# PDNode-600_Pro1.net
KiCad netlist of a schematic drawn in EAGLE
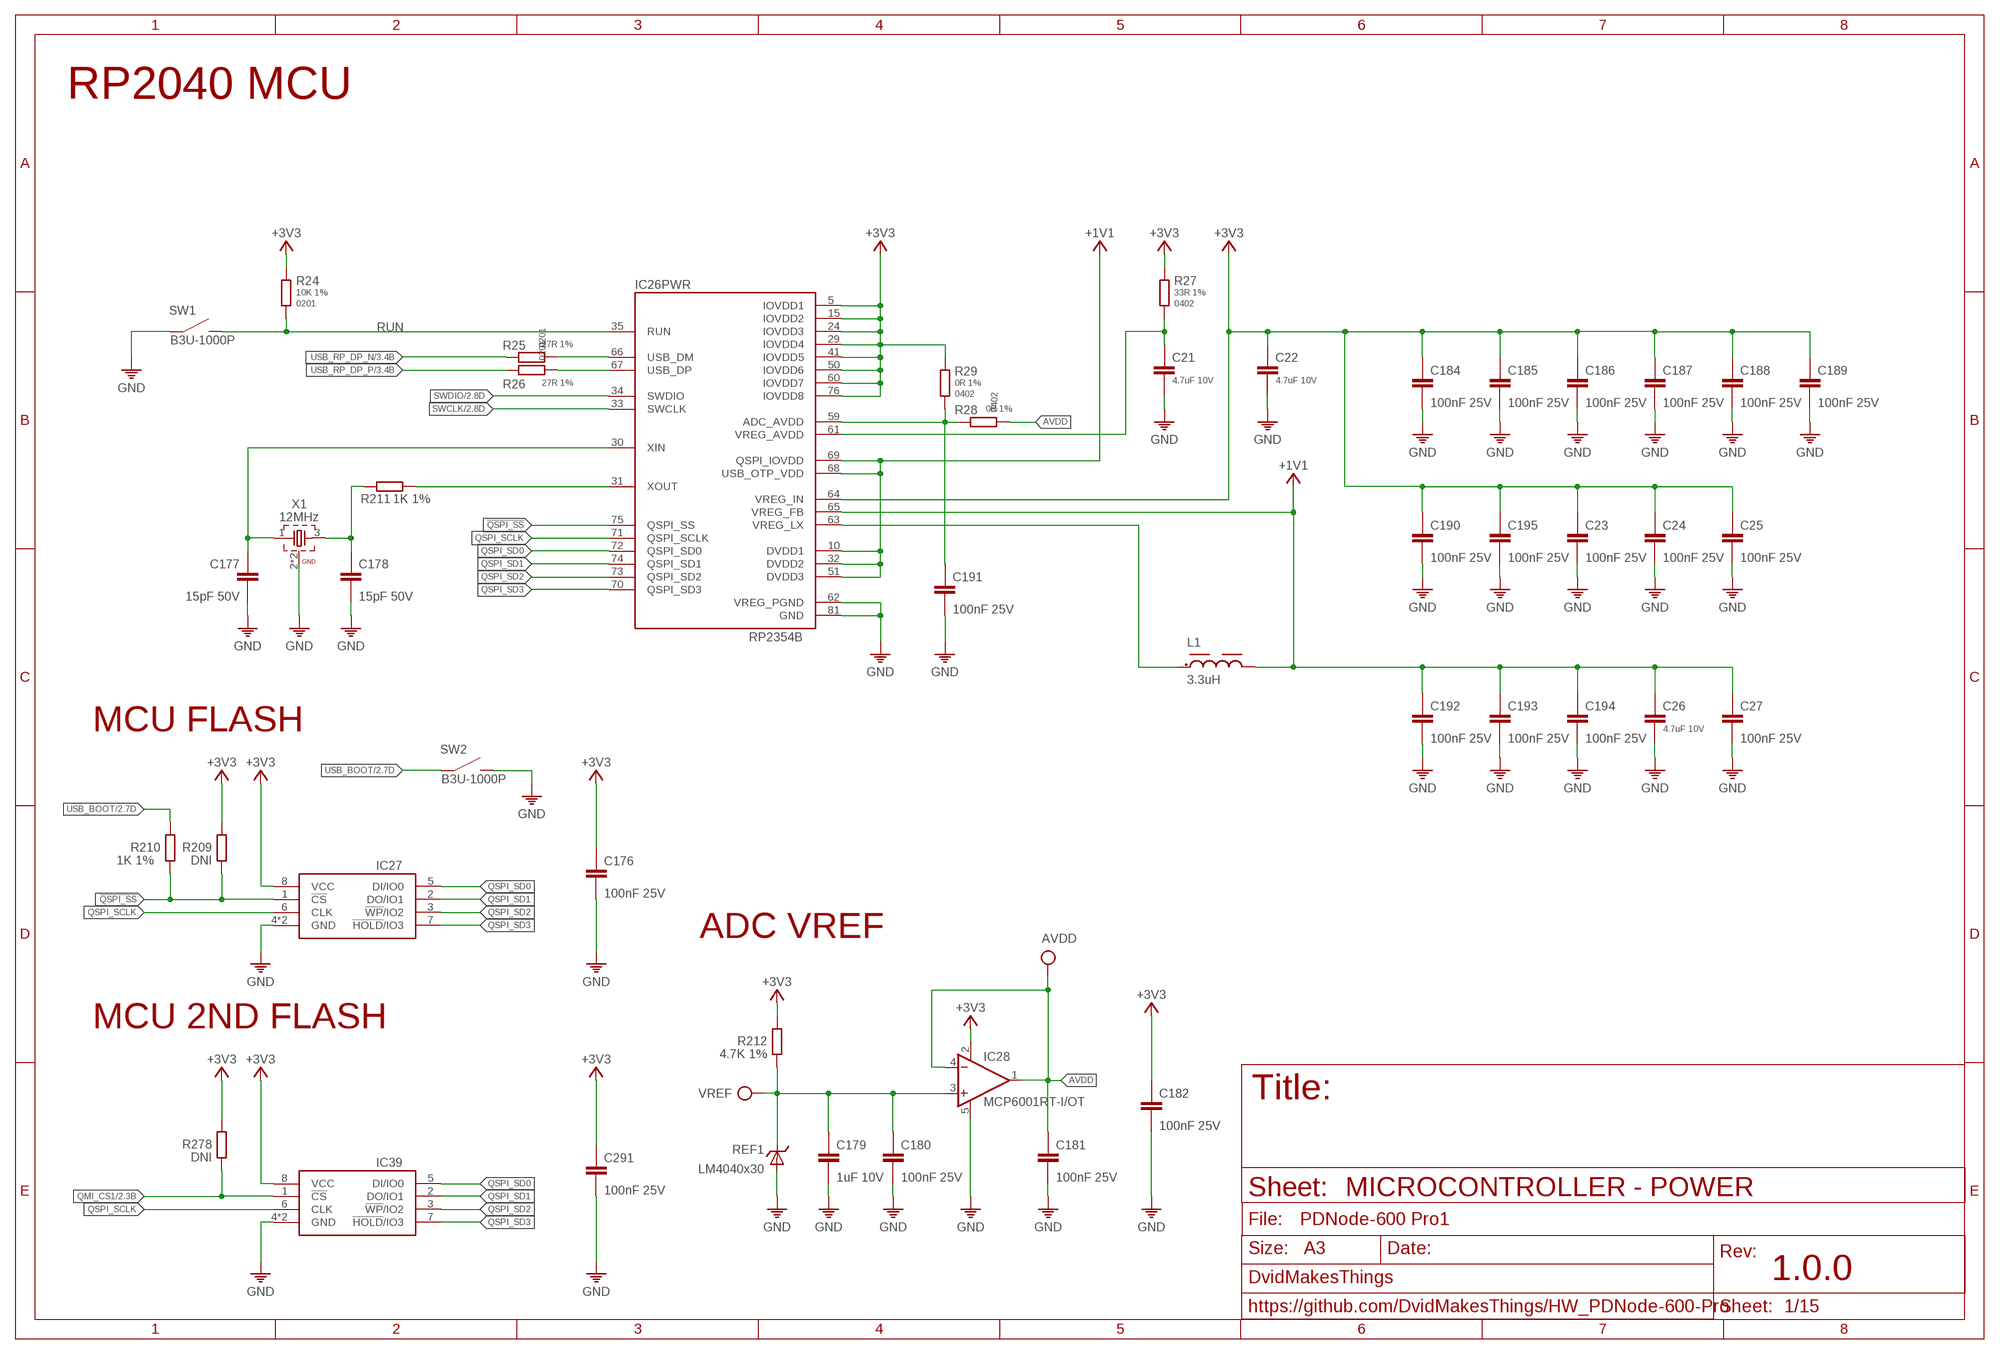
[diagram p0: schematic, sheet 1]
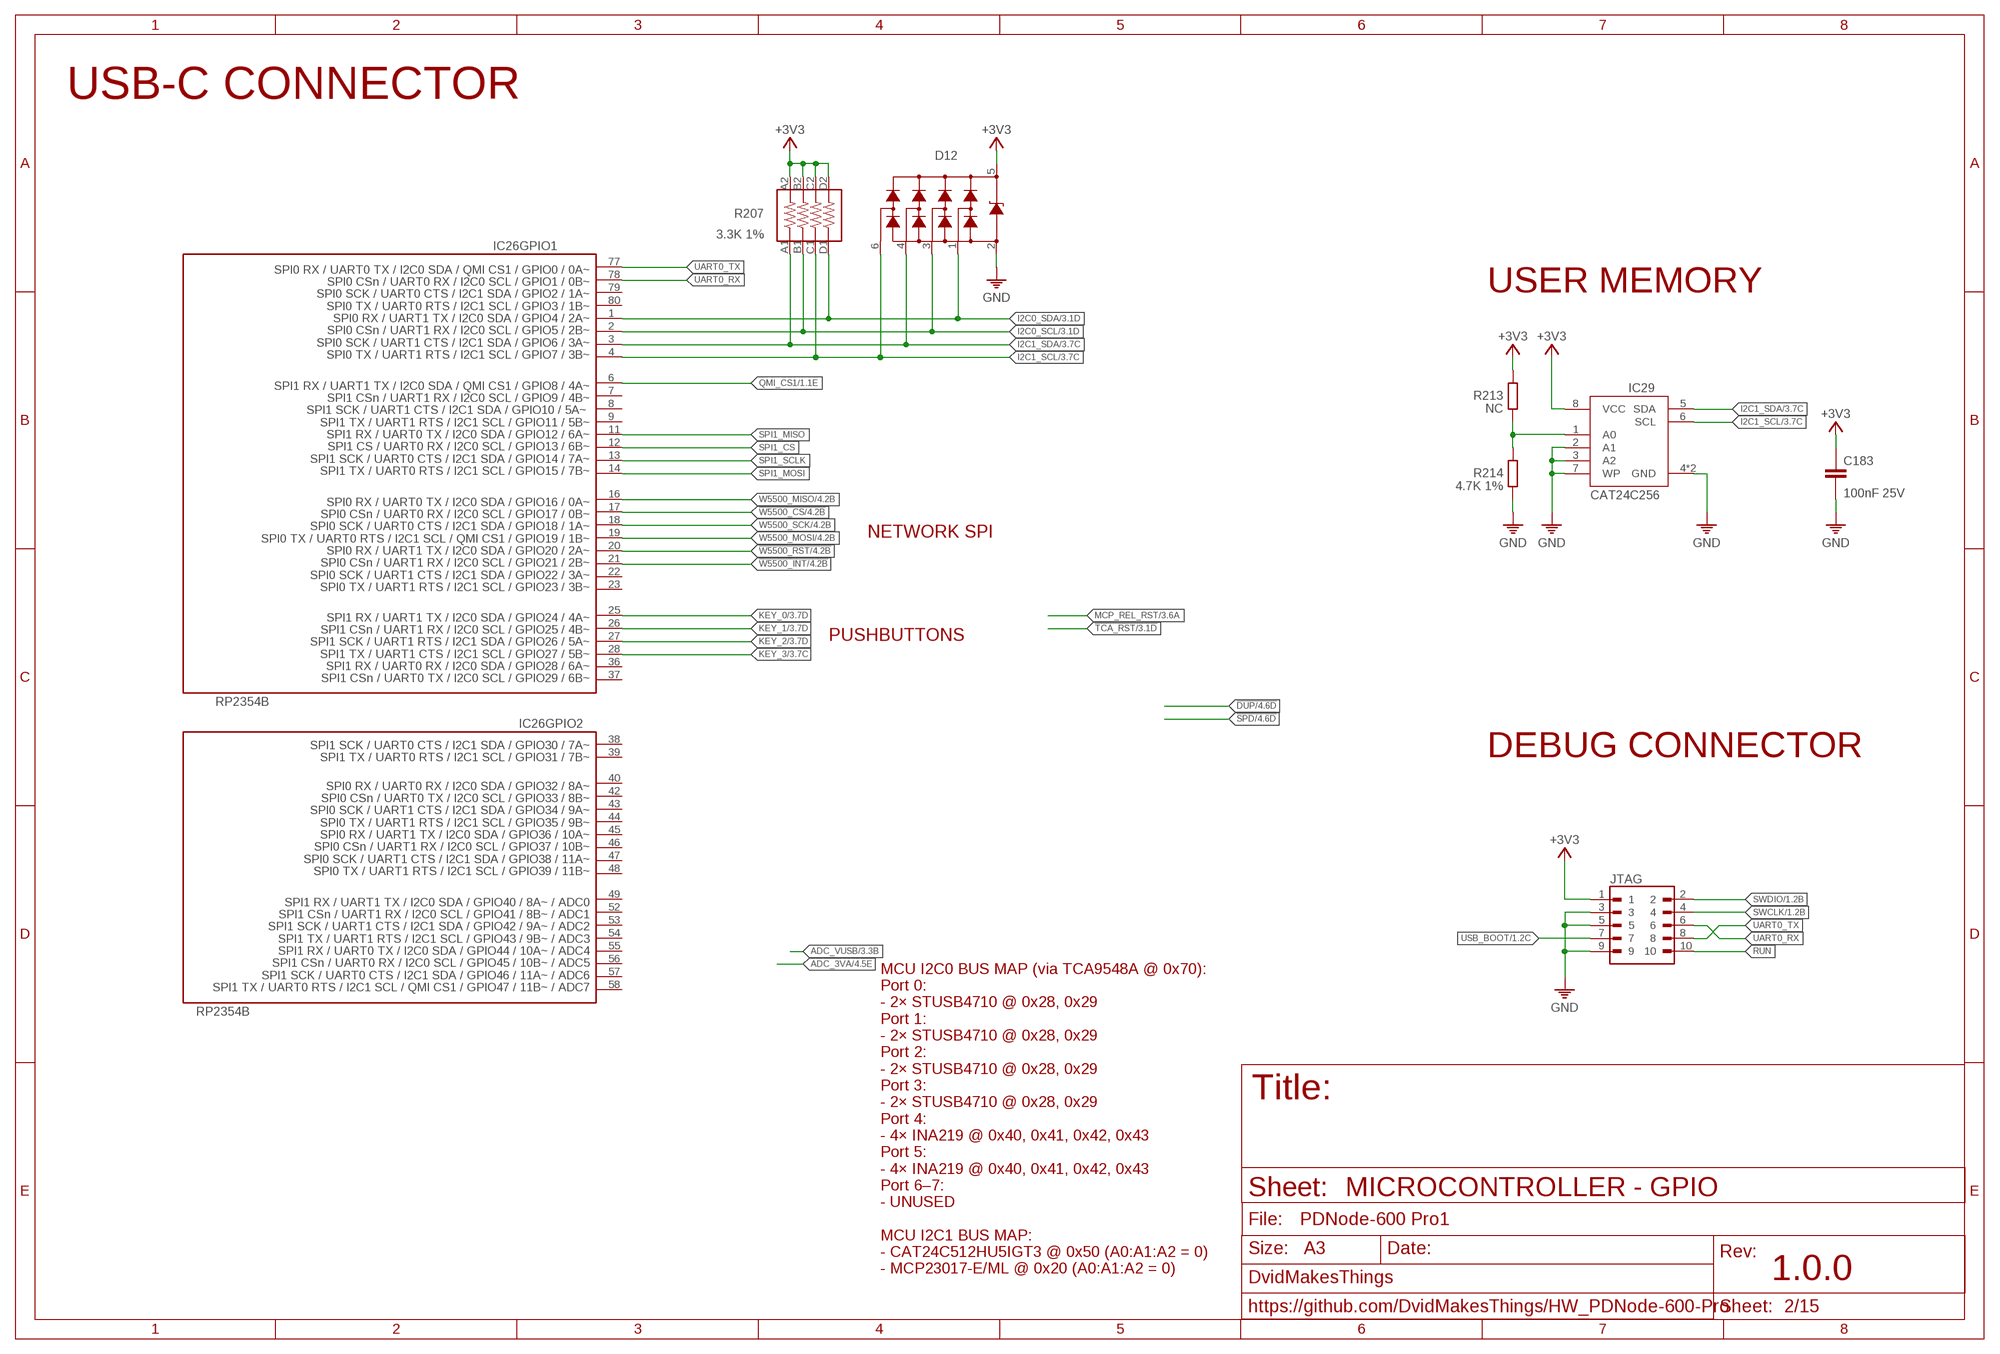
[diagram p1: schematic, sheet 2]
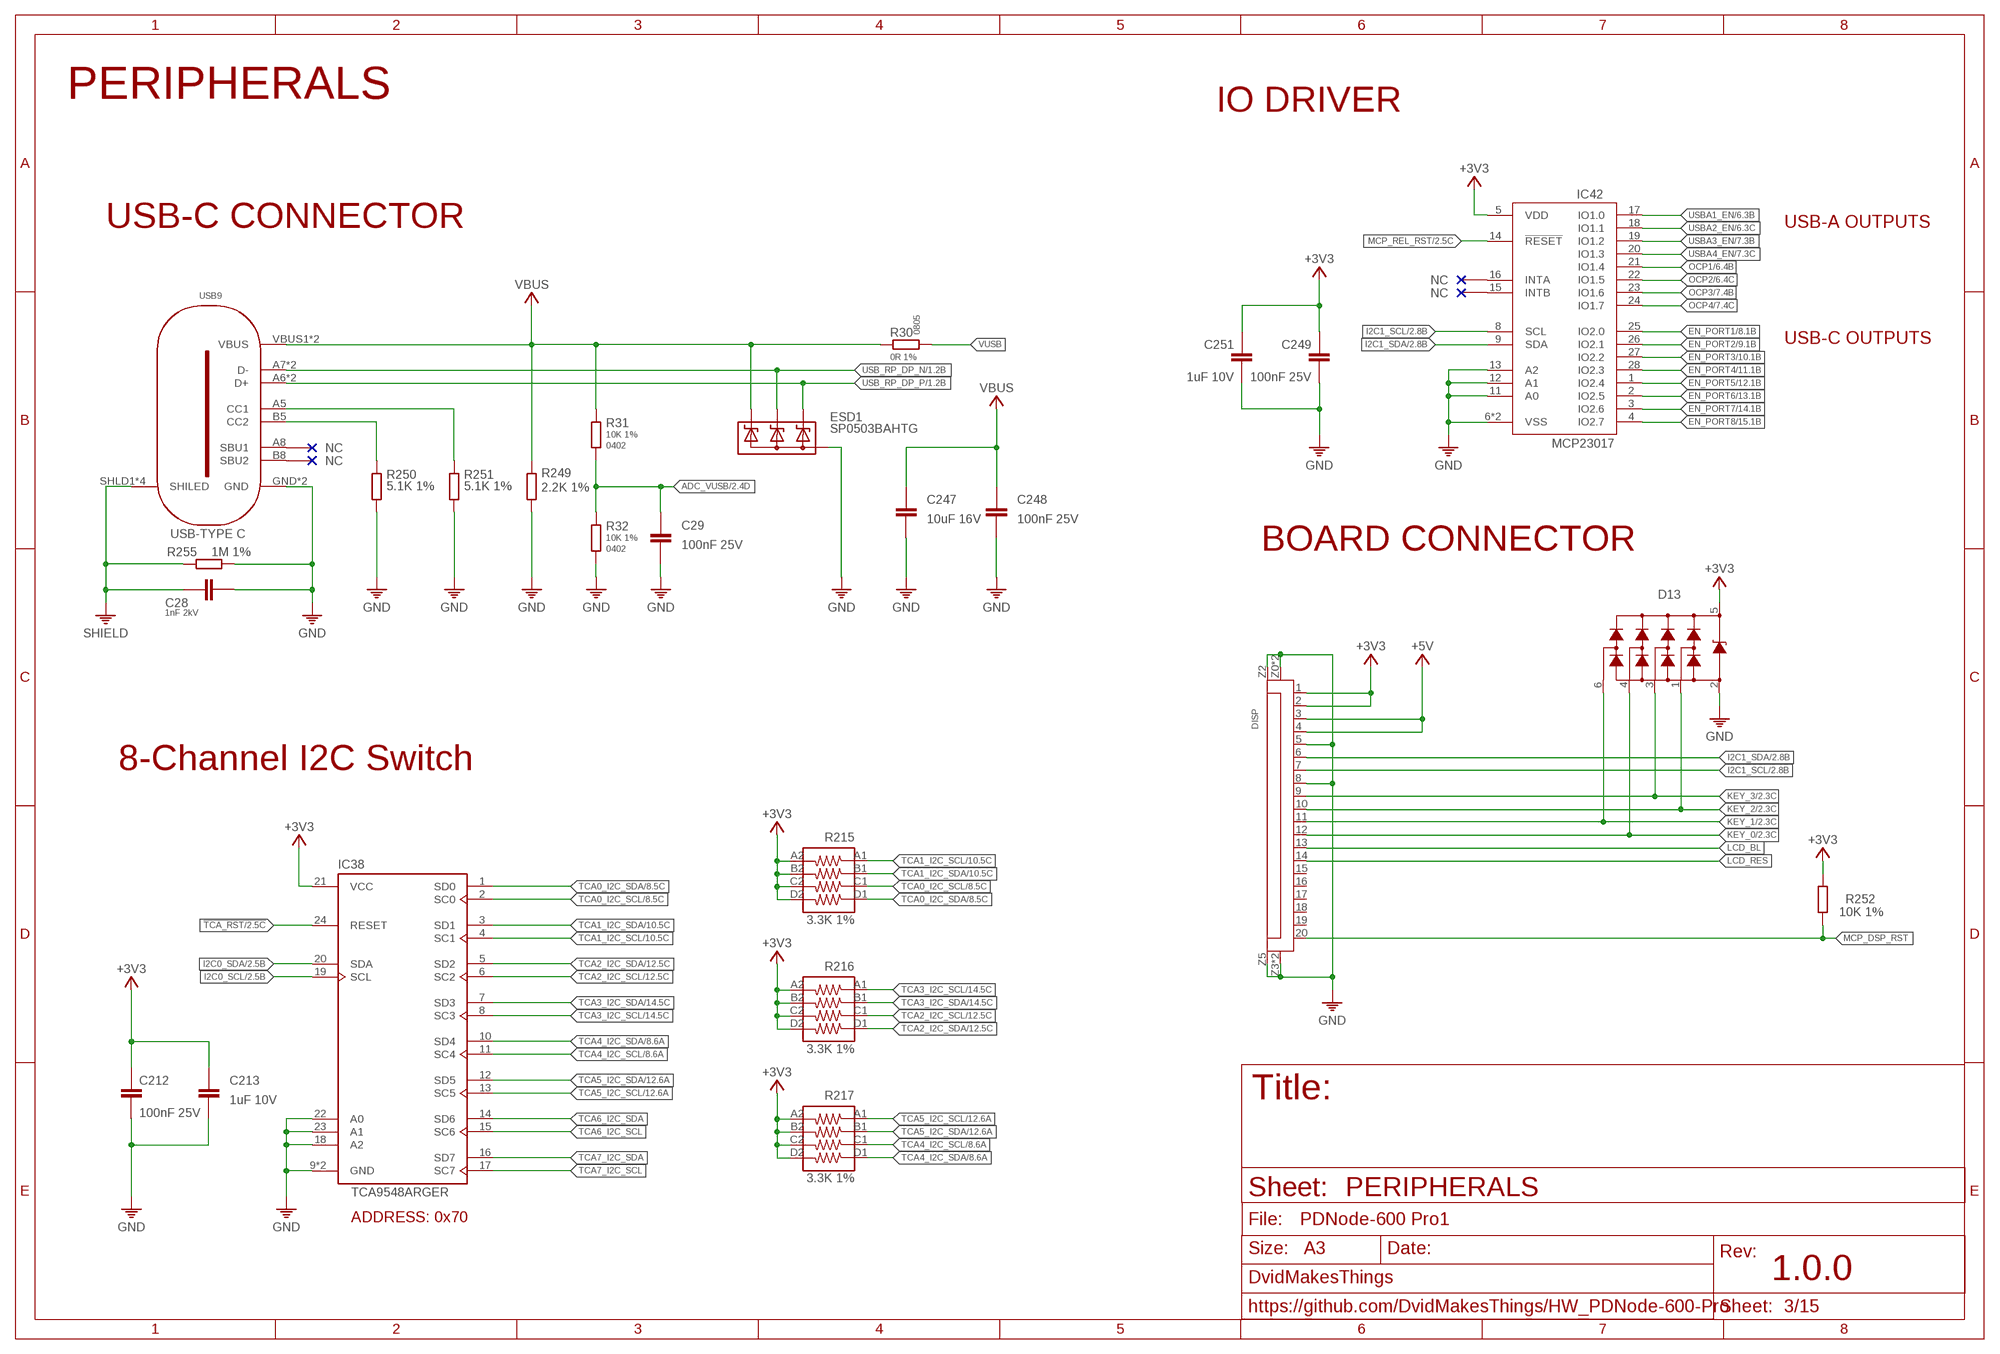
[diagram p2: schematic, sheet 3]
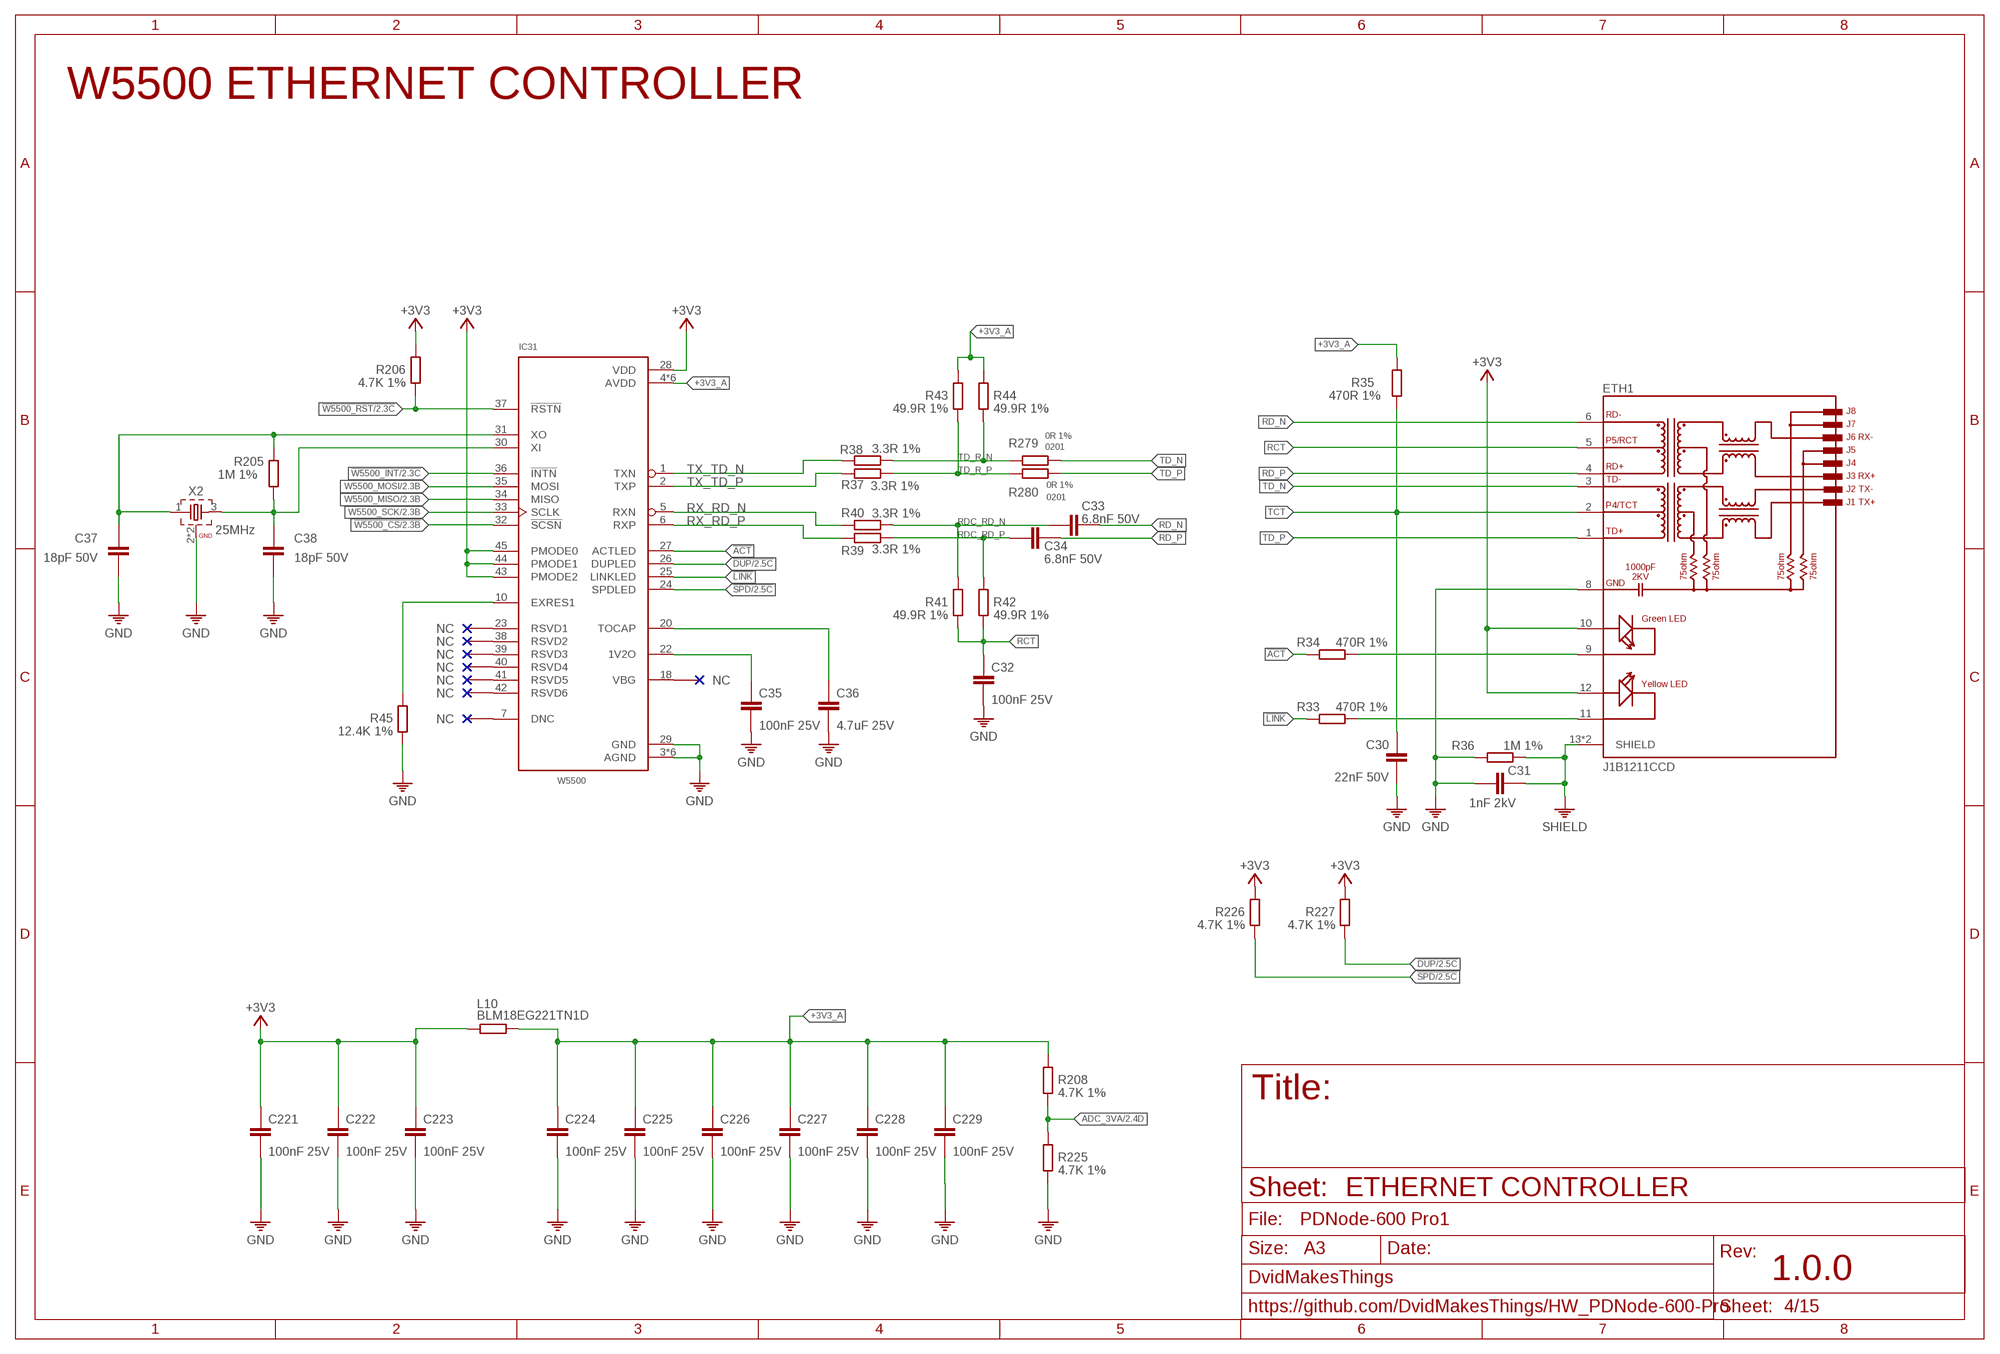
[diagram p3: schematic, sheet 4]
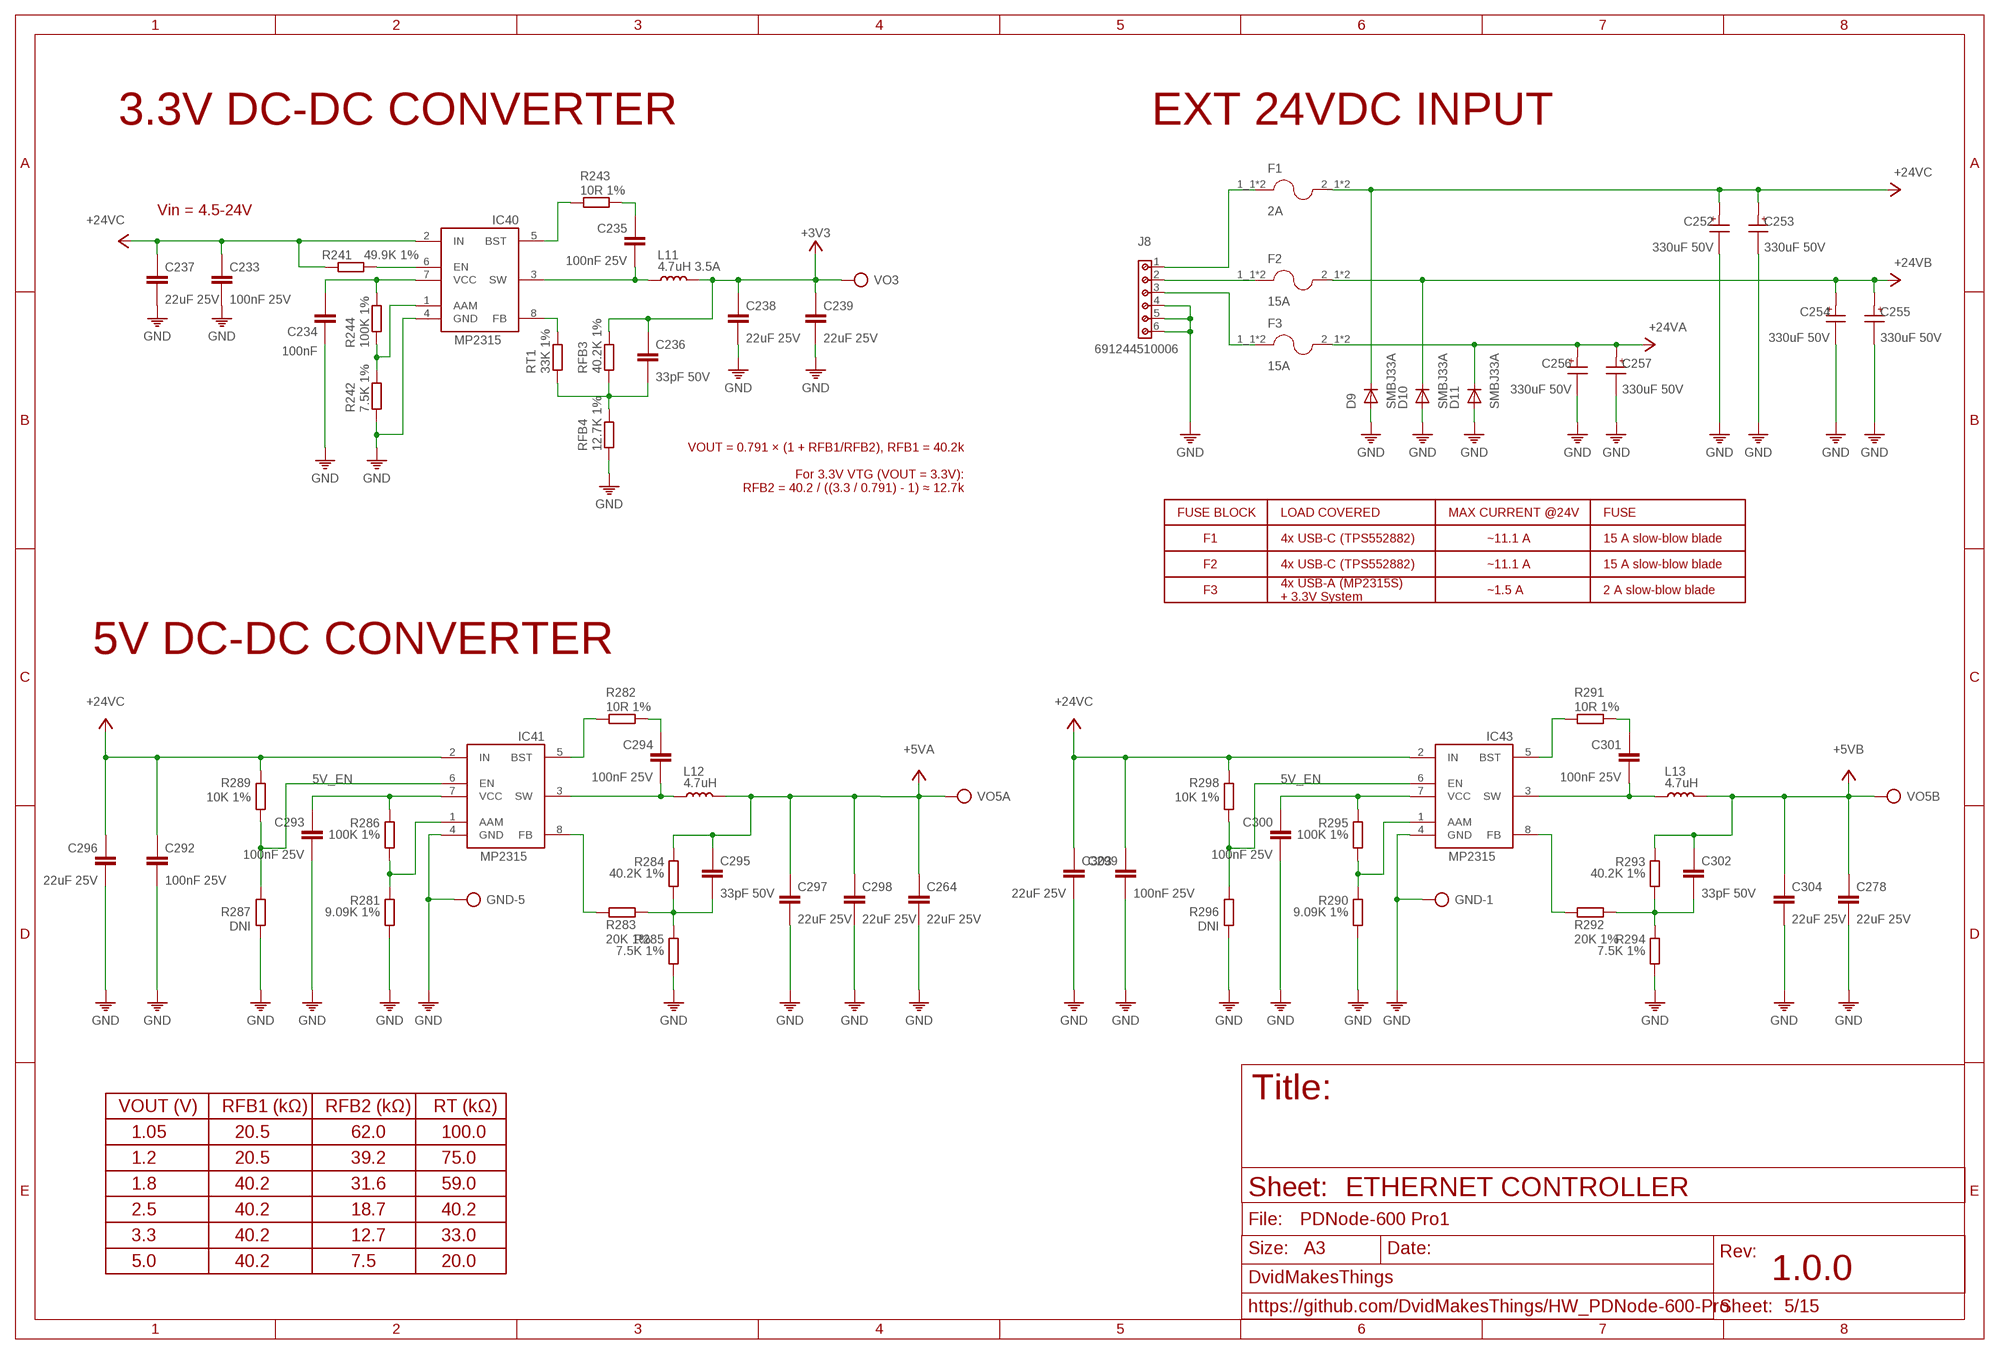
[diagram p4: schematic, sheet 5]
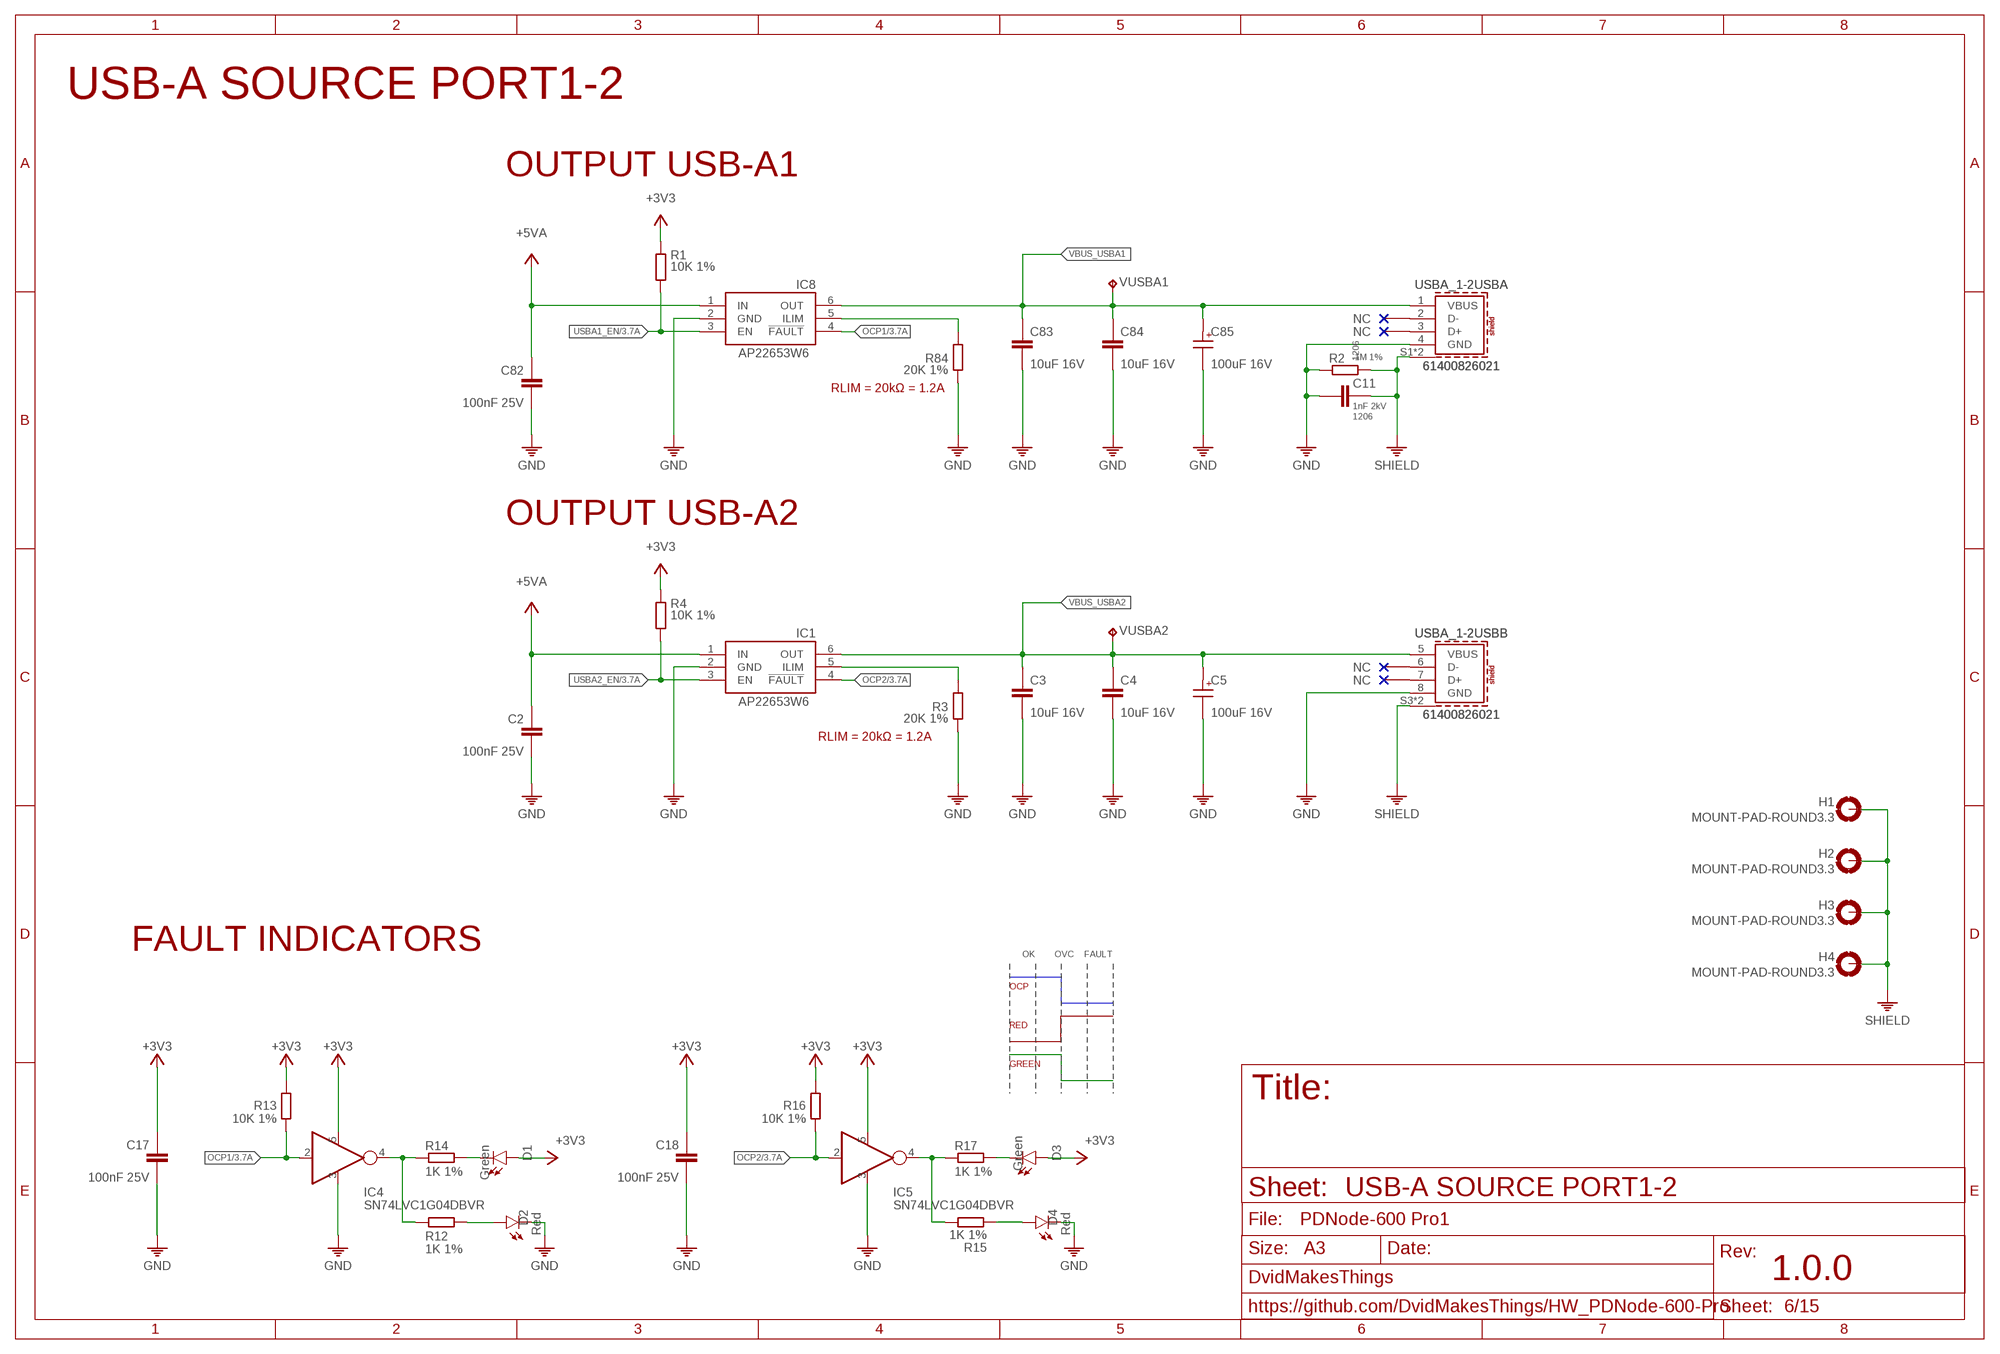
[diagram p5: schematic, sheet 6]
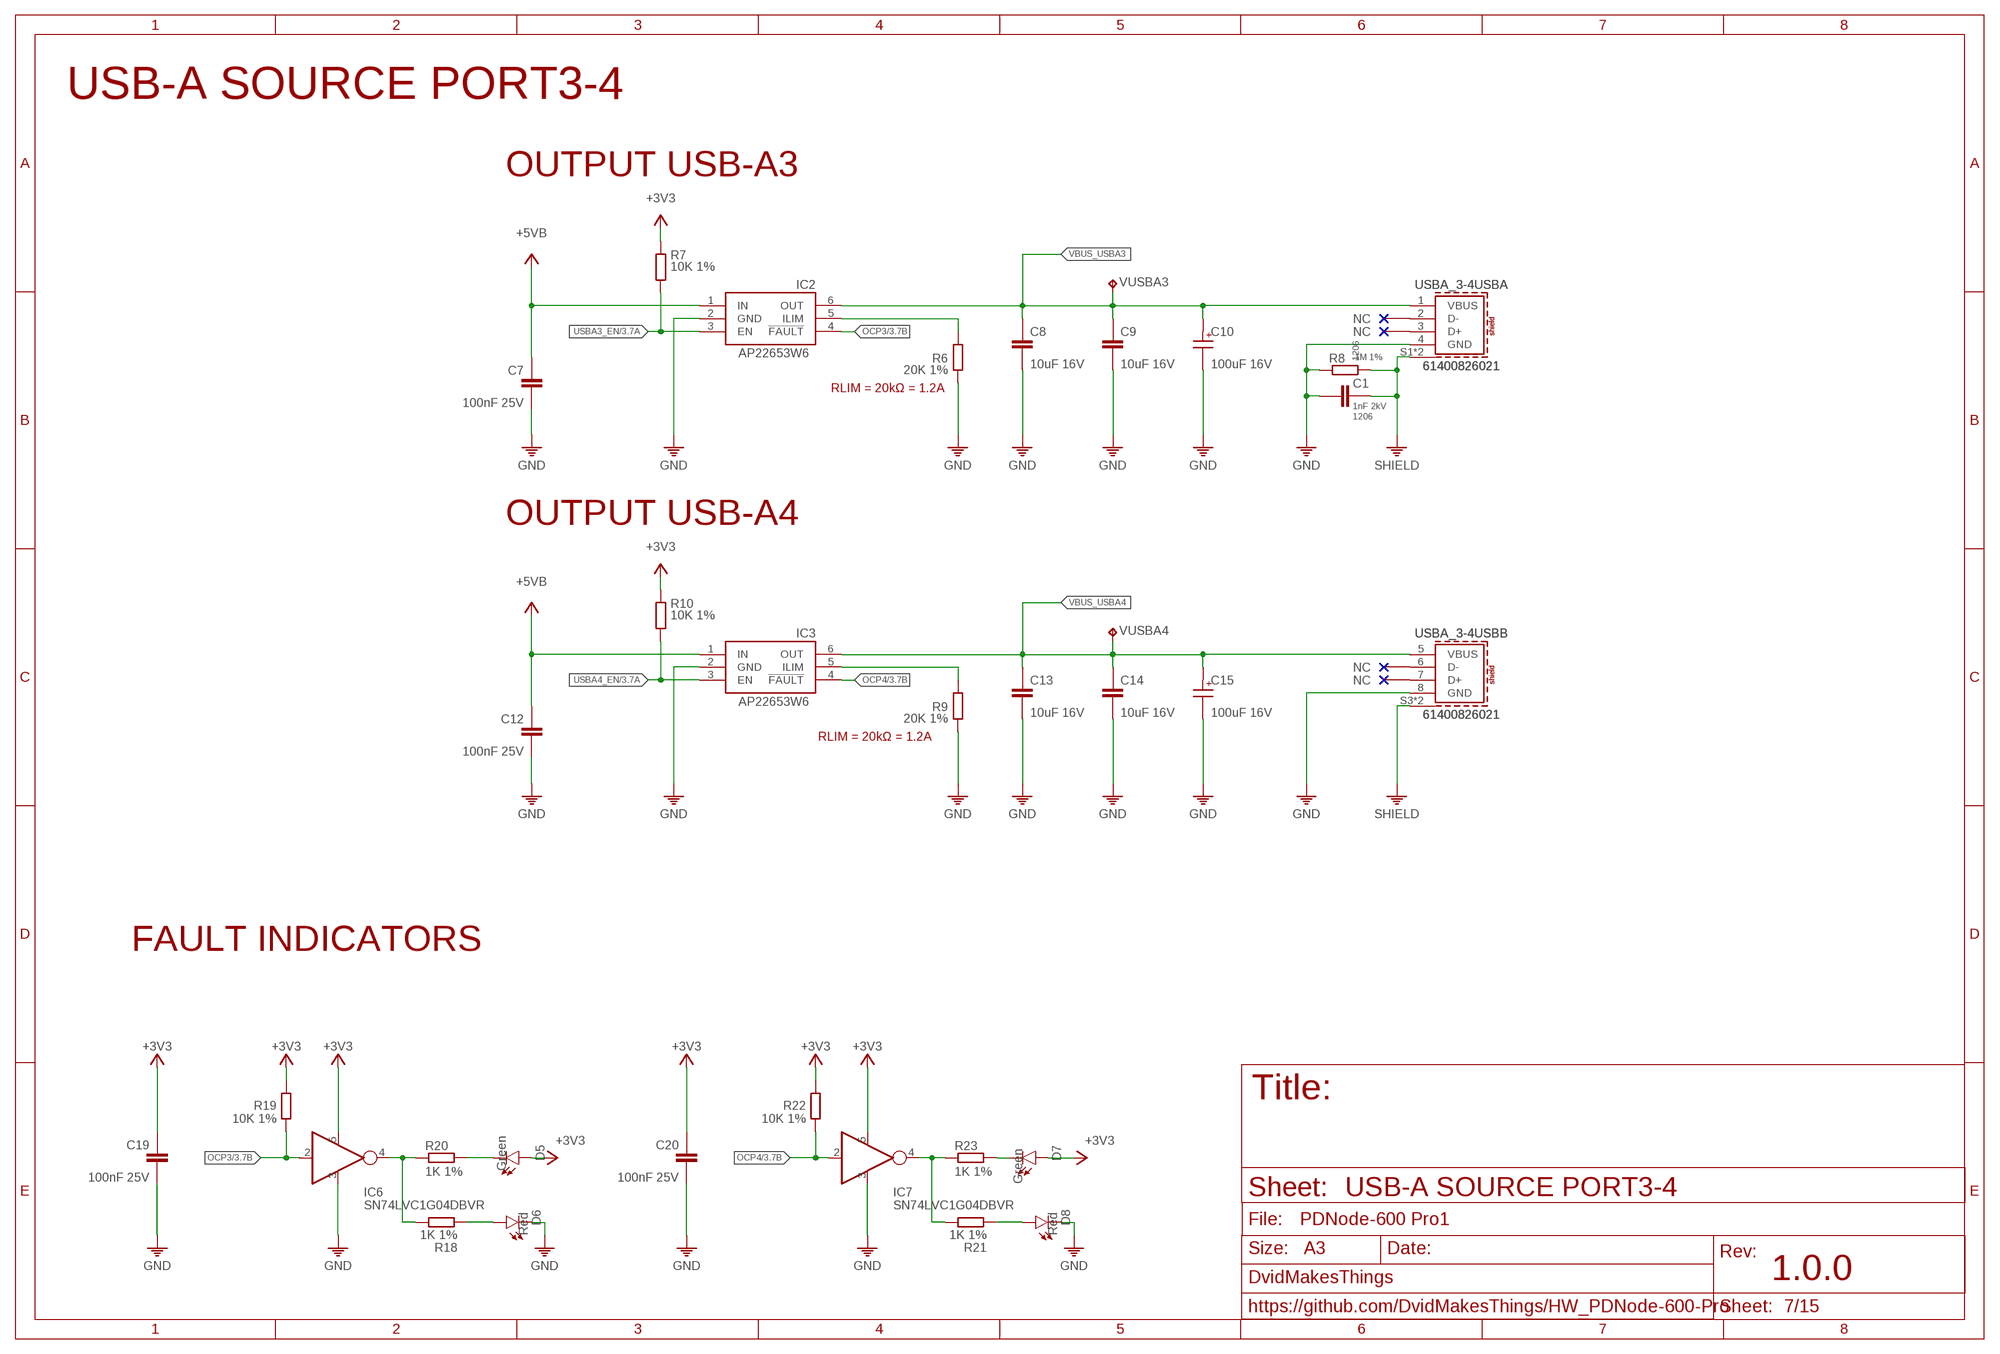
[diagram p6: schematic, sheet 7]
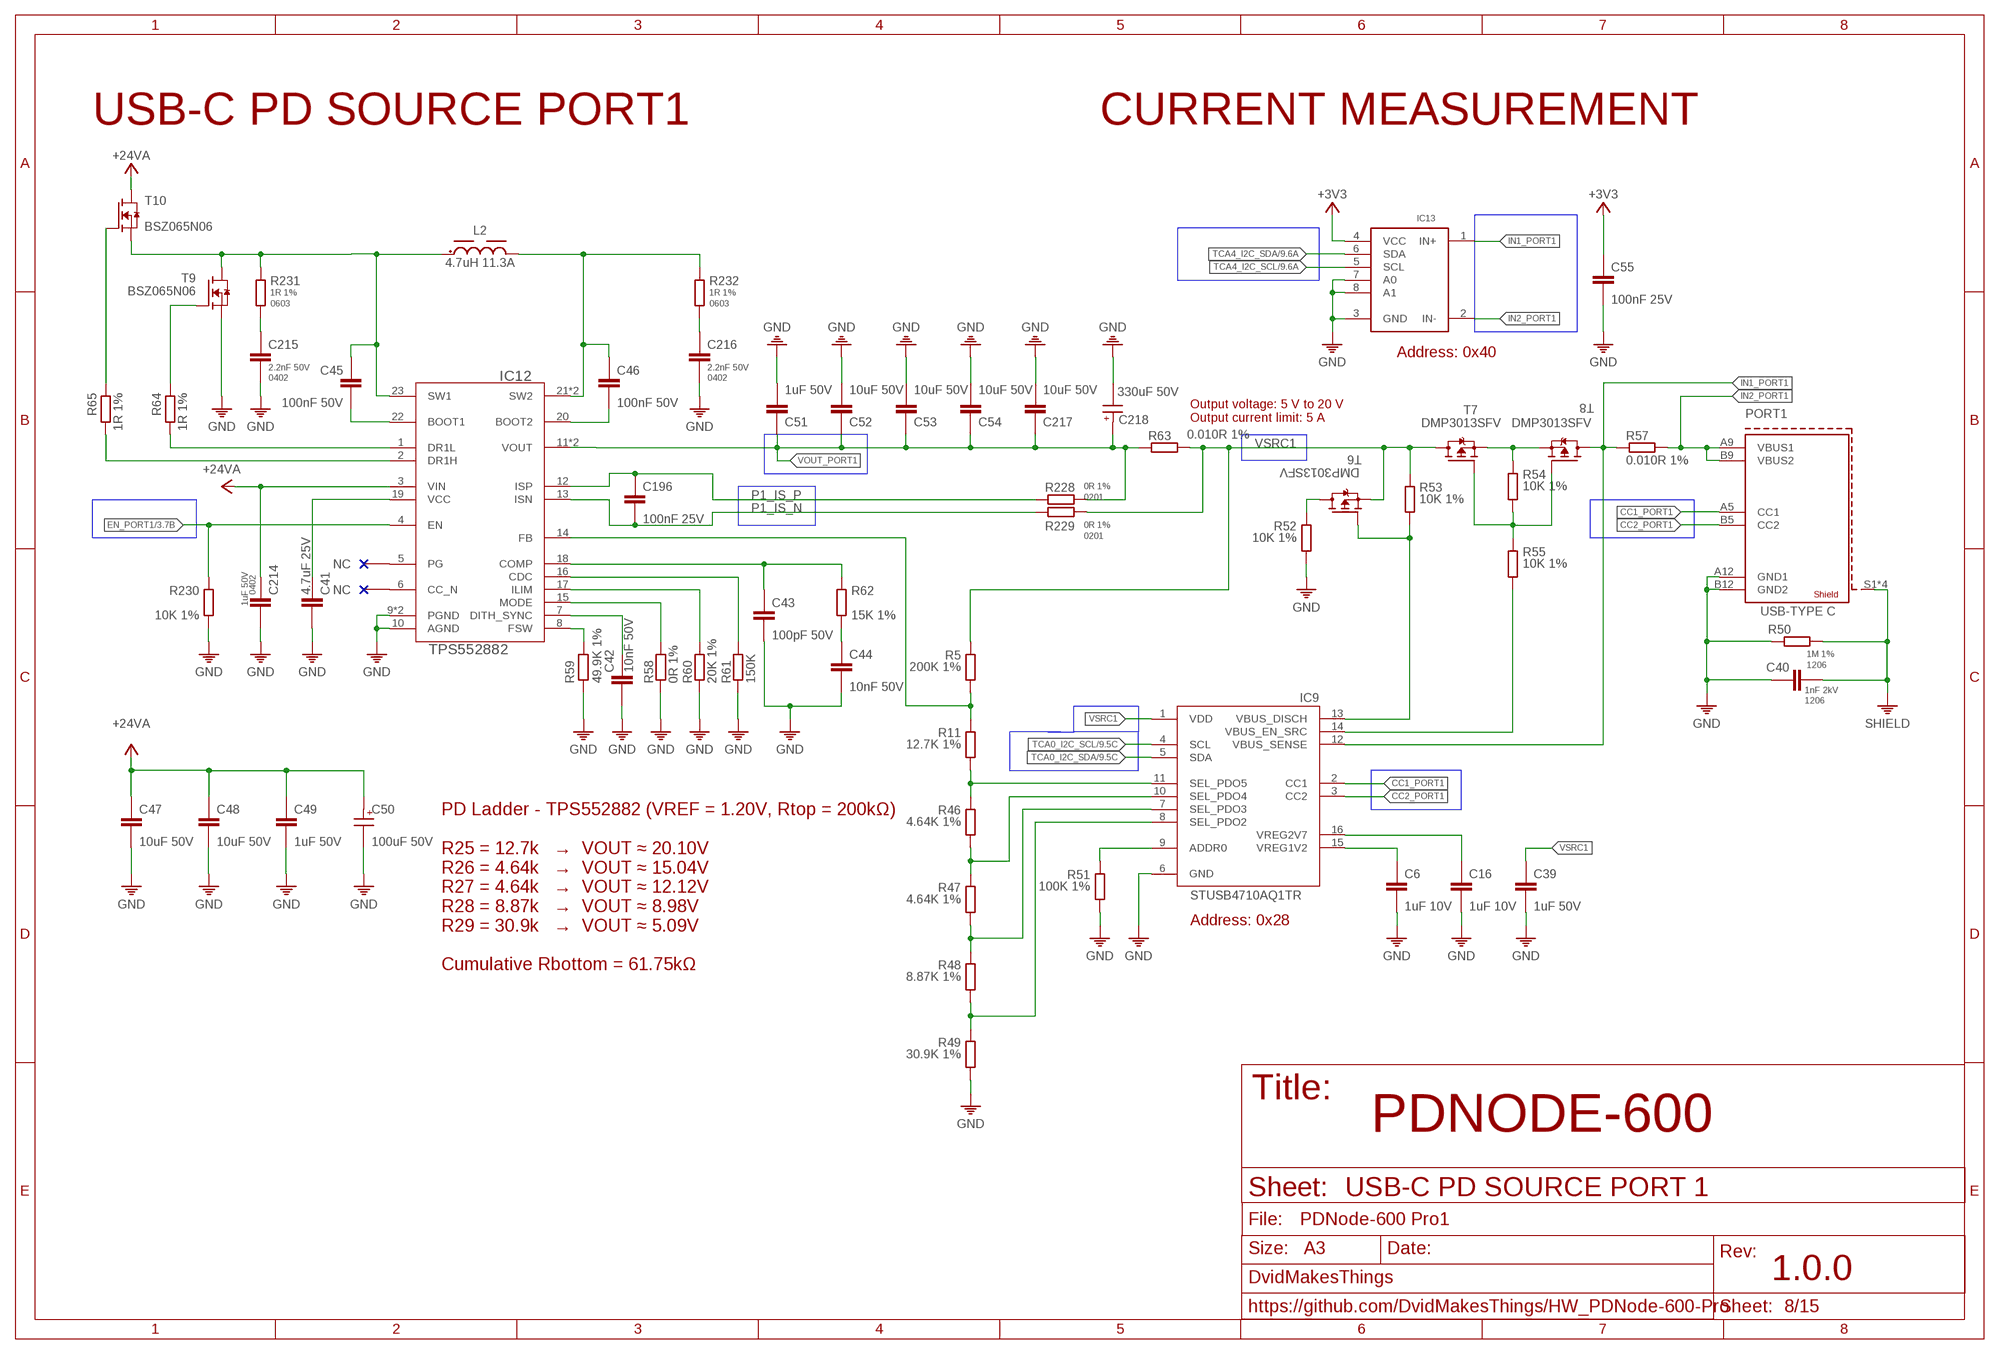
[diagram p7: schematic, sheet 8]
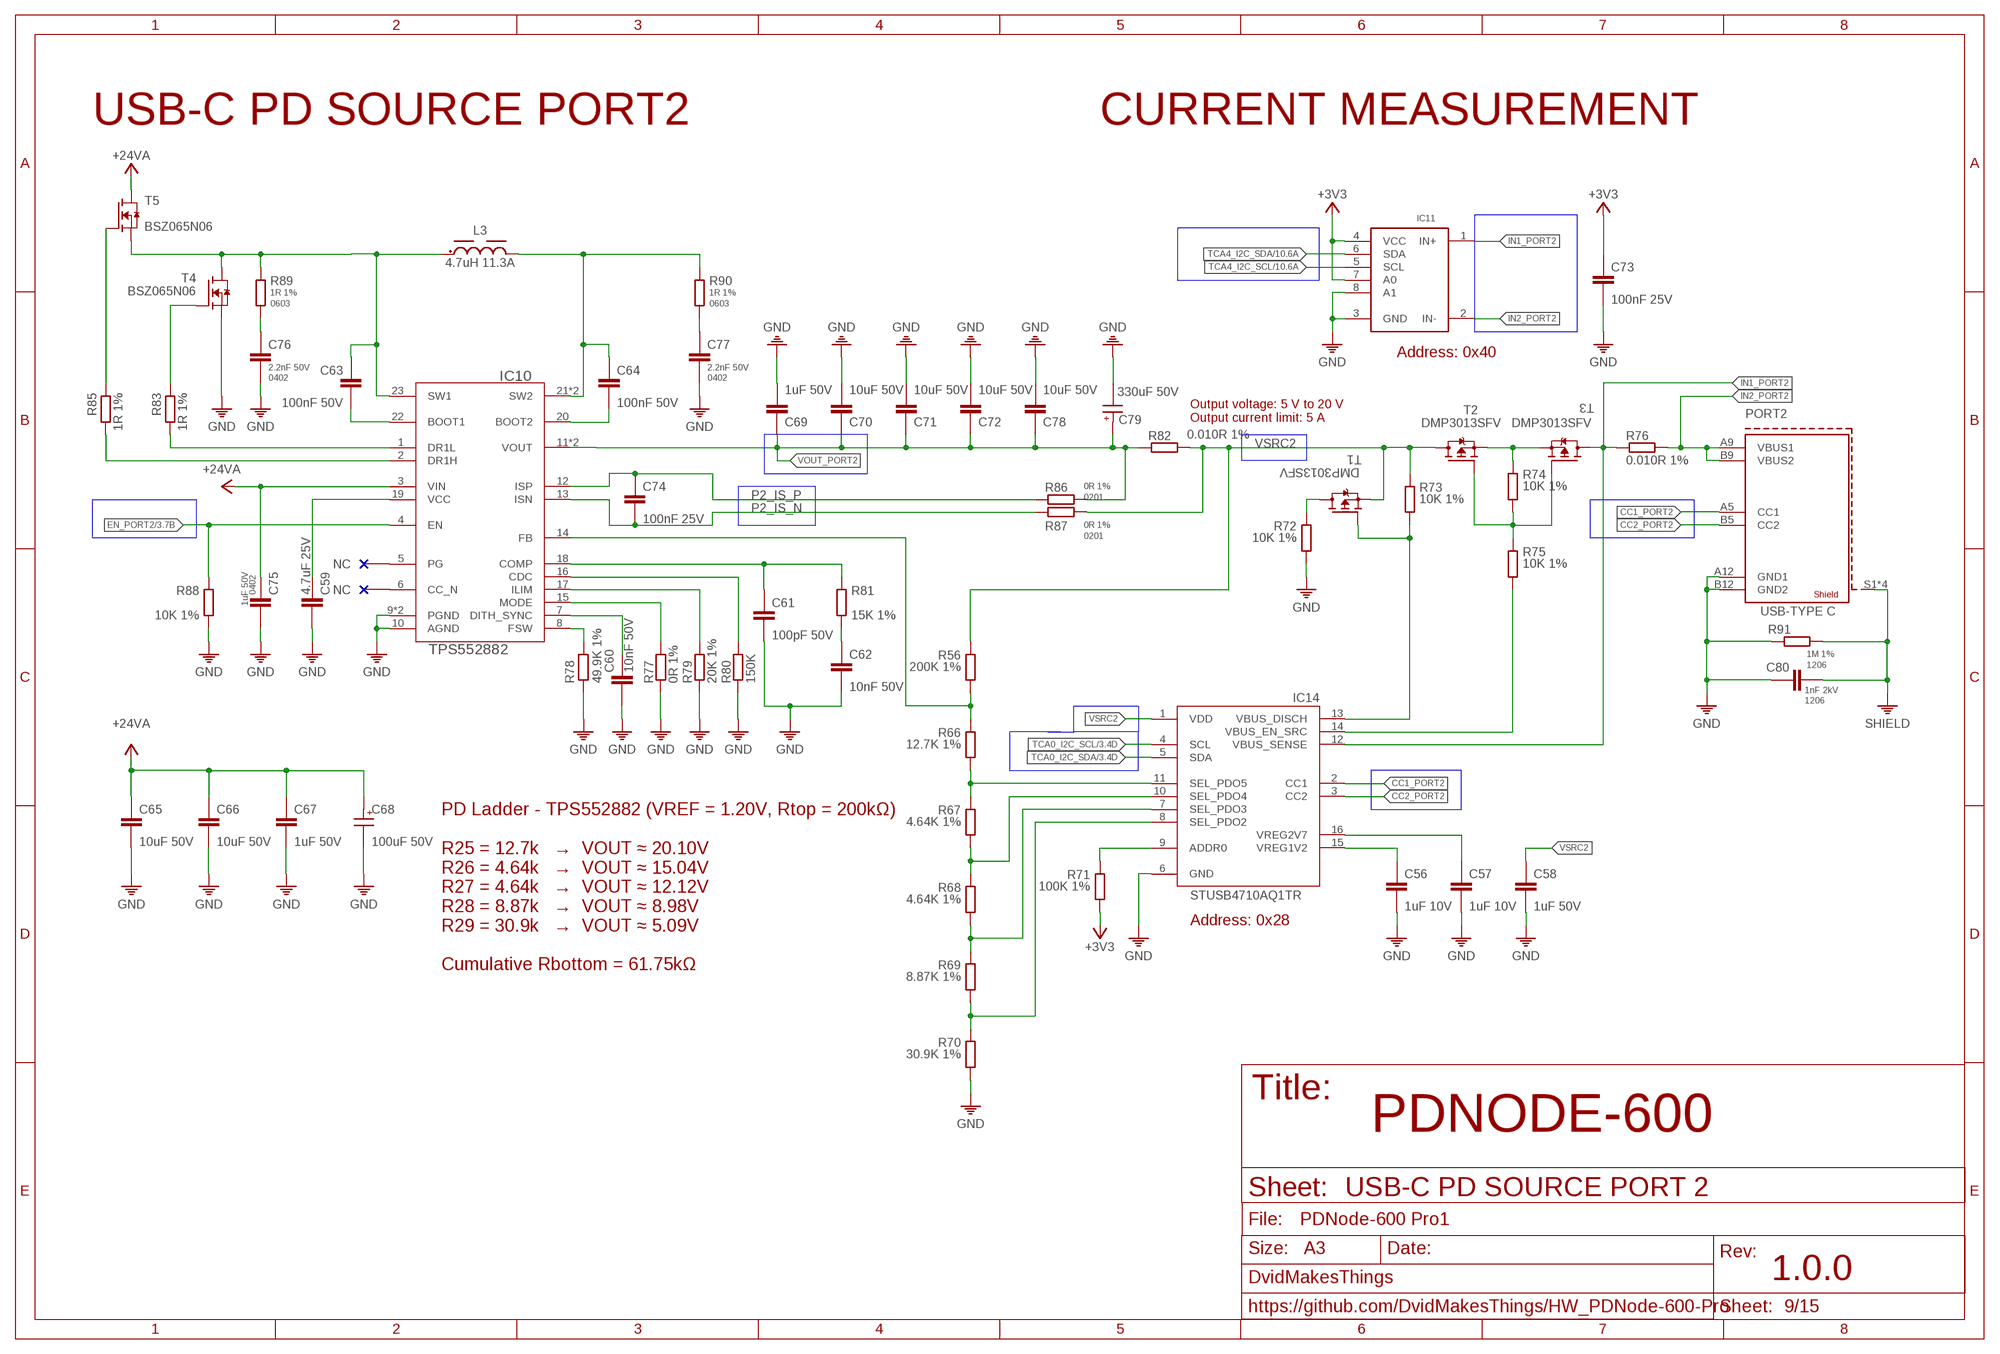
[diagram p8: schematic, sheet 9]
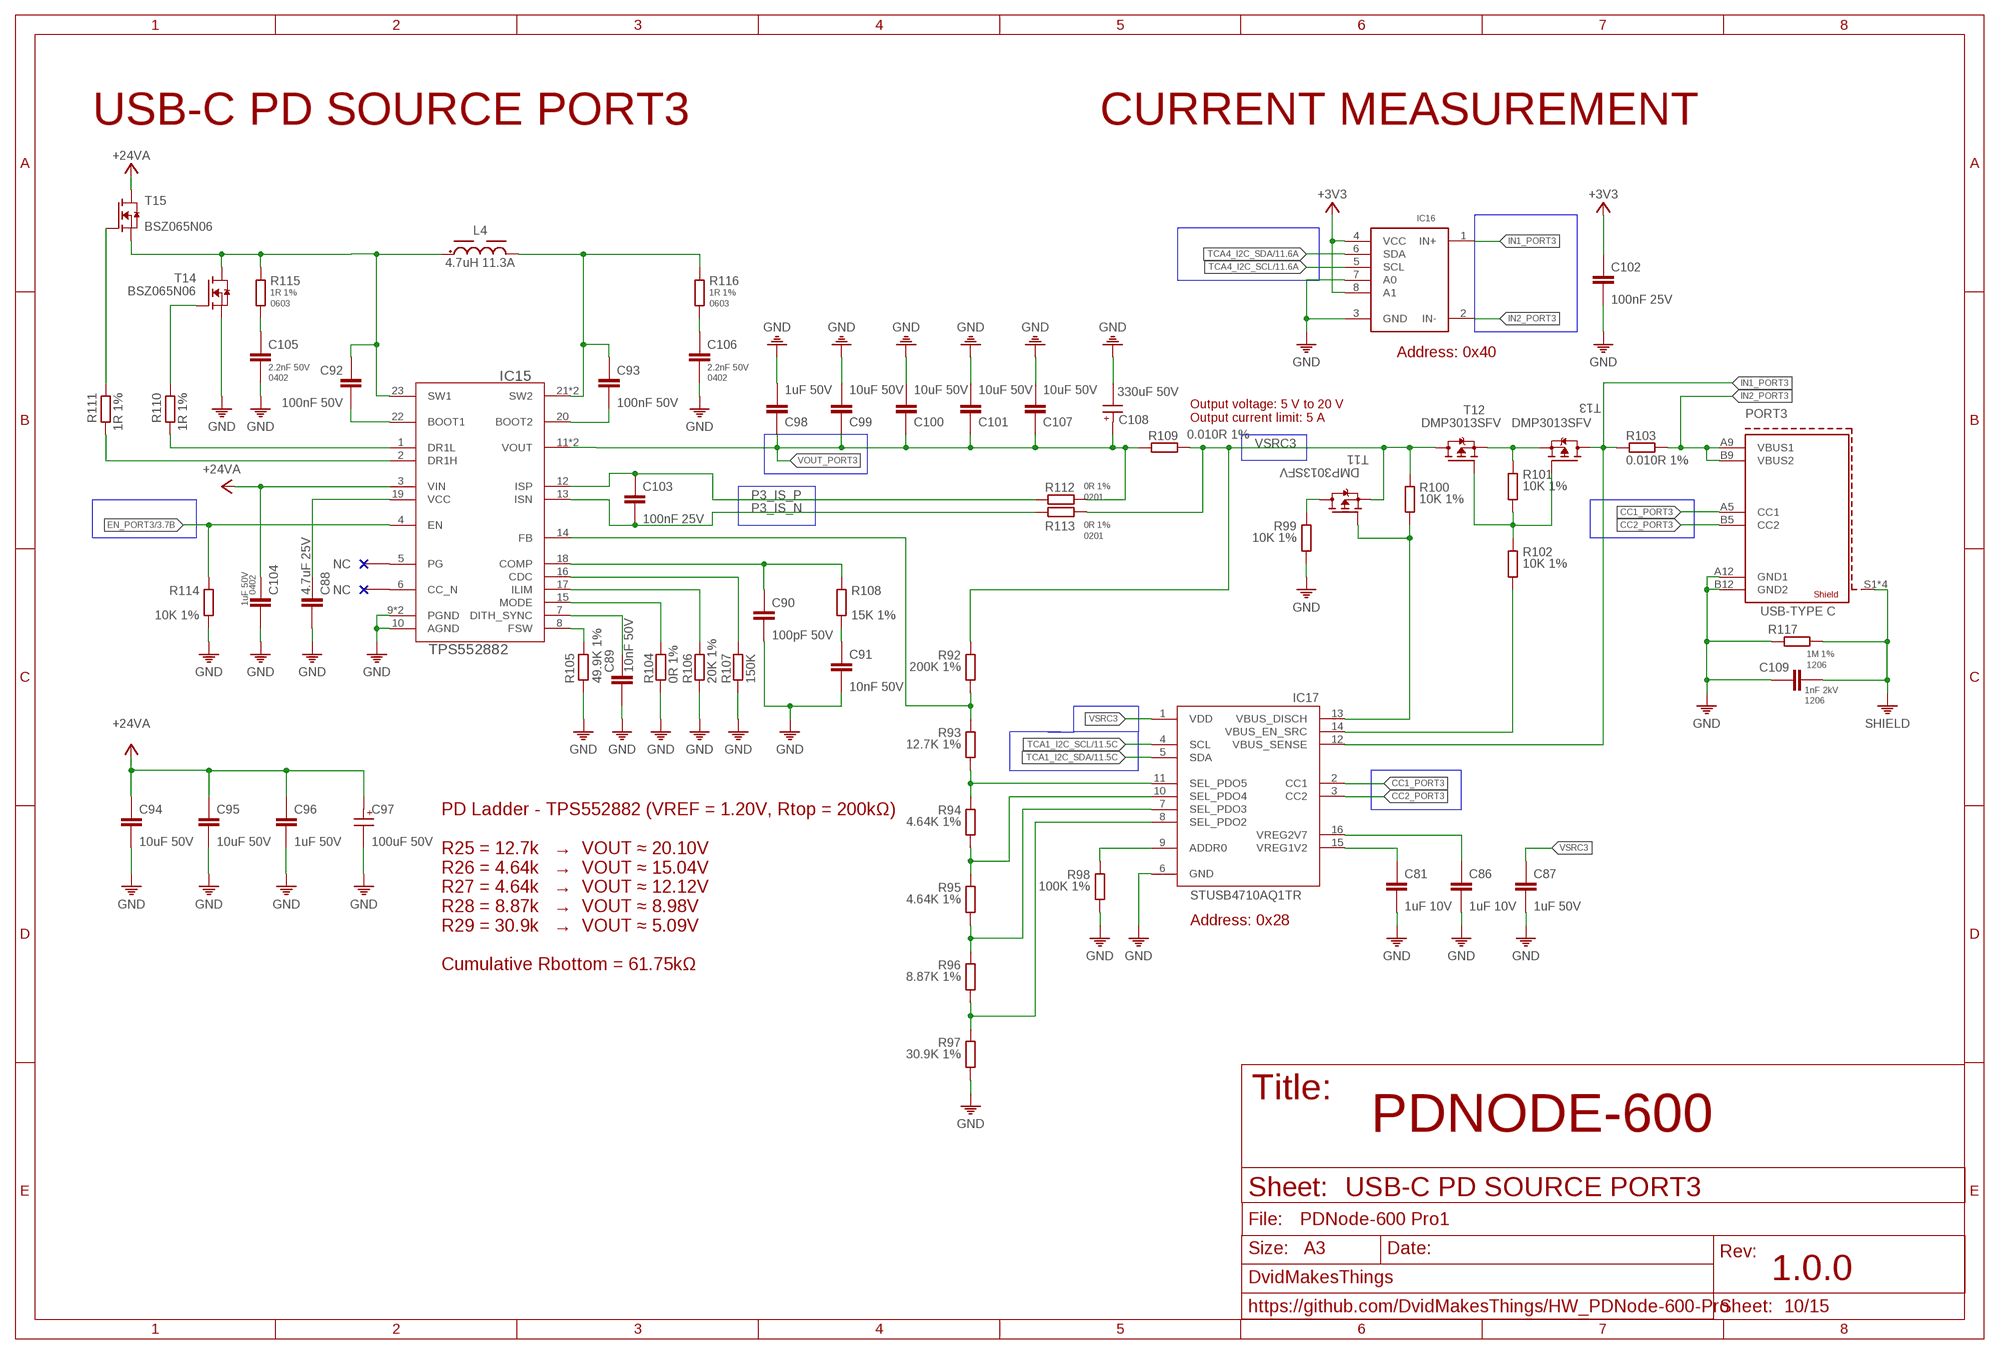
[diagram p9: schematic, sheet 10]
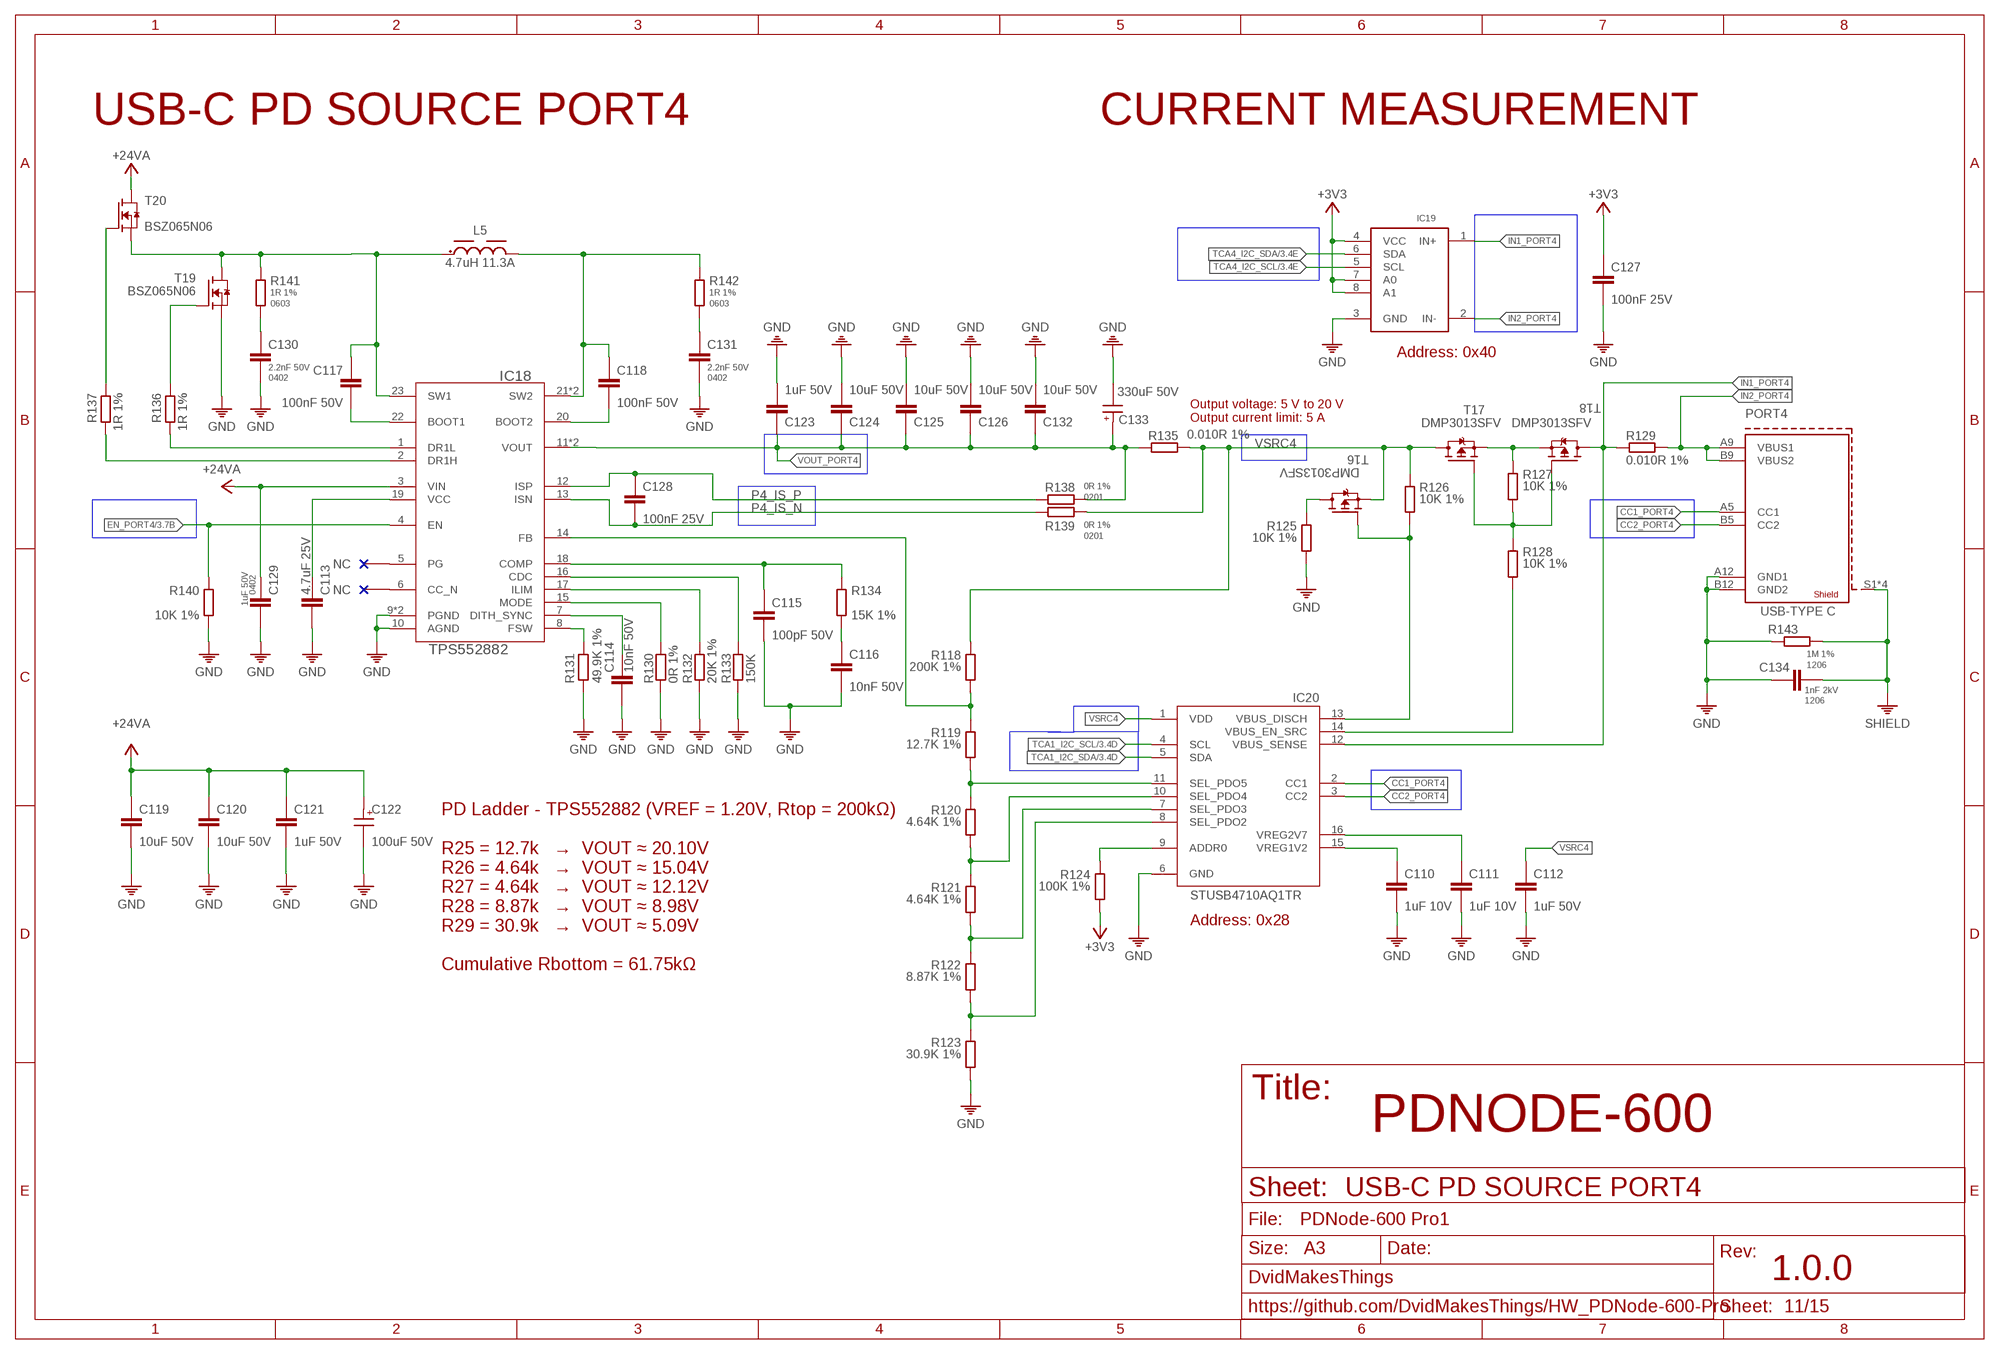
[diagram p10: schematic, sheet 11]
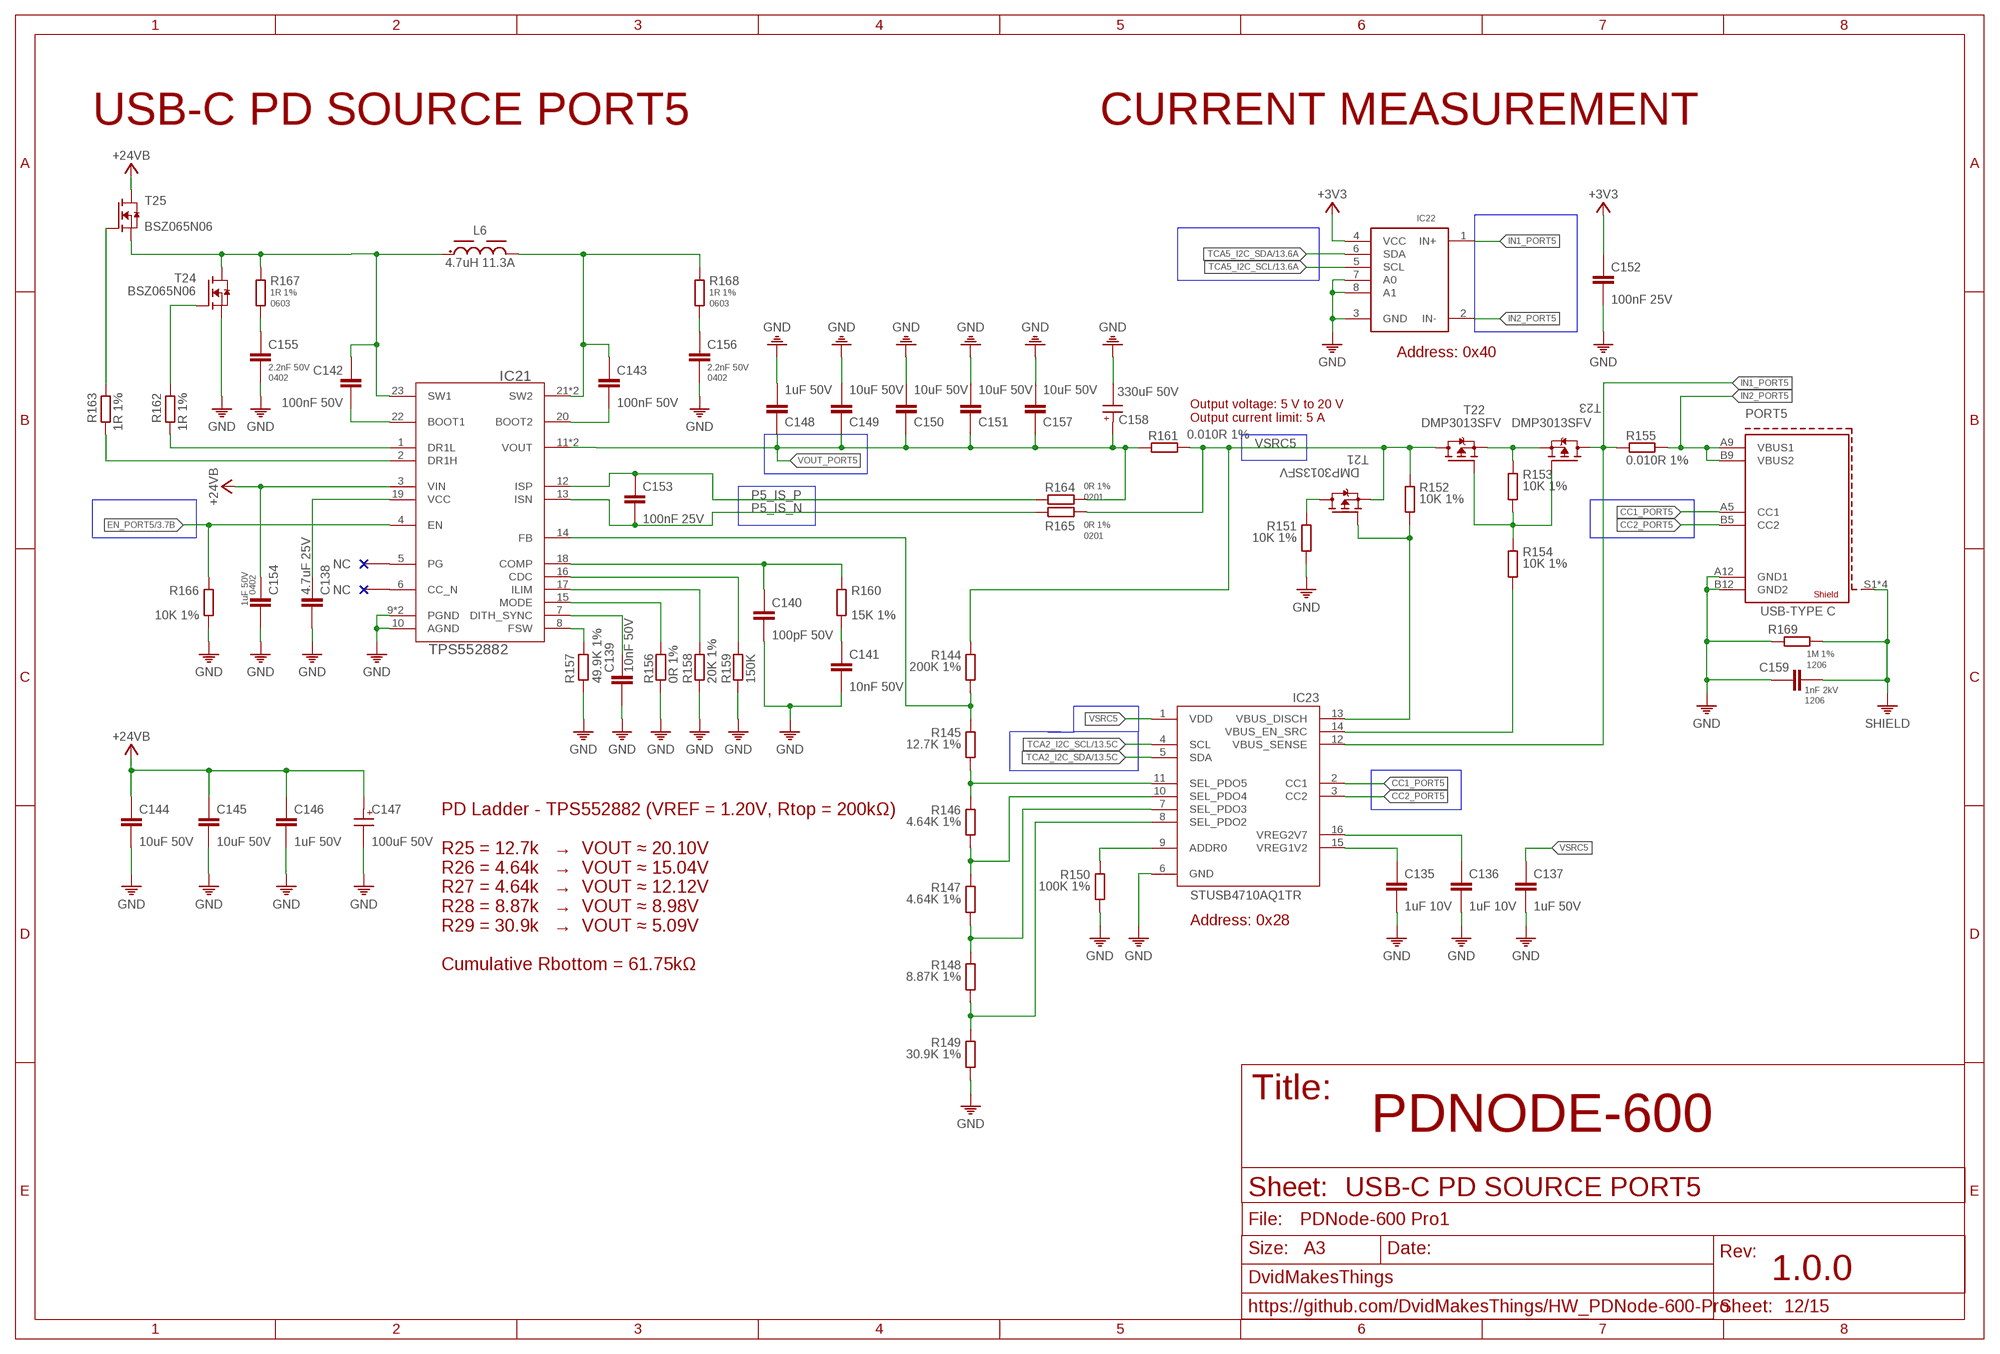
[diagram p11: schematic, sheet 12]
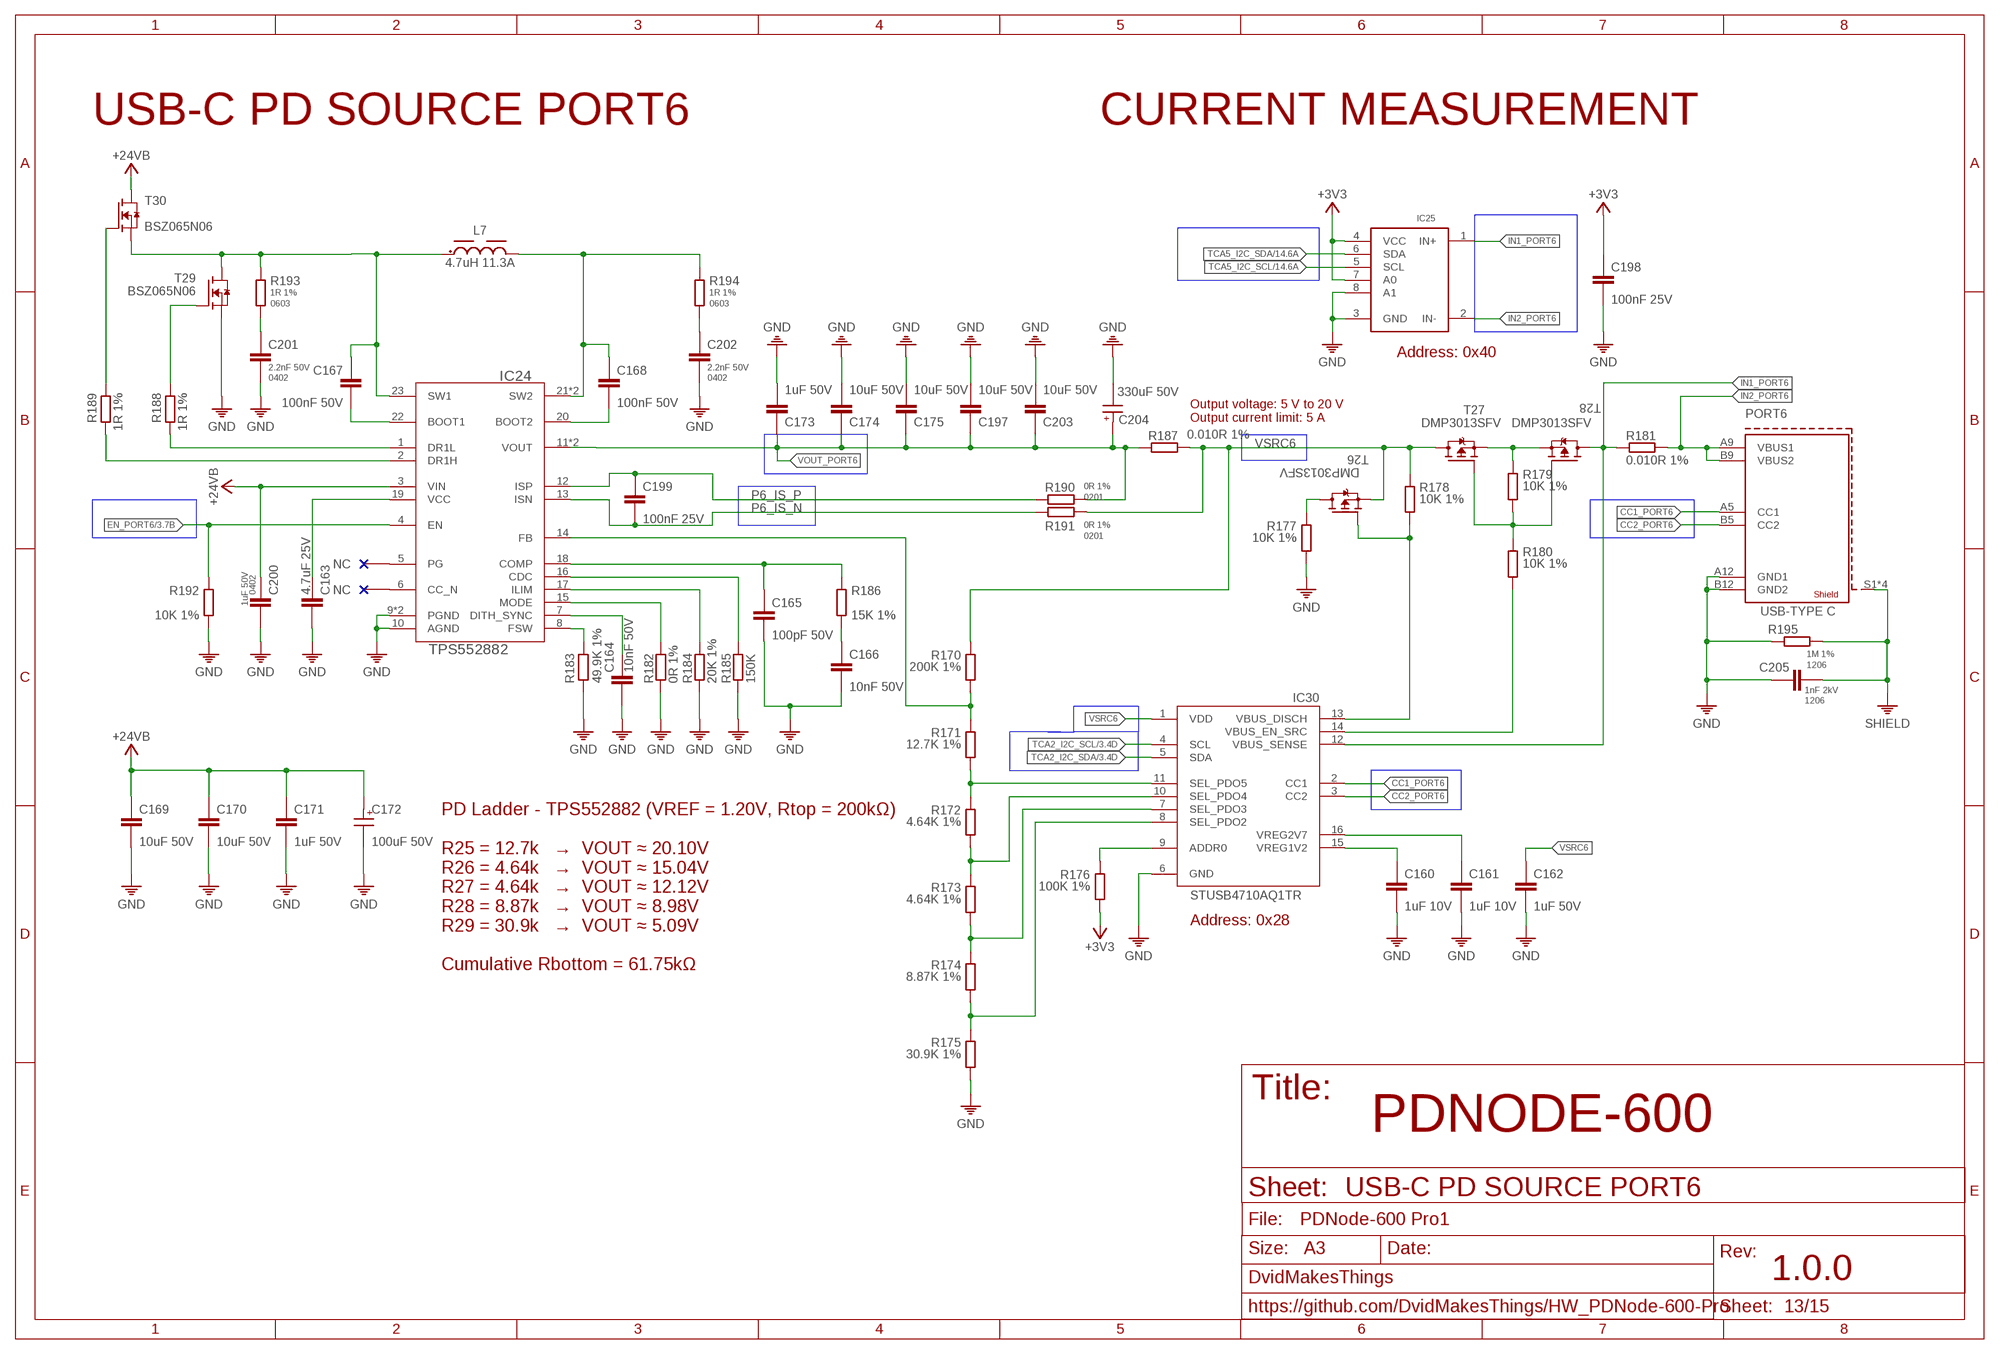
[diagram p12: schematic, sheet 13]
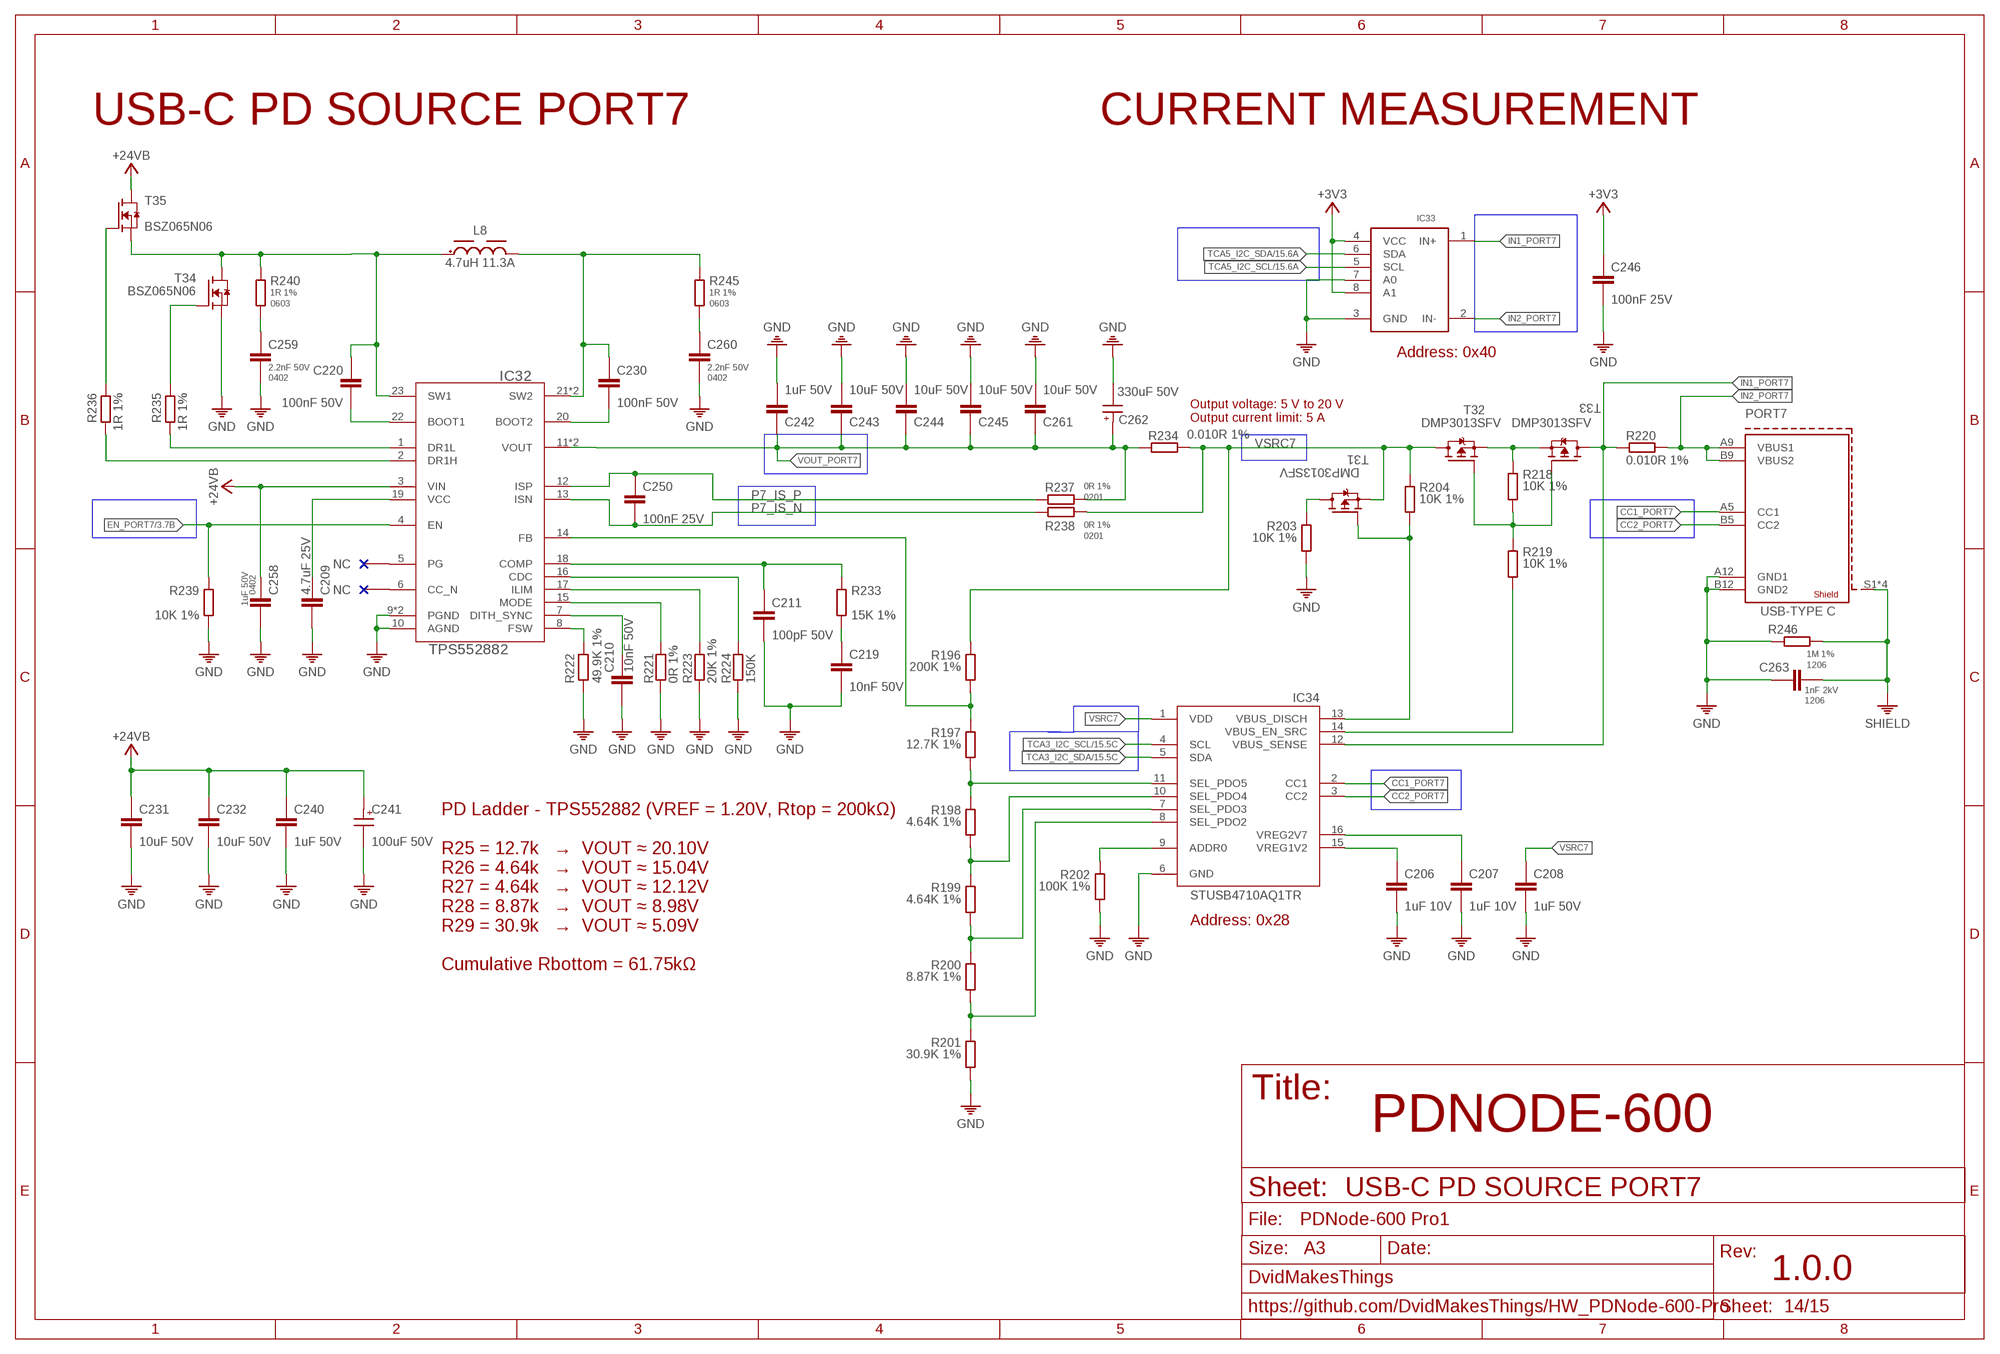
[diagram p13: schematic, sheet 14]
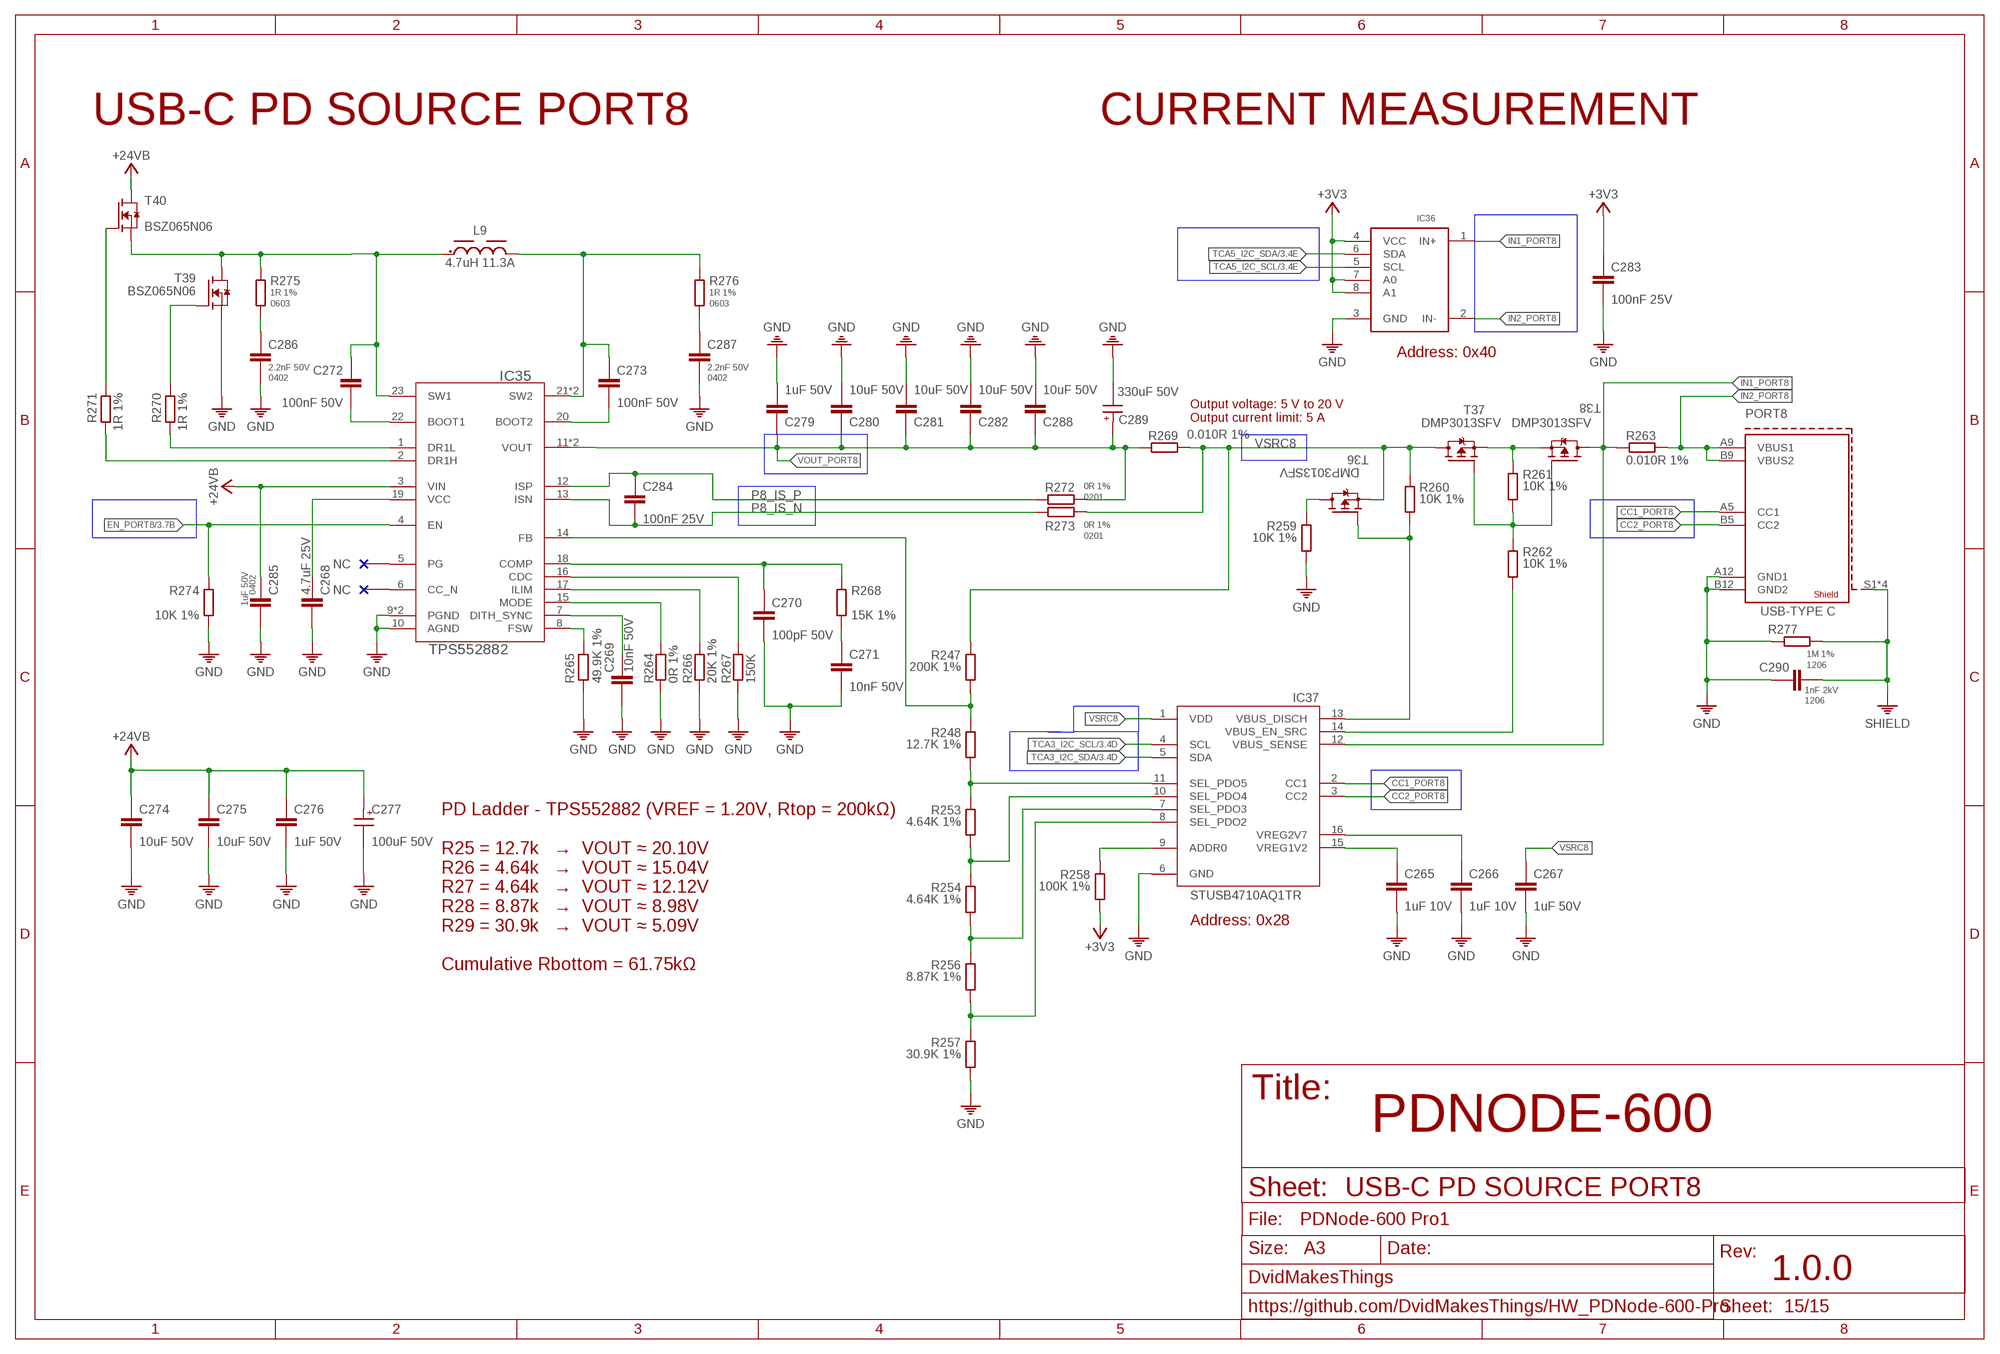
[diagram p14: schematic, sheet 15]

(export (version "E")
  (design (tool "Eeschema 10.0.6"))
  (components
    (comp (ref "C265")
      (value "1uF 10V")
      (footprint "eagle-import:0201")
      (fields (field (name "LCSC_PART") "C76935"))
      (libsource (lib "eagle-import") (part "1UF-10V0201"))
    )
    (comp (ref "C266")
      (value "1uF 10V")
      (footprint "eagle-import:0201")
      (fields (field (name "LCSC_PART") "C76935"))
      (libsource (lib "eagle-import") (part "1UF-10V0201"))
    )
    (comp (ref "C267")
      (value "1uF 50V")
      (footprint "eagle-import:0603")
      (fields (field (name "LCSC_PART") "C15849"))
      (libsource (lib "eagle-import") (part "1UF-50V0603"))
    )
    (comp (ref "C268")
      (value "4.7uF 25V")
      (footprint "eagle-import:0402")
      (fields
        (field (name "HQ_PART") "ZHLM0023346")
        (field (name "LCSC_PART") "C22367824")
        (field (name "MANUFACTURER") "Murata")
      )
      (libsource (lib "eagle-import") (part "4.7UF-25V0402"))
    )
    (comp (ref "C269")
      (value "10nF 50V")
      (footprint "eagle-import:0201")
      (fields (field (name "LCSC_PART") "C5142551"))
      (libsource (lib "eagle-import") (part "10NF-50V-0201"))
    )
    (comp (ref "C270")
      (value "100pF 50V")
      (footprint "eagle-import:0201")
      (fields
        (field (name "HQ_PART") "CA0177921")
        (field (name "MANUFACTURER") "DARFON")
        (field (name "MPN") "C0603NP0101JGT")
      )
      (libsource (lib "eagle-import") (part "100PF-50V0201"))
    )
    (comp (ref "C271")
      (value "10nF 50V")
      (footprint "eagle-import:0201")
      (fields (field (name "LCSC_PART") "C5142551"))
      (libsource (lib "eagle-import") (part "10NF-50V-0201"))
    )
    (comp (ref "C272")
      (value "100nF 50V")
      (footprint "eagle-import:0402")
      (fields (field (name "LCSC_PART") "C307331"))
      (libsource (lib "eagle-import") (part "100NF-50V-0402"))
    )
    (comp (ref "C273")
      (value "100nF 50V")
      (footprint "eagle-import:0402")
      (fields (field (name "LCSC_PART") "C307331"))
      (libsource (lib "eagle-import") (part "100NF-50V-0402"))
    )
    (comp (ref "C274")
      (value "10uF 50V")
      (footprint "eagle-import:0805")
      (fields (field (name "LCSC_PART") "C440198"))
      (libsource (lib "eagle-import") (part "10UF-50V-0805"))
    )
    (comp (ref "C275")
      (value "10uF 50V")
      (footprint "eagle-import:0805")
      (fields (field (name "LCSC_PART") "C440198"))
      (libsource (lib "eagle-import") (part "10UF-50V-0805"))
    )
    (comp (ref "C276")
      (value "1uF 50V")
      (footprint "eagle-import:0805")
      (fields
        (field (name "HQ_PART") "CA0182352")
        (field (name "LCSC_PART") "C28323")
        (field (name "MANUFACTURER") "TDK")
      )
      (libsource (lib "eagle-import") (part "1UF-50V0805"))
    )
    (comp (ref "C277")
      (value "100uF 50V")
      (footprint "eagle-import:6.3X7.7(DXL)")
      (fields
        (field (name "HQ_PART") "ZHLM0353527")
        (field (name "LCSC_PART") "C3151829")
        (field (name "MANUFACTURER") "ROQANG")
      )
      (libsource (lib "eagle-import") (part "100UF-50V6.3X7.7(DXL)"))
    )
    (comp (ref "C279")
      (value "1uF 50V")
      (footprint "eagle-import:0402")
      (fields (field (name "LCSC_PART") "C1518208"))
      (libsource (lib "eagle-import") (part "1UF-50V0402"))
    )
    (comp (ref "C280")
      (value "10uF 50V")
      (footprint "eagle-import:0805")
      (fields (field (name "LCSC_PART") "C440198"))
      (libsource (lib "eagle-import") (part "10UF-50V-0805"))
    )
    (comp (ref "C281")
      (value "10uF 50V")
      (footprint "eagle-import:0805")
      (fields (field (name "LCSC_PART") "C440198"))
      (libsource (lib "eagle-import") (part "10UF-50V-0805"))
    )
    (comp (ref "C282")
      (value "10uF 50V")
      (footprint "eagle-import:0805")
      (fields (field (name "LCSC_PART") "C440198"))
      (libsource (lib "eagle-import") (part "10UF-50V-0805"))
    )
    (comp (ref "C283")
      (value "100nF 25V")
      (footprint "eagle-import:0201")
      (fields
        (field (name "HQ_PART") "CA0183221")
        (field (name "LCSC_PART") "C76939")
        (field (name "MANUFACTURER") "Samsung")
      )
      (libsource (lib "eagle-import") (part "100NF-25V-0201"))
    )
    (comp (ref "C284")
      (value "100nF 25V")
      (footprint "eagle-import:0201")
      (fields
        (field (name "HQ_PART") "CA0183221")
        (field (name "LCSC_PART") "C76939")
        (field (name "MANUFACTURER") "Samsung")
      )
      (libsource (lib "eagle-import") (part "100NF-25V-0201"))
    )
    (comp (ref "C285")
      (value "1uF 50V")
      (footprint "eagle-import:0402")
      (fields (field (name "PACKAGE") "0402") (field (name "LCSC_PART") "C1518208"))
      (libsource (lib "eagle-import") (part "1UF-50V0402"))
    )
    (comp (ref "C286")
      (value "2.2nF 50V")
      (footprint "eagle-import:0402")
      (fields
        (field (name "PACKAGE") "0402")
        (field (name "HQ_PART") "CA0176616")
        (field (name "MANUFACTURER") "WALSIN")
        (field (name "MPN") "0402B222K500CT")
      )
      (libsource (lib "eagle-import") (part "2.2NF-50V-0402"))
    )
    (comp (ref "C287")
      (value "2.2nF 50V")
      (footprint "eagle-import:0402")
      (fields
        (field (name "PACKAGE") "0402")
        (field (name "HQ_PART") "CA0176616")
        (field (name "MANUFACTURER") "WALSIN")
        (field (name "MPN") "0402B222K500CT")
      )
      (libsource (lib "eagle-import") (part "2.2NF-50V-0402"))
    )
    (comp (ref "C288")
      (value "10uF 50V")
      (footprint "eagle-import:0805")
      (fields (field (name "LCSC_PART") "C440198"))
      (libsource (lib "eagle-import") (part "10UF-50V-0805"))
    )
    (comp (ref "C289")
      (value "330uF 50V")
      (footprint "eagle-import:10X10.5(DXL)")
      (fields (field (name "LCSC_PART") "C2895745") (field (name "MPN") "EEE-FT1H331AP"))
      (libsource (lib "eagle-import") (part "330UF-50V10X10.5(DXL)"))
    )
    (comp (ref "C290")
      (value "1nF 2kV")
      (footprint "eagle-import:1206")
      (fields
        (field (name "PACKAGE") "1206")
        (field (name "HQ_PART") "CA0134884")
        (field (name "LCSC_PART") "C173242")
        (field (name "MANUFACTURER") "Johanson Dielectrics ")
      )
      (libsource (lib "eagle-import") (part "1NF-2KV"))
    )
    (comp (ref "IC35")
      (value "TPS552882")
      (footprint "eagle-import:RPM0026A-MFG")
      (fields
        (field (name "MANUFACTURER_PART_NUMBER") "TPS552882QRPMRQ1")
        (field (name "COPYRIGHT") "Copyright (C) 2025 Ultra Librarian. All rights reserved.")
      )
      (libsource (lib "eagle-import") (part "TPS552882"))
    )
    (comp (ref "IC36")
      (value "INA219BIDCNT")
      (footprint "eagle-import:SOT23-8")
      (fields
        (field (name "HQ_PART") "IC0063216")
        (field (name "LCSC_PART") "C2653868")
        (field (name "MANUFACTURER") "Texas Instruments")
      )
      (libsource (lib "eagle-import") (part "INA219BIDCNT"))
    )
    (comp (ref "IC37")
      (value "STUSB4710AQ1TR")
      (footprint "eagle-import:QFN50P300X300X55-16N")
      (libsource (lib "eagle-import") (part "STUSB4710AQ1TR"))
    )
    (comp (ref "L9")
      (value "4.7uH 11.3A")
      (footprint "eagle-import:WE-PDHV_1280")
      (fields
        (field (name "LCSC_PART") "C2998768")
        (field (name "MANUFACTURER") "Sumida")
        (field (name "MPN") "CDRH127NP-4R7NC")
      )
      (libsource (lib "eagle-import") (part "4.7UH-PWR"))
    )
    (comp (ref "PORT8")
      (value "632722100213")
      (footprint "eagle-import:632722100213")
      (fields
        (field (name "LCSC_PART") "C2927029")
        (field (name "MANUFACTURER") "DEALON")
        (field (name "MPN") "USB-TYPE-C-009 ")
      )
      (libsource (lib "eagle-import") (part "USB-C-POWERONLY"))
    )
    (comp (ref "R247")
      (value "200K 1%")
      (footprint "eagle-import:0201")
      (fields (field (name "LCSC_PART") "C270357"))
      (libsource (lib "eagle-import") (part "200K-1%0201"))
    )
    (comp (ref "R248")
      (value "12.7K 1%")
      (footprint "eagle-import:0201")
      (fields
        (field (name "LCSC_PART") "C423755")
        (field (name "MANUFACTURER") "UNI-ROYAL")
        (field (name "MPN") "0201WMF1272TEE")
      )
      (libsource (lib "eagle-import") (part "12.7K-1%0201"))
    )
    (comp (ref "R253")
      (value "4.64K 1%")
      (footprint "eagle-import:0201")
      (fields
        (field (name "LCSC_PART") "C166186")
        (field (name "MANUFACTURER") " RALEC")
        (field (name "MPN") "RTT014641FTH")
      )
      (libsource (lib "eagle-import") (part "4.64K-1%-0201"))
    )
    (comp (ref "R254")
      (value "4.64K 1%")
      (footprint "eagle-import:0201")
      (fields
        (field (name "LCSC_PART") "C166186")
        (field (name "MANUFACTURER") " RALEC")
        (field (name "MPN") "RTT014641FTH")
      )
      (libsource (lib "eagle-import") (part "4.64K-1%-0201"))
    )
    (comp (ref "R256")
      (value "8.87K 1%")
      (footprint "eagle-import:0201")
      (fields
        (field (name "LCSC_PART") "C423413")
        (field (name "MANUFACTURER") " UNI-ROYAL")
        (field (name "MPN") "0201WMF8871TEE")
      )
      (libsource (lib "eagle-import") (part "8.87K-1%-0201"))
    )
    (comp (ref "R257")
      (value "30.9K 1%")
      (footprint "eagle-import:0201")
      (fields (field (name "LCSC_PART") "C364366"))
      (libsource (lib "eagle-import") (part "30.9K-1%0201"))
    )
    (comp (ref "R258")
      (value "100K 1%")
      (footprint "eagle-import:0201")
      (fields (field (name "LCSC_PART") "C270364"))
      (libsource (lib "eagle-import") (part "100K-1%0201"))
    )
    (comp (ref "R259")
      (value "10K 1%")
      (footprint "eagle-import:0402")
      (fields
        (field (name "HQ_PART") "RE0207399")
        (field (name "LCSC_PART") "C25744")
        (field (name "MANUFACTURER") "ROHM")
      )
      (libsource (lib "eagle-import") (part "10K-1%0402"))
    )
    (comp (ref "R260")
      (value "10K 1%")
      (footprint "eagle-import:0402")
      (fields
        (field (name "HQ_PART") "RE0207399")
        (field (name "LCSC_PART") "C25744")
        (field (name "MANUFACTURER") "ROHM")
      )
      (libsource (lib "eagle-import") (part "10K-1%0402"))
    )
    (comp (ref "R261")
      (value "10K 1%")
      (footprint "eagle-import:0201")
      (fields
        (field (name "HQ_PART") "RE0208620")
        (field (name "LCSC_PART") "C473048")
        (field (name "MANUFACTURER") "FH")
      )
      (libsource (lib "eagle-import") (part "10K-1%0201"))
    )
    (comp (ref "R262")
      (value "10K 1%")
      (footprint "eagle-import:0402")
      (fields
        (field (name "HQ_PART") "RE0207399")
        (field (name "LCSC_PART") "C25744")
        (field (name "MANUFACTURER") "ROHM")
      )
      (libsource (lib "eagle-import") (part "10K-1%0402"))
    )
    (comp (ref "R263")
      (value "0.010R 1%")
      (footprint "eagle-import:2512")
      (fields
        (field (name "LCSC_PART") "C127692")
        (field (name "MANUFACTURER") " UNI-ROYAL")
        (field (name "MPN") "25121WF100MT4E")
      )
      (libsource (lib "eagle-import") (part "0.010R-1%-2512"))
    )
    (comp (ref "R264")
      (value "0R 1%")
      (footprint "eagle-import:0201")
      (fields
        (field (name "HA_PART") "RE0015349")
        (field (name "LCSC_PART") "C106227")
        (field (name "MANUFACTURER") "Yageo")
      )
      (libsource (lib "eagle-import") (part "0R0201"))
    )
    (comp (ref "R265")
      (value "49.9K 1%")
      (footprint "eagle-import:0201")
      (fields
        (field (name "HQ_PART") "RE0461584")
        (field (name "LCSC_PART") "C138136")
        (field (name "MANUFACTURER") "Yageo")
      )
      (libsource (lib "eagle-import") (part "49.9K-1%0201"))
    )
    (comp (ref "R266")
      (value "20K 1%")
      (footprint "eagle-import:0201")
      (fields (field (name "LCSC_PART") "C473466"))
      (libsource (lib "eagle-import") (part "20K-1%0201"))
    )
    (comp (ref "R267")
      (value "150K")
      (footprint "eagle-import:R0201")
      (libsource (lib "eagle-import") (part "R0201"))
    )
    (comp (ref "R268")
      (value "15K 1%")
      (footprint "eagle-import:0201")
      (fields (field (name "LCSC_PART") "C295774"))
      (libsource (lib "eagle-import") (part "15K-1%0201"))
    )
    (comp (ref "R269")
      (value "0.010R 1%")
      (footprint "eagle-import:2512")
      (fields
        (field (name "LCSC_PART") "C127692")
        (field (name "MANUFACTURER") " UNI-ROYAL")
        (field (name "MPN") "25121WF100MT4E")
      )
      (libsource (lib "eagle-import") (part "0.010R-1%-2512"))
    )
    (comp (ref "R270")
      (value "1R 1%")
      (footprint "eagle-import:0402")
      (fields
        (field (name "HQ_PART") "RE0322446")
        (field (name "MANUFACTURER") "RALEC")
        (field (name "MPN") "RTT021R00FTH")
      )
      (libsource (lib "eagle-import") (part "1R-1%0402"))
    )
    (comp (ref "R271")
      (value "1R 1%")
      (footprint "eagle-import:0402")
      (fields
        (field (name "HQ_PART") "RE0322446")
        (field (name "MANUFACTURER") "RALEC")
        (field (name "MPN") "RTT021R00FTH")
      )
      (libsource (lib "eagle-import") (part "1R-1%0402"))
    )
    (comp (ref "R272")
      (value "0R 1%")
      (footprint "eagle-import:0201")
      (fields
        (field (name "PACKAGE") "0201")
        (field (name "HA_PART") "RE0015349")
        (field (name "LCSC_PART") "C106227")
        (field (name "MANUFACTURER") "Yageo")
      )
      (libsource (lib "eagle-import") (part "0R0201"))
    )
    (comp (ref "R273")
      (value "0R 1%")
      (footprint "eagle-import:0201")
      (fields
        (field (name "PACKAGE") "0201")
        (field (name "HA_PART") "RE0015349")
        (field (name "LCSC_PART") "C106227")
        (field (name "MANUFACTURER") "Yageo")
      )
      (libsource (lib "eagle-import") (part "0R0201"))
    )
    (comp (ref "R274")
      (value "10K 1%")
      (footprint "eagle-import:0201")
      (fields
        (field (name "HQ_PART") "RE0208620")
        (field (name "LCSC_PART") "C473048")
        (field (name "MANUFACTURER") "FH")
      )
      (libsource (lib "eagle-import") (part "10K-1%0201"))
    )
    (comp (ref "R275")
      (value "1R 1%")
      (footprint "eagle-import:0603")
      (fields
        (field (name "PACKAGE") "0603")
        (field (name "HQ_PART") "RE0421839")
        (field (name "MANUFACTURER") "RALEC")
        (field (name "MPN") "RTT031R00FTP")
      )
      (libsource (lib "eagle-import") (part "1R-1%0603"))
    )
    (comp (ref "R276")
      (value "1R 1%")
      (footprint "eagle-import:0603")
      (fields
        (field (name "PACKAGE") "0603")
        (field (name "HQ_PART") "RE0421839")
        (field (name "MANUFACTURER") "RALEC")
        (field (name "MPN") "RTT031R00FTP")
      )
      (libsource (lib "eagle-import") (part "1R-1%0603"))
    )
    (comp (ref "R277")
      (value "1M 1%")
      (footprint "eagle-import:1206")
      (fields
        (field (name "PACKAGE") "1206")
        (field (name "HQ_PART") "RE0188103")
        (field (name "LCSC_PART") "C17927")
        (field (name "MANUFACTURER") "Uniohm")
      )
      (libsource (lib "eagle-import") (part "1M-1%1206"))
    )
    (comp (ref "T36")
      (value "DMP3013SFV")
      (footprint "eagle-import:POWERDI3333-8_UX_DIO-L")
      (fields (field (name "MANUFACTURER_PART_NUMBER") "DMP3013SFV-7"))
      (libsource (lib "eagle-import") (part "DMP3013SFV-7UX"))
    )
    (comp (ref "T37")
      (value "DMP3013SFV")
      (footprint "eagle-import:POWERDI3333-8_UX_DIO-L")
      (fields (field (name "MANUFACTURER_PART_NUMBER") "DMP3013SFV-7"))
      (libsource (lib "eagle-import") (part "DMP3013SFV-7UX"))
    )
    (comp (ref "T38")
      (value "DMP3013SFV")
      (footprint "eagle-import:POWERDI3333-8_UX_DIO-L")
      (fields (field (name "MANUFACTURER_PART_NUMBER") "DMP3013SFV-7"))
      (libsource (lib "eagle-import") (part "DMP3013SFV-7UX"))
    )
    (comp (ref "T39")
      (value "BSZ065N06")
      (footprint "eagle-import:POWERDI3333-8_UX_DIO-L")
      (fields
        (field (name "MANUFACTURER_PART_NUMBER") "IPZ40N04S5L7R4ATMA1")
        (field (name "COPYRIGHT") "Copyright (C) 2025 Ultra Librarian. All rights reserved.")
      )
      (libsource (lib "eagle-import") (part "IPZ40N04S5L7R4ATMA1"))
    )
    (comp (ref "T40")
      (value "BSZ065N06")
      (footprint "eagle-import:POWERDI3333-8_UX_DIO-L")
      (fields
        (field (name "MANUFACTURER_PART_NUMBER") "IPZ40N04S5L7R4ATMA1")
        (field (name "COPYRIGHT") "Copyright (C) 2025 Ultra Librarian. All rights reserved.")
      )
      (libsource (lib "eagle-import") (part "IPZ40N04S5L7R4ATMA1"))
    )
    (comp (ref "C6")
      (value "1uF 10V")
      (footprint "eagle-import:0201")
      (fields (field (name "LCSC_PART") "C76935"))
      (libsource (lib "eagle-import") (part "1UF-10V0201"))
    )
    (comp (ref "C16")
      (value "1uF 10V")
      (footprint "eagle-import:0201")
      (fields (field (name "LCSC_PART") "C76935"))
      (libsource (lib "eagle-import") (part "1UF-10V0201"))
    )
    (comp (ref "C39")
      (value "1uF 50V")
      (footprint "eagle-import:0603")
      (fields (field (name "LCSC_PART") "C15849"))
      (libsource (lib "eagle-import") (part "1UF-50V0603"))
    )
    (comp (ref "C40")
      (value "1nF 2kV")
      (footprint "eagle-import:1206")
      (fields
        (field (name "PACKAGE") "1206")
        (field (name "HQ_PART") "CA0134884")
        (field (name "LCSC_PART") "C173242")
        (field (name "MANUFACTURER") "Johanson Dielectrics ")
      )
      (libsource (lib "eagle-import") (part "1NF-2KV"))
    )
    (comp (ref "C41")
      (value "4.7uF 25V")
      (footprint "eagle-import:0402")
      (fields
        (field (name "HQ_PART") "ZHLM0023346")
        (field (name "LCSC_PART") "C22367824")
        (field (name "MANUFACTURER") "Murata")
      )
      (libsource (lib "eagle-import") (part "4.7UF-25V0402"))
    )
    (comp (ref "C42")
      (value "10nF 50V")
      (footprint "eagle-import:0201")
      (fields (field (name "LCSC_PART") "C5142551"))
      (libsource (lib "eagle-import") (part "10NF-50V-0201"))
    )
    (comp (ref "C43")
      (value "100pF 50V")
      (footprint "eagle-import:0201")
      (fields
        (field (name "HQ_PART") "CA0177921")
        (field (name "MANUFACTURER") "DARFON")
        (field (name "MPN") "C0603NP0101JGT")
      )
      (libsource (lib "eagle-import") (part "100PF-50V0201"))
    )
    (comp (ref "C44")
      (value "10nF 50V")
      (footprint "eagle-import:0201")
      (fields (field (name "LCSC_PART") "C5142551"))
      (libsource (lib "eagle-import") (part "10NF-50V-0201"))
    )
    (comp (ref "C45")
      (value "100nF 50V")
      (footprint "eagle-import:0402")
      (fields (field (name "LCSC_PART") "C307331"))
      (libsource (lib "eagle-import") (part "100NF-50V-0402"))
    )
    (comp (ref "C46")
      (value "100nF 50V")
      (footprint "eagle-import:0402")
      (fields (field (name "LCSC_PART") "C307331"))
      (libsource (lib "eagle-import") (part "100NF-50V-0402"))
    )
    (comp (ref "C47")
      (value "10uF 50V")
      (footprint "eagle-import:0805")
      (fields (field (name "LCSC_PART") "C440198"))
      (libsource (lib "eagle-import") (part "10UF-50V-0805"))
    )
    (comp (ref "C48")
      (value "10uF 50V")
      (footprint "eagle-import:0805")
      (fields (field (name "LCSC_PART") "C440198"))
      (libsource (lib "eagle-import") (part "10UF-50V-0805"))
    )
    (comp (ref "C49")
      (value "1uF 50V")
      (footprint "eagle-import:0805")
      (fields
        (field (name "HQ_PART") "CA0182352")
        (field (name "LCSC_PART") "C28323")
        (field (name "MANUFACTURER") "TDK")
      )
      (libsource (lib "eagle-import") (part "1UF-50V0805"))
    )
    (comp (ref "C50")
      (value "100uF 50V")
      (footprint "eagle-import:6.3X7.7(DXL)")
      (fields
        (field (name "HQ_PART") "ZHLM0353527")
        (field (name "LCSC_PART") "C3151829")
        (field (name "MANUFACTURER") "ROQANG")
      )
      (libsource (lib "eagle-import") (part "100UF-50V6.3X7.7(DXL)"))
    )
    (comp (ref "C51")
      (value "1uF 50V")
      (footprint "eagle-import:0402")
      (fields (field (name "LCSC_PART") "C1518208"))
      (libsource (lib "eagle-import") (part "1UF-50V0402"))
    )
    (comp (ref "C52")
      (value "10uF 50V")
      (footprint "eagle-import:0805")
      (fields (field (name "LCSC_PART") "C440198"))
      (libsource (lib "eagle-import") (part "10UF-50V-0805"))
    )
    (comp (ref "C53")
      (value "10uF 50V")
      (footprint "eagle-import:0805")
      (fields (field (name "LCSC_PART") "C440198"))
      (libsource (lib "eagle-import") (part "10UF-50V-0805"))
    )
    (comp (ref "C54")
      (value "10uF 50V")
      (footprint "eagle-import:0805")
      (fields (field (name "LCSC_PART") "C440198"))
      (libsource (lib "eagle-import") (part "10UF-50V-0805"))
    )
    (comp (ref "C55")
      (value "100nF 25V")
      (footprint "eagle-import:0201")
      (fields
        (field (name "HQ_PART") "CA0183221")
        (field (name "LCSC_PART") "C76939")
        (field (name "MANUFACTURER") "Samsung")
      )
      (libsource (lib "eagle-import") (part "100NF-25V-0201"))
    )
    (comp (ref "C196")
      (value "100nF 25V")
      (footprint "eagle-import:0201")
      (fields
        (field (name "HQ_PART") "CA0183221")
        (field (name "LCSC_PART") "C76939")
        (field (name "MANUFACTURER") "Samsung")
      )
      (libsource (lib "eagle-import") (part "100NF-25V-0201"))
    )
    (comp (ref "C214")
      (value "1uF 50V")
      (footprint "eagle-import:0402")
      (fields (field (name "PACKAGE") "0402") (field (name "LCSC_PART") "C1518208"))
      (libsource (lib "eagle-import") (part "1UF-50V0402"))
    )
    (comp (ref "C215")
      (value "2.2nF 50V")
      (footprint "eagle-import:0402")
      (fields
        (field (name "PACKAGE") "0402")
        (field (name "HQ_PART") "CA0176616")
        (field (name "MANUFACTURER") "WALSIN")
        (field (name "MPN") "0402B222K500CT")
      )
      (libsource (lib "eagle-import") (part "2.2NF-50V-0402"))
    )
    (comp (ref "C216")
      (value "2.2nF 50V")
      (footprint "eagle-import:0402")
      (fields
        (field (name "PACKAGE") "0402")
        (field (name "HQ_PART") "CA0176616")
        (field (name "MANUFACTURER") "WALSIN")
        (field (name "MPN") "0402B222K500CT")
      )
      (libsource (lib "eagle-import") (part "2.2NF-50V-0402"))
    )
    (comp (ref "C217")
      (value "10uF 50V")
      (footprint "eagle-import:0805")
      (fields (field (name "LCSC_PART") "C440198"))
      (libsource (lib "eagle-import") (part "10UF-50V-0805"))
    )
    (comp (ref "C218")
      (value "330uF 50V")
      (footprint "eagle-import:10X10.5(DXL)")
      (fields (field (name "LCSC_PART") "C2895745") (field (name "MPN") "EEE-FT1H331AP"))
      (libsource (lib "eagle-import") (part "330UF-50V10X10.5(DXL)"))
    )
    (comp (ref "IC9")
      (value "STUSB4710AQ1TR")
      (footprint "eagle-import:QFN50P300X300X55-16N")
      (libsource (lib "eagle-import") (part "STUSB4710AQ1TR"))
    )
    (comp (ref "IC12")
      (value "TPS552882")
      (footprint "eagle-import:RPM0026A-MFG")
      (fields
        (field (name "MANUFACTURER_PART_NUMBER") "TPS552882QRPMRQ1")
        (field (name "COPYRIGHT") "Copyright (C) 2025 Ultra Librarian. All rights reserved.")
      )
      (libsource (lib "eagle-import") (part "TPS552882"))
    )
    (comp (ref "IC13")
      (value "INA219BIDCNT")
      (footprint "eagle-import:SOT23-8")
      (fields
        (field (name "HQ_PART") "IC0063216")
        (field (name "LCSC_PART") "C2653868")
        (field (name "MANUFACTURER") "Texas Instruments")
      )
      (libsource (lib "eagle-import") (part "INA219BIDCNT"))
    )
    (comp (ref "L2")
      (value "4.7uH 11.3A")
      (footprint "eagle-import:WE-PDHV_1280")
      (fields
        (field (name "LCSC_PART") "C2998768")
        (field (name "MANUFACTURER") "Sumida")
        (field (name "MPN") "CDRH127NP-4R7NC")
      )
      (libsource (lib "eagle-import") (part "4.7UH-PWR"))
    )
    (comp (ref "PORT1")
      (value "632722100213")
      (footprint "eagle-import:632722100213")
      (fields
        (field (name "LCSC_PART") "C2927029")
        (field (name "MANUFACTURER") "DEALON")
        (field (name "MPN") "USB-TYPE-C-009 ")
      )
      (libsource (lib "eagle-import") (part "USB-C-POWERONLY"))
    )
    (comp (ref "R5")
      (value "200K 1%")
      (footprint "eagle-import:0201")
      (fields (field (name "LCSC_PART") "C270357"))
      (libsource (lib "eagle-import") (part "200K-1%0201"))
    )
    (comp (ref "R11")
      (value "12.7K 1%")
      (footprint "eagle-import:0201")
      (fields
        (field (name "LCSC_PART") "C423755")
        (field (name "MANUFACTURER") "UNI-ROYAL")
        (field (name "MPN") "0201WMF1272TEE")
      )
      (libsource (lib "eagle-import") (part "12.7K-1%0201"))
    )
    (comp (ref "R46")
      (value "4.64K 1%")
      (footprint "eagle-import:0201")
      (fields
        (field (name "LCSC_PART") "C166186")
        (field (name "MANUFACTURER") " RALEC")
        (field (name "MPN") "RTT014641FTH")
      )
      (libsource (lib "eagle-import") (part "4.64K-1%-0201"))
    )
    (comp (ref "R47")
      (value "4.64K 1%")
      (footprint "eagle-import:0201")
      (fields
        (field (name "LCSC_PART") "C166186")
        (field (name "MANUFACTURER") " RALEC")
        (field (name "MPN") "RTT014641FTH")
      )
      (libsource (lib "eagle-import") (part "4.64K-1%-0201"))
    )
    (comp (ref "R48")
      (value "8.87K 1%")
      (footprint "eagle-import:0201")
      (fields
        (field (name "LCSC_PART") "C423413")
        (field (name "MANUFACTURER") " UNI-ROYAL")
        (field (name "MPN") "0201WMF8871TEE")
      )
      (libsource (lib "eagle-import") (part "8.87K-1%-0201"))
    )
    (comp (ref "R49")
      (value "30.9K 1%")
      (footprint "eagle-import:0201")
      (fields (field (name "LCSC_PART") "C364366"))
      (libsource (lib "eagle-import") (part "30.9K-1%0201"))
    )
    (comp (ref "R50")
      (value "1M 1%")
      (footprint "eagle-import:1206")
      (fields
        (field (name "PACKAGE") "1206")
        (field (name "HQ_PART") "RE0188103")
        (field (name "LCSC_PART") "C17927")
        (field (name "MANUFACTURER") "Uniohm")
      )
      (libsource (lib "eagle-import") (part "1M-1%1206"))
    )
    (comp (ref "R51")
      (value "100K 1%")
      (footprint "eagle-import:0201")
      (fields (field (name "LCSC_PART") "C270364"))
      (libsource (lib "eagle-import") (part "100K-1%0201"))
    )
    (comp (ref "R52")
      (value "10K 1%")
      (footprint "eagle-import:0402")
      (fields
        (field (name "HQ_PART") "RE0207399")
        (field (name "LCSC_PART") "C25744")
        (field (name "MANUFACTURER") "ROHM")
      )
      (libsource (lib "eagle-import") (part "10K-1%0402"))
    )
    (comp (ref "R53")
      (value "10K 1%")
      (footprint "eagle-import:0402")
      (fields
        (field (name "HQ_PART") "RE0207399")
        (field (name "LCSC_PART") "C25744")
        (field (name "MANUFACTURER") "ROHM")
      )
      (libsource (lib "eagle-import") (part "10K-1%0402"))
    )
    (comp (ref "R54")
      (value "10K 1%")
      (footprint "eagle-import:0201")
      (fields
        (field (name "HQ_PART") "RE0208620")
        (field (name "LCSC_PART") "C473048")
        (field (name "MANUFACTURER") "FH")
      )
      (libsource (lib "eagle-import") (part "10K-1%0201"))
    )
    (comp (ref "R55")
      (value "10K 1%")
      (footprint "eagle-import:0402")
      (fields
        (field (name "HQ_PART") "RE0207399")
        (field (name "LCSC_PART") "C25744")
        (field (name "MANUFACTURER") "ROHM")
      )
      (libsource (lib "eagle-import") (part "10K-1%0402"))
    )
    (comp (ref "R57")
      (value "0.010R 1%")
      (footprint "eagle-import:2512")
      (fields
        (field (name "LCSC_PART") "C127692")
        (field (name "MANUFACTURER") " UNI-ROYAL")
        (field (name "MPN") "25121WF100MT4E")
      )
      (libsource (lib "eagle-import") (part "0.010R-1%-2512"))
    )
    (comp (ref "R58")
      (value "0R 1%")
      (footprint "eagle-import:0201")
      (fields
        (field (name "HA_PART") "RE0015349")
        (field (name "LCSC_PART") "C106227")
        (field (name "MANUFACTURER") "Yageo")
      )
      (libsource (lib "eagle-import") (part "0R0201"))
    )
    (comp (ref "R59")
      (value "49.9K 1%")
      (footprint "eagle-import:0201")
      (fields
        (field (name "HQ_PART") "RE0461584")
        (field (name "LCSC_PART") "C138136")
        (field (name "MANUFACTURER") "Yageo")
      )
      (libsource (lib "eagle-import") (part "49.9K-1%0201"))
    )
    (comp (ref "R60")
      (value "20K 1%")
      (footprint "eagle-import:0201")
      (fields (field (name "LCSC_PART") "C473466"))
      (libsource (lib "eagle-import") (part "20K-1%0201"))
    )
    (comp (ref "R61")
      (value "150K")
      (footprint "eagle-import:R0201")
      (libsource (lib "eagle-import") (part "R0201"))
    )
    (comp (ref "R62")
      (value "15K 1%")
      (footprint "eagle-import:0201")
      (fields (field (name "LCSC_PART") "C295774"))
      (libsource (lib "eagle-import") (part "15K-1%0201"))
    )
    (comp (ref "R63")
      (value "0.010R 1%")
      (footprint "eagle-import:2512")
      (fields
        (field (name "LCSC_PART") "C127692")
        (field (name "MANUFACTURER") " UNI-ROYAL")
        (field (name "MPN") "25121WF100MT4E")
      )
      (libsource (lib "eagle-import") (part "0.010R-1%-2512"))
    )
    (comp (ref "R64")
      (value "1R 1%")
      (footprint "eagle-import:0402")
      (fields
        (field (name "HQ_PART") "RE0322446")
        (field (name "MANUFACTURER") "RALEC")
        (field (name "MPN") "RTT021R00FTH")
      )
      (libsource (lib "eagle-import") (part "1R-1%0402"))
    )
    (comp (ref "R65")
      (value "1R 1%")
      (footprint "eagle-import:0402")
      (fields
        (field (name "HQ_PART") "RE0322446")
        (field (name "MANUFACTURER") "RALEC")
        (field (name "MPN") "RTT021R00FTH")
      )
      (libsource (lib "eagle-import") (part "1R-1%0402"))
    )
    (comp (ref "R228")
      (value "0R 1%")
      (footprint "eagle-import:0201")
      (fields
        (field (name "PACKAGE") "0201")
        (field (name "HA_PART") "RE0015349")
        (field (name "LCSC_PART") "C106227")
        (field (name "MANUFACTURER") "Yageo")
      )
      (libsource (lib "eagle-import") (part "0R0201"))
    )
    (comp (ref "R229")
      (value "0R 1%")
      (footprint "eagle-import:0201")
      (fields
        (field (name "PACKAGE") "0201")
        (field (name "HA_PART") "RE0015349")
        (field (name "LCSC_PART") "C106227")
        (field (name "MANUFACTURER") "Yageo")
      )
      (libsource (lib "eagle-import") (part "0R0201"))
    )
    (comp (ref "R230")
      (value "10K 1%")
      (footprint "eagle-import:0201")
      (fields
        (field (name "HQ_PART") "RE0208620")
        (field (name "LCSC_PART") "C473048")
        (field (name "MANUFACTURER") "FH")
      )
      (libsource (lib "eagle-import") (part "10K-1%0201"))
    )
    (comp (ref "R231")
      (value "1R 1%")
      (footprint "eagle-import:0603")
      (fields
        (field (name "PACKAGE") "0603")
        (field (name "HQ_PART") "RE0421839")
        (field (name "MANUFACTURER") "RALEC")
        (field (name "MPN") "RTT031R00FTP")
      )
      (libsource (lib "eagle-import") (part "1R-1%0603"))
    )
    (comp (ref "R232")
      (value "1R 1%")
      (footprint "eagle-import:0603")
      (fields
        (field (name "PACKAGE") "0603")
        (field (name "HQ_PART") "RE0421839")
        (field (name "MANUFACTURER") "RALEC")
        (field (name "MPN") "RTT031R00FTP")
      )
      (libsource (lib "eagle-import") (part "1R-1%0603"))
    )
    (comp (ref "T6")
      (value "DMP3013SFV")
      (footprint "eagle-import:POWERDI3333-8_UX_DIO-L")
      (fields (field (name "MANUFACTURER_PART_NUMBER") "DMP3013SFV-7"))
      (libsource (lib "eagle-import") (part "DMP3013SFV-7UX"))
    )
    (comp (ref "T7")
      (value "DMP3013SFV")
      (footprint "eagle-import:POWERDI3333-8_UX_DIO-L")
      (fields (field (name "MANUFACTURER_PART_NUMBER") "DMP3013SFV-7"))
      (libsource (lib "eagle-import") (part "DMP3013SFV-7UX"))
    )
    (comp (ref "T8")
      (value "DMP3013SFV")
      (footprint "eagle-import:POWERDI3333-8_UX_DIO-L")
      (fields (field (name "MANUFACTURER_PART_NUMBER") "DMP3013SFV-7"))
      (libsource (lib "eagle-import") (part "DMP3013SFV-7UX"))
    )
    (comp (ref "T9")
      (value "BSZ065N06")
      (footprint "eagle-import:POWERDI3333-8_UX_DIO-L")
      (fields
        (field (name "MANUFACTURER_PART_NUMBER") "IPZ40N04S5L7R4ATMA1")
        (field (name "COPYRIGHT") "Copyright (C) 2025 Ultra Librarian. All rights reserved.")
      )
      (libsource (lib "eagle-import") (part "IPZ40N04S5L7R4ATMA1"))
    )
    (comp (ref "T10")
      (value "BSZ065N06")
      (footprint "eagle-import:POWERDI3333-8_UX_DIO-L")
      (fields
        (field (name "MANUFACTURER_PART_NUMBER") "IPZ40N04S5L7R4ATMA1")
        (field (name "COPYRIGHT") "Copyright (C) 2025 Ultra Librarian. All rights reserved.")
      )
      (libsource (lib "eagle-import") (part "IPZ40N04S5L7R4ATMA1"))
    )
    (comp (ref "C81")
      (value "1uF 10V")
      (footprint "eagle-import:0201")
      (fields (field (name "LCSC_PART") "C76935"))
      (libsource (lib "eagle-import") (part "1UF-10V0201"))
    )
    (comp (ref "C86")
      (value "1uF 10V")
      (footprint "eagle-import:0201")
      (fields (field (name "LCSC_PART") "C76935"))
      (libsource (lib "eagle-import") (part "1UF-10V0201"))
    )
    (comp (ref "C87")
      (value "1uF 50V")
      (footprint "eagle-import:0603")
      (fields (field (name "LCSC_PART") "C15849"))
      (libsource (lib "eagle-import") (part "1UF-50V0603"))
    )
    (comp (ref "C88")
      (value "4.7uF 25V")
      (footprint "eagle-import:0402")
      (fields
        (field (name "HQ_PART") "ZHLM0023346")
        (field (name "LCSC_PART") "C22367824")
        (field (name "MANUFACTURER") "Murata")
      )
      (libsource (lib "eagle-import") (part "4.7UF-25V0402"))
    )
    (comp (ref "C89")
      (value "10nF 50V")
      (footprint "eagle-import:0201")
      (fields (field (name "LCSC_PART") "C5142551"))
      (libsource (lib "eagle-import") (part "10NF-50V-0201"))
    )
    (comp (ref "C90")
      (value "100pF 50V")
      (footprint "eagle-import:0201")
      (fields
        (field (name "HQ_PART") "CA0177921")
        (field (name "MANUFACTURER") "DARFON")
        (field (name "MPN") "C0603NP0101JGT")
      )
      (libsource (lib "eagle-import") (part "100PF-50V0201"))
    )
    (comp (ref "C91")
      (value "10nF 50V")
      (footprint "eagle-import:0201")
      (fields (field (name "LCSC_PART") "C5142551"))
      (libsource (lib "eagle-import") (part "10NF-50V-0201"))
    )
    (comp (ref "C92")
      (value "100nF 50V")
      (footprint "eagle-import:0402")
      (fields (field (name "LCSC_PART") "C307331"))
      (libsource (lib "eagle-import") (part "100NF-50V-0402"))
    )
    (comp (ref "C93")
      (value "100nF 50V")
      (footprint "eagle-import:0402")
      (fields (field (name "LCSC_PART") "C307331"))
      (libsource (lib "eagle-import") (part "100NF-50V-0402"))
    )
    (comp (ref "C94")
      (value "10uF 50V")
      (footprint "eagle-import:0805")
      (fields (field (name "LCSC_PART") "C440198"))
      (libsource (lib "eagle-import") (part "10UF-50V-0805"))
    )
    (comp (ref "C95")
      (value "10uF 50V")
      (footprint "eagle-import:0805")
      (fields (field (name "LCSC_PART") "C440198"))
      (libsource (lib "eagle-import") (part "10UF-50V-0805"))
    )
    (comp (ref "C96")
      (value "1uF 50V")
      (footprint "eagle-import:0805")
      (fields
        (field (name "HQ_PART") "CA0182352")
        (field (name "LCSC_PART") "C28323")
        (field (name "MANUFACTURER") "TDK")
      )
      (libsource (lib "eagle-import") (part "1UF-50V0805"))
    )
    (comp (ref "C97")
      (value "100uF 50V")
      (footprint "eagle-import:6.3X7.7(DXL)")
      (fields
        (field (name "HQ_PART") "ZHLM0353527")
        (field (name "LCSC_PART") "C3151829")
        (field (name "MANUFACTURER") "ROQANG")
      )
      (libsource (lib "eagle-import") (part "100UF-50V6.3X7.7(DXL)"))
    )
    (comp (ref "C98")
      (value "1uF 50V")
      (footprint "eagle-import:0402")
      (fields (field (name "LCSC_PART") "C1518208"))
      (libsource (lib "eagle-import") (part "1UF-50V0402"))
    )
    (comp (ref "C99")
      (value "10uF 50V")
      (footprint "eagle-import:0805")
      (fields (field (name "LCSC_PART") "C440198"))
      (libsource (lib "eagle-import") (part "10UF-50V-0805"))
    )
    (comp (ref "C100")
      (value "10uF 50V")
      (footprint "eagle-import:0805")
      (fields (field (name "LCSC_PART") "C440198"))
      (libsource (lib "eagle-import") (part "10UF-50V-0805"))
    )
    (comp (ref "C101")
      (value "10uF 50V")
      (footprint "eagle-import:0805")
      (fields (field (name "LCSC_PART") "C440198"))
      (libsource (lib "eagle-import") (part "10UF-50V-0805"))
    )
    (comp (ref "C102")
      (value "100nF 25V")
      (footprint "eagle-import:0201")
      (fields
        (field (name "HQ_PART") "CA0183221")
        (field (name "LCSC_PART") "C76939")
        (field (name "MANUFACTURER") "Samsung")
      )
      (libsource (lib "eagle-import") (part "100NF-25V-0201"))
    )
    (comp (ref "C103")
      (value "100nF 25V")
      (footprint "eagle-import:0201")
      (fields
        (field (name "HQ_PART") "CA0183221")
        (field (name "LCSC_PART") "C76939")
        (field (name "MANUFACTURER") "Samsung")
      )
      (libsource (lib "eagle-import") (part "100NF-25V-0201"))
    )
    (comp (ref "C104")
      (value "1uF 50V")
      (footprint "eagle-import:0402")
      (fields (field (name "PACKAGE") "0402") (field (name "LCSC_PART") "C1518208"))
      (libsource (lib "eagle-import") (part "1UF-50V0402"))
    )
    (comp (ref "C105")
      (value "2.2nF 50V")
      (footprint "eagle-import:0402")
      (fields
        (field (name "PACKAGE") "0402")
        (field (name "HQ_PART") "CA0176616")
        (field (name "MANUFACTURER") "WALSIN")
        (field (name "MPN") "0402B222K500CT")
      )
      (libsource (lib "eagle-import") (part "2.2NF-50V-0402"))
    )
    (comp (ref "C106")
      (value "2.2nF 50V")
      (footprint "eagle-import:0402")
      (fields
        (field (name "PACKAGE") "0402")
        (field (name "HQ_PART") "CA0176616")
        (field (name "MANUFACTURER") "WALSIN")
        (field (name "MPN") "0402B222K500CT")
      )
      (libsource (lib "eagle-import") (part "2.2NF-50V-0402"))
    )
    (comp (ref "C107")
      (value "10uF 50V")
      (footprint "eagle-import:0805")
      (fields (field (name "LCSC_PART") "C440198"))
      (libsource (lib "eagle-import") (part "10UF-50V-0805"))
    )
    (comp (ref "C108")
      (value "330uF 50V")
      (footprint "eagle-import:10X10.5(DXL)")
      (fields (field (name "LCSC_PART") "C2895745") (field (name "MPN") "EEE-FT1H331AP"))
      (libsource (lib "eagle-import") (part "330UF-50V10X10.5(DXL)"))
    )
    (comp (ref "C109")
      (value "1nF 2kV")
      (footprint "eagle-import:1206")
      (fields
        (field (name "PACKAGE") "1206")
        (field (name "HQ_PART") "CA0134884")
        (field (name "LCSC_PART") "C173242")
        (field (name "MANUFACTURER") "Johanson Dielectrics ")
      )
      (libsource (lib "eagle-import") (part "1NF-2KV"))
    )
    (comp (ref "IC15")
      (value "TPS552882")
      (footprint "eagle-import:RPM0026A-MFG")
      (fields
        (field (name "MANUFACTURER_PART_NUMBER") "TPS552882QRPMRQ1")
        (field (name "COPYRIGHT") "Copyright (C) 2025 Ultra Librarian. All rights reserved.")
      )
      (libsource (lib "eagle-import") (part "TPS552882"))
    )
    (comp (ref "IC16")
      (value "INA219BIDCNT")
      (footprint "eagle-import:SOT23-8")
      (fields
        (field (name "HQ_PART") "IC0063216")
        (field (name "LCSC_PART") "C2653868")
        (field (name "MANUFACTURER") "Texas Instruments")
      )
      (libsource (lib "eagle-import") (part "INA219BIDCNT"))
    )
    (comp (ref "IC17")
      (value "STUSB4710AQ1TR")
      (footprint "eagle-import:QFN50P300X300X55-16N")
      (libsource (lib "eagle-import") (part "STUSB4710AQ1TR"))
    )
    (comp (ref "L4")
      (value "4.7uH 11.3A")
      (footprint "eagle-import:WE-PDHV_1280")
      (fields
        (field (name "LCSC_PART") "C2998768")
        (field (name "MANUFACTURER") "Sumida")
        (field (name "MPN") "CDRH127NP-4R7NC")
      )
      (libsource (lib "eagle-import") (part "4.7UH-PWR"))
    )
    (comp (ref "PORT3")
      (value "632722100213")
      (footprint "eagle-import:632722100213")
      (fields
        (field (name "LCSC_PART") "C2927029")
        (field (name "MANUFACTURER") "DEALON")
        (field (name "MPN") "USB-TYPE-C-009 ")
      )
      (libsource (lib "eagle-import") (part "USB-C-POWERONLY"))
    )
    (comp (ref "R92")
      (value "200K 1%")
      (footprint "eagle-import:0201")
      (fields (field (name "LCSC_PART") "C270357"))
      (libsource (lib "eagle-import") (part "200K-1%0201"))
    )
    (comp (ref "R93")
      (value "12.7K 1%")
      (footprint "eagle-import:0201")
      (fields
        (field (name "LCSC_PART") "C423755")
        (field (name "MANUFACTURER") "UNI-ROYAL")
        (field (name "MPN") "0201WMF1272TEE")
      )
      (libsource (lib "eagle-import") (part "12.7K-1%0201"))
    )
    (comp (ref "R94")
      (value "4.64K 1%")
      (footprint "eagle-import:0201")
      (fields
        (field (name "LCSC_PART") "C166186")
        (field (name "MANUFACTURER") " RALEC")
        (field (name "MPN") "RTT014641FTH")
      )
      (libsource (lib "eagle-import") (part "4.64K-1%-0201"))
    )
    (comp (ref "R95")
      (value "4.64K 1%")
      (footprint "eagle-import:0201")
      (fields
        (field (name "LCSC_PART") "C166186")
        (field (name "MANUFACTURER") " RALEC")
        (field (name "MPN") "RTT014641FTH")
      )
      (libsource (lib "eagle-import") (part "4.64K-1%-0201"))
    )
    (comp (ref "R96")
      (value "8.87K 1%")
      (footprint "eagle-import:0201")
      (fields
        (field (name "LCSC_PART") "C423413")
        (field (name "MANUFACTURER") " UNI-ROYAL")
        (field (name "MPN") "0201WMF8871TEE")
      )
      (libsource (lib "eagle-import") (part "8.87K-1%-0201"))
    )
    (comp (ref "R97")
      (value "30.9K 1%")
      (footprint "eagle-import:0201")
      (fields (field (name "LCSC_PART") "C364366"))
      (libsource (lib "eagle-import") (part "30.9K-1%0201"))
    )
    (comp (ref "R98")
      (value "100K 1%")
      (footprint "eagle-import:0201")
      (fields (field (name "LCSC_PART") "C270364"))
      (libsource (lib "eagle-import") (part "100K-1%0201"))
    )
    (comp (ref "R99")
      (value "10K 1%")
      (footprint "eagle-import:0402")
      (fields
        (field (name "HQ_PART") "RE0207399")
        (field (name "LCSC_PART") "C25744")
        (field (name "MANUFACTURER") "ROHM")
      )
      (libsource (lib "eagle-import") (part "10K-1%0402"))
    )
    (comp (ref "R100")
      (value "10K 1%")
      (footprint "eagle-import:0402")
      (fields
        (field (name "HQ_PART") "RE0207399")
        (field (name "LCSC_PART") "C25744")
        (field (name "MANUFACTURER") "ROHM")
      )
      (libsource (lib "eagle-import") (part "10K-1%0402"))
    )
    (comp (ref "R101")
      (value "10K 1%")
      (footprint "eagle-import:0201")
      (fields
        (field (name "HQ_PART") "RE0208620")
        (field (name "LCSC_PART") "C473048")
        (field (name "MANUFACTURER") "FH")
      )
      (libsource (lib "eagle-import") (part "10K-1%0201"))
    )
    (comp (ref "R102")
      (value "10K 1%")
      (footprint "eagle-import:0402")
      (fields
        (field (name "HQ_PART") "RE0207399")
        (field (name "LCSC_PART") "C25744")
        (field (name "MANUFACTURER") "ROHM")
      )
      (libsource (lib "eagle-import") (part "10K-1%0402"))
    )
    (comp (ref "R103")
      (value "0.010R 1%")
      (footprint "eagle-import:2512")
      (fields
        (field (name "LCSC_PART") "C127692")
        (field (name "MANUFACTURER") " UNI-ROYAL")
        (field (name "MPN") "25121WF100MT4E")
      )
      (libsource (lib "eagle-import") (part "0.010R-1%-2512"))
    )
    (comp (ref "R104")
      (value "0R 1%")
      (footprint "eagle-import:0201")
      (fields
        (field (name "HA_PART") "RE0015349")
        (field (name "LCSC_PART") "C106227")
        (field (name "MANUFACTURER") "Yageo")
      )
      (libsource (lib "eagle-import") (part "0R0201"))
    )
    (comp (ref "R105")
      (value "49.9K 1%")
      (footprint "eagle-import:0201")
      (fields
        (field (name "HQ_PART") "RE0461584")
        (field (name "LCSC_PART") "C138136")
        (field (name "MANUFACTURER") "Yageo")
      )
      (libsource (lib "eagle-import") (part "49.9K-1%0201"))
    )
    (comp (ref "R106")
      (value "20K 1%")
      (footprint "eagle-import:0201")
      (fields (field (name "LCSC_PART") "C473466"))
      (libsource (lib "eagle-import") (part "20K-1%0201"))
    )
    (comp (ref "R107")
      (value "150K")
      (footprint "eagle-import:R0201")
      (libsource (lib "eagle-import") (part "R0201"))
    )
    (comp (ref "R108")
      (value "15K 1%")
      (footprint "eagle-import:0201")
      (fields (field (name "LCSC_PART") "C295774"))
      (libsource (lib "eagle-import") (part "15K-1%0201"))
    )
    (comp (ref "R109")
      (value "0.010R 1%")
      (footprint "eagle-import:2512")
      (fields
        (field (name "LCSC_PART") "C127692")
        (field (name "MANUFACTURER") " UNI-ROYAL")
        (field (name "MPN") "25121WF100MT4E")
      )
      (libsource (lib "eagle-import") (part "0.010R-1%-2512"))
    )
    (comp (ref "R110")
      (value "1R 1%")
      (footprint "eagle-import:0402")
      (fields
        (field (name "HQ_PART") "RE0322446")
        (field (name "MANUFACTURER") "RALEC")
        (field (name "MPN") "RTT021R00FTH")
      )
      (libsource (lib "eagle-import") (part "1R-1%0402"))
    )
    (comp (ref "R111")
      (value "1R 1%")
      (footprint "eagle-import:0402")
      (fields
        (field (name "HQ_PART") "RE0322446")
        (field (name "MANUFACTURER") "RALEC")
        (field (name "MPN") "RTT021R00FTH")
      )
      (libsource (lib "eagle-import") (part "1R-1%0402"))
    )
    (comp (ref "R112")
      (value "0R 1%")
      (footprint "eagle-import:0201")
      (fields
        (field (name "PACKAGE") "0201")
        (field (name "HA_PART") "RE0015349")
        (field (name "LCSC_PART") "C106227")
        (field (name "MANUFACTURER") "Yageo")
      )
      (libsource (lib "eagle-import") (part "0R0201"))
    )
    (comp (ref "R113")
      (value "0R 1%")
      (footprint "eagle-import:0201")
      (fields
        (field (name "PACKAGE") "0201")
        (field (name "HA_PART") "RE0015349")
        (field (name "LCSC_PART") "C106227")
        (field (name "MANUFACTURER") "Yageo")
      )
      (libsource (lib "eagle-import") (part "0R0201"))
    )
    (comp (ref "R114")
      (value "10K 1%")
      (footprint "eagle-import:0201")
      (fields
        (field (name "HQ_PART") "RE0208620")
        (field (name "LCSC_PART") "C473048")
        (field (name "MANUFACTURER") "FH")
      )
      (libsource (lib "eagle-import") (part "10K-1%0201"))
    )
    (comp (ref "R115")
      (value "1R 1%")
      (footprint "eagle-import:0603")
      (fields
        (field (name "PACKAGE") "0603")
        (field (name "HQ_PART") "RE0421839")
        (field (name "MANUFACTURER") "RALEC")
        (field (name "MPN") "RTT031R00FTP")
      )
      (libsource (lib "eagle-import") (part "1R-1%0603"))
    )
    (comp (ref "R116")
      (value "1R 1%")
      (footprint "eagle-import:0603")
      (fields
        (field (name "PACKAGE") "0603")
        (field (name "HQ_PART") "RE0421839")
        (field (name "MANUFACTURER") "RALEC")
        (field (name "MPN") "RTT031R00FTP")
      )
      (libsource (lib "eagle-import") (part "1R-1%0603"))
    )
    (comp (ref "R117")
      (value "1M 1%")
      (footprint "eagle-import:1206")
      (fields
        (field (name "PACKAGE") "1206")
        (field (name "HQ_PART") "RE0188103")
        (field (name "LCSC_PART") "C17927")
        (field (name "MANUFACTURER") "Uniohm")
      )
      (libsource (lib "eagle-import") (part "1M-1%1206"))
    )
    (comp (ref "T11")
      (value "DMP3013SFV")
      (footprint "eagle-import:POWERDI3333-8_UX_DIO-L")
      (fields (field (name "MANUFACTURER_PART_NUMBER") "DMP3013SFV-7"))
      (libsource (lib "eagle-import") (part "DMP3013SFV-7UX"))
    )
    (comp (ref "T12")
      (value "DMP3013SFV")
      (footprint "eagle-import:POWERDI3333-8_UX_DIO-L")
      (fields (field (name "MANUFACTURER_PART_NUMBER") "DMP3013SFV-7"))
      (libsource (lib "eagle-import") (part "DMP3013SFV-7UX"))
    )
    (comp (ref "T13")
      (value "DMP3013SFV")
      (footprint "eagle-import:POWERDI3333-8_UX_DIO-L")
      (fields (field (name "MANUFACTURER_PART_NUMBER") "DMP3013SFV-7"))
      (libsource (lib "eagle-import") (part "DMP3013SFV-7UX"))
    )
    (comp (ref "T14")
      (value "BSZ065N06")
      (footprint "eagle-import:POWERDI3333-8_UX_DIO-L")
      (fields
        (field (name "MANUFACTURER_PART_NUMBER") "IPZ40N04S5L7R4ATMA1")
        (field (name "COPYRIGHT") "Copyright (C) 2025 Ultra Librarian. All rights reserved.")
      )
      (libsource (lib "eagle-import") (part "IPZ40N04S5L7R4ATMA1"))
    )
    (comp (ref "T15")
      (value "BSZ065N06")
      (footprint "eagle-import:POWERDI3333-8_UX_DIO-L")
      (fields
        (field (name "MANUFACTURER_PART_NUMBER") "IPZ40N04S5L7R4ATMA1")
        (field (name "COPYRIGHT") "Copyright (C) 2025 Ultra Librarian. All rights reserved.")
      )
      (libsource (lib "eagle-import") (part "IPZ40N04S5L7R4ATMA1"))
    )
    (comp (ref "AVDD")
      (value "DNI")
      (footprint "eagle-import:TP-ROUND")
      (libsource (lib "eagle-import") (part "TP-ROUND"))
    )
    (comp (ref "C21")
      (value "4.7uF 10V")
      (footprint "eagle-import:0402")
      (fields (field (name "LCSC_PART") "C368809"))
      (libsource (lib "eagle-import") (part "4.7UF-10V0402"))
    )
    (comp (ref "C22")
      (value "4.7uF 10V")
      (footprint "eagle-import:0402")
      (fields (field (name "LCSC_PART") "C368809"))
      (libsource (lib "eagle-import") (part "4.7UF-10V0402"))
    )
    (comp (ref "C23")
      (value "100nF 25V")
      (footprint "eagle-import:0201")
      (fields
        (field (name "HQ_PART") "CA0183221")
        (field (name "LCSC_PART") "C76939")
        (field (name "MANUFACTURER") "Samsung")
      )
      (libsource (lib "eagle-import") (part "100NF-25V-0201"))
    )
    (comp (ref "C24")
      (value "100nF 25V")
      (footprint "eagle-import:0201")
      (fields
        (field (name "HQ_PART") "CA0183221")
        (field (name "LCSC_PART") "C76939")
        (field (name "MANUFACTURER") "Samsung")
      )
      (libsource (lib "eagle-import") (part "100NF-25V-0201"))
    )
    (comp (ref "C25")
      (value "100nF 25V")
      (footprint "eagle-import:0201")
      (fields
        (field (name "HQ_PART") "CA0183221")
        (field (name "LCSC_PART") "C76939")
        (field (name "MANUFACTURER") "Samsung")
      )
      (libsource (lib "eagle-import") (part "100NF-25V-0201"))
    )
    (comp (ref "C26")
      (value "4.7uF 10V")
      (footprint "eagle-import:0402")
      (fields (field (name "LCSC_PART") "C368809"))
      (libsource (lib "eagle-import") (part "4.7UF-10V0402"))
    )
    (comp (ref "C27")
      (value "100nF 25V")
      (footprint "eagle-import:0201")
      (fields
        (field (name "HQ_PART") "CA0183221")
        (field (name "LCSC_PART") "C76939")
        (field (name "MANUFACTURER") "Samsung")
      )
      (libsource (lib "eagle-import") (part "100NF-25V-0201"))
    )
    (comp (ref "C176")
      (value "100nF 25V")
      (footprint "eagle-import:0201")
      (fields
        (field (name "HQ_PART") "CA0183221")
        (field (name "LCSC_PART") "C76939")
        (field (name "MANUFACTURER") "Samsung")
      )
      (libsource (lib "eagle-import") (part "100NF-25V-0201"))
    )
    (comp (ref "C177")
      (value "15pF 50V")
      (footprint "eagle-import:0201")
      (fields
        (field (name "HQ_PART") "CA0136888")
        (field (name "LCSC_PART") "C22374851")
        (field (name "MANUFACTURER") "Yageo")
      )
      (libsource (lib "eagle-import") (part "15PF-50V0201"))
    )
    (comp (ref "C178")
      (value "15pF 50V")
      (footprint "eagle-import:0201")
      (fields
        (field (name "HQ_PART") "CA0136888")
        (field (name "LCSC_PART") "C22374851")
        (field (name "MANUFACTURER") "Yageo")
      )
      (libsource (lib "eagle-import") (part "15PF-50V0201"))
    )
    (comp (ref "C179")
      (value "1uF 10V")
      (footprint "eagle-import:0201")
      (fields (field (name "LCSC_PART") "C76935"))
      (libsource (lib "eagle-import") (part "1UF-10V0201"))
    )
    (comp (ref "C180")
      (value "100nF 25V")
      (footprint "eagle-import:0201")
      (fields
        (field (name "HQ_PART") "CA0183221")
        (field (name "LCSC_PART") "C76939")
        (field (name "MANUFACTURER") "Samsung")
      )
      (libsource (lib "eagle-import") (part "100NF-25V-0201"))
    )
    (comp (ref "C181")
      (value "100nF 25V")
      (footprint "eagle-import:0402")
      (fields
        (field (name "HQ_PART") "CA0176807")
        (field (name "LCSC_PART") "C56392")
        (field (name "MANUFACTURER") "Walsin")
      )
      (libsource (lib "eagle-import") (part "100NF-25V-0402"))
    )
    (comp (ref "C182")
      (value "100nF 25V")
      (footprint "eagle-import:0201")
      (fields
        (field (name "HQ_PART") "CA0183221")
        (field (name "LCSC_PART") "C76939")
        (field (name "MANUFACTURER") "Samsung")
      )
      (libsource (lib "eagle-import") (part "100NF-25V-0201"))
    )
    (comp (ref "C184")
      (value "100nF 25V")
      (footprint "eagle-import:0201")
      (fields
        (field (name "HQ_PART") "CA0183221")
        (field (name "LCSC_PART") "C76939")
        (field (name "MANUFACTURER") "Samsung")
      )
      (libsource (lib "eagle-import") (part "100NF-25V-0201"))
    )
    (comp (ref "C185")
      (value "100nF 25V")
      (footprint "eagle-import:0201")
      (fields
        (field (name "HQ_PART") "CA0183221")
        (field (name "LCSC_PART") "C76939")
        (field (name "MANUFACTURER") "Samsung")
      )
      (libsource (lib "eagle-import") (part "100NF-25V-0201"))
    )
    (comp (ref "C186")
      (value "100nF 25V")
      (footprint "eagle-import:0201")
      (fields
        (field (name "HQ_PART") "CA0183221")
        (field (name "LCSC_PART") "C76939")
        (field (name "MANUFACTURER") "Samsung")
      )
      (libsource (lib "eagle-import") (part "100NF-25V-0201"))
    )
    (comp (ref "C187")
      (value "100nF 25V")
      (footprint "eagle-import:0201")
      (fields
        (field (name "HQ_PART") "CA0183221")
        (field (name "LCSC_PART") "C76939")
        (field (name "MANUFACTURER") "Samsung")
      )
      (libsource (lib "eagle-import") (part "100NF-25V-0201"))
    )
    (comp (ref "C188")
      (value "100nF 25V")
      (footprint "eagle-import:0201")
      (fields
        (field (name "HQ_PART") "CA0183221")
        (field (name "LCSC_PART") "C76939")
        (field (name "MANUFACTURER") "Samsung")
      )
      (libsource (lib "eagle-import") (part "100NF-25V-0201"))
    )
    (comp (ref "C189")
      (value "100nF 25V")
      (footprint "eagle-import:0201")
      (fields
        (field (name "HQ_PART") "CA0183221")
        (field (name "LCSC_PART") "C76939")
        (field (name "MANUFACTURER") "Samsung")
      )
      (libsource (lib "eagle-import") (part "100NF-25V-0201"))
    )
    (comp (ref "C190")
      (value "100nF 25V")
      (footprint "eagle-import:0201")
      (fields
        (field (name "HQ_PART") "CA0183221")
        (field (name "LCSC_PART") "C76939")
        (field (name "MANUFACTURER") "Samsung")
      )
      (libsource (lib "eagle-import") (part "100NF-25V-0201"))
    )
    (comp (ref "C191")
      (value "100nF 25V")
      (footprint "eagle-import:0201")
      (fields
        (field (name "HQ_PART") "CA0183221")
        (field (name "LCSC_PART") "C76939")
        (field (name "MANUFACTURER") "Samsung")
      )
      (libsource (lib "eagle-import") (part "100NF-25V-0201"))
    )
    (comp (ref "C192")
      (value "100nF 25V")
      (footprint "eagle-import:0201")
      (fields
        (field (name "HQ_PART") "CA0183221")
        (field (name "LCSC_PART") "C76939")
        (field (name "MANUFACTURER") "Samsung")
      )
      (libsource (lib "eagle-import") (part "100NF-25V-0201"))
    )
    (comp (ref "C193")
      (value "100nF 25V")
      (footprint "eagle-import:0201")
      (fields
        (field (name "HQ_PART") "CA0183221")
        (field (name "LCSC_PART") "C76939")
        (field (name "MANUFACTURER") "Samsung")
      )
      (libsource (lib "eagle-import") (part "100NF-25V-0201"))
    )
    (comp (ref "C194")
      (value "100nF 25V")
      (footprint "eagle-import:0201")
      (fields
        (field (name "HQ_PART") "CA0183221")
        (field (name "LCSC_PART") "C76939")
        (field (name "MANUFACTURER") "Samsung")
      )
      (libsource (lib "eagle-import") (part "100NF-25V-0201"))
    )
    (comp (ref "C195")
      (value "100nF 25V")
      (footprint "eagle-import:0201")
      (fields
        (field (name "HQ_PART") "CA0183221")
        (field (name "LCSC_PART") "C76939")
        (field (name "MANUFACTURER") "Samsung")
      )
      (libsource (lib "eagle-import") (part "100NF-25V-0201"))
    )
    (comp (ref "C291")
      (value "100nF 25V")
      (footprint "eagle-import:0201")
      (fields
        (field (name "HQ_PART") "CA0183221")
        (field (name "LCSC_PART") "C76939")
        (field (name "MANUFACTURER") "Samsung")
      )
      (libsource (lib "eagle-import") (part "100NF-25V-0201"))
    )
    (comp (ref "IC26")
      (value "RP2354B")
      (footprint "eagle-import:QFN80-10X10")
      (fields (field (name "LCSC_PART") "C39843328") (field (name "MANUFACTURER") "Raspberry Pi "))
      (libsource (lib "eagle-import") (part "RP235XB"))
    )
    (comp (ref "IC27")
      (value "W25Q128JVPIQ")
      (footprint "eagle-import:SON127P600X500X75-8N")
      (fields
        (field (name "HQ_PART") "IC0150933")
        (field (name "LCSC_PART") "C190862")
        (field (name "MANUFACTURER") "Winbond")
      )
      (libsource (lib "eagle-import") (part "W25Q128JVP"))
    )
    (comp (ref "IC28")
      (value "MCP6001RT-I/OT")
      (footprint "eagle-import:SOT23-5")
      (fields
        (field (name "HQ_PART") "IC0119727")
        (field (name "LCSC_PART") "C154973")
        (field (name "MANUFACTURER") "MICROCHIP")
      )
      (libsource (lib "eagle-import") (part "MCP6001RT"))
    )
    (comp (ref "IC39")
      (value "W25Q128JVPIQ")
      (footprint "eagle-import:SON127P600X500X75-8N")
      (fields
        (field (name "HQ_PART") "IC0150933")
        (field (name "LCSC_PART") "C190862")
        (field (name "MANUFACTURER") "Winbond")
      )
      (libsource (lib "eagle-import") (part "W25Q128JVP"))
    )
    (comp (ref "L1")
      (value "3.3uH")
      (footprint "eagle-import:0805")
      (fields
        (field (name "HQ_PART") "IN47489734")
        (field (name "LCSC_PART") "C42411119")
        (field (name "MANUFACTURER") "Abracon LLC")
      )
      (libsource (lib "eagle-import") (part "3.3UH0805"))
    )
    (comp (ref "R24")
      (value "10K 1%")
      (footprint "eagle-import:0201")
      (fields
        (field (name "PACKAGE") "0201")
        (field (name "HQ_PART") "RE0208620")
        (field (name "LCSC_PART") "C473048")
        (field (name "MANUFACTURER") "FH")
      )
      (libsource (lib "eagle-import") (part "10K-1%0201"))
    )
    (comp (ref "R25")
      (value "27R 1%")
      (footprint "eagle-import:0201")
      (fields
        (field (name "PACKAGE") "0201")
        (field (name "HQ_PART") "RE0209327 ")
        (field (name "LCSC_PART") "C473051")
        (field (name "MANUFACTURER") "FH")
      )
      (libsource (lib "eagle-import") (part "27R-1%0201"))
    )
    (comp (ref "R26")
      (value "27R 1%")
      (footprint "eagle-import:0201")
      (fields
        (field (name "PACKAGE") "0201")
        (field (name "HQ_PART") "RE0209327 ")
        (field (name "LCSC_PART") "C473051")
        (field (name "MANUFACTURER") "FH")
      )
      (libsource (lib "eagle-import") (part "27R-1%0201"))
    )
    (comp (ref "R27")
      (value "33R 1%")
      (footprint "eagle-import:0402")
      (fields
        (field (name "PACKAGE") "0402")
        (field (name "HQ_PART") "RE0368295")
        (field (name "LCSC_PART") "C25105")
        (field (name "MANUFACTURER") "ROHM")
      )
      (libsource (lib "eagle-import") (part "33R-1%0402"))
    )
    (comp (ref "R28")
      (value "0R 1%")
      (footprint "eagle-import:0402")
      (fields
        (field (name "PACKAGE") "0402")
        (field (name "HQ_PART") "RE0250181")
        (field (name "LCSC_PART") "C17168")
        (field (name "MANUFACTURER") "YAGEO")
      )
      (libsource (lib "eagle-import") (part "0R0402"))
    )
    (comp (ref "R29")
      (value "0R 1%")
      (footprint "eagle-import:0402")
      (fields
        (field (name "PACKAGE") "0402")
        (field (name "HQ_PART") "RE0250181")
        (field (name "LCSC_PART") "C17168")
        (field (name "MANUFACTURER") "YAGEO")
      )
      (libsource (lib "eagle-import") (part "0R0402"))
    )
    (comp (ref "R209")
      (value "DNI")
      (footprint "eagle-import:R0201")
      (libsource (lib "eagle-import") (part "R0201"))
    )
    (comp (ref "R210")
      (value "1K 1%")
      (footprint "eagle-import:0201")
      (fields
        (field (name "HQ_PART") "RE0015967")
        (field (name "LCSC_PART") "C270365")
        (field (name "MANUFACTURER") "Yageo")
      )
      (libsource (lib "eagle-import") (part "1K-1%0201"))
    )
    (comp (ref "R211")
      (value "1K 1%")
      (footprint "eagle-import:0201")
      (fields
        (field (name "HQ_PART") "RE0015967")
        (field (name "LCSC_PART") "C270365")
        (field (name "MANUFACTURER") "Yageo")
      )
      (libsource (lib "eagle-import") (part "1K-1%0201"))
    )
    (comp (ref "R212")
      (value "4.7K 1%")
      (footprint "eagle-import:0201")
      (fields
        (field (name "HQ_PART") "RE0208670")
        (field (name "LCSC_PART") "C270346")
        (field (name "MANUFACTURER") "RALEC")
      )
      (libsource (lib "eagle-import") (part "4.7K-1%0201"))
    )
    (comp (ref "R278")
      (value "DNI")
      (footprint "eagle-import:R0201")
      (libsource (lib "eagle-import") (part "R0201"))
    )
    (comp (ref "REF1")
      (value "LM4040x30")
      (footprint "eagle-import:SOT23")
      (fields
        (field (name "HQ_PART") "IC0022950")
        (field (name "LCSC_PART") "C460604")
        (field (name "MANUFACTURER") "DIODES")
      )
      (libsource (lib "eagle-import") (part "LM4040BXX"))
    )
    (comp (ref "SW1")
      (value "B3U-1000P")
      (footprint "eagle-import:B3U-1000P")
      (fields
        (field (name "HQ_PART") "SW0036094 ")
        (field (name "LCSC_PART") "C231329")
        (field (name "MANUFACTURER") "Omron")
      )
      (libsource (lib "eagle-import") (part "B3U-1000P"))
    )
    (comp (ref "SW2")
      (value "B3U-1000P")
      (footprint "eagle-import:B3U-1000P")
      (fields
        (field (name "HQ_PART") "SW0036094 ")
        (field (name "LCSC_PART") "C231329")
        (field (name "MANUFACTURER") "Omron")
      )
      (libsource (lib "eagle-import") (part "B3U-1000P"))
    )
    (comp (ref "VREF")
      (value "DNI")
      (footprint "eagle-import:TP-ROUND")
      (libsource (lib "eagle-import") (part "TP-ROUND"))
    )
    (comp (ref "X1")
      (value "12MHz")
      (footprint "eagle-import:WE-XTAL_CFPX-180")
      (fields
        (field (name "HQ_PART") "CR0250194")
        (field (name "LCSC_PART") "C20625731")
        (field (name "MANUFACTURER") "TKD")
      )
      (libsource (lib "eagle-import") (part "CRYSTAL-3225X322512MSB4SI"))
    )
    (comp (ref "C233")
      (value "100nF 25V")
      (footprint "eagle-import:0201")
      (fields
        (field (name "HQ_PART") "CA0183221")
        (field (name "LCSC_PART") "C76939")
        (field (name "MANUFACTURER") "Samsung")
      )
      (libsource (lib "eagle-import") (part "100NF-25V-0201"))
    )
    (comp (ref "C234")
      (value "100nF")
      (footprint "eagle-import:0201")
      (libsource (lib "eagle-import") (part "C-0201"))
    )
    (comp (ref "C235")
      (value "100nF 25V")
      (footprint "eagle-import:0201")
      (fields
        (field (name "HQ_PART") "CA0183221")
        (field (name "LCSC_PART") "C76939")
        (field (name "MANUFACTURER") "Samsung")
      )
      (libsource (lib "eagle-import") (part "100NF-25V-0201"))
    )
    (comp (ref "C236")
      (value "33pF 50V")
      (footprint "eagle-import:0201")
      (fields (field (name "LCSC_PART") "C56903"))
      (libsource (lib "eagle-import") (part "33PF-50V0201"))
    )
    (comp (ref "C237")
      (value "22uF 25V")
      (footprint "eagle-import:1206")
      (fields
        (field (name "HQ_PART") "CA0182777")
        (field (name "LCSC_PART") "C12891")
        (field (name "MANUFACTURER") "FH")
      )
      (libsource (lib "eagle-import") (part "22UF-25V-1206"))
    )
    (comp (ref "C238")
      (value "22uF 25V")
      (footprint "eagle-import:1206")
      (fields
        (field (name "HQ_PART") "CA0182777")
        (field (name "LCSC_PART") "C12891")
        (field (name "MANUFACTURER") "FH")
      )
      (libsource (lib "eagle-import") (part "22UF-25V-1206"))
    )
    (comp (ref "C239")
      (value "22uF 25V")
      (footprint "eagle-import:1206")
      (fields
        (field (name "HQ_PART") "CA0182777")
        (field (name "LCSC_PART") "C12891")
        (field (name "MANUFACTURER") "FH")
      )
      (libsource (lib "eagle-import") (part "22UF-25V-1206"))
    )
    (comp (ref "C252")
      (value "330uF 50V")
      (footprint "eagle-import:10X10.5(DXL)")
      (fields (field (name "LCSC_PART") "C2895745") (field (name "MPN") "EEE-FT1H331AP"))
      (libsource (lib "eagle-import") (part "330UF-50V10X10.5(DXL)"))
    )
    (comp (ref "C253")
      (value "330uF 50V")
      (footprint "eagle-import:10X10.5(DXL)")
      (fields (field (name "LCSC_PART") "C2895745") (field (name "MPN") "EEE-FT1H331AP"))
      (libsource (lib "eagle-import") (part "330UF-50V10X10.5(DXL)"))
    )
    (comp (ref "C254")
      (value "330uF 50V")
      (footprint "eagle-import:10X10.5(DXL)")
      (fields (field (name "LCSC_PART") "C2895745") (field (name "MPN") "EEE-FT1H331AP"))
      (libsource (lib "eagle-import") (part "330UF-50V10X10.5(DXL)"))
    )
    (comp (ref "C255")
      (value "330uF 50V")
      (footprint "eagle-import:10X10.5(DXL)")
      (fields (field (name "LCSC_PART") "C2895745") (field (name "MPN") "EEE-FT1H331AP"))
      (libsource (lib "eagle-import") (part "330UF-50V10X10.5(DXL)"))
    )
    (comp (ref "C256")
      (value "330uF 50V")
      (footprint "eagle-import:10X10.5(DXL)")
      (fields (field (name "LCSC_PART") "C2895745") (field (name "MPN") "EEE-FT1H331AP"))
      (libsource (lib "eagle-import") (part "330UF-50V10X10.5(DXL)"))
    )
    (comp (ref "C257")
      (value "330uF 50V")
      (footprint "eagle-import:10X10.5(DXL)")
      (fields (field (name "LCSC_PART") "C2895745") (field (name "MPN") "EEE-FT1H331AP"))
      (libsource (lib "eagle-import") (part "330UF-50V10X10.5(DXL)"))
    )
    (comp (ref "C264")
      (value "22uF 25V")
      (footprint "eagle-import:1206")
      (fields
        (field (name "HQ_PART") "CA0182777")
        (field (name "LCSC_PART") "C12891")
        (field (name "MANUFACTURER") "FH")
      )
      (libsource (lib "eagle-import") (part "22UF-25V-1206"))
    )
    (comp (ref "C278")
      (value "22uF 25V")
      (footprint "eagle-import:1206")
      (fields
        (field (name "HQ_PART") "CA0182777")
        (field (name "LCSC_PART") "C12891")
        (field (name "MANUFACTURER") "FH")
      )
      (libsource (lib "eagle-import") (part "22UF-25V-1206"))
    )
    (comp (ref "C292")
      (value "100nF 25V")
      (footprint "eagle-import:0402")
      (fields
        (field (name "HQ_PART") "CA0176807")
        (field (name "LCSC_PART") "C56392")
        (field (name "MANUFACTURER") "Walsin")
      )
      (libsource (lib "eagle-import") (part "100NF-25V-0402"))
    )
    (comp (ref "C293")
      (value "100nF 25V")
      (footprint "eagle-import:0402")
      (fields
        (field (name "HQ_PART") "CA0176807")
        (field (name "LCSC_PART") "C56392")
        (field (name "MANUFACTURER") "Walsin")
      )
      (libsource (lib "eagle-import") (part "100NF-25V-0402"))
    )
    (comp (ref "C294")
      (value "100nF 25V")
      (footprint "eagle-import:0402")
      (fields
        (field (name "HQ_PART") "CA0176807")
        (field (name "LCSC_PART") "C56392")
        (field (name "MANUFACTURER") "Walsin")
      )
      (libsource (lib "eagle-import") (part "100NF-25V-0402"))
    )
    (comp (ref "C295")
      (value "33pF 50V")
      (footprint "eagle-import:0402")
      (fields
        (field (name "HQ_PART") "CA0484207")
        (field (name "LCSC_PART") "C107005")
        (field (name "MANUFACTURER") "PSA")
      )
      (libsource (lib "eagle-import") (part "33PF-50V0402"))
    )
    (comp (ref "C296")
      (value "22uF 25V")
      (footprint "eagle-import:1206")
      (fields
        (field (name "HQ_PART") "CA0182777")
        (field (name "LCSC_PART") "C12891")
        (field (name "MANUFACTURER") "FH")
      )
      (libsource (lib "eagle-import") (part "22UF-25V-1206"))
    )
    (comp (ref "C297")
      (value "22uF 25V")
      (footprint "eagle-import:1206")
      (fields
        (field (name "HQ_PART") "CA0182777")
        (field (name "LCSC_PART") "C12891")
        (field (name "MANUFACTURER") "FH")
      )
      (libsource (lib "eagle-import") (part "22UF-25V-1206"))
    )
    (comp (ref "C298")
      (value "22uF 25V")
      (footprint "eagle-import:1206")
      (fields
        (field (name "HQ_PART") "CA0182777")
        (field (name "LCSC_PART") "C12891")
        (field (name "MANUFACTURER") "FH")
      )
      (libsource (lib "eagle-import") (part "22UF-25V-1206"))
    )
    (comp (ref "C299")
      (value "100nF 25V")
      (footprint "eagle-import:0402")
      (fields
        (field (name "HQ_PART") "CA0176807")
        (field (name "LCSC_PART") "C56392")
        (field (name "MANUFACTURER") "Walsin")
      )
      (libsource (lib "eagle-import") (part "100NF-25V-0402"))
    )
    (comp (ref "C300")
      (value "100nF 25V")
      (footprint "eagle-import:0402")
      (fields
        (field (name "HQ_PART") "CA0176807")
        (field (name "LCSC_PART") "C56392")
        (field (name "MANUFACTURER") "Walsin")
      )
      (libsource (lib "eagle-import") (part "100NF-25V-0402"))
    )
    (comp (ref "C301")
      (value "100nF 25V")
      (footprint "eagle-import:0402")
      (fields
        (field (name "HQ_PART") "CA0176807")
        (field (name "LCSC_PART") "C56392")
        (field (name "MANUFACTURER") "Walsin")
      )
      (libsource (lib "eagle-import") (part "100NF-25V-0402"))
    )
    (comp (ref "C302")
      (value "33pF 50V")
      (footprint "eagle-import:0402")
      (fields
        (field (name "HQ_PART") "CA0484207")
        (field (name "LCSC_PART") "C107005")
        (field (name "MANUFACTURER") "PSA")
      )
      (libsource (lib "eagle-import") (part "33PF-50V0402"))
    )
    (comp (ref "C303")
      (value "22uF 25V")
      (footprint "eagle-import:1206")
      (fields
        (field (name "HQ_PART") "CA0182777")
        (field (name "LCSC_PART") "C12891")
        (field (name "MANUFACTURER") "FH")
      )
      (libsource (lib "eagle-import") (part "22UF-25V-1206"))
    )
    (comp (ref "C304")
      (value "22uF 25V")
      (footprint "eagle-import:1206")
      (fields
        (field (name "HQ_PART") "CA0182777")
        (field (name "LCSC_PART") "C12891")
        (field (name "MANUFACTURER") "FH")
      )
      (libsource (lib "eagle-import") (part "22UF-25V-1206"))
    )
    (comp (ref "D9")
      (value "SMBJ33A")
      (footprint "eagle-import:SMB")
      (libsource (lib "eagle-import") (part "DIODE-SMB"))
    )
    (comp (ref "D10")
      (value "SMBJ33A")
      (footprint "eagle-import:SMB")
      (libsource (lib "eagle-import") (part "DIODE-SMB"))
    )
    (comp (ref "D11")
      (value "SMBJ33A")
      (footprint "eagle-import:SMB")
      (libsource (lib "eagle-import") (part "DIODE-SMB"))
    )
    (comp (ref "F1")
      (value "2A")
      (footprint "eagle-import:FUSE_3544-2")
      (fields (field (name "MANUFACTURER") "Keystone") (field (name "MPN") "3544-2"))
      (libsource (lib "eagle-import") (part "BLADE-FUSE"))
    )
    (comp (ref "F2")
      (value "15A")
      (footprint "eagle-import:FUSE_3544-2")
      (fields (field (name "MANUFACTURER") "Keystone") (field (name "MPN") "3544-2"))
      (libsource (lib "eagle-import") (part "BLADE-FUSE"))
    )
    (comp (ref "F3")
      (value "15A")
      (footprint "eagle-import:FUSE_3544-2")
      (fields (field (name "MANUFACTURER") "Keystone") (field (name "MPN") "3544-2"))
      (libsource (lib "eagle-import") (part "BLADE-FUSE"))
    )
    (comp (ref "GND-1")
      (value "DNI")
      (footprint "eagle-import:TP-ROUND")
      (libsource (lib "eagle-import") (part "TP-ROUND"))
    )
    (comp (ref "GND-5")
      (value "DNI")
      (footprint "eagle-import:TP-ROUND")
      (libsource (lib "eagle-import") (part "TP-ROUND"))
    )
    (comp (ref "IC40")
      (value "MP2315GJ-Z")
      (footprint "eagle-import:SOT65P280X110-8N")
      (fields
        (field (name "HQ_PART") "IC0339027")
        (field (name "LCSC_PART") "C45889")
        (field (name "MANUFACTURER") "MPS")
      )
      (libsource (lib "eagle-import") (part "MP2315TSOT23-8"))
    )
    (comp (ref "IC41")
      (value "MP2315GJ-Z")
      (footprint "eagle-import:SOT65P280X110-8N")
      (fields
        (field (name "HQ_PART") "IC0339027")
        (field (name "LCSC_PART") "C45889")
        (field (name "MANUFACTURER") "MPS")
      )
      (libsource (lib "eagle-import") (part "MP2315TSOT23-8"))
    )
    (comp (ref "IC43")
      (value "MP2315GJ-Z")
      (footprint "eagle-import:SOT65P280X110-8N")
      (fields
        (field (name "HQ_PART") "IC0339027")
        (field (name "LCSC_PART") "C45889")
        (field (name "MANUFACTURER") "MPS")
      )
      (libsource (lib "eagle-import") (part "MP2315TSOT23-8"))
    )
    (comp (ref "J8")
      (value "691244510006")
      (footprint "eagle-import:691244510006")
      (libsource (lib "eagle-import") (part "691244510006"))
    )
    (comp (ref "L11")
      (value "4.7uH 3.5A")
      (footprint "eagle-import:SRR5228A")
      (fields
        (field (name "LCSC_PART") "C14258")
        (field (name "MANUFACTURER") "SXN")
        (field (name "MPN") "YP0503-4R7M")
      )
      (libsource (lib "eagle-import") (part "4.2UH"))
    )
    (comp (ref "L12")
      (value "4.7uH")
      (footprint "eagle-import:SRR5228A")
      (fields
        (field (name "HQ_PART") "IN0027228")
        (field (name "LCSC_PART") "C325964")
        (field (name "MANUFACTURER") "YJYCOIN")
      )
      (libsource (lib "eagle-import") (part "4.7UH"))
    )
    (comp (ref "L13")
      (value "4.7uH")
      (footprint "eagle-import:SRR5228A")
      (fields
        (field (name "HQ_PART") "IN0027228")
        (field (name "LCSC_PART") "C325964")
        (field (name "MANUFACTURER") "YJYCOIN")
      )
      (libsource (lib "eagle-import") (part "4.7UH"))
    )
    (comp (ref "R241")
      (value "49.9K 1%")
      (footprint "eagle-import:0201")
      (fields
        (field (name "HQ_PART") "RE0461584")
        (field (name "LCSC_PART") "C138136")
        (field (name "MANUFACTURER") "Yageo")
      )
      (libsource (lib "eagle-import") (part "49.9K-1%0201"))
    )
    (comp (ref "R242")
      (value "7.5K 1%")
      (footprint "eagle-import:0201")
      (fields (field (name "LCSC_PART") "C473504"))
      (libsource (lib "eagle-import") (part "7.5K-1%0201"))
    )
    (comp (ref "R243")
      (value "10R 1%")
      (footprint "eagle-import:0201")
      (fields
        (field (name "HQ_PART") "RE0210247")
        (field (name "LCSC_PART") "C270817")
        (field (name "MANUFACTURER") "Yageo")
      )
      (libsource (lib "eagle-import") (part "10R-1%0201"))
    )
    (comp (ref "R244")
      (value "100K 1%")
      (footprint "eagle-import:0201")
      (fields (field (name "LCSC_PART") "C270364"))
      (libsource (lib "eagle-import") (part "100K-1%0201"))
    )
    (comp (ref "R281")
      (value "9.09K 1%")
      (footprint "eagle-import:0402")
      (fields
        (field (name "HQ_PART") "RE0203888")
        (field (name "LCSC_PART") "C11549")
        (field (name "MANUFACTURER") "Yageo")
      )
      (libsource (lib "eagle-import") (part "9.09K-1%0402"))
    )
    (comp (ref "R282")
      (value "10R 1%")
      (footprint "eagle-import:0402")
      (fields
        (field (name "HQ_PART") "RE0191560")
        (field (name "LCSC_PART") "C25077")
        (field (name "MANUFACTURER") "Uniohm")
      )
      (libsource (lib "eagle-import") (part "10R-1%0402"))
    )
    (comp (ref "R283")
      (value "20K 1%")
      (footprint "eagle-import:0402")
      (fields
        (field (name "HQ_PART") "RE0203337")
        (field (name "LCSC_PART") "C25765")
        (field (name "MANUFACTURER") "FH")
      )
      (libsource (lib "eagle-import") (part "20K-1%0402"))
    )
    (comp (ref "R284")
      (value "40.2K 1%")
      (footprint "eagle-import:0402")
      (fields
        (field (name "HQ_PART") "RE0063264")
        (field (name "LCSC_PART") "C25893")
        (field (name "MANUFACTURER") "Yageo")
      )
      (libsource (lib "eagle-import") (part "40.2K-1%0402"))
    )
    (comp (ref "R285")
      (value "7.5K 1%")
      (footprint "eagle-import:0402")
      (fields
        (field (name "HQ_PART") "RE0188271")
        (field (name "LCSC_PART") "C25918")
        (field (name "MANUFACTURER") "Uniohm")
      )
      (libsource (lib "eagle-import") (part "7.5K-1%0402"))
    )
    (comp (ref "R286")
      (value "100K 1%")
      (footprint "eagle-import:0402")
      (fields
        (field (name "HQ_PART") "RE0203322")
        (field (name "LCSC_PART") "C25741")
        (field (name "MANUFACTURER") "FH")
      )
      (libsource (lib "eagle-import") (part "100K-1%0402"))
    )
    (comp (ref "R287")
      (value "DNI")
      (footprint "eagle-import:0402")
      (libsource (lib "eagle-import") (part "R0402"))
    )
    (comp (ref "R289")
      (value "10K 1%")
      (footprint "eagle-import:0402")
      (fields
        (field (name "HQ_PART") "RE0207399")
        (field (name "LCSC_PART") "C25744")
        (field (name "MANUFACTURER") "ROHM")
      )
      (libsource (lib "eagle-import") (part "10K-1%0402"))
    )
    (comp (ref "R290")
      (value "9.09K 1%")
      (footprint "eagle-import:0402")
      (fields
        (field (name "HQ_PART") "RE0203888")
        (field (name "LCSC_PART") "C11549")
        (field (name "MANUFACTURER") "Yageo")
      )
      (libsource (lib "eagle-import") (part "9.09K-1%0402"))
    )
    (comp (ref "R291")
      (value "10R 1%")
      (footprint "eagle-import:0402")
      (fields
        (field (name "HQ_PART") "RE0191560")
        (field (name "LCSC_PART") "C25077")
        (field (name "MANUFACTURER") "Uniohm")
      )
      (libsource (lib "eagle-import") (part "10R-1%0402"))
    )
    (comp (ref "R292")
      (value "20K 1%")
      (footprint "eagle-import:0402")
      (fields
        (field (name "HQ_PART") "RE0203337")
        (field (name "LCSC_PART") "C25765")
        (field (name "MANUFACTURER") "FH")
      )
      (libsource (lib "eagle-import") (part "20K-1%0402"))
    )
    (comp (ref "R293")
      (value "40.2K 1%")
      (footprint "eagle-import:0402")
      (fields
        (field (name "HQ_PART") "RE0063264")
        (field (name "LCSC_PART") "C25893")
        (field (name "MANUFACTURER") "Yageo")
      )
      (libsource (lib "eagle-import") (part "40.2K-1%0402"))
    )
    (comp (ref "R294")
      (value "7.5K 1%")
      (footprint "eagle-import:0402")
      (fields
        (field (name "HQ_PART") "RE0188271")
        (field (name "LCSC_PART") "C25918")
        (field (name "MANUFACTURER") "Uniohm")
      )
      (libsource (lib "eagle-import") (part "7.5K-1%0402"))
    )
    (comp (ref "R295")
      (value "100K 1%")
      (footprint "eagle-import:0402")
      (fields
        (field (name "HQ_PART") "RE0203322")
        (field (name "LCSC_PART") "C25741")
        (field (name "MANUFACTURER") "FH")
      )
      (libsource (lib "eagle-import") (part "100K-1%0402"))
    )
    (comp (ref "R296")
      (value "DNI")
      (footprint "eagle-import:0402")
      (libsource (lib "eagle-import") (part "R0402"))
    )
    (comp (ref "R298")
      (value "10K 1%")
      (footprint "eagle-import:0402")
      (fields
        (field (name "HQ_PART") "RE0207399")
        (field (name "LCSC_PART") "C25744")
        (field (name "MANUFACTURER") "ROHM")
      )
      (libsource (lib "eagle-import") (part "10K-1%0402"))
    )
    (comp (ref "RFB3")
      (value "40.2K 1%")
      (footprint "eagle-import:0201")
      (fields (field (name "LCSC_PART") "C274875"))
      (libsource (lib "eagle-import") (part "40.2K-1%0201"))
    )
    (comp (ref "RFB4")
      (value "12.7K 1%")
      (footprint "eagle-import:0201")
      (fields
        (field (name "LCSC_PART") "C423755")
        (field (name "MANUFACTURER") "UNI-ROYAL")
        (field (name "MPN") "0201WMF1272TEE")
      )
      (libsource (lib "eagle-import") (part "12.7K-1%0201"))
    )
    (comp (ref "RT1")
      (value "33K 1%")
      (footprint "eagle-import:0201")
      (fields (field (name "LCSC_PART") "C473534"))
      (libsource (lib "eagle-import") (part "33K-1%0201"))
    )
    (comp (ref "VO3")
      (value "DNI")
      (footprint "eagle-import:TP-ROUND")
      (libsource (lib "eagle-import") (part "TP-ROUND"))
    )
    (comp (ref "VO5A")
      (value "DNI")
      (footprint "eagle-import:TP-ROUND")
      (libsource (lib "eagle-import") (part "TP-ROUND"))
    )
    (comp (ref "VO5B")
      (value "DNI")
      (footprint "eagle-import:TP-ROUND")
      (libsource (lib "eagle-import") (part "TP-ROUND"))
    )
    (comp (ref "C135")
      (value "1uF 10V")
      (footprint "eagle-import:0201")
      (fields (field (name "LCSC_PART") "C76935"))
      (libsource (lib "eagle-import") (part "1UF-10V0201"))
    )
    (comp (ref "C136")
      (value "1uF 10V")
      (footprint "eagle-import:0201")
      (fields (field (name "LCSC_PART") "C76935"))
      (libsource (lib "eagle-import") (part "1UF-10V0201"))
    )
    (comp (ref "C137")
      (value "1uF 50V")
      (footprint "eagle-import:0603")
      (fields (field (name "LCSC_PART") "C15849"))
      (libsource (lib "eagle-import") (part "1UF-50V0603"))
    )
    (comp (ref "C138")
      (value "4.7uF 25V")
      (footprint "eagle-import:0402")
      (fields
        (field (name "HQ_PART") "ZHLM0023346")
        (field (name "LCSC_PART") "C22367824")
        (field (name "MANUFACTURER") "Murata")
      )
      (libsource (lib "eagle-import") (part "4.7UF-25V0402"))
    )
    (comp (ref "C139")
      (value "10nF 50V")
      (footprint "eagle-import:0201")
      (fields (field (name "LCSC_PART") "C5142551"))
      (libsource (lib "eagle-import") (part "10NF-50V-0201"))
    )
    (comp (ref "C140")
      (value "100pF 50V")
      (footprint "eagle-import:0201")
      (fields
        (field (name "HQ_PART") "CA0177921")
        (field (name "MANUFACTURER") "DARFON")
        (field (name "MPN") "C0603NP0101JGT")
      )
      (libsource (lib "eagle-import") (part "100PF-50V0201"))
    )
    (comp (ref "C141")
      (value "10nF 50V")
      (footprint "eagle-import:0201")
      (fields (field (name "LCSC_PART") "C5142551"))
      (libsource (lib "eagle-import") (part "10NF-50V-0201"))
    )
    (comp (ref "C142")
      (value "100nF 50V")
      (footprint "eagle-import:0402")
      (fields (field (name "LCSC_PART") "C307331"))
      (libsource (lib "eagle-import") (part "100NF-50V-0402"))
    )
    (comp (ref "C143")
      (value "100nF 50V")
      (footprint "eagle-import:0402")
      (fields (field (name "LCSC_PART") "C307331"))
      (libsource (lib "eagle-import") (part "100NF-50V-0402"))
    )
    (comp (ref "C144")
      (value "10uF 50V")
      (footprint "eagle-import:0805")
      (fields (field (name "LCSC_PART") "C440198"))
      (libsource (lib "eagle-import") (part "10UF-50V-0805"))
    )
    (comp (ref "C145")
      (value "10uF 50V")
      (footprint "eagle-import:0805")
      (fields (field (name "LCSC_PART") "C440198"))
      (libsource (lib "eagle-import") (part "10UF-50V-0805"))
    )
    (comp (ref "C146")
      (value "1uF 50V")
      (footprint "eagle-import:0805")
      (fields
        (field (name "HQ_PART") "CA0182352")
        (field (name "LCSC_PART") "C28323")
        (field (name "MANUFACTURER") "TDK")
      )
      (libsource (lib "eagle-import") (part "1UF-50V0805"))
    )
    (comp (ref "C147")
      (value "100uF 50V")
      (footprint "eagle-import:6.3X7.7(DXL)")
      (fields
        (field (name "HQ_PART") "ZHLM0353527")
        (field (name "LCSC_PART") "C3151829")
        (field (name "MANUFACTURER") "ROQANG")
      )
      (libsource (lib "eagle-import") (part "100UF-50V6.3X7.7(DXL)"))
    )
    (comp (ref "C148")
      (value "1uF 50V")
      (footprint "eagle-import:0402")
      (fields (field (name "LCSC_PART") "C1518208"))
      (libsource (lib "eagle-import") (part "1UF-50V0402"))
    )
    (comp (ref "C149")
      (value "10uF 50V")
      (footprint "eagle-import:0805")
      (fields (field (name "LCSC_PART") "C440198"))
      (libsource (lib "eagle-import") (part "10UF-50V-0805"))
    )
    (comp (ref "C150")
      (value "10uF 50V")
      (footprint "eagle-import:0805")
      (fields (field (name "LCSC_PART") "C440198"))
      (libsource (lib "eagle-import") (part "10UF-50V-0805"))
    )
    (comp (ref "C151")
      (value "10uF 50V")
      (footprint "eagle-import:0805")
      (fields (field (name "LCSC_PART") "C440198"))
      (libsource (lib "eagle-import") (part "10UF-50V-0805"))
    )
    (comp (ref "C152")
      (value "100nF 25V")
      (footprint "eagle-import:0201")
      (fields
        (field (name "HQ_PART") "CA0183221")
        (field (name "LCSC_PART") "C76939")
        (field (name "MANUFACTURER") "Samsung")
      )
      (libsource (lib "eagle-import") (part "100NF-25V-0201"))
    )
    (comp (ref "C153")
      (value "100nF 25V")
      (footprint "eagle-import:0201")
      (fields
        (field (name "HQ_PART") "CA0183221")
        (field (name "LCSC_PART") "C76939")
        (field (name "MANUFACTURER") "Samsung")
      )
      (libsource (lib "eagle-import") (part "100NF-25V-0201"))
    )
    (comp (ref "C154")
      (value "1uF 50V")
      (footprint "eagle-import:0402")
      (fields (field (name "PACKAGE") "0402") (field (name "LCSC_PART") "C1518208"))
      (libsource (lib "eagle-import") (part "1UF-50V0402"))
    )
    (comp (ref "C155")
      (value "2.2nF 50V")
      (footprint "eagle-import:0402")
      (fields
        (field (name "PACKAGE") "0402")
        (field (name "HQ_PART") "CA0176616")
        (field (name "MANUFACTURER") "WALSIN")
        (field (name "MPN") "0402B222K500CT")
      )
      (libsource (lib "eagle-import") (part "2.2NF-50V-0402"))
    )
    (comp (ref "C156")
      (value "2.2nF 50V")
      (footprint "eagle-import:0402")
      (fields
        (field (name "PACKAGE") "0402")
        (field (name "HQ_PART") "CA0176616")
        (field (name "MANUFACTURER") "WALSIN")
        (field (name "MPN") "0402B222K500CT")
      )
      (libsource (lib "eagle-import") (part "2.2NF-50V-0402"))
    )
    (comp (ref "C157")
      (value "10uF 50V")
      (footprint "eagle-import:0805")
      (fields (field (name "LCSC_PART") "C440198"))
      (libsource (lib "eagle-import") (part "10UF-50V-0805"))
    )
    (comp (ref "C158")
      (value "330uF 50V")
      (footprint "eagle-import:10X10.5(DXL)")
      (fields (field (name "LCSC_PART") "C2895745") (field (name "MPN") "EEE-FT1H331AP"))
      (libsource (lib "eagle-import") (part "330UF-50V10X10.5(DXL)"))
    )
    (comp (ref "C159")
      (value "1nF 2kV")
      (footprint "eagle-import:1206")
      (fields
        (field (name "PACKAGE") "1206")
        (field (name "HQ_PART") "CA0134884")
        (field (name "LCSC_PART") "C173242")
        (field (name "MANUFACTURER") "Johanson Dielectrics ")
      )
      (libsource (lib "eagle-import") (part "1NF-2KV"))
    )
    (comp (ref "IC21")
      (value "TPS552882")
      (footprint "eagle-import:RPM0026A-MFG")
      (fields
        (field (name "MANUFACTURER_PART_NUMBER") "TPS552882QRPMRQ1")
        (field (name "COPYRIGHT") "Copyright (C) 2025 Ultra Librarian. All rights reserved.")
      )
      (libsource (lib "eagle-import") (part "TPS552882"))
    )
    (comp (ref "IC22")
      (value "INA219BIDCNT")
      (footprint "eagle-import:SOT23-8")
      (fields
        (field (name "HQ_PART") "IC0063216")
        (field (name "LCSC_PART") "C2653868")
        (field (name "MANUFACTURER") "Texas Instruments")
      )
      (libsource (lib "eagle-import") (part "INA219BIDCNT"))
    )
    (comp (ref "IC23")
      (value "STUSB4710AQ1TR")
      (footprint "eagle-import:QFN50P300X300X55-16N")
      (libsource (lib "eagle-import") (part "STUSB4710AQ1TR"))
    )
    (comp (ref "L6")
      (value "4.7uH 11.3A")
      (footprint "eagle-import:WE-PDHV_1280")
      (fields
        (field (name "LCSC_PART") "C2998768")
        (field (name "MANUFACTURER") "Sumida")
        (field (name "MPN") "CDRH127NP-4R7NC")
      )
      (libsource (lib "eagle-import") (part "4.7UH-PWR"))
    )
    (comp (ref "PORT5")
      (value "632722100213")
      (footprint "eagle-import:632722100213")
      (fields
        (field (name "LCSC_PART") "C2927029")
        (field (name "MANUFACTURER") "DEALON")
        (field (name "MPN") "USB-TYPE-C-009 ")
      )
      (libsource (lib "eagle-import") (part "USB-C-POWERONLY"))
    )
    (comp (ref "R144")
      (value "200K 1%")
      (footprint "eagle-import:0201")
      (fields (field (name "LCSC_PART") "C270357"))
      (libsource (lib "eagle-import") (part "200K-1%0201"))
    )
    (comp (ref "R145")
      (value "12.7K 1%")
      (footprint "eagle-import:0201")
      (fields
        (field (name "LCSC_PART") "C423755")
        (field (name "MANUFACTURER") "UNI-ROYAL")
        (field (name "MPN") "0201WMF1272TEE")
      )
      (libsource (lib "eagle-import") (part "12.7K-1%0201"))
    )
    (comp (ref "R146")
      (value "4.64K 1%")
      (footprint "eagle-import:0201")
      (fields
        (field (name "LCSC_PART") "C166186")
        (field (name "MANUFACTURER") " RALEC")
        (field (name "MPN") "RTT014641FTH")
      )
      (libsource (lib "eagle-import") (part "4.64K-1%-0201"))
    )
    (comp (ref "R147")
      (value "4.64K 1%")
      (footprint "eagle-import:0201")
      (fields
        (field (name "LCSC_PART") "C166186")
        (field (name "MANUFACTURER") " RALEC")
        (field (name "MPN") "RTT014641FTH")
      )
      (libsource (lib "eagle-import") (part "4.64K-1%-0201"))
    )
    (comp (ref "R148")
      (value "8.87K 1%")
      (footprint "eagle-import:0201")
      (fields
        (field (name "LCSC_PART") "C423413")
        (field (name "MANUFACTURER") " UNI-ROYAL")
        (field (name "MPN") "0201WMF8871TEE")
      )
      (libsource (lib "eagle-import") (part "8.87K-1%-0201"))
    )
    (comp (ref "R149")
      (value "30.9K 1%")
      (footprint "eagle-import:0201")
      (fields (field (name "LCSC_PART") "C364366"))
      (libsource (lib "eagle-import") (part "30.9K-1%0201"))
    )
    (comp (ref "R150")
      (value "100K 1%")
      (footprint "eagle-import:0201")
      (fields (field (name "LCSC_PART") "C270364"))
      (libsource (lib "eagle-import") (part "100K-1%0201"))
    )
    (comp (ref "R151")
      (value "10K 1%")
      (footprint "eagle-import:0402")
      (fields
        (field (name "HQ_PART") "RE0207399")
        (field (name "LCSC_PART") "C25744")
        (field (name "MANUFACTURER") "ROHM")
      )
      (libsource (lib "eagle-import") (part "10K-1%0402"))
    )
    (comp (ref "R152")
      (value "10K 1%")
      (footprint "eagle-import:0402")
      (fields
        (field (name "HQ_PART") "RE0207399")
        (field (name "LCSC_PART") "C25744")
        (field (name "MANUFACTURER") "ROHM")
      )
      (libsource (lib "eagle-import") (part "10K-1%0402"))
    )
    (comp (ref "R153")
      (value "10K 1%")
      (footprint "eagle-import:0201")
      (fields
        (field (name "HQ_PART") "RE0208620")
        (field (name "LCSC_PART") "C473048")
        (field (name "MANUFACTURER") "FH")
      )
      (libsource (lib "eagle-import") (part "10K-1%0201"))
    )
    (comp (ref "R154")
      (value "10K 1%")
      (footprint "eagle-import:0402")
      (fields
        (field (name "HQ_PART") "RE0207399")
        (field (name "LCSC_PART") "C25744")
        (field (name "MANUFACTURER") "ROHM")
      )
      (libsource (lib "eagle-import") (part "10K-1%0402"))
    )
    (comp (ref "R155")
      (value "0.010R 1%")
      (footprint "eagle-import:2512")
      (fields
        (field (name "LCSC_PART") "C127692")
        (field (name "MANUFACTURER") " UNI-ROYAL")
        (field (name "MPN") "25121WF100MT4E")
      )
      (libsource (lib "eagle-import") (part "0.010R-1%-2512"))
    )
    (comp (ref "R156")
      (value "0R 1%")
      (footprint "eagle-import:0201")
      (fields
        (field (name "HA_PART") "RE0015349")
        (field (name "LCSC_PART") "C106227")
        (field (name "MANUFACTURER") "Yageo")
      )
      (libsource (lib "eagle-import") (part "0R0201"))
    )
    (comp (ref "R157")
      (value "49.9K 1%")
      (footprint "eagle-import:0201")
      (fields
        (field (name "HQ_PART") "RE0461584")
        (field (name "LCSC_PART") "C138136")
        (field (name "MANUFACTURER") "Yageo")
      )
      (libsource (lib "eagle-import") (part "49.9K-1%0201"))
    )
    (comp (ref "R158")
      (value "20K 1%")
      (footprint "eagle-import:0201")
      (fields (field (name "LCSC_PART") "C473466"))
      (libsource (lib "eagle-import") (part "20K-1%0201"))
    )
    (comp (ref "R159")
      (value "150K")
      (footprint "eagle-import:R0201")
      (libsource (lib "eagle-import") (part "R0201"))
    )
    (comp (ref "R160")
      (value "15K 1%")
      (footprint "eagle-import:0201")
      (fields (field (name "LCSC_PART") "C295774"))
      (libsource (lib "eagle-import") (part "15K-1%0201"))
    )
    (comp (ref "R161")
      (value "0.010R 1%")
      (footprint "eagle-import:2512")
      (fields
        (field (name "LCSC_PART") "C127692")
        (field (name "MANUFACTURER") " UNI-ROYAL")
        (field (name "MPN") "25121WF100MT4E")
      )
      (libsource (lib "eagle-import") (part "0.010R-1%-2512"))
    )
    (comp (ref "R162")
      (value "1R 1%")
      (footprint "eagle-import:0402")
      (fields
        (field (name "HQ_PART") "RE0322446")
        (field (name "MANUFACTURER") "RALEC")
        (field (name "MPN") "RTT021R00FTH")
      )
      (libsource (lib "eagle-import") (part "1R-1%0402"))
    )
    (comp (ref "R163")
      (value "1R 1%")
      (footprint "eagle-import:0402")
      (fields
        (field (name "HQ_PART") "RE0322446")
        (field (name "MANUFACTURER") "RALEC")
        (field (name "MPN") "RTT021R00FTH")
      )
      (libsource (lib "eagle-import") (part "1R-1%0402"))
    )
    (comp (ref "R164")
      (value "0R 1%")
      (footprint "eagle-import:0201")
      (fields
        (field (name "PACKAGE") "0201")
        (field (name "HA_PART") "RE0015349")
        (field (name "LCSC_PART") "C106227")
        (field (name "MANUFACTURER") "Yageo")
      )
      (libsource (lib "eagle-import") (part "0R0201"))
    )
    (comp (ref "R165")
      (value "0R 1%")
      (footprint "eagle-import:0201")
      (fields
        (field (name "PACKAGE") "0201")
        (field (name "HA_PART") "RE0015349")
        (field (name "LCSC_PART") "C106227")
        (field (name "MANUFACTURER") "Yageo")
      )
      (libsource (lib "eagle-import") (part "0R0201"))
    )
    (comp (ref "R166")
      (value "10K 1%")
      (footprint "eagle-import:0201")
      (fields
        (field (name "HQ_PART") "RE0208620")
        (field (name "LCSC_PART") "C473048")
        (field (name "MANUFACTURER") "FH")
      )
      (libsource (lib "eagle-import") (part "10K-1%0201"))
    )
    (comp (ref "R167")
      (value "1R 1%")
      (footprint "eagle-import:0603")
      (fields
        (field (name "PACKAGE") "0603")
        (field (name "HQ_PART") "RE0421839")
        (field (name "MANUFACTURER") "RALEC")
        (field (name "MPN") "RTT031R00FTP")
      )
      (libsource (lib "eagle-import") (part "1R-1%0603"))
    )
    (comp (ref "R168")
      (value "1R 1%")
      (footprint "eagle-import:0603")
      (fields
        (field (name "PACKAGE") "0603")
        (field (name "HQ_PART") "RE0421839")
        (field (name "MANUFACTURER") "RALEC")
        (field (name "MPN") "RTT031R00FTP")
      )
      (libsource (lib "eagle-import") (part "1R-1%0603"))
    )
    (comp (ref "R169")
      (value "1M 1%")
      (footprint "eagle-import:1206")
      (fields
        (field (name "PACKAGE") "1206")
        (field (name "HQ_PART") "RE0188103")
        (field (name "LCSC_PART") "C17927")
        (field (name "MANUFACTURER") "Uniohm")
      )
      (libsource (lib "eagle-import") (part "1M-1%1206"))
    )
    (comp (ref "T21")
      (value "DMP3013SFV")
      (footprint "eagle-import:POWERDI3333-8_UX_DIO-L")
      (fields (field (name "MANUFACTURER_PART_NUMBER") "DMP3013SFV-7"))
      (libsource (lib "eagle-import") (part "DMP3013SFV-7UX"))
    )
    (comp (ref "T22")
      (value "DMP3013SFV")
      (footprint "eagle-import:POWERDI3333-8_UX_DIO-L")
      (fields (field (name "MANUFACTURER_PART_NUMBER") "DMP3013SFV-7"))
      (libsource (lib "eagle-import") (part "DMP3013SFV-7UX"))
    )
    (comp (ref "T23")
      (value "DMP3013SFV")
      (footprint "eagle-import:POWERDI3333-8_UX_DIO-L")
      (fields (field (name "MANUFACTURER_PART_NUMBER") "DMP3013SFV-7"))
      (libsource (lib "eagle-import") (part "DMP3013SFV-7UX"))
    )
    (comp (ref "T24")
      (value "BSZ065N06")
      (footprint "eagle-import:POWERDI3333-8_UX_DIO-L")
      (fields
        (field (name "MANUFACTURER_PART_NUMBER") "IPZ40N04S5L7R4ATMA1")
        (field (name "COPYRIGHT") "Copyright (C) 2025 Ultra Librarian. All rights reserved.")
      )
      (libsource (lib "eagle-import") (part "IPZ40N04S5L7R4ATMA1"))
    )
    (comp (ref "T25")
      (value "BSZ065N06")
      (footprint "eagle-import:POWERDI3333-8_UX_DIO-L")
      (fields
        (field (name "MANUFACTURER_PART_NUMBER") "IPZ40N04S5L7R4ATMA1")
        (field (name "COPYRIGHT") "Copyright (C) 2025 Ultra Librarian. All rights reserved.")
      )
      (libsource (lib "eagle-import") (part "IPZ40N04S5L7R4ATMA1"))
    )
    (comp (ref "C183")
      (value "100nF 25V")
      (footprint "eagle-import:0201")
      (fields
        (field (name "HQ_PART") "CA0183221")
        (field (name "LCSC_PART") "C76939")
        (field (name "MANUFACTURER") "Samsung")
      )
      (libsource (lib "eagle-import") (part "100NF-25V-0201"))
    )
    (comp (ref "D12")
      (value "HDMIULC6-4SC6Y")
      (footprint "eagle-import:SOT23-6")
      (libsource (lib "eagle-import") (part "HDMIULC6-4SC6Y"))
    )
    (comp (ref "IC29")
      (value "CAT24C256HU4IGT3")
      (footprint "eagle-import:SON50P300X200X50-9T130X140N")
      (fields
        (field (name "HQ_PART") "IC0066897")
        (field (name "LCSC_PART") "C233771")
        (field (name "MANUFACTURER") "ON")
      )
      (libsource (lib "eagle-import") (part "CAT24C256-HU4"))
    )
    (comp (ref "JTAG")
      (value "3220_10_0300_00")
      (footprint "eagle-import:3220_10_0300_00")
      (fields (field (name "MANUFACTURER") "CNC Tech") (field (name "MPN") "3220-10-0300-00 "))
      (libsource (lib "eagle-import") (part "3220_10_0300_00"))
    )
    (comp (ref "R207")
      (value "3.3K 1%")
      (footprint "eagle-import:_0603X4-1206")
      (fields
        (field (name "HQ_PART") "RE0093863")
        (field (name "LCSC_PART") "C1734380")
        (field (name "MANUFACTURER") "Yageo")
      )
      (libsource (lib "eagle-import") (part "3.3K-1%_ARRAY0603X4-1206"))
    )
    (comp (ref "R213")
      (value "NC")
      (footprint "eagle-import:R0201")
      (libsource (lib "eagle-import") (part "R0201"))
    )
    (comp (ref "R214")
      (value "4.7K 1%")
      (footprint "eagle-import:0201")
      (fields
        (field (name "HQ_PART") "RE0208670")
        (field (name "LCSC_PART") "C270346")
        (field (name "MANUFACTURER") "RALEC")
      )
      (libsource (lib "eagle-import") (part "4.7K-1%0201"))
    )
    (comp (ref "C56")
      (value "1uF 10V")
      (footprint "eagle-import:0201")
      (fields (field (name "LCSC_PART") "C76935"))
      (libsource (lib "eagle-import") (part "1UF-10V0201"))
    )
    (comp (ref "C57")
      (value "1uF 10V")
      (footprint "eagle-import:0201")
      (fields (field (name "LCSC_PART") "C76935"))
      (libsource (lib "eagle-import") (part "1UF-10V0201"))
    )
    (comp (ref "C58")
      (value "1uF 50V")
      (footprint "eagle-import:0603")
      (fields (field (name "LCSC_PART") "C15849"))
      (libsource (lib "eagle-import") (part "1UF-50V0603"))
    )
    (comp (ref "C59")
      (value "4.7uF 25V")
      (footprint "eagle-import:0402")
      (fields
        (field (name "HQ_PART") "ZHLM0023346")
        (field (name "LCSC_PART") "C22367824")
        (field (name "MANUFACTURER") "Murata")
      )
      (libsource (lib "eagle-import") (part "4.7UF-25V0402"))
    )
    (comp (ref "C60")
      (value "10nF 50V")
      (footprint "eagle-import:0201")
      (fields (field (name "LCSC_PART") "C5142551"))
      (libsource (lib "eagle-import") (part "10NF-50V-0201"))
    )
    (comp (ref "C61")
      (value "100pF 50V")
      (footprint "eagle-import:0201")
      (fields
        (field (name "HQ_PART") "CA0177921")
        (field (name "MANUFACTURER") "DARFON")
        (field (name "MPN") "C0603NP0101JGT")
      )
      (libsource (lib "eagle-import") (part "100PF-50V0201"))
    )
    (comp (ref "C62")
      (value "10nF 50V")
      (footprint "eagle-import:0201")
      (fields (field (name "LCSC_PART") "C5142551"))
      (libsource (lib "eagle-import") (part "10NF-50V-0201"))
    )
    (comp (ref "C63")
      (value "100nF 50V")
      (footprint "eagle-import:0402")
      (fields (field (name "LCSC_PART") "C307331"))
      (libsource (lib "eagle-import") (part "100NF-50V-0402"))
    )
    (comp (ref "C64")
      (value "100nF 50V")
      (footprint "eagle-import:0402")
      (fields (field (name "LCSC_PART") "C307331"))
      (libsource (lib "eagle-import") (part "100NF-50V-0402"))
    )
    (comp (ref "C65")
      (value "10uF 50V")
      (footprint "eagle-import:0805")
      (fields (field (name "LCSC_PART") "C440198"))
      (libsource (lib "eagle-import") (part "10UF-50V-0805"))
    )
    (comp (ref "C66")
      (value "10uF 50V")
      (footprint "eagle-import:0805")
      (fields (field (name "LCSC_PART") "C440198"))
      (libsource (lib "eagle-import") (part "10UF-50V-0805"))
    )
    (comp (ref "C67")
      (value "1uF 50V")
      (footprint "eagle-import:0805")
      (fields
        (field (name "HQ_PART") "CA0182352")
        (field (name "LCSC_PART") "C28323")
        (field (name "MANUFACTURER") "TDK")
      )
      (libsource (lib "eagle-import") (part "1UF-50V0805"))
    )
    (comp (ref "C68")
      (value "100uF 50V")
      (footprint "eagle-import:6.3X7.7(DXL)")
      (fields
        (field (name "HQ_PART") "ZHLM0353527")
        (field (name "LCSC_PART") "C3151829")
        (field (name "MANUFACTURER") "ROQANG")
      )
      (libsource (lib "eagle-import") (part "100UF-50V6.3X7.7(DXL)"))
    )
    (comp (ref "C69")
      (value "1uF 50V")
      (footprint "eagle-import:0402")
      (fields (field (name "LCSC_PART") "C1518208"))
      (libsource (lib "eagle-import") (part "1UF-50V0402"))
    )
    (comp (ref "C70")
      (value "10uF 50V")
      (footprint "eagle-import:0805")
      (fields (field (name "LCSC_PART") "C440198"))
      (libsource (lib "eagle-import") (part "10UF-50V-0805"))
    )
    (comp (ref "C71")
      (value "10uF 50V")
      (footprint "eagle-import:0805")
      (fields (field (name "LCSC_PART") "C440198"))
      (libsource (lib "eagle-import") (part "10UF-50V-0805"))
    )
    (comp (ref "C72")
      (value "10uF 50V")
      (footprint "eagle-import:0805")
      (fields (field (name "LCSC_PART") "C440198"))
      (libsource (lib "eagle-import") (part "10UF-50V-0805"))
    )
    (comp (ref "C73")
      (value "100nF 25V")
      (footprint "eagle-import:0201")
      (fields
        (field (name "HQ_PART") "CA0183221")
        (field (name "LCSC_PART") "C76939")
        (field (name "MANUFACTURER") "Samsung")
      )
      (libsource (lib "eagle-import") (part "100NF-25V-0201"))
    )
    (comp (ref "C74")
      (value "100nF 25V")
      (footprint "eagle-import:0201")
      (fields
        (field (name "HQ_PART") "CA0183221")
        (field (name "LCSC_PART") "C76939")
        (field (name "MANUFACTURER") "Samsung")
      )
      (libsource (lib "eagle-import") (part "100NF-25V-0201"))
    )
    (comp (ref "C75")
      (value "1uF 50V")
      (footprint "eagle-import:0402")
      (fields (field (name "PACKAGE") "0402") (field (name "LCSC_PART") "C1518208"))
      (libsource (lib "eagle-import") (part "1UF-50V0402"))
    )
    (comp (ref "C76")
      (value "2.2nF 50V")
      (footprint "eagle-import:0402")
      (fields
        (field (name "PACKAGE") "0402")
        (field (name "HQ_PART") "CA0176616")
        (field (name "MANUFACTURER") "WALSIN")
        (field (name "MPN") "0402B222K500CT")
      )
      (libsource (lib "eagle-import") (part "2.2NF-50V-0402"))
    )
    (comp (ref "C77")
      (value "2.2nF 50V")
      (footprint "eagle-import:0402")
      (fields
        (field (name "PACKAGE") "0402")
        (field (name "HQ_PART") "CA0176616")
        (field (name "MANUFACTURER") "WALSIN")
        (field (name "MPN") "0402B222K500CT")
      )
      (libsource (lib "eagle-import") (part "2.2NF-50V-0402"))
    )
    (comp (ref "C78")
      (value "10uF 50V")
      (footprint "eagle-import:0805")
      (fields (field (name "LCSC_PART") "C440198"))
      (libsource (lib "eagle-import") (part "10UF-50V-0805"))
    )
    (comp (ref "C79")
      (value "330uF 50V")
      (footprint "eagle-import:10X10.5(DXL)")
      (fields (field (name "LCSC_PART") "C2895745") (field (name "MPN") "EEE-FT1H331AP"))
      (libsource (lib "eagle-import") (part "330UF-50V10X10.5(DXL)"))
    )
    (comp (ref "C80")
      (value "1nF 2kV")
      (footprint "eagle-import:1206")
      (fields
        (field (name "PACKAGE") "1206")
        (field (name "HQ_PART") "CA0134884")
        (field (name "LCSC_PART") "C173242")
        (field (name "MANUFACTURER") "Johanson Dielectrics ")
      )
      (libsource (lib "eagle-import") (part "1NF-2KV"))
    )
    (comp (ref "IC10")
      (value "TPS552882")
      (footprint "eagle-import:RPM0026A-MFG")
      (fields
        (field (name "MANUFACTURER_PART_NUMBER") "TPS552882QRPMRQ1")
        (field (name "COPYRIGHT") "Copyright (C) 2025 Ultra Librarian. All rights reserved.")
      )
      (libsource (lib "eagle-import") (part "TPS552882"))
    )
    (comp (ref "IC11")
      (value "INA219BIDCNT")
      (footprint "eagle-import:SOT23-8")
      (fields
        (field (name "HQ_PART") "IC0063216")
        (field (name "LCSC_PART") "C2653868")
        (field (name "MANUFACTURER") "Texas Instruments")
      )
      (libsource (lib "eagle-import") (part "INA219BIDCNT"))
    )
    (comp (ref "IC14")
      (value "STUSB4710AQ1TR")
      (footprint "eagle-import:QFN50P300X300X55-16N")
      (libsource (lib "eagle-import") (part "STUSB4710AQ1TR"))
    )
    (comp (ref "L3")
      (value "4.7uH 11.3A")
      (footprint "eagle-import:WE-PDHV_1280")
      (fields
        (field (name "LCSC_PART") "C2998768")
        (field (name "MANUFACTURER") "Sumida")
        (field (name "MPN") "CDRH127NP-4R7NC")
      )
      (libsource (lib "eagle-import") (part "4.7UH-PWR"))
    )
    (comp (ref "PORT2")
      (value "632722100213")
      (footprint "eagle-import:632722100213")
      (fields
        (field (name "LCSC_PART") "C2927029")
        (field (name "MANUFACTURER") "DEALON")
        (field (name "MPN") "USB-TYPE-C-009 ")
      )
      (libsource (lib "eagle-import") (part "USB-C-POWERONLY"))
    )
    (comp (ref "R56")
      (value "200K 1%")
      (footprint "eagle-import:0201")
      (fields (field (name "LCSC_PART") "C270357"))
      (libsource (lib "eagle-import") (part "200K-1%0201"))
    )
    (comp (ref "R66")
      (value "12.7K 1%")
      (footprint "eagle-import:0201")
      (fields
        (field (name "LCSC_PART") "C423755")
        (field (name "MANUFACTURER") "UNI-ROYAL")
        (field (name "MPN") "0201WMF1272TEE")
      )
      (libsource (lib "eagle-import") (part "12.7K-1%0201"))
    )
    (comp (ref "R67")
      (value "4.64K 1%")
      (footprint "eagle-import:0201")
      (fields
        (field (name "LCSC_PART") "C166186")
        (field (name "MANUFACTURER") " RALEC")
        (field (name "MPN") "RTT014641FTH")
      )
      (libsource (lib "eagle-import") (part "4.64K-1%-0201"))
    )
    (comp (ref "R68")
      (value "4.64K 1%")
      (footprint "eagle-import:0201")
      (fields
        (field (name "LCSC_PART") "C166186")
        (field (name "MANUFACTURER") " RALEC")
        (field (name "MPN") "RTT014641FTH")
      )
      (libsource (lib "eagle-import") (part "4.64K-1%-0201"))
    )
    (comp (ref "R69")
      (value "8.87K 1%")
      (footprint "eagle-import:0201")
      (fields
        (field (name "LCSC_PART") "C423413")
        (field (name "MANUFACTURER") " UNI-ROYAL")
        (field (name "MPN") "0201WMF8871TEE")
      )
      (libsource (lib "eagle-import") (part "8.87K-1%-0201"))
    )
    (comp (ref "R70")
      (value "30.9K 1%")
      (footprint "eagle-import:0201")
      (fields (field (name "LCSC_PART") "C364366"))
      (libsource (lib "eagle-import") (part "30.9K-1%0201"))
    )
    (comp (ref "R71")
      (value "100K 1%")
      (footprint "eagle-import:0201")
      (fields (field (name "LCSC_PART") "C270364"))
      (libsource (lib "eagle-import") (part "100K-1%0201"))
    )
    (comp (ref "R72")
      (value "10K 1%")
      (footprint "eagle-import:0402")
      (fields
        (field (name "HQ_PART") "RE0207399")
        (field (name "LCSC_PART") "C25744")
        (field (name "MANUFACTURER") "ROHM")
      )
      (libsource (lib "eagle-import") (part "10K-1%0402"))
    )
    (comp (ref "R73")
      (value "10K 1%")
      (footprint "eagle-import:0402")
      (fields
        (field (name "HQ_PART") "RE0207399")
        (field (name "LCSC_PART") "C25744")
        (field (name "MANUFACTURER") "ROHM")
      )
      (libsource (lib "eagle-import") (part "10K-1%0402"))
    )
    (comp (ref "R74")
      (value "10K 1%")
      (footprint "eagle-import:0201")
      (fields
        (field (name "HQ_PART") "RE0208620")
        (field (name "LCSC_PART") "C473048")
        (field (name "MANUFACTURER") "FH")
      )
      (libsource (lib "eagle-import") (part "10K-1%0201"))
    )
    (comp (ref "R75")
      (value "10K 1%")
      (footprint "eagle-import:0402")
      (fields
        (field (name "HQ_PART") "RE0207399")
        (field (name "LCSC_PART") "C25744")
        (field (name "MANUFACTURER") "ROHM")
      )
      (libsource (lib "eagle-import") (part "10K-1%0402"))
    )
    (comp (ref "R76")
      (value "0.010R 1%")
      (footprint "eagle-import:2512")
      (fields
        (field (name "LCSC_PART") "C127692")
        (field (name "MANUFACTURER") " UNI-ROYAL")
        (field (name "MPN") "25121WF100MT4E")
      )
      (libsource (lib "eagle-import") (part "0.010R-1%-2512"))
    )
    (comp (ref "R77")
      (value "0R 1%")
      (footprint "eagle-import:0201")
      (fields
        (field (name "HA_PART") "RE0015349")
        (field (name "LCSC_PART") "C106227")
        (field (name "MANUFACTURER") "Yageo")
      )
      (libsource (lib "eagle-import") (part "0R0201"))
    )
    (comp (ref "R78")
      (value "49.9K 1%")
      (footprint "eagle-import:0201")
      (fields
        (field (name "HQ_PART") "RE0461584")
        (field (name "LCSC_PART") "C138136")
        (field (name "MANUFACTURER") "Yageo")
      )
      (libsource (lib "eagle-import") (part "49.9K-1%0201"))
    )
    (comp (ref "R79")
      (value "20K 1%")
      (footprint "eagle-import:0201")
      (fields (field (name "LCSC_PART") "C473466"))
      (libsource (lib "eagle-import") (part "20K-1%0201"))
    )
    (comp (ref "R80")
      (value "150K")
      (footprint "eagle-import:R0201")
      (libsource (lib "eagle-import") (part "R0201"))
    )
    (comp (ref "R81")
      (value "15K 1%")
      (footprint "eagle-import:0201")
      (fields (field (name "LCSC_PART") "C295774"))
      (libsource (lib "eagle-import") (part "15K-1%0201"))
    )
    (comp (ref "R82")
      (value "0.010R 1%")
      (footprint "eagle-import:2512")
      (fields
        (field (name "LCSC_PART") "C127692")
        (field (name "MANUFACTURER") " UNI-ROYAL")
        (field (name "MPN") "25121WF100MT4E")
      )
      (libsource (lib "eagle-import") (part "0.010R-1%-2512"))
    )
    (comp (ref "R83")
      (value "1R 1%")
      (footprint "eagle-import:0402")
      (fields
        (field (name "HQ_PART") "RE0322446")
        (field (name "MANUFACTURER") "RALEC")
        (field (name "MPN") "RTT021R00FTH")
      )
      (libsource (lib "eagle-import") (part "1R-1%0402"))
    )
    (comp (ref "R85")
      (value "1R 1%")
      (footprint "eagle-import:0402")
      (fields
        (field (name "HQ_PART") "RE0322446")
        (field (name "MANUFACTURER") "RALEC")
        (field (name "MPN") "RTT021R00FTH")
      )
      (libsource (lib "eagle-import") (part "1R-1%0402"))
    )
    (comp (ref "R86")
      (value "0R 1%")
      (footprint "eagle-import:0201")
      (fields
        (field (name "PACKAGE") "0201")
        (field (name "HA_PART") "RE0015349")
        (field (name "LCSC_PART") "C106227")
        (field (name "MANUFACTURER") "Yageo")
      )
      (libsource (lib "eagle-import") (part "0R0201"))
    )
    (comp (ref "R87")
      (value "0R 1%")
      (footprint "eagle-import:0201")
      (fields
        (field (name "PACKAGE") "0201")
        (field (name "HA_PART") "RE0015349")
        (field (name "LCSC_PART") "C106227")
        (field (name "MANUFACTURER") "Yageo")
      )
      (libsource (lib "eagle-import") (part "0R0201"))
    )
    (comp (ref "R88")
      (value "10K 1%")
      (footprint "eagle-import:0201")
      (fields
        (field (name "HQ_PART") "RE0208620")
        (field (name "LCSC_PART") "C473048")
        (field (name "MANUFACTURER") "FH")
      )
      (libsource (lib "eagle-import") (part "10K-1%0201"))
    )
    (comp (ref "R89")
      (value "1R 1%")
      (footprint "eagle-import:0603")
      (fields
        (field (name "PACKAGE") "0603")
        (field (name "HQ_PART") "RE0421839")
        (field (name "MANUFACTURER") "RALEC")
        (field (name "MPN") "RTT031R00FTP")
      )
      (libsource (lib "eagle-import") (part "1R-1%0603"))
    )
    (comp (ref "R90")
      (value "1R 1%")
      (footprint "eagle-import:0603")
      (fields
        (field (name "PACKAGE") "0603")
        (field (name "HQ_PART") "RE0421839")
        (field (name "MANUFACTURER") "RALEC")
        (field (name "MPN") "RTT031R00FTP")
      )
      (libsource (lib "eagle-import") (part "1R-1%0603"))
    )
    (comp (ref "R91")
      (value "1M 1%")
      (footprint "eagle-import:1206")
      (fields
        (field (name "PACKAGE") "1206")
        (field (name "HQ_PART") "RE0188103")
        (field (name "LCSC_PART") "C17927")
        (field (name "MANUFACTURER") "Uniohm")
      )
      (libsource (lib "eagle-import") (part "1M-1%1206"))
    )
    (comp (ref "T1")
      (value "DMP3013SFV")
      (footprint "eagle-import:POWERDI3333-8_UX_DIO-L")
      (fields (field (name "MANUFACTURER_PART_NUMBER") "DMP3013SFV-7"))
      (libsource (lib "eagle-import") (part "DMP3013SFV-7UX"))
    )
    (comp (ref "T2")
      (value "DMP3013SFV")
      (footprint "eagle-import:POWERDI3333-8_UX_DIO-L")
      (fields (field (name "MANUFACTURER_PART_NUMBER") "DMP3013SFV-7"))
      (libsource (lib "eagle-import") (part "DMP3013SFV-7UX"))
    )
    (comp (ref "T3")
      (value "DMP3013SFV")
      (footprint "eagle-import:POWERDI3333-8_UX_DIO-L")
      (fields (field (name "MANUFACTURER_PART_NUMBER") "DMP3013SFV-7"))
      (libsource (lib "eagle-import") (part "DMP3013SFV-7UX"))
    )
    (comp (ref "T4")
      (value "BSZ065N06")
      (footprint "eagle-import:POWERDI3333-8_UX_DIO-L")
      (fields
        (field (name "MANUFACTURER_PART_NUMBER") "IPZ40N04S5L7R4ATMA1")
        (field (name "COPYRIGHT") "Copyright (C) 2025 Ultra Librarian. All rights reserved.")
      )
      (libsource (lib "eagle-import") (part "IPZ40N04S5L7R4ATMA1"))
    )
    (comp (ref "T5")
      (value "BSZ065N06")
      (footprint "eagle-import:POWERDI3333-8_UX_DIO-L")
      (fields
        (field (name "MANUFACTURER_PART_NUMBER") "IPZ40N04S5L7R4ATMA1")
        (field (name "COPYRIGHT") "Copyright (C) 2025 Ultra Librarian. All rights reserved.")
      )
      (libsource (lib "eagle-import") (part "IPZ40N04S5L7R4ATMA1"))
    )
    (comp (ref "C110")
      (value "1uF 10V")
      (footprint "eagle-import:0201")
      (fields (field (name "LCSC_PART") "C76935"))
      (libsource (lib "eagle-import") (part "1UF-10V0201"))
    )
    (comp (ref "C111")
      (value "1uF 10V")
      (footprint "eagle-import:0201")
      (fields (field (name "LCSC_PART") "C76935"))
      (libsource (lib "eagle-import") (part "1UF-10V0201"))
    )
    (comp (ref "C112")
      (value "1uF 50V")
      (footprint "eagle-import:0603")
      (fields (field (name "LCSC_PART") "C15849"))
      (libsource (lib "eagle-import") (part "1UF-50V0603"))
    )
    (comp (ref "C113")
      (value "4.7uF 25V")
      (footprint "eagle-import:0402")
      (fields
        (field (name "HQ_PART") "ZHLM0023346")
        (field (name "LCSC_PART") "C22367824")
        (field (name "MANUFACTURER") "Murata")
      )
      (libsource (lib "eagle-import") (part "4.7UF-25V0402"))
    )
    (comp (ref "C114")
      (value "10nF 50V")
      (footprint "eagle-import:0201")
      (fields (field (name "LCSC_PART") "C5142551"))
      (libsource (lib "eagle-import") (part "10NF-50V-0201"))
    )
    (comp (ref "C115")
      (value "100pF 50V")
      (footprint "eagle-import:0201")
      (fields
        (field (name "HQ_PART") "CA0177921")
        (field (name "MANUFACTURER") "DARFON")
        (field (name "MPN") "C0603NP0101JGT")
      )
      (libsource (lib "eagle-import") (part "100PF-50V0201"))
    )
    (comp (ref "C116")
      (value "10nF 50V")
      (footprint "eagle-import:0201")
      (fields (field (name "LCSC_PART") "C5142551"))
      (libsource (lib "eagle-import") (part "10NF-50V-0201"))
    )
    (comp (ref "C117")
      (value "100nF 50V")
      (footprint "eagle-import:0402")
      (fields (field (name "LCSC_PART") "C307331"))
      (libsource (lib "eagle-import") (part "100NF-50V-0402"))
    )
    (comp (ref "C118")
      (value "100nF 50V")
      (footprint "eagle-import:0402")
      (fields (field (name "LCSC_PART") "C307331"))
      (libsource (lib "eagle-import") (part "100NF-50V-0402"))
    )
    (comp (ref "C119")
      (value "10uF 50V")
      (footprint "eagle-import:0805")
      (fields (field (name "LCSC_PART") "C440198"))
      (libsource (lib "eagle-import") (part "10UF-50V-0805"))
    )
    (comp (ref "C120")
      (value "10uF 50V")
      (footprint "eagle-import:0805")
      (fields (field (name "LCSC_PART") "C440198"))
      (libsource (lib "eagle-import") (part "10UF-50V-0805"))
    )
    (comp (ref "C121")
      (value "1uF 50V")
      (footprint "eagle-import:0805")
      (fields
        (field (name "HQ_PART") "CA0182352")
        (field (name "LCSC_PART") "C28323")
        (field (name "MANUFACTURER") "TDK")
      )
      (libsource (lib "eagle-import") (part "1UF-50V0805"))
    )
    (comp (ref "C122")
      (value "100uF 50V")
      (footprint "eagle-import:6.3X7.7(DXL)")
      (fields
        (field (name "HQ_PART") "ZHLM0353527")
        (field (name "LCSC_PART") "C3151829")
        (field (name "MANUFACTURER") "ROQANG")
      )
      (libsource (lib "eagle-import") (part "100UF-50V6.3X7.7(DXL)"))
    )
    (comp (ref "C123")
      (value "1uF 50V")
      (footprint "eagle-import:0402")
      (fields (field (name "LCSC_PART") "C1518208"))
      (libsource (lib "eagle-import") (part "1UF-50V0402"))
    )
    (comp (ref "C124")
      (value "10uF 50V")
      (footprint "eagle-import:0805")
      (fields (field (name "LCSC_PART") "C440198"))
      (libsource (lib "eagle-import") (part "10UF-50V-0805"))
    )
    (comp (ref "C125")
      (value "10uF 50V")
      (footprint "eagle-import:0805")
      (fields (field (name "LCSC_PART") "C440198"))
      (libsource (lib "eagle-import") (part "10UF-50V-0805"))
    )
    (comp (ref "C126")
      (value "10uF 50V")
      (footprint "eagle-import:0805")
      (fields (field (name "LCSC_PART") "C440198"))
      (libsource (lib "eagle-import") (part "10UF-50V-0805"))
    )
    (comp (ref "C127")
      (value "100nF 25V")
      (footprint "eagle-import:0201")
      (fields
        (field (name "HQ_PART") "CA0183221")
        (field (name "LCSC_PART") "C76939")
        (field (name "MANUFACTURER") "Samsung")
      )
      (libsource (lib "eagle-import") (part "100NF-25V-0201"))
    )
    (comp (ref "C128")
      (value "100nF 25V")
      (footprint "eagle-import:0201")
      (fields
        (field (name "HQ_PART") "CA0183221")
        (field (name "LCSC_PART") "C76939")
        (field (name "MANUFACTURER") "Samsung")
      )
      (libsource (lib "eagle-import") (part "100NF-25V-0201"))
    )
    (comp (ref "C129")
      (value "1uF 50V")
      (footprint "eagle-import:0402")
      (fields (field (name "PACKAGE") "0402") (field (name "LCSC_PART") "C1518208"))
      (libsource (lib "eagle-import") (part "1UF-50V0402"))
    )
    (comp (ref "C130")
      (value "2.2nF 50V")
      (footprint "eagle-import:0402")
      (fields
        (field (name "PACKAGE") "0402")
        (field (name "HQ_PART") "CA0176616")
        (field (name "MANUFACTURER") "WALSIN")
        (field (name "MPN") "0402B222K500CT")
      )
      (libsource (lib "eagle-import") (part "2.2NF-50V-0402"))
    )
    (comp (ref "C131")
      (value "2.2nF 50V")
      (footprint "eagle-import:0402")
      (fields
        (field (name "PACKAGE") "0402")
        (field (name "HQ_PART") "CA0176616")
        (field (name "MANUFACTURER") "WALSIN")
        (field (name "MPN") "0402B222K500CT")
      )
      (libsource (lib "eagle-import") (part "2.2NF-50V-0402"))
    )
    (comp (ref "C132")
      (value "10uF 50V")
      (footprint "eagle-import:0805")
      (fields (field (name "LCSC_PART") "C440198"))
      (libsource (lib "eagle-import") (part "10UF-50V-0805"))
    )
    (comp (ref "C133")
      (value "330uF 50V")
      (footprint "eagle-import:10X10.5(DXL)")
      (fields (field (name "LCSC_PART") "C2895745") (field (name "MPN") "EEE-FT1H331AP"))
      (libsource (lib "eagle-import") (part "330UF-50V10X10.5(DXL)"))
    )
    (comp (ref "C134")
      (value "1nF 2kV")
      (footprint "eagle-import:1206")
      (fields
        (field (name "PACKAGE") "1206")
        (field (name "HQ_PART") "CA0134884")
        (field (name "LCSC_PART") "C173242")
        (field (name "MANUFACTURER") "Johanson Dielectrics ")
      )
      (libsource (lib "eagle-import") (part "1NF-2KV"))
    )
    (comp (ref "IC18")
      (value "TPS552882")
      (footprint "eagle-import:RPM0026A-MFG")
      (fields
        (field (name "MANUFACTURER_PART_NUMBER") "TPS552882QRPMRQ1")
        (field (name "COPYRIGHT") "Copyright (C) 2025 Ultra Librarian. All rights reserved.")
      )
      (libsource (lib "eagle-import") (part "TPS552882"))
    )
    (comp (ref "IC19")
      (value "INA219BIDCNT")
      (footprint "eagle-import:SOT23-8")
      (fields
        (field (name "HQ_PART") "IC0063216")
        (field (name "LCSC_PART") "C2653868")
        (field (name "MANUFACTURER") "Texas Instruments")
      )
      (libsource (lib "eagle-import") (part "INA219BIDCNT"))
    )
    (comp (ref "IC20")
      (value "STUSB4710AQ1TR")
      (footprint "eagle-import:QFN50P300X300X55-16N")
      (libsource (lib "eagle-import") (part "STUSB4710AQ1TR"))
    )
    (comp (ref "L5")
      (value "4.7uH 11.3A")
      (footprint "eagle-import:WE-PDHV_1280")
      (fields
        (field (name "LCSC_PART") "C2998768")
        (field (name "MANUFACTURER") "Sumida")
        (field (name "MPN") "CDRH127NP-4R7NC")
      )
      (libsource (lib "eagle-import") (part "4.7UH-PWR"))
    )
    (comp (ref "PORT4")
      (value "632722100213")
      (footprint "eagle-import:632722100213")
      (fields
        (field (name "LCSC_PART") "C2927029")
        (field (name "MANUFACTURER") "DEALON")
        (field (name "MPN") "USB-TYPE-C-009 ")
      )
      (libsource (lib "eagle-import") (part "USB-C-POWERONLY"))
    )
    (comp (ref "R118")
      (value "200K 1%")
      (footprint "eagle-import:0201")
      (fields (field (name "LCSC_PART") "C270357"))
      (libsource (lib "eagle-import") (part "200K-1%0201"))
    )
    (comp (ref "R119")
      (value "12.7K 1%")
      (footprint "eagle-import:0201")
      (fields
        (field (name "LCSC_PART") "C423755")
        (field (name "MANUFACTURER") "UNI-ROYAL")
        (field (name "MPN") "0201WMF1272TEE")
      )
      (libsource (lib "eagle-import") (part "12.7K-1%0201"))
    )
    (comp (ref "R120")
      (value "4.64K 1%")
      (footprint "eagle-import:0201")
      (fields
        (field (name "LCSC_PART") "C166186")
        (field (name "MANUFACTURER") " RALEC")
        (field (name "MPN") "RTT014641FTH")
      )
      (libsource (lib "eagle-import") (part "4.64K-1%-0201"))
    )
    (comp (ref "R121")
      (value "4.64K 1%")
      (footprint "eagle-import:0201")
      (fields
        (field (name "LCSC_PART") "C166186")
        (field (name "MANUFACTURER") " RALEC")
        (field (name "MPN") "RTT014641FTH")
      )
      (libsource (lib "eagle-import") (part "4.64K-1%-0201"))
    )
    (comp (ref "R122")
      (value "8.87K 1%")
      (footprint "eagle-import:0201")
      (fields
        (field (name "LCSC_PART") "C423413")
        (field (name "MANUFACTURER") " UNI-ROYAL")
        (field (name "MPN") "0201WMF8871TEE")
      )
      (libsource (lib "eagle-import") (part "8.87K-1%-0201"))
    )
    (comp (ref "R123")
      (value "30.9K 1%")
      (footprint "eagle-import:0201")
      (fields (field (name "LCSC_PART") "C364366"))
      (libsource (lib "eagle-import") (part "30.9K-1%0201"))
    )
    (comp (ref "R124")
      (value "100K 1%")
      (footprint "eagle-import:0201")
      (fields (field (name "LCSC_PART") "C270364"))
      (libsource (lib "eagle-import") (part "100K-1%0201"))
    )
    (comp (ref "R125")
      (value "10K 1%")
      (footprint "eagle-import:0402")
      (fields
        (field (name "HQ_PART") "RE0207399")
        (field (name "LCSC_PART") "C25744")
        (field (name "MANUFACTURER") "ROHM")
      )
      (libsource (lib "eagle-import") (part "10K-1%0402"))
    )
    (comp (ref "R126")
      (value "10K 1%")
      (footprint "eagle-import:0402")
      (fields
        (field (name "HQ_PART") "RE0207399")
        (field (name "LCSC_PART") "C25744")
        (field (name "MANUFACTURER") "ROHM")
      )
      (libsource (lib "eagle-import") (part "10K-1%0402"))
    )
    (comp (ref "R127")
      (value "10K 1%")
      (footprint "eagle-import:0201")
      (fields
        (field (name "HQ_PART") "RE0208620")
        (field (name "LCSC_PART") "C473048")
        (field (name "MANUFACTURER") "FH")
      )
      (libsource (lib "eagle-import") (part "10K-1%0201"))
    )
    (comp (ref "R128")
      (value "10K 1%")
      (footprint "eagle-import:0402")
      (fields
        (field (name "HQ_PART") "RE0207399")
        (field (name "LCSC_PART") "C25744")
        (field (name "MANUFACTURER") "ROHM")
      )
      (libsource (lib "eagle-import") (part "10K-1%0402"))
    )
    (comp (ref "R129")
      (value "0.010R 1%")
      (footprint "eagle-import:2512")
      (fields
        (field (name "LCSC_PART") "C127692")
        (field (name "MANUFACTURER") " UNI-ROYAL")
        (field (name "MPN") "25121WF100MT4E")
      )
      (libsource (lib "eagle-import") (part "0.010R-1%-2512"))
    )
    (comp (ref "R130")
      (value "0R 1%")
      (footprint "eagle-import:0201")
      (fields
        (field (name "HA_PART") "RE0015349")
        (field (name "LCSC_PART") "C106227")
        (field (name "MANUFACTURER") "Yageo")
      )
      (libsource (lib "eagle-import") (part "0R0201"))
    )
    (comp (ref "R131")
      (value "49.9K 1%")
      (footprint "eagle-import:0201")
      (fields
        (field (name "HQ_PART") "RE0461584")
        (field (name "LCSC_PART") "C138136")
        (field (name "MANUFACTURER") "Yageo")
      )
      (libsource (lib "eagle-import") (part "49.9K-1%0201"))
    )
    (comp (ref "R132")
      (value "20K 1%")
      (footprint "eagle-import:0201")
      (fields (field (name "LCSC_PART") "C473466"))
      (libsource (lib "eagle-import") (part "20K-1%0201"))
    )
    (comp (ref "R133")
      (value "150K")
      (footprint "eagle-import:R0201")
      (libsource (lib "eagle-import") (part "R0201"))
    )
    (comp (ref "R134")
      (value "15K 1%")
      (footprint "eagle-import:0201")
      (fields (field (name "LCSC_PART") "C295774"))
      (libsource (lib "eagle-import") (part "15K-1%0201"))
    )
    (comp (ref "R135")
      (value "0.010R 1%")
      (footprint "eagle-import:2512")
      (fields
        (field (name "LCSC_PART") "C127692")
        (field (name "MANUFACTURER") " UNI-ROYAL")
        (field (name "MPN") "25121WF100MT4E")
      )
      (libsource (lib "eagle-import") (part "0.010R-1%-2512"))
    )
    (comp (ref "R136")
      (value "1R 1%")
      (footprint "eagle-import:0402")
      (fields
        (field (name "HQ_PART") "RE0322446")
        (field (name "MANUFACTURER") "RALEC")
        (field (name "MPN") "RTT021R00FTH")
      )
      (libsource (lib "eagle-import") (part "1R-1%0402"))
    )
    (comp (ref "R137")
      (value "1R 1%")
      (footprint "eagle-import:0402")
      (fields
        (field (name "HQ_PART") "RE0322446")
        (field (name "MANUFACTURER") "RALEC")
        (field (name "MPN") "RTT021R00FTH")
      )
      (libsource (lib "eagle-import") (part "1R-1%0402"))
    )
    (comp (ref "R138")
      (value "0R 1%")
      (footprint "eagle-import:0201")
      (fields
        (field (name "PACKAGE") "0201")
        (field (name "HA_PART") "RE0015349")
        (field (name "LCSC_PART") "C106227")
        (field (name "MANUFACTURER") "Yageo")
      )
      (libsource (lib "eagle-import") (part "0R0201"))
    )
    (comp (ref "R139")
      (value "0R 1%")
      (footprint "eagle-import:0201")
      (fields
        (field (name "PACKAGE") "0201")
        (field (name "HA_PART") "RE0015349")
        (field (name "LCSC_PART") "C106227")
        (field (name "MANUFACTURER") "Yageo")
      )
      (libsource (lib "eagle-import") (part "0R0201"))
    )
    (comp (ref "R140")
      (value "10K 1%")
      (footprint "eagle-import:0201")
      (fields
        (field (name "HQ_PART") "RE0208620")
        (field (name "LCSC_PART") "C473048")
        (field (name "MANUFACTURER") "FH")
      )
      (libsource (lib "eagle-import") (part "10K-1%0201"))
    )
    (comp (ref "R141")
      (value "1R 1%")
      (footprint "eagle-import:0603")
      (fields
        (field (name "PACKAGE") "0603")
        (field (name "HQ_PART") "RE0421839")
        (field (name "MANUFACTURER") "RALEC")
        (field (name "MPN") "RTT031R00FTP")
      )
      (libsource (lib "eagle-import") (part "1R-1%0603"))
    )
    (comp (ref "R142")
      (value "1R 1%")
      (footprint "eagle-import:0603")
      (fields
        (field (name "PACKAGE") "0603")
        (field (name "HQ_PART") "RE0421839")
        (field (name "MANUFACTURER") "RALEC")
        (field (name "MPN") "RTT031R00FTP")
      )
      (libsource (lib "eagle-import") (part "1R-1%0603"))
    )
    (comp (ref "R143")
      (value "1M 1%")
      (footprint "eagle-import:1206")
      (fields
        (field (name "PACKAGE") "1206")
        (field (name "HQ_PART") "RE0188103")
        (field (name "LCSC_PART") "C17927")
        (field (name "MANUFACTURER") "Uniohm")
      )
      (libsource (lib "eagle-import") (part "1M-1%1206"))
    )
    (comp (ref "T16")
      (value "DMP3013SFV")
      (footprint "eagle-import:POWERDI3333-8_UX_DIO-L")
      (fields (field (name "MANUFACTURER_PART_NUMBER") "DMP3013SFV-7"))
      (libsource (lib "eagle-import") (part "DMP3013SFV-7UX"))
    )
    (comp (ref "T17")
      (value "DMP3013SFV")
      (footprint "eagle-import:POWERDI3333-8_UX_DIO-L")
      (fields (field (name "MANUFACTURER_PART_NUMBER") "DMP3013SFV-7"))
      (libsource (lib "eagle-import") (part "DMP3013SFV-7UX"))
    )
    (comp (ref "T18")
      (value "DMP3013SFV")
      (footprint "eagle-import:POWERDI3333-8_UX_DIO-L")
      (fields (field (name "MANUFACTURER_PART_NUMBER") "DMP3013SFV-7"))
      (libsource (lib "eagle-import") (part "DMP3013SFV-7UX"))
    )
    (comp (ref "T19")
      (value "BSZ065N06")
      (footprint "eagle-import:POWERDI3333-8_UX_DIO-L")
      (fields
        (field (name "MANUFACTURER_PART_NUMBER") "IPZ40N04S5L7R4ATMA1")
        (field (name "COPYRIGHT") "Copyright (C) 2025 Ultra Librarian. All rights reserved.")
      )
      (libsource (lib "eagle-import") (part "IPZ40N04S5L7R4ATMA1"))
    )
    (comp (ref "T20")
      (value "BSZ065N06")
      (footprint "eagle-import:POWERDI3333-8_UX_DIO-L")
      (fields
        (field (name "MANUFACTURER_PART_NUMBER") "IPZ40N04S5L7R4ATMA1")
        (field (name "COPYRIGHT") "Copyright (C) 2025 Ultra Librarian. All rights reserved.")
      )
      (libsource (lib "eagle-import") (part "IPZ40N04S5L7R4ATMA1"))
    )
    (comp (ref "C28")
      (value "1nF 2kV")
      (footprint "eagle-import:1206")
      (fields
        (field (name "HQ_PART") "CA0134884")
        (field (name "LCSC_PART") "C173242")
        (field (name "MANUFACTURER") "Johanson Dielectrics ")
      )
      (libsource (lib "eagle-import") (part "1NF-2KV"))
    )
    (comp (ref "C29")
      (value "100nF 25V")
      (footprint "eagle-import:0402")
      (fields
        (field (name "HQ_PART") "CA0176807")
        (field (name "LCSC_PART") "C56392")
        (field (name "MANUFACTURER") "Walsin")
      )
      (libsource (lib "eagle-import") (part "100NF-25V-0402"))
    )
    (comp (ref "C212")
      (value "100nF 25V")
      (footprint "eagle-import:0201")
      (fields
        (field (name "HQ_PART") "CA0183221")
        (field (name "LCSC_PART") "C76939")
        (field (name "MANUFACTURER") "Samsung")
      )
      (libsource (lib "eagle-import") (part "100NF-25V-0201"))
    )
    (comp (ref "C213")
      (value "1uF 10V")
      (footprint "eagle-import:0201")
      (fields (field (name "LCSC_PART") "C76935"))
      (libsource (lib "eagle-import") (part "1UF-10V0201"))
    )
    (comp (ref "C247")
      (value "10uF 16V")
      (footprint "eagle-import:0603")
      (fields
        (field (name "HQ_PART") "CA0149236")
        (field (name "LCSC_PART") "C92487")
        (field (name "MANUFACTURER") "Murata")
      )
      (libsource (lib "eagle-import") (part "10UF-16V-0603"))
    )
    (comp (ref "C248")
      (value "100nF 25V")
      (footprint "eagle-import:0402")
      (fields
        (field (name "HQ_PART") "CA0176807")
        (field (name "LCSC_PART") "C56392")
        (field (name "MANUFACTURER") "Walsin")
      )
      (libsource (lib "eagle-import") (part "100NF-25V-0402"))
    )
    (comp (ref "C249")
      (value "100nF 25V")
      (footprint "eagle-import:0201")
      (fields
        (field (name "HQ_PART") "CA0183221")
        (field (name "LCSC_PART") "C76939")
        (field (name "MANUFACTURER") "Samsung")
      )
      (libsource (lib "eagle-import") (part "100NF-25V-0201"))
    )
    (comp (ref "C251")
      (value "1uF 10V")
      (footprint "eagle-import:0201")
      (fields (field (name "LCSC_PART") "C76935"))
      (libsource (lib "eagle-import") (part "1UF-10V0201"))
    )
    (comp (ref "D13")
      (value "HDMIULC6-4SC6Y")
      (footprint "eagle-import:SOT23-6")
      (libsource (lib "eagle-import") (part "HDMIULC6-4SC6Y"))
    )
    (comp (ref "DISP")
      (value "AFC11-S20ICC-00")
      (footprint "eagle-import:FPC20")
      (fields
        (field (name "HQ_PART") "CO0889517")
        (field (name "LCSC_PART") "C466537")
        (field (name "MANUFACTURER") "JS")
      )
      (libsource (lib "eagle-import") (part "AFC11-S20ICC-00"))
    )
    (comp (ref "ESD1")
      (value "SP0503BAHTG")
      (footprint "eagle-import:SOT143")
      (fields
        (field (name "HQ_PART") "CP0003989")
        (field (name "LCSC_PART") "C3040626")
        (field (name "MANUFACTURER") "Littelfuse")
      )
      (libsource (lib "eagle-import") (part "SP0503BAHT"))
    )
    (comp (ref "IC38")
      (value "TCA9548ARGER")
      (footprint "eagle-import:QFN50P400X400X100-25T210N")
      (libsource (lib "eagle-import") (part "TCA9548ARGER"))
    )
    (comp (ref "IC42")
      (value "MCP23017T-E/ML")
      (footprint "eagle-import:QFN28[6X6]ML")
      (fields
        (field (name "HQ_PART") "IC0080215")
        (field (name "LCSC_PART") "C629439")
        (field (name "MANUFACTURER") "MICROCHIP")
      )
      (libsource (lib "eagle-import") (part "MCP23017-E/ML"))
    )
    (comp (ref "R30")
      (value "0R 1%")
      (footprint "eagle-import:0805")
      (fields
        (field (name "PACKAGE") "0805")
        (field (name "HQ_PART") "RE0013023")
        (field (name "LCSC_PART") "C17477")
        (field (name "MANUFACTURER") "Vishay")
      )
      (libsource (lib "eagle-import") (part "0R0805"))
    )
    (comp (ref "R31")
      (value "10K 1%")
      (footprint "eagle-import:0402")
      (fields
        (field (name "PACKAGE") "0402")
        (field (name "HQ_PART") "RE0207399")
        (field (name "LCSC_PART") "C25744")
        (field (name "MANUFACTURER") "ROHM")
      )
      (libsource (lib "eagle-import") (part "10K-1%0402"))
    )
    (comp (ref "R32")
      (value "10K 1%")
      (footprint "eagle-import:0402")
      (fields
        (field (name "PACKAGE") "0402")
        (field (name "HQ_PART") "RE0207399")
        (field (name "LCSC_PART") "C25744")
        (field (name "MANUFACTURER") "ROHM")
      )
      (libsource (lib "eagle-import") (part "10K-1%0402"))
    )
    (comp (ref "R215")
      (value "3.3K 1%")
      (footprint "eagle-import:_0603X4-1206")
      (fields
        (field (name "HQ_PART") "RE0093863")
        (field (name "LCSC_PART") "C1734380")
        (field (name "MANUFACTURER") "Yageo")
      )
      (libsource (lib "eagle-import") (part "3.3K-1%_ARRAY0603X4-1206"))
    )
    (comp (ref "R216")
      (value "3.3K 1%")
      (footprint "eagle-import:_0603X4-1206")
      (fields
        (field (name "HQ_PART") "RE0093863")
        (field (name "LCSC_PART") "C1734380")
        (field (name "MANUFACTURER") "Yageo")
      )
      (libsource (lib "eagle-import") (part "3.3K-1%_ARRAY0603X4-1206"))
    )
    (comp (ref "R217")
      (value "3.3K 1%")
      (footprint "eagle-import:_0603X4-1206")
      (fields
        (field (name "HQ_PART") "RE0093863")
        (field (name "LCSC_PART") "C1734380")
        (field (name "MANUFACTURER") "Yageo")
      )
      (libsource (lib "eagle-import") (part "3.3K-1%_ARRAY0603X4-1206"))
    )
    (comp (ref "R249")
      (value "2.2K 1%")
      (footprint "eagle-import:0201")
      (fields
        (field (name "HQ_PART") "RE0209901")
        (field (name "LCSC_PART") "C473508")
        (field (name "MANUFACTURER") "FH")
      )
      (libsource (lib "eagle-import") (part "2.2K-1%0201"))
    )
    (comp (ref "R250")
      (value "5.1K 1%")
      (footprint "eagle-import:0201")
      (fields
        (field (name "HQ_PART") "RE0185972")
        (field (name "LCSC_PART") "C274341")
        (field (name "MANUFACTURER") "Yageo")
      )
      (libsource (lib "eagle-import") (part "5.1K-1%0201"))
    )
    (comp (ref "R251")
      (value "5.1K 1%")
      (footprint "eagle-import:0201")
      (fields
        (field (name "HQ_PART") "RE0185972")
        (field (name "LCSC_PART") "C274341")
        (field (name "MANUFACTURER") "Yageo")
      )
      (libsource (lib "eagle-import") (part "5.1K-1%0201"))
    )
    (comp (ref "R252")
      (value "10K 1%")
      (footprint "eagle-import:0201")
      (fields
        (field (name "HQ_PART") "RE0208620")
        (field (name "LCSC_PART") "C473048")
        (field (name "MANUFACTURER") "FH")
      )
      (libsource (lib "eagle-import") (part "10K-1%0201"))
    )
    (comp (ref "R255")
      (value "1M 1%")
      (footprint "eagle-import:1206")
      (fields
        (field (name "HQ_PART") "RE0188103")
        (field (name "LCSC_PART") "C17927")
        (field (name "MANUFACTURER") "Uniohm")
      )
      (libsource (lib "eagle-import") (part "1M-1%1206"))
    )
    (comp (ref "USB9")
      (value "USB-TYPE-C-018")
      (footprint "eagle-import:USB-C")
      (fields
        (field (name "HQ_PART") "ZHLM0322915")
        (field (name "LCSC_PART") "C2927038")
        (field (name "MANUFACTURER") "DEALON")
      )
      (libsource (lib "eagle-import") (part "USB_C-THT"))
    )
    (comp (ref "C206")
      (value "1uF 10V")
      (footprint "eagle-import:0201")
      (fields (field (name "LCSC_PART") "C76935"))
      (libsource (lib "eagle-import") (part "1UF-10V0201"))
    )
    (comp (ref "C207")
      (value "1uF 10V")
      (footprint "eagle-import:0201")
      (fields (field (name "LCSC_PART") "C76935"))
      (libsource (lib "eagle-import") (part "1UF-10V0201"))
    )
    (comp (ref "C208")
      (value "1uF 50V")
      (footprint "eagle-import:0603")
      (fields (field (name "LCSC_PART") "C15849"))
      (libsource (lib "eagle-import") (part "1UF-50V0603"))
    )
    (comp (ref "C209")
      (value "4.7uF 25V")
      (footprint "eagle-import:0402")
      (fields
        (field (name "HQ_PART") "ZHLM0023346")
        (field (name "LCSC_PART") "C22367824")
        (field (name "MANUFACTURER") "Murata")
      )
      (libsource (lib "eagle-import") (part "4.7UF-25V0402"))
    )
    (comp (ref "C210")
      (value "10nF 50V")
      (footprint "eagle-import:0201")
      (fields (field (name "LCSC_PART") "C5142551"))
      (libsource (lib "eagle-import") (part "10NF-50V-0201"))
    )
    (comp (ref "C211")
      (value "100pF 50V")
      (footprint "eagle-import:0201")
      (fields
        (field (name "HQ_PART") "CA0177921")
        (field (name "MANUFACTURER") "DARFON")
        (field (name "MPN") "C0603NP0101JGT")
      )
      (libsource (lib "eagle-import") (part "100PF-50V0201"))
    )
    (comp (ref "C219")
      (value "10nF 50V")
      (footprint "eagle-import:0201")
      (fields (field (name "LCSC_PART") "C5142551"))
      (libsource (lib "eagle-import") (part "10NF-50V-0201"))
    )
    (comp (ref "C220")
      (value "100nF 50V")
      (footprint "eagle-import:0402")
      (fields (field (name "LCSC_PART") "C307331"))
      (libsource (lib "eagle-import") (part "100NF-50V-0402"))
    )
    (comp (ref "C230")
      (value "100nF 50V")
      (footprint "eagle-import:0402")
      (fields (field (name "LCSC_PART") "C307331"))
      (libsource (lib "eagle-import") (part "100NF-50V-0402"))
    )
    (comp (ref "C231")
      (value "10uF 50V")
      (footprint "eagle-import:0805")
      (fields (field (name "LCSC_PART") "C440198"))
      (libsource (lib "eagle-import") (part "10UF-50V-0805"))
    )
    (comp (ref "C232")
      (value "10uF 50V")
      (footprint "eagle-import:0805")
      (fields (field (name "LCSC_PART") "C440198"))
      (libsource (lib "eagle-import") (part "10UF-50V-0805"))
    )
    (comp (ref "C240")
      (value "1uF 50V")
      (footprint "eagle-import:0805")
      (fields
        (field (name "HQ_PART") "CA0182352")
        (field (name "LCSC_PART") "C28323")
        (field (name "MANUFACTURER") "TDK")
      )
      (libsource (lib "eagle-import") (part "1UF-50V0805"))
    )
    (comp (ref "C241")
      (value "100uF 50V")
      (footprint "eagle-import:6.3X7.7(DXL)")
      (fields
        (field (name "HQ_PART") "ZHLM0353527")
        (field (name "LCSC_PART") "C3151829")
        (field (name "MANUFACTURER") "ROQANG")
      )
      (libsource (lib "eagle-import") (part "100UF-50V6.3X7.7(DXL)"))
    )
    (comp (ref "C242")
      (value "1uF 50V")
      (footprint "eagle-import:0402")
      (fields (field (name "LCSC_PART") "C1518208"))
      (libsource (lib "eagle-import") (part "1UF-50V0402"))
    )
    (comp (ref "C243")
      (value "10uF 50V")
      (footprint "eagle-import:0805")
      (fields (field (name "LCSC_PART") "C440198"))
      (libsource (lib "eagle-import") (part "10UF-50V-0805"))
    )
    (comp (ref "C244")
      (value "10uF 50V")
      (footprint "eagle-import:0805")
      (fields (field (name "LCSC_PART") "C440198"))
      (libsource (lib "eagle-import") (part "10UF-50V-0805"))
    )
    (comp (ref "C245")
      (value "10uF 50V")
      (footprint "eagle-import:0805")
      (fields (field (name "LCSC_PART") "C440198"))
      (libsource (lib "eagle-import") (part "10UF-50V-0805"))
    )
    (comp (ref "C246")
      (value "100nF 25V")
      (footprint "eagle-import:0201")
      (fields
        (field (name "HQ_PART") "CA0183221")
        (field (name "LCSC_PART") "C76939")
        (field (name "MANUFACTURER") "Samsung")
      )
      (libsource (lib "eagle-import") (part "100NF-25V-0201"))
    )
    (comp (ref "C250")
      (value "100nF 25V")
      (footprint "eagle-import:0201")
      (fields
        (field (name "HQ_PART") "CA0183221")
        (field (name "LCSC_PART") "C76939")
        (field (name "MANUFACTURER") "Samsung")
      )
      (libsource (lib "eagle-import") (part "100NF-25V-0201"))
    )
    (comp (ref "C258")
      (value "1uF 50V")
      (footprint "eagle-import:0402")
      (fields (field (name "PACKAGE") "0402") (field (name "LCSC_PART") "C1518208"))
      (libsource (lib "eagle-import") (part "1UF-50V0402"))
    )
    (comp (ref "C259")
      (value "2.2nF 50V")
      (footprint "eagle-import:0402")
      (fields
        (field (name "PACKAGE") "0402")
        (field (name "HQ_PART") "CA0176616")
        (field (name "MANUFACTURER") "WALSIN")
        (field (name "MPN") "0402B222K500CT")
      )
      (libsource (lib "eagle-import") (part "2.2NF-50V-0402"))
    )
    (comp (ref "C260")
      (value "2.2nF 50V")
      (footprint "eagle-import:0402")
      (fields
        (field (name "PACKAGE") "0402")
        (field (name "HQ_PART") "CA0176616")
        (field (name "MANUFACTURER") "WALSIN")
        (field (name "MPN") "0402B222K500CT")
      )
      (libsource (lib "eagle-import") (part "2.2NF-50V-0402"))
    )
    (comp (ref "C261")
      (value "10uF 50V")
      (footprint "eagle-import:0805")
      (fields (field (name "LCSC_PART") "C440198"))
      (libsource (lib "eagle-import") (part "10UF-50V-0805"))
    )
    (comp (ref "C262")
      (value "330uF 50V")
      (footprint "eagle-import:10X10.5(DXL)")
      (fields (field (name "LCSC_PART") "C2895745") (field (name "MPN") "EEE-FT1H331AP"))
      (libsource (lib "eagle-import") (part "330UF-50V10X10.5(DXL)"))
    )
    (comp (ref "C263")
      (value "1nF 2kV")
      (footprint "eagle-import:1206")
      (fields
        (field (name "PACKAGE") "1206")
        (field (name "HQ_PART") "CA0134884")
        (field (name "LCSC_PART") "C173242")
        (field (name "MANUFACTURER") "Johanson Dielectrics ")
      )
      (libsource (lib "eagle-import") (part "1NF-2KV"))
    )
    (comp (ref "IC32")
      (value "TPS552882")
      (footprint "eagle-import:RPM0026A-MFG")
      (fields
        (field (name "MANUFACTURER_PART_NUMBER") "TPS552882QRPMRQ1")
        (field (name "COPYRIGHT") "Copyright (C) 2025 Ultra Librarian. All rights reserved.")
      )
      (libsource (lib "eagle-import") (part "TPS552882"))
    )
    (comp (ref "IC33")
      (value "INA219BIDCNT")
      (footprint "eagle-import:SOT23-8")
      (fields
        (field (name "HQ_PART") "IC0063216")
        (field (name "LCSC_PART") "C2653868")
        (field (name "MANUFACTURER") "Texas Instruments")
      )
      (libsource (lib "eagle-import") (part "INA219BIDCNT"))
    )
    (comp (ref "IC34")
      (value "STUSB4710AQ1TR")
      (footprint "eagle-import:QFN50P300X300X55-16N")
      (libsource (lib "eagle-import") (part "STUSB4710AQ1TR"))
    )
    (comp (ref "L8")
      (value "4.7uH 11.3A")
      (footprint "eagle-import:WE-PDHV_1280")
      (fields
        (field (name "LCSC_PART") "C2998768")
        (field (name "MANUFACTURER") "Sumida")
        (field (name "MPN") "CDRH127NP-4R7NC")
      )
      (libsource (lib "eagle-import") (part "4.7UH-PWR"))
    )
    (comp (ref "PORT7")
      (value "632722100213")
      (footprint "eagle-import:632722100213")
      (fields
        (field (name "LCSC_PART") "C2927029")
        (field (name "MANUFACTURER") "DEALON")
        (field (name "MPN") "USB-TYPE-C-009 ")
      )
      (libsource (lib "eagle-import") (part "USB-C-POWERONLY"))
    )
    (comp (ref "R196")
      (value "200K 1%")
      (footprint "eagle-import:0201")
      (fields (field (name "LCSC_PART") "C270357"))
      (libsource (lib "eagle-import") (part "200K-1%0201"))
    )
    (comp (ref "R197")
      (value "12.7K 1%")
      (footprint "eagle-import:0201")
      (fields
        (field (name "LCSC_PART") "C423755")
        (field (name "MANUFACTURER") "UNI-ROYAL")
        (field (name "MPN") "0201WMF1272TEE")
      )
      (libsource (lib "eagle-import") (part "12.7K-1%0201"))
    )
    (comp (ref "R198")
      (value "4.64K 1%")
      (footprint "eagle-import:0201")
      (fields
        (field (name "LCSC_PART") "C166186")
        (field (name "MANUFACTURER") " RALEC")
        (field (name "MPN") "RTT014641FTH")
      )
      (libsource (lib "eagle-import") (part "4.64K-1%-0201"))
    )
    (comp (ref "R199")
      (value "4.64K 1%")
      (footprint "eagle-import:0201")
      (fields
        (field (name "LCSC_PART") "C166186")
        (field (name "MANUFACTURER") " RALEC")
        (field (name "MPN") "RTT014641FTH")
      )
      (libsource (lib "eagle-import") (part "4.64K-1%-0201"))
    )
    (comp (ref "R200")
      (value "8.87K 1%")
      (footprint "eagle-import:0201")
      (fields
        (field (name "LCSC_PART") "C423413")
        (field (name "MANUFACTURER") " UNI-ROYAL")
        (field (name "MPN") "0201WMF8871TEE")
      )
      (libsource (lib "eagle-import") (part "8.87K-1%-0201"))
    )
    (comp (ref "R201")
      (value "30.9K 1%")
      (footprint "eagle-import:0201")
      (fields (field (name "LCSC_PART") "C364366"))
      (libsource (lib "eagle-import") (part "30.9K-1%0201"))
    )
    (comp (ref "R202")
      (value "100K 1%")
      (footprint "eagle-import:0201")
      (fields (field (name "LCSC_PART") "C270364"))
      (libsource (lib "eagle-import") (part "100K-1%0201"))
    )
    (comp (ref "R203")
      (value "10K 1%")
      (footprint "eagle-import:0402")
      (fields
        (field (name "HQ_PART") "RE0207399")
        (field (name "LCSC_PART") "C25744")
        (field (name "MANUFACTURER") "ROHM")
      )
      (libsource (lib "eagle-import") (part "10K-1%0402"))
    )
    (comp (ref "R204")
      (value "10K 1%")
      (footprint "eagle-import:0402")
      (fields
        (field (name "HQ_PART") "RE0207399")
        (field (name "LCSC_PART") "C25744")
        (field (name "MANUFACTURER") "ROHM")
      )
      (libsource (lib "eagle-import") (part "10K-1%0402"))
    )
    (comp (ref "R218")
      (value "10K 1%")
      (footprint "eagle-import:0201")
      (fields
        (field (name "HQ_PART") "RE0208620")
        (field (name "LCSC_PART") "C473048")
        (field (name "MANUFACTURER") "FH")
      )
      (libsource (lib "eagle-import") (part "10K-1%0201"))
    )
    (comp (ref "R219")
      (value "10K 1%")
      (footprint "eagle-import:0402")
      (fields
        (field (name "HQ_PART") "RE0207399")
        (field (name "LCSC_PART") "C25744")
        (field (name "MANUFACTURER") "ROHM")
      )
      (libsource (lib "eagle-import") (part "10K-1%0402"))
    )
    (comp (ref "R220")
      (value "0.010R 1%")
      (footprint "eagle-import:2512")
      (fields
        (field (name "LCSC_PART") "C127692")
        (field (name "MANUFACTURER") " UNI-ROYAL")
        (field (name "MPN") "25121WF100MT4E")
      )
      (libsource (lib "eagle-import") (part "0.010R-1%-2512"))
    )
    (comp (ref "R221")
      (value "0R 1%")
      (footprint "eagle-import:0201")
      (fields
        (field (name "HA_PART") "RE0015349")
        (field (name "LCSC_PART") "C106227")
        (field (name "MANUFACTURER") "Yageo")
      )
      (libsource (lib "eagle-import") (part "0R0201"))
    )
    (comp (ref "R222")
      (value "49.9K 1%")
      (footprint "eagle-import:0201")
      (fields
        (field (name "HQ_PART") "RE0461584")
        (field (name "LCSC_PART") "C138136")
        (field (name "MANUFACTURER") "Yageo")
      )
      (libsource (lib "eagle-import") (part "49.9K-1%0201"))
    )
    (comp (ref "R223")
      (value "20K 1%")
      (footprint "eagle-import:0201")
      (fields (field (name "LCSC_PART") "C473466"))
      (libsource (lib "eagle-import") (part "20K-1%0201"))
    )
    (comp (ref "R224")
      (value "150K")
      (footprint "eagle-import:R0201")
      (libsource (lib "eagle-import") (part "R0201"))
    )
    (comp (ref "R233")
      (value "15K 1%")
      (footprint "eagle-import:0201")
      (fields (field (name "LCSC_PART") "C295774"))
      (libsource (lib "eagle-import") (part "15K-1%0201"))
    )
    (comp (ref "R234")
      (value "0.010R 1%")
      (footprint "eagle-import:2512")
      (fields
        (field (name "LCSC_PART") "C127692")
        (field (name "MANUFACTURER") " UNI-ROYAL")
        (field (name "MPN") "25121WF100MT4E")
      )
      (libsource (lib "eagle-import") (part "0.010R-1%-2512"))
    )
    (comp (ref "R235")
      (value "1R 1%")
      (footprint "eagle-import:0402")
      (fields
        (field (name "HQ_PART") "RE0322446")
        (field (name "MANUFACTURER") "RALEC")
        (field (name "MPN") "RTT021R00FTH")
      )
      (libsource (lib "eagle-import") (part "1R-1%0402"))
    )
    (comp (ref "R236")
      (value "1R 1%")
      (footprint "eagle-import:0402")
      (fields
        (field (name "HQ_PART") "RE0322446")
        (field (name "MANUFACTURER") "RALEC")
        (field (name "MPN") "RTT021R00FTH")
      )
      (libsource (lib "eagle-import") (part "1R-1%0402"))
    )
    (comp (ref "R237")
      (value "0R 1%")
      (footprint "eagle-import:0201")
      (fields
        (field (name "PACKAGE") "0201")
        (field (name "HA_PART") "RE0015349")
        (field (name "LCSC_PART") "C106227")
        (field (name "MANUFACTURER") "Yageo")
      )
      (libsource (lib "eagle-import") (part "0R0201"))
    )
    (comp (ref "R238")
      (value "0R 1%")
      (footprint "eagle-import:0201")
      (fields
        (field (name "PACKAGE") "0201")
        (field (name "HA_PART") "RE0015349")
        (field (name "LCSC_PART") "C106227")
        (field (name "MANUFACTURER") "Yageo")
      )
      (libsource (lib "eagle-import") (part "0R0201"))
    )
    (comp (ref "R239")
      (value "10K 1%")
      (footprint "eagle-import:0201")
      (fields
        (field (name "HQ_PART") "RE0208620")
        (field (name "LCSC_PART") "C473048")
        (field (name "MANUFACTURER") "FH")
      )
      (libsource (lib "eagle-import") (part "10K-1%0201"))
    )
    (comp (ref "R240")
      (value "1R 1%")
      (footprint "eagle-import:0603")
      (fields
        (field (name "PACKAGE") "0603")
        (field (name "HQ_PART") "RE0421839")
        (field (name "MANUFACTURER") "RALEC")
        (field (name "MPN") "RTT031R00FTP")
      )
      (libsource (lib "eagle-import") (part "1R-1%0603"))
    )
    (comp (ref "R245")
      (value "1R 1%")
      (footprint "eagle-import:0603")
      (fields
        (field (name "PACKAGE") "0603")
        (field (name "HQ_PART") "RE0421839")
        (field (name "MANUFACTURER") "RALEC")
        (field (name "MPN") "RTT031R00FTP")
      )
      (libsource (lib "eagle-import") (part "1R-1%0603"))
    )
    (comp (ref "R246")
      (value "1M 1%")
      (footprint "eagle-import:1206")
      (fields
        (field (name "PACKAGE") "1206")
        (field (name "HQ_PART") "RE0188103")
        (field (name "LCSC_PART") "C17927")
        (field (name "MANUFACTURER") "Uniohm")
      )
      (libsource (lib "eagle-import") (part "1M-1%1206"))
    )
    (comp (ref "T31")
      (value "DMP3013SFV")
      (footprint "eagle-import:POWERDI3333-8_UX_DIO-L")
      (fields (field (name "MANUFACTURER_PART_NUMBER") "DMP3013SFV-7"))
      (libsource (lib "eagle-import") (part "DMP3013SFV-7UX"))
    )
    (comp (ref "T32")
      (value "DMP3013SFV")
      (footprint "eagle-import:POWERDI3333-8_UX_DIO-L")
      (fields (field (name "MANUFACTURER_PART_NUMBER") "DMP3013SFV-7"))
      (libsource (lib "eagle-import") (part "DMP3013SFV-7UX"))
    )
    (comp (ref "T33")
      (value "DMP3013SFV")
      (footprint "eagle-import:POWERDI3333-8_UX_DIO-L")
      (fields (field (name "MANUFACTURER_PART_NUMBER") "DMP3013SFV-7"))
      (libsource (lib "eagle-import") (part "DMP3013SFV-7UX"))
    )
    (comp (ref "T34")
      (value "BSZ065N06")
      (footprint "eagle-import:POWERDI3333-8_UX_DIO-L")
      (fields
        (field (name "MANUFACTURER_PART_NUMBER") "IPZ40N04S5L7R4ATMA1")
        (field (name "COPYRIGHT") "Copyright (C) 2025 Ultra Librarian. All rights reserved.")
      )
      (libsource (lib "eagle-import") (part "IPZ40N04S5L7R4ATMA1"))
    )
    (comp (ref "T35")
      (value "BSZ065N06")
      (footprint "eagle-import:POWERDI3333-8_UX_DIO-L")
      (fields
        (field (name "MANUFACTURER_PART_NUMBER") "IPZ40N04S5L7R4ATMA1")
        (field (name "COPYRIGHT") "Copyright (C) 2025 Ultra Librarian. All rights reserved.")
      )
      (libsource (lib "eagle-import") (part "IPZ40N04S5L7R4ATMA1"))
    )
    (comp (ref "C30")
      (value "22nF 50V")
      (footprint "eagle-import:0402")
      (fields
        (field (name "HQ_PART") "CA0171190")
        (field (name "LCSC_PART") "C1532")
        (field (name "MANUFACTURER") "Samsung")
      )
      (libsource (lib "eagle-import") (part "22NF-50V0402"))
    )
    (comp (ref "C31")
      (value "1nF 2kV")
      (footprint "eagle-import:1206")
      (fields
        (field (name "HQ_PART") "CA0134884")
        (field (name "LCSC_PART") "C173242")
        (field (name "MANUFACTURER") "Johanson Dielectrics ")
      )
      (libsource (lib "eagle-import") (part "1NF-2KV"))
    )
    (comp (ref "C32")
      (value "100nF 25V")
      (footprint "eagle-import:0402")
      (fields
        (field (name "HQ_PART") "CA0176807")
        (field (name "LCSC_PART") "C56392")
        (field (name "MANUFACTURER") "Walsin")
      )
      (libsource (lib "eagle-import") (part "100NF-25V-0402"))
    )
    (comp (ref "C33")
      (value "6.8nF 50V")
      (footprint "eagle-import:0201")
      (fields
        (field (name "HQ_PART") "CA0363038")
        (field (name "LCSC_PART") "C285015")
        (field (name "MANUFACTURER") "FH")
      )
      (libsource (lib "eagle-import") (part "6.8NF-50V0201"))
    )
    (comp (ref "C34")
      (value "6.8nF 50V")
      (footprint "eagle-import:0201")
      (fields
        (field (name "HQ_PART") "CA0363038")
        (field (name "LCSC_PART") "C285015")
        (field (name "MANUFACTURER") "FH")
      )
      (libsource (lib "eagle-import") (part "6.8NF-50V0201"))
    )
    (comp (ref "C35")
      (value "100nF 25V")
      (footprint "eagle-import:0201")
      (fields
        (field (name "HQ_PART") "CA0183221")
        (field (name "LCSC_PART") "C76939")
        (field (name "MANUFACTURER") "Samsung")
      )
      (libsource (lib "eagle-import") (part "100NF-25V-0201"))
    )
    (comp (ref "C36")
      (value "4.7uF 25V")
      (footprint "eagle-import:0402")
      (fields
        (field (name "HQ_PART") "ZHLM0023346")
        (field (name "LCSC_PART") "C22367824")
        (field (name "MANUFACTURER") "Murata")
      )
      (libsource (lib "eagle-import") (part "4.7UF-25V0402"))
    )
    (comp (ref "C37")
      (value "18pF 50V")
      (footprint "eagle-import:0201")
      (fields
        (field (name "HQ_PART") "CA0486739")
        (field (name "LCSC_PART") "C62164")
        (field (name "MANUFACTURER") "Yageo")
      )
      (libsource (lib "eagle-import") (part "18PF-50V-0201"))
    )
    (comp (ref "C38")
      (value "18pF 50V")
      (footprint "eagle-import:0201")
      (fields
        (field (name "HQ_PART") "CA0486739")
        (field (name "LCSC_PART") "C62164")
        (field (name "MANUFACTURER") "Yageo")
      )
      (libsource (lib "eagle-import") (part "18PF-50V-0201"))
    )
    (comp (ref "C221")
      (value "100nF 25V")
      (footprint "eagle-import:0201")
      (fields
        (field (name "HQ_PART") "CA0183221")
        (field (name "LCSC_PART") "C76939")
        (field (name "MANUFACTURER") "Samsung")
      )
      (libsource (lib "eagle-import") (part "100NF-25V-0201"))
    )
    (comp (ref "C222")
      (value "100nF 25V")
      (footprint "eagle-import:0201")
      (fields
        (field (name "HQ_PART") "CA0183221")
        (field (name "LCSC_PART") "C76939")
        (field (name "MANUFACTURER") "Samsung")
      )
      (libsource (lib "eagle-import") (part "100NF-25V-0201"))
    )
    (comp (ref "C223")
      (value "100nF 25V")
      (footprint "eagle-import:0201")
      (fields
        (field (name "HQ_PART") "CA0183221")
        (field (name "LCSC_PART") "C76939")
        (field (name "MANUFACTURER") "Samsung")
      )
      (libsource (lib "eagle-import") (part "100NF-25V-0201"))
    )
    (comp (ref "C224")
      (value "100nF 25V")
      (footprint "eagle-import:0201")
      (fields
        (field (name "HQ_PART") "CA0183221")
        (field (name "LCSC_PART") "C76939")
        (field (name "MANUFACTURER") "Samsung")
      )
      (libsource (lib "eagle-import") (part "100NF-25V-0201"))
    )
    (comp (ref "C225")
      (value "100nF 25V")
      (footprint "eagle-import:0201")
      (fields
        (field (name "HQ_PART") "CA0183221")
        (field (name "LCSC_PART") "C76939")
        (field (name "MANUFACTURER") "Samsung")
      )
      (libsource (lib "eagle-import") (part "100NF-25V-0201"))
    )
    (comp (ref "C226")
      (value "100nF 25V")
      (footprint "eagle-import:0201")
      (fields
        (field (name "HQ_PART") "CA0183221")
        (field (name "LCSC_PART") "C76939")
        (field (name "MANUFACTURER") "Samsung")
      )
      (libsource (lib "eagle-import") (part "100NF-25V-0201"))
    )
    (comp (ref "C227")
      (value "100nF 25V")
      (footprint "eagle-import:0201")
      (fields
        (field (name "HQ_PART") "CA0183221")
        (field (name "LCSC_PART") "C76939")
        (field (name "MANUFACTURER") "Samsung")
      )
      (libsource (lib "eagle-import") (part "100NF-25V-0201"))
    )
    (comp (ref "C228")
      (value "100nF 25V")
      (footprint "eagle-import:0201")
      (fields
        (field (name "HQ_PART") "CA0183221")
        (field (name "LCSC_PART") "C76939")
        (field (name "MANUFACTURER") "Samsung")
      )
      (libsource (lib "eagle-import") (part "100NF-25V-0201"))
    )
    (comp (ref "C229")
      (value "100nF 25V")
      (footprint "eagle-import:0201")
      (fields
        (field (name "HQ_PART") "CA0183221")
        (field (name "LCSC_PART") "C76939")
        (field (name "MANUFACTURER") "Samsung")
      )
      (libsource (lib "eagle-import") (part "100NF-25V-0201"))
    )
    (comp (ref "ETH1")
      (value "J1B1211CCD")
      (footprint "eagle-import:J1B1211CCD")
      (fields
        (field (name "HQ_PART") "UN0002907")
        (field (name "LCSC_PART") "C910371")
        (field (name "MANUFACTURER") "WIZnet")
      )
      (libsource (lib "eagle-import") (part "J1B1211CCD"))
    )
    (comp (ref "IC31")
      (value "W5500")
      (footprint "eagle-import:LQFP48")
      (fields
        (field (name "HQ_PART") "IC0084426")
        (field (name "LCSC_PART") "C32843")
        (field (name "MANUFACTURER") "WIZNET")
      )
      (libsource (lib "eagle-import") (part "W5500"))
    )
    (comp (ref "L10")
      (value "BLM18EG221TN1D")
      (footprint "eagle-import:0603")
      (libsource (lib "eagle-import") (part "R0603"))
    )
    (comp (ref "R33")
      (value "470R 1%")
      (footprint "eagle-import:0402")
      (fields
        (field (name "HQ_PART") "RE0205922")
        (field (name "LCSC_PART") "C25117")
        (field (name "MANUFACTURER") "Panasonic")
      )
      (libsource (lib "eagle-import") (part "470R-1%0402"))
    )
    (comp (ref "R34")
      (value "470R 1%")
      (footprint "eagle-import:0402")
      (fields
        (field (name "HQ_PART") "RE0205922")
        (field (name "LCSC_PART") "C25117")
        (field (name "MANUFACTURER") "Panasonic")
      )
      (libsource (lib "eagle-import") (part "470R-1%0402"))
    )
    (comp (ref "R35")
      (value "470R 1%")
      (footprint "eagle-import:0402")
      (fields
        (field (name "HQ_PART") "RE0205922")
        (field (name "LCSC_PART") "C25117")
        (field (name "MANUFACTURER") "Panasonic")
      )
      (libsource (lib "eagle-import") (part "470R-1%0402"))
    )
    (comp (ref "R36")
      (value "1M 1%")
      (footprint "eagle-import:1206")
      (fields
        (field (name "HQ_PART") "RE0188103")
        (field (name "LCSC_PART") "C17927")
        (field (name "MANUFACTURER") "Uniohm")
      )
      (libsource (lib "eagle-import") (part "1M-1%1206"))
    )
    (comp (ref "R37")
      (value "3.3R 1%")
      (footprint "eagle-import:0201")
      (fields
        (field (name "HQ_PART") "RE0422979")
        (field (name "LCSC_PART") "C158547")
        (field (name "MANUFACTURER") "Uniohm")
      )
      (libsource (lib "eagle-import") (part "3.3R-1%0201"))
    )
    (comp (ref "R38")
      (value "3.3R 1%")
      (footprint "eagle-import:0201")
      (fields
        (field (name "HQ_PART") "RE0422979")
        (field (name "LCSC_PART") "C158547")
        (field (name "MANUFACTURER") "Uniohm")
      )
      (libsource (lib "eagle-import") (part "3.3R-1%0201"))
    )
    (comp (ref "R39")
      (value "3.3R 1%")
      (footprint "eagle-import:0201")
      (fields
        (field (name "HQ_PART") "RE0422979")
        (field (name "LCSC_PART") "C158547")
        (field (name "MANUFACTURER") "Uniohm")
      )
      (libsource (lib "eagle-import") (part "3.3R-1%0201"))
    )
    (comp (ref "R40")
      (value "3.3R 1%")
      (footprint "eagle-import:0201")
      (fields
        (field (name "HQ_PART") "RE0422979")
        (field (name "LCSC_PART") "C158547")
        (field (name "MANUFACTURER") "Uniohm")
      )
      (libsource (lib "eagle-import") (part "3.3R-1%0201"))
    )
    (comp (ref "R41")
      (value "49.9R 1%")
      (footprint "eagle-import:0201")
      (fields
        (field (name "HQ_PART") "RE0721921")
        (field (name "LCSC_PART") "C155744")
        (field (name "MANUFACTURER") "FH")
      )
      (libsource (lib "eagle-import") (part "49.9R-1%0201"))
    )
    (comp (ref "R42")
      (value "49.9R 1%")
      (footprint "eagle-import:0201")
      (fields
        (field (name "HQ_PART") "RE0721921")
        (field (name "LCSC_PART") "C155744")
        (field (name "MANUFACTURER") "FH")
      )
      (libsource (lib "eagle-import") (part "49.9R-1%0201"))
    )
    (comp (ref "R43")
      (value "49.9R 1%")
      (footprint "eagle-import:0201")
      (fields
        (field (name "HQ_PART") "RE0721921")
        (field (name "LCSC_PART") "C155744")
        (field (name "MANUFACTURER") "FH")
      )
      (libsource (lib "eagle-import") (part "49.9R-1%0201"))
    )
    (comp (ref "R44")
      (value "49.9R 1%")
      (footprint "eagle-import:0201")
      (fields
        (field (name "HQ_PART") "RE0721921")
        (field (name "LCSC_PART") "C155744")
        (field (name "MANUFACTURER") "FH")
      )
      (libsource (lib "eagle-import") (part "49.9R-1%0201"))
    )
    (comp (ref "R45")
      (value "12.4K 1%")
      (footprint "eagle-import:R0201")
      (libsource (lib "eagle-import") (part "R0201"))
    )
    (comp (ref "R205")
      (value "1M 1%")
      (footprint "eagle-import:0201")
      (fields
        (field (name "HQ_PART") "RE0422946")
        (field (name "LCSC_PART") "C295786")
        (field (name "MANUFACTURER") "Yageo")
      )
      (libsource (lib "eagle-import") (part "1M-1%0201"))
    )
    (comp (ref "R206")
      (value "4.7K 1%")
      (footprint "eagle-import:0201")
      (fields
        (field (name "HQ_PART") "RE0208670")
        (field (name "LCSC_PART") "C270346")
        (field (name "MANUFACTURER") "RALEC")
      )
      (libsource (lib "eagle-import") (part "4.7K-1%0201"))
    )
    (comp (ref "R208")
      (value "4.7K 1%")
      (footprint "eagle-import:0201")
      (fields
        (field (name "HQ_PART") "RE0208670")
        (field (name "LCSC_PART") "C270346")
        (field (name "MANUFACTURER") "RALEC")
      )
      (libsource (lib "eagle-import") (part "4.7K-1%0201"))
    )
    (comp (ref "R225")
      (value "4.7K 1%")
      (footprint "eagle-import:0201")
      (fields
        (field (name "HQ_PART") "RE0208670")
        (field (name "LCSC_PART") "C270346")
        (field (name "MANUFACTURER") "RALEC")
      )
      (libsource (lib "eagle-import") (part "4.7K-1%0201"))
    )
    (comp (ref "R226")
      (value "4.7K 1%")
      (footprint "eagle-import:0201")
      (fields
        (field (name "HQ_PART") "RE0208670")
        (field (name "LCSC_PART") "C270346")
        (field (name "MANUFACTURER") "RALEC")
      )
      (libsource (lib "eagle-import") (part "4.7K-1%0201"))
    )
    (comp (ref "R227")
      (value "4.7K 1%")
      (footprint "eagle-import:0201")
      (fields
        (field (name "HQ_PART") "RE0208670")
        (field (name "LCSC_PART") "C270346")
        (field (name "MANUFACTURER") "RALEC")
      )
      (libsource (lib "eagle-import") (part "4.7K-1%0201"))
    )
    (comp (ref "R279")
      (value "0R 1%")
      (footprint "eagle-import:0201")
      (fields
        (field (name "PACKAGE") "0201")
        (field (name "HA_PART") "RE0015349")
        (field (name "LCSC_PART") "C106227")
        (field (name "MANUFACTURER") "Yageo")
      )
      (libsource (lib "eagle-import") (part "0R0201"))
    )
    (comp (ref "R280")
      (value "0R 1%")
      (footprint "eagle-import:0201")
      (fields
        (field (name "PACKAGE") "0201")
        (field (name "HA_PART") "RE0015349")
        (field (name "LCSC_PART") "C106227")
        (field (name "MANUFACTURER") "Yageo")
      )
      (libsource (lib "eagle-import") (part "0R0201"))
    )
    (comp (ref "X2")
      (value "25MHz")
      (footprint "eagle-import:WE-XTAL_CFPX-180")
      (fields
        (field (name "HQ_PART") "CR0250343")
        (field (name "LCSC_PART") "C13740")
        (field (name "MANUFACTURER") "Epson")
      )
      (libsource (lib "eagle-import") (part "CRYSTAL-3225X322525MOB4SI"))
    )
    (comp (ref "C160")
      (value "1uF 10V")
      (footprint "eagle-import:0201")
      (fields (field (name "LCSC_PART") "C76935"))
      (libsource (lib "eagle-import") (part "1UF-10V0201"))
    )
    (comp (ref "C161")
      (value "1uF 10V")
      (footprint "eagle-import:0201")
      (fields (field (name "LCSC_PART") "C76935"))
      (libsource (lib "eagle-import") (part "1UF-10V0201"))
    )
    (comp (ref "C162")
      (value "1uF 50V")
      (footprint "eagle-import:0603")
      (fields (field (name "LCSC_PART") "C15849"))
      (libsource (lib "eagle-import") (part "1UF-50V0603"))
    )
    (comp (ref "C163")
      (value "4.7uF 25V")
      (footprint "eagle-import:0402")
      (fields
        (field (name "HQ_PART") "ZHLM0023346")
        (field (name "LCSC_PART") "C22367824")
        (field (name "MANUFACTURER") "Murata")
      )
      (libsource (lib "eagle-import") (part "4.7UF-25V0402"))
    )
    (comp (ref "C164")
      (value "10nF 50V")
      (footprint "eagle-import:0201")
      (fields (field (name "LCSC_PART") "C5142551"))
      (libsource (lib "eagle-import") (part "10NF-50V-0201"))
    )
    (comp (ref "C165")
      (value "100pF 50V")
      (footprint "eagle-import:0201")
      (fields
        (field (name "HQ_PART") "CA0177921")
        (field (name "MANUFACTURER") "DARFON")
        (field (name "MPN") "C0603NP0101JGT")
      )
      (libsource (lib "eagle-import") (part "100PF-50V0201"))
    )
    (comp (ref "C166")
      (value "10nF 50V")
      (footprint "eagle-import:0201")
      (fields (field (name "LCSC_PART") "C5142551"))
      (libsource (lib "eagle-import") (part "10NF-50V-0201"))
    )
    (comp (ref "C167")
      (value "100nF 50V")
      (footprint "eagle-import:0402")
      (fields (field (name "LCSC_PART") "C307331"))
      (libsource (lib "eagle-import") (part "100NF-50V-0402"))
    )
    (comp (ref "C168")
      (value "100nF 50V")
      (footprint "eagle-import:0402")
      (fields (field (name "LCSC_PART") "C307331"))
      (libsource (lib "eagle-import") (part "100NF-50V-0402"))
    )
    (comp (ref "C169")
      (value "10uF 50V")
      (footprint "eagle-import:0805")
      (fields (field (name "LCSC_PART") "C440198"))
      (libsource (lib "eagle-import") (part "10UF-50V-0805"))
    )
    (comp (ref "C170")
      (value "10uF 50V")
      (footprint "eagle-import:0805")
      (fields (field (name "LCSC_PART") "C440198"))
      (libsource (lib "eagle-import") (part "10UF-50V-0805"))
    )
    (comp (ref "C171")
      (value "1uF 50V")
      (footprint "eagle-import:0805")
      (fields
        (field (name "HQ_PART") "CA0182352")
        (field (name "LCSC_PART") "C28323")
        (field (name "MANUFACTURER") "TDK")
      )
      (libsource (lib "eagle-import") (part "1UF-50V0805"))
    )
    (comp (ref "C172")
      (value "100uF 50V")
      (footprint "eagle-import:6.3X7.7(DXL)")
      (fields
        (field (name "HQ_PART") "ZHLM0353527")
        (field (name "LCSC_PART") "C3151829")
        (field (name "MANUFACTURER") "ROQANG")
      )
      (libsource (lib "eagle-import") (part "100UF-50V6.3X7.7(DXL)"))
    )
    (comp (ref "C173")
      (value "1uF 50V")
      (footprint "eagle-import:0402")
      (fields (field (name "LCSC_PART") "C1518208"))
      (libsource (lib "eagle-import") (part "1UF-50V0402"))
    )
    (comp (ref "C174")
      (value "10uF 50V")
      (footprint "eagle-import:0805")
      (fields (field (name "LCSC_PART") "C440198"))
      (libsource (lib "eagle-import") (part "10UF-50V-0805"))
    )
    (comp (ref "C175")
      (value "10uF 50V")
      (footprint "eagle-import:0805")
      (fields (field (name "LCSC_PART") "C440198"))
      (libsource (lib "eagle-import") (part "10UF-50V-0805"))
    )
    (comp (ref "C197")
      (value "10uF 50V")
      (footprint "eagle-import:0805")
      (fields (field (name "LCSC_PART") "C440198"))
      (libsource (lib "eagle-import") (part "10UF-50V-0805"))
    )
    (comp (ref "C198")
      (value "100nF 25V")
      (footprint "eagle-import:0201")
      (fields
        (field (name "HQ_PART") "CA0183221")
        (field (name "LCSC_PART") "C76939")
        (field (name "MANUFACTURER") "Samsung")
      )
      (libsource (lib "eagle-import") (part "100NF-25V-0201"))
    )
    (comp (ref "C199")
      (value "100nF 25V")
      (footprint "eagle-import:0201")
      (fields
        (field (name "HQ_PART") "CA0183221")
        (field (name "LCSC_PART") "C76939")
        (field (name "MANUFACTURER") "Samsung")
      )
      (libsource (lib "eagle-import") (part "100NF-25V-0201"))
    )
    (comp (ref "C200")
      (value "1uF 50V")
      (footprint "eagle-import:0402")
      (fields (field (name "PACKAGE") "0402") (field (name "LCSC_PART") "C1518208"))
      (libsource (lib "eagle-import") (part "1UF-50V0402"))
    )
    (comp (ref "C201")
      (value "2.2nF 50V")
      (footprint "eagle-import:0402")
      (fields
        (field (name "PACKAGE") "0402")
        (field (name "HQ_PART") "CA0176616")
        (field (name "MANUFACTURER") "WALSIN")
        (field (name "MPN") "0402B222K500CT")
      )
      (libsource (lib "eagle-import") (part "2.2NF-50V-0402"))
    )
    (comp (ref "C202")
      (value "2.2nF 50V")
      (footprint "eagle-import:0402")
      (fields
        (field (name "PACKAGE") "0402")
        (field (name "HQ_PART") "CA0176616")
        (field (name "MANUFACTURER") "WALSIN")
        (field (name "MPN") "0402B222K500CT")
      )
      (libsource (lib "eagle-import") (part "2.2NF-50V-0402"))
    )
    (comp (ref "C203")
      (value "10uF 50V")
      (footprint "eagle-import:0805")
      (fields (field (name "LCSC_PART") "C440198"))
      (libsource (lib "eagle-import") (part "10UF-50V-0805"))
    )
    (comp (ref "C204")
      (value "330uF 50V")
      (footprint "eagle-import:10X10.5(DXL)")
      (fields (field (name "LCSC_PART") "C2895745") (field (name "MPN") "EEE-FT1H331AP"))
      (libsource (lib "eagle-import") (part "330UF-50V10X10.5(DXL)"))
    )
    (comp (ref "C205")
      (value "1nF 2kV")
      (footprint "eagle-import:1206")
      (fields
        (field (name "PACKAGE") "1206")
        (field (name "HQ_PART") "CA0134884")
        (field (name "LCSC_PART") "C173242")
        (field (name "MANUFACTURER") "Johanson Dielectrics ")
      )
      (libsource (lib "eagle-import") (part "1NF-2KV"))
    )
    (comp (ref "IC24")
      (value "TPS552882")
      (footprint "eagle-import:RPM0026A-MFG")
      (fields
        (field (name "MANUFACTURER_PART_NUMBER") "TPS552882QRPMRQ1")
        (field (name "COPYRIGHT") "Copyright (C) 2025 Ultra Librarian. All rights reserved.")
      )
      (libsource (lib "eagle-import") (part "TPS552882"))
    )
    (comp (ref "IC25")
      (value "INA219BIDCNT")
      (footprint "eagle-import:SOT23-8")
      (fields
        (field (name "HQ_PART") "IC0063216")
        (field (name "LCSC_PART") "C2653868")
        (field (name "MANUFACTURER") "Texas Instruments")
      )
      (libsource (lib "eagle-import") (part "INA219BIDCNT"))
    )
    (comp (ref "IC30")
      (value "STUSB4710AQ1TR")
      (footprint "eagle-import:QFN50P300X300X55-16N")
      (libsource (lib "eagle-import") (part "STUSB4710AQ1TR"))
    )
    (comp (ref "L7")
      (value "4.7uH 11.3A")
      (footprint "eagle-import:WE-PDHV_1280")
      (fields
        (field (name "LCSC_PART") "C2998768")
        (field (name "MANUFACTURER") "Sumida")
        (field (name "MPN") "CDRH127NP-4R7NC")
      )
      (libsource (lib "eagle-import") (part "4.7UH-PWR"))
    )
    (comp (ref "PORT6")
      (value "632722100213")
      (footprint "eagle-import:632722100213")
      (fields
        (field (name "LCSC_PART") "C2927029")
        (field (name "MANUFACTURER") "DEALON")
        (field (name "MPN") "USB-TYPE-C-009 ")
      )
      (libsource (lib "eagle-import") (part "USB-C-POWERONLY"))
    )
    (comp (ref "R170")
      (value "200K 1%")
      (footprint "eagle-import:0201")
      (fields (field (name "LCSC_PART") "C270357"))
      (libsource (lib "eagle-import") (part "200K-1%0201"))
    )
    (comp (ref "R171")
      (value "12.7K 1%")
      (footprint "eagle-import:0201")
      (fields
        (field (name "LCSC_PART") "C423755")
        (field (name "MANUFACTURER") "UNI-ROYAL")
        (field (name "MPN") "0201WMF1272TEE")
      )
      (libsource (lib "eagle-import") (part "12.7K-1%0201"))
    )
    (comp (ref "R172")
      (value "4.64K 1%")
      (footprint "eagle-import:0201")
      (fields
        (field (name "LCSC_PART") "C166186")
        (field (name "MANUFACTURER") " RALEC")
        (field (name "MPN") "RTT014641FTH")
      )
      (libsource (lib "eagle-import") (part "4.64K-1%-0201"))
    )
    (comp (ref "R173")
      (value "4.64K 1%")
      (footprint "eagle-import:0201")
      (fields
        (field (name "LCSC_PART") "C166186")
        (field (name "MANUFACTURER") " RALEC")
        (field (name "MPN") "RTT014641FTH")
      )
      (libsource (lib "eagle-import") (part "4.64K-1%-0201"))
    )
    (comp (ref "R174")
      (value "8.87K 1%")
      (footprint "eagle-import:0201")
      (fields
        (field (name "LCSC_PART") "C423413")
        (field (name "MANUFACTURER") " UNI-ROYAL")
        (field (name "MPN") "0201WMF8871TEE")
      )
      (libsource (lib "eagle-import") (part "8.87K-1%-0201"))
    )
    (comp (ref "R175")
      (value "30.9K 1%")
      (footprint "eagle-import:0201")
      (fields (field (name "LCSC_PART") "C364366"))
      (libsource (lib "eagle-import") (part "30.9K-1%0201"))
    )
    (comp (ref "R176")
      (value "100K 1%")
      (footprint "eagle-import:0201")
      (fields (field (name "LCSC_PART") "C270364"))
      (libsource (lib "eagle-import") (part "100K-1%0201"))
    )
    (comp (ref "R177")
      (value "10K 1%")
      (footprint "eagle-import:0402")
      (fields
        (field (name "HQ_PART") "RE0207399")
        (field (name "LCSC_PART") "C25744")
        (field (name "MANUFACTURER") "ROHM")
      )
      (libsource (lib "eagle-import") (part "10K-1%0402"))
    )
    (comp (ref "R178")
      (value "10K 1%")
      (footprint "eagle-import:0402")
      (fields
        (field (name "HQ_PART") "RE0207399")
        (field (name "LCSC_PART") "C25744")
        (field (name "MANUFACTURER") "ROHM")
      )
      (libsource (lib "eagle-import") (part "10K-1%0402"))
    )
    (comp (ref "R179")
      (value "10K 1%")
      (footprint "eagle-import:0201")
      (fields
        (field (name "HQ_PART") "RE0208620")
        (field (name "LCSC_PART") "C473048")
        (field (name "MANUFACTURER") "FH")
      )
      (libsource (lib "eagle-import") (part "10K-1%0201"))
    )
    (comp (ref "R180")
      (value "10K 1%")
      (footprint "eagle-import:0402")
      (fields
        (field (name "HQ_PART") "RE0207399")
        (field (name "LCSC_PART") "C25744")
        (field (name "MANUFACTURER") "ROHM")
      )
      (libsource (lib "eagle-import") (part "10K-1%0402"))
    )
    (comp (ref "R181")
      (value "0.010R 1%")
      (footprint "eagle-import:2512")
      (fields
        (field (name "LCSC_PART") "C127692")
        (field (name "MANUFACTURER") " UNI-ROYAL")
        (field (name "MPN") "25121WF100MT4E")
      )
      (libsource (lib "eagle-import") (part "0.010R-1%-2512"))
    )
    (comp (ref "R182")
      (value "0R 1%")
      (footprint "eagle-import:0201")
      (fields
        (field (name "HA_PART") "RE0015349")
        (field (name "LCSC_PART") "C106227")
        (field (name "MANUFACTURER") "Yageo")
      )
      (libsource (lib "eagle-import") (part "0R0201"))
    )
    (comp (ref "R183")
      (value "49.9K 1%")
      (footprint "eagle-import:0201")
      (fields
        (field (name "HQ_PART") "RE0461584")
        (field (name "LCSC_PART") "C138136")
        (field (name "MANUFACTURER") "Yageo")
      )
      (libsource (lib "eagle-import") (part "49.9K-1%0201"))
    )
    (comp (ref "R184")
      (value "20K 1%")
      (footprint "eagle-import:0201")
      (fields (field (name "LCSC_PART") "C473466"))
      (libsource (lib "eagle-import") (part "20K-1%0201"))
    )
    (comp (ref "R185")
      (value "150K")
      (footprint "eagle-import:R0201")
      (libsource (lib "eagle-import") (part "R0201"))
    )
    (comp (ref "R186")
      (value "15K 1%")
      (footprint "eagle-import:0201")
      (fields (field (name "LCSC_PART") "C295774"))
      (libsource (lib "eagle-import") (part "15K-1%0201"))
    )
    (comp (ref "R187")
      (value "0.010R 1%")
      (footprint "eagle-import:2512")
      (fields
        (field (name "LCSC_PART") "C127692")
        (field (name "MANUFACTURER") " UNI-ROYAL")
        (field (name "MPN") "25121WF100MT4E")
      )
      (libsource (lib "eagle-import") (part "0.010R-1%-2512"))
    )
    (comp (ref "R188")
      (value "1R 1%")
      (footprint "eagle-import:0402")
      (fields
        (field (name "HQ_PART") "RE0322446")
        (field (name "MANUFACTURER") "RALEC")
        (field (name "MPN") "RTT021R00FTH")
      )
      (libsource (lib "eagle-import") (part "1R-1%0402"))
    )
    (comp (ref "R189")
      (value "1R 1%")
      (footprint "eagle-import:0402")
      (fields
        (field (name "HQ_PART") "RE0322446")
        (field (name "MANUFACTURER") "RALEC")
        (field (name "MPN") "RTT021R00FTH")
      )
      (libsource (lib "eagle-import") (part "1R-1%0402"))
    )
    (comp (ref "R190")
      (value "0R 1%")
      (footprint "eagle-import:0201")
      (fields
        (field (name "PACKAGE") "0201")
        (field (name "HA_PART") "RE0015349")
        (field (name "LCSC_PART") "C106227")
        (field (name "MANUFACTURER") "Yageo")
      )
      (libsource (lib "eagle-import") (part "0R0201"))
    )
    (comp (ref "R191")
      (value "0R 1%")
      (footprint "eagle-import:0201")
      (fields
        (field (name "PACKAGE") "0201")
        (field (name "HA_PART") "RE0015349")
        (field (name "LCSC_PART") "C106227")
        (field (name "MANUFACTURER") "Yageo")
      )
      (libsource (lib "eagle-import") (part "0R0201"))
    )
    (comp (ref "R192")
      (value "10K 1%")
      (footprint "eagle-import:0201")
      (fields
        (field (name "HQ_PART") "RE0208620")
        (field (name "LCSC_PART") "C473048")
        (field (name "MANUFACTURER") "FH")
      )
      (libsource (lib "eagle-import") (part "10K-1%0201"))
    )
    (comp (ref "R193")
      (value "1R 1%")
      (footprint "eagle-import:0603")
      (fields
        (field (name "PACKAGE") "0603")
        (field (name "HQ_PART") "RE0421839")
        (field (name "MANUFACTURER") "RALEC")
        (field (name "MPN") "RTT031R00FTP")
      )
      (libsource (lib "eagle-import") (part "1R-1%0603"))
    )
    (comp (ref "R194")
      (value "1R 1%")
      (footprint "eagle-import:0603")
      (fields
        (field (name "PACKAGE") "0603")
        (field (name "HQ_PART") "RE0421839")
        (field (name "MANUFACTURER") "RALEC")
        (field (name "MPN") "RTT031R00FTP")
      )
      (libsource (lib "eagle-import") (part "1R-1%0603"))
    )
    (comp (ref "R195")
      (value "1M 1%")
      (footprint "eagle-import:1206")
      (fields
        (field (name "PACKAGE") "1206")
        (field (name "HQ_PART") "RE0188103")
        (field (name "LCSC_PART") "C17927")
        (field (name "MANUFACTURER") "Uniohm")
      )
      (libsource (lib "eagle-import") (part "1M-1%1206"))
    )
    (comp (ref "T26")
      (value "DMP3013SFV")
      (footprint "eagle-import:POWERDI3333-8_UX_DIO-L")
      (fields (field (name "MANUFACTURER_PART_NUMBER") "DMP3013SFV-7"))
      (libsource (lib "eagle-import") (part "DMP3013SFV-7UX"))
    )
    (comp (ref "T27")
      (value "DMP3013SFV")
      (footprint "eagle-import:POWERDI3333-8_UX_DIO-L")
      (fields (field (name "MANUFACTURER_PART_NUMBER") "DMP3013SFV-7"))
      (libsource (lib "eagle-import") (part "DMP3013SFV-7UX"))
    )
    (comp (ref "T28")
      (value "DMP3013SFV")
      (footprint "eagle-import:POWERDI3333-8_UX_DIO-L")
      (fields (field (name "MANUFACTURER_PART_NUMBER") "DMP3013SFV-7"))
      (libsource (lib "eagle-import") (part "DMP3013SFV-7UX"))
    )
    (comp (ref "T29")
      (value "BSZ065N06")
      (footprint "eagle-import:POWERDI3333-8_UX_DIO-L")
      (fields
        (field (name "MANUFACTURER_PART_NUMBER") "IPZ40N04S5L7R4ATMA1")
        (field (name "COPYRIGHT") "Copyright (C) 2025 Ultra Librarian. All rights reserved.")
      )
      (libsource (lib "eagle-import") (part "IPZ40N04S5L7R4ATMA1"))
    )
    (comp (ref "T30")
      (value "BSZ065N06")
      (footprint "eagle-import:POWERDI3333-8_UX_DIO-L")
      (fields
        (field (name "MANUFACTURER_PART_NUMBER") "IPZ40N04S5L7R4ATMA1")
        (field (name "COPYRIGHT") "Copyright (C) 2025 Ultra Librarian. All rights reserved.")
      )
      (libsource (lib "eagle-import") (part "IPZ40N04S5L7R4ATMA1"))
    )
    (comp (ref "C2")
      (value "100nF 25V")
      (footprint "eagle-import:0201")
      (fields
        (field (name "HQ_PART") "CA0183221")
        (field (name "LCSC_PART") "C76939")
        (field (name "MANUFACTURER") "Samsung")
      )
      (libsource (lib "eagle-import") (part "100NF-25V-0201"))
    )
    (comp (ref "C3")
      (value "10uF 16V")
      (footprint "eagle-import:0603")
      (fields
        (field (name "HQ_PART") "CA0149236")
        (field (name "LCSC_PART") "C92487")
        (field (name "MANUFACTURER") "Murata")
      )
      (libsource (lib "eagle-import") (part "10UF-16V-0603"))
    )
    (comp (ref "C4")
      (value "10uF 16V")
      (footprint "eagle-import:0603")
      (fields
        (field (name "HQ_PART") "CA0149236")
        (field (name "LCSC_PART") "C92487")
        (field (name "MANUFACTURER") "Murata")
      )
      (libsource (lib "eagle-import") (part "10UF-16V-0603"))
    )
    (comp (ref "C5")
      (value "100uF 16V")
      (footprint "eagle-import:5X5.5(DXL)")
      (fields (field (name "LCSC_PART") "C2977550"))
      (libsource (lib "eagle-import") (part "100UF-16V5X5.5(DXL)"))
    )
    (comp (ref "C11")
      (value "1nF 2kV")
      (footprint "eagle-import:1206")
      (fields
        (field (name "PACKAGE") "1206")
        (field (name "HQ_PART") "CA0134884")
        (field (name "LCSC_PART") "C173242")
        (field (name "MANUFACTURER") "Johanson Dielectrics ")
      )
      (libsource (lib "eagle-import") (part "1NF-2KV"))
    )
    (comp (ref "C17")
      (value "100nF 25V")
      (footprint "eagle-import:0201")
      (fields
        (field (name "HQ_PART") "CA0183221")
        (field (name "LCSC_PART") "C76939")
        (field (name "MANUFACTURER") "Samsung")
      )
      (libsource (lib "eagle-import") (part "100NF-25V-0201"))
    )
    (comp (ref "C18")
      (value "100nF 25V")
      (footprint "eagle-import:0201")
      (fields
        (field (name "HQ_PART") "CA0183221")
        (field (name "LCSC_PART") "C76939")
        (field (name "MANUFACTURER") "Samsung")
      )
      (libsource (lib "eagle-import") (part "100NF-25V-0201"))
    )
    (comp (ref "C82")
      (value "100nF 25V")
      (footprint "eagle-import:0201")
      (fields
        (field (name "HQ_PART") "CA0183221")
        (field (name "LCSC_PART") "C76939")
        (field (name "MANUFACTURER") "Samsung")
      )
      (libsource (lib "eagle-import") (part "100NF-25V-0201"))
    )
    (comp (ref "C83")
      (value "10uF 16V")
      (footprint "eagle-import:0603")
      (fields
        (field (name "HQ_PART") "CA0149236")
        (field (name "LCSC_PART") "C92487")
        (field (name "MANUFACTURER") "Murata")
      )
      (libsource (lib "eagle-import") (part "10UF-16V-0603"))
    )
    (comp (ref "C84")
      (value "10uF 16V")
      (footprint "eagle-import:0603")
      (fields
        (field (name "HQ_PART") "CA0149236")
        (field (name "LCSC_PART") "C92487")
        (field (name "MANUFACTURER") "Murata")
      )
      (libsource (lib "eagle-import") (part "10UF-16V-0603"))
    )
    (comp (ref "C85")
      (value "100uF 16V")
      (footprint "eagle-import:5X5.5(DXL)")
      (fields (field (name "LCSC_PART") "C2977550"))
      (libsource (lib "eagle-import") (part "100UF-16V5X5.5(DXL)"))
    )
    (comp (ref "D1")
      (value "Green")
      (footprint "eagle-import:LED-0603")
      (fields
        (field (name "HQ_PART") "PH0010430")
        (field (name "LCSC_PART") "C965804")
        (field (name "MANUFACTURER") "Wurth")
      )
      (libsource (lib "eagle-import") (part "LED-GREENLED-0603"))
    )
    (comp (ref "D2")
      (value "Red")
      (footprint "eagle-import:LED-0603")
      (fields (field (name "LCSC_PART") "C2286"))
      (libsource (lib "eagle-import") (part "LED-REDLED-0603"))
    )
    (comp (ref "D3")
      (value "Green")
      (footprint "eagle-import:LED-0603")
      (fields
        (field (name "HQ_PART") "PH0010430")
        (field (name "LCSC_PART") "C965804")
        (field (name "MANUFACTURER") "Wurth")
      )
      (libsource (lib "eagle-import") (part "LED-GREENLED-0603"))
    )
    (comp (ref "D4")
      (value "Red")
      (footprint "eagle-import:LED-0603")
      (fields (field (name "LCSC_PART") "C2286"))
      (libsource (lib "eagle-import") (part "LED-REDLED-0603"))
    )
    (comp (ref "H1")
      (value "MOUNT-PAD-ROUND3.3")
      (footprint "eagle-import:3,3-PAD")
      (libsource (lib "eagle-import") (part "MOUNT-PAD-ROUND3.3"))
    )
    (comp (ref "H2")
      (value "MOUNT-PAD-ROUND3.3")
      (footprint "eagle-import:3,3-PAD")
      (libsource (lib "eagle-import") (part "MOUNT-PAD-ROUND3.3"))
    )
    (comp (ref "H3")
      (value "MOUNT-PAD-ROUND3.3")
      (footprint "eagle-import:3,3-PAD")
      (libsource (lib "eagle-import") (part "MOUNT-PAD-ROUND3.3"))
    )
    (comp (ref "H4")
      (value "MOUNT-PAD-ROUND3.3")
      (footprint "eagle-import:3,3-PAD")
      (libsource (lib "eagle-import") (part "MOUNT-PAD-ROUND3.3"))
    )
    (comp (ref "IC1")
      (value "AP22653W6")
      (footprint "eagle-import:SOT23-6")
      (fields
        (field (name "HQ_PART") "PM0174903")
        (field (name "LCSC_PART") "C2158037")
        (field (name "MANUFACTURER") "Diodes Incorporated")
      )
      (libsource (lib "eagle-import") (part "AP22653W6"))
    )
    (comp (ref "IC4")
      (value "SN74LVC1G04DBVR")
      (footprint "eagle-import:SOT95P280X145-5N")
      (libsource (lib "eagle-import") (part "74LVC1G04"))
    )
    (comp (ref "IC5")
      (value "SN74LVC1G04DBVR")
      (footprint "eagle-import:SOT95P280X145-5N")
      (libsource (lib "eagle-import") (part "74LVC1G04"))
    )
    (comp (ref "IC8")
      (value "AP22653W6")
      (footprint "eagle-import:SOT23-6")
      (fields
        (field (name "HQ_PART") "PM0174903")
        (field (name "LCSC_PART") "C2158037")
        (field (name "MANUFACTURER") "Diodes Incorporated")
      )
      (libsource (lib "eagle-import") (part "AP22653W6"))
    )
    (comp (ref "R1")
      (value "10K 1%")
      (footprint "eagle-import:0201")
      (fields
        (field (name "HQ_PART") "RE0208620")
        (field (name "LCSC_PART") "C473048")
        (field (name "MANUFACTURER") "FH")
      )
      (libsource (lib "eagle-import") (part "10K-1%0201"))
    )
    (comp (ref "R2")
      (value "1M 1%")
      (footprint "eagle-import:1206")
      (fields
        (field (name "PACKAGE") "1206")
        (field (name "HQ_PART") "RE0188103")
        (field (name "LCSC_PART") "C17927")
        (field (name "MANUFACTURER") "Uniohm")
      )
      (libsource (lib "eagle-import") (part "1M-1%1206"))
    )
    (comp (ref "R3")
      (value "20K 1%")
      (footprint "eagle-import:0201")
      (fields (field (name "LCSC_PART") "C473466"))
      (libsource (lib "eagle-import") (part "20K-1%0201"))
    )
    (comp (ref "R4")
      (value "10K 1%")
      (footprint "eagle-import:0201")
      (fields
        (field (name "HQ_PART") "RE0208620")
        (field (name "LCSC_PART") "C473048")
        (field (name "MANUFACTURER") "FH")
      )
      (libsource (lib "eagle-import") (part "10K-1%0201"))
    )
    (comp (ref "R12")
      (value "1K 1%")
      (footprint "eagle-import:0402")
      (fields
        (field (name "HQ_PART") "RE0208724")
        (field (name "LCSC_PART") "C11702")
        (field (name "MANUFACTURER") "FH")
      )
      (libsource (lib "eagle-import") (part "1K-1%0402"))
    )
    (comp (ref "R13")
      (value "10K 1%")
      (footprint "eagle-import:0402")
      (fields
        (field (name "HQ_PART") "RE0207399")
        (field (name "LCSC_PART") "C25744")
        (field (name "MANUFACTURER") "ROHM")
      )
      (libsource (lib "eagle-import") (part "10K-1%0402"))
    )
    (comp (ref "R14")
      (value "1K 1%")
      (footprint "eagle-import:0402")
      (fields
        (field (name "HQ_PART") "RE0208724")
        (field (name "LCSC_PART") "C11702")
        (field (name "MANUFACTURER") "FH")
      )
      (libsource (lib "eagle-import") (part "1K-1%0402"))
    )
    (comp (ref "R15")
      (value "1K 1%")
      (footprint "eagle-import:0402")
      (fields
        (field (name "HQ_PART") "RE0208724")
        (field (name "LCSC_PART") "C11702")
        (field (name "MANUFACTURER") "FH")
      )
      (libsource (lib "eagle-import") (part "1K-1%0402"))
    )
    (comp (ref "R16")
      (value "10K 1%")
      (footprint "eagle-import:0402")
      (fields
        (field (name "HQ_PART") "RE0207399")
        (field (name "LCSC_PART") "C25744")
        (field (name "MANUFACTURER") "ROHM")
      )
      (libsource (lib "eagle-import") (part "10K-1%0402"))
    )
    (comp (ref "R17")
      (value "1K 1%")
      (footprint "eagle-import:0402")
      (fields
        (field (name "HQ_PART") "RE0208724")
        (field (name "LCSC_PART") "C11702")
        (field (name "MANUFACTURER") "FH")
      )
      (libsource (lib "eagle-import") (part "1K-1%0402"))
    )
    (comp (ref "R84")
      (value "20K 1%")
      (footprint "eagle-import:0201")
      (fields (field (name "LCSC_PART") "C473466"))
      (libsource (lib "eagle-import") (part "20K-1%0201"))
    )
    (comp (ref "USBA_1-2")
      (value "61400826021")
      (footprint "eagle-import:61400826021")
      (libsource (lib "eagle-import") (part "61400826021"))
    )
    (comp (ref "VUSBA1")
      (value "TPB1,27")
      (footprint "eagle-import:B1,27")
      (libsource (lib "eagle-import") (part "TPB1,27"))
    )
    (comp (ref "VUSBA2")
      (value "TPB1,27")
      (footprint "eagle-import:B1,27")
      (libsource (lib "eagle-import") (part "TPB1,27"))
    )
    (comp (ref "C1")
      (value "1nF 2kV")
      (footprint "eagle-import:1206")
      (fields
        (field (name "PACKAGE") "1206")
        (field (name "HQ_PART") "CA0134884")
        (field (name "LCSC_PART") "C173242")
        (field (name "MANUFACTURER") "Johanson Dielectrics ")
      )
      (libsource (lib "eagle-import") (part "1NF-2KV"))
    )
    (comp (ref "C7")
      (value "100nF 25V")
      (footprint "eagle-import:0201")
      (fields
        (field (name "HQ_PART") "CA0183221")
        (field (name "LCSC_PART") "C76939")
        (field (name "MANUFACTURER") "Samsung")
      )
      (libsource (lib "eagle-import") (part "100NF-25V-0201"))
    )
    (comp (ref "C8")
      (value "10uF 16V")
      (footprint "eagle-import:0603")
      (fields
        (field (name "HQ_PART") "CA0149236")
        (field (name "LCSC_PART") "C92487")
        (field (name "MANUFACTURER") "Murata")
      )
      (libsource (lib "eagle-import") (part "10UF-16V-0603"))
    )
    (comp (ref "C9")
      (value "10uF 16V")
      (footprint "eagle-import:0603")
      (fields
        (field (name "HQ_PART") "CA0149236")
        (field (name "LCSC_PART") "C92487")
        (field (name "MANUFACTURER") "Murata")
      )
      (libsource (lib "eagle-import") (part "10UF-16V-0603"))
    )
    (comp (ref "C10")
      (value "100uF 16V")
      (footprint "eagle-import:5X5.5(DXL)")
      (fields (field (name "LCSC_PART") "C2977550"))
      (libsource (lib "eagle-import") (part "100UF-16V5X5.5(DXL)"))
    )
    (comp (ref "C12")
      (value "100nF 25V")
      (footprint "eagle-import:0201")
      (fields
        (field (name "HQ_PART") "CA0183221")
        (field (name "LCSC_PART") "C76939")
        (field (name "MANUFACTURER") "Samsung")
      )
      (libsource (lib "eagle-import") (part "100NF-25V-0201"))
    )
    (comp (ref "C13")
      (value "10uF 16V")
      (footprint "eagle-import:0603")
      (fields
        (field (name "HQ_PART") "CA0149236")
        (field (name "LCSC_PART") "C92487")
        (field (name "MANUFACTURER") "Murata")
      )
      (libsource (lib "eagle-import") (part "10UF-16V-0603"))
    )
    (comp (ref "C14")
      (value "10uF 16V")
      (footprint "eagle-import:0603")
      (fields
        (field (name "HQ_PART") "CA0149236")
        (field (name "LCSC_PART") "C92487")
        (field (name "MANUFACTURER") "Murata")
      )
      (libsource (lib "eagle-import") (part "10UF-16V-0603"))
    )
    (comp (ref "C15")
      (value "100uF 16V")
      (footprint "eagle-import:5X5.5(DXL)")
      (fields (field (name "LCSC_PART") "C2977550"))
      (libsource (lib "eagle-import") (part "100UF-16V5X5.5(DXL)"))
    )
    (comp (ref "C19")
      (value "100nF 25V")
      (footprint "eagle-import:0201")
      (fields
        (field (name "HQ_PART") "CA0183221")
        (field (name "LCSC_PART") "C76939")
        (field (name "MANUFACTURER") "Samsung")
      )
      (libsource (lib "eagle-import") (part "100NF-25V-0201"))
    )
    (comp (ref "C20")
      (value "100nF 25V")
      (footprint "eagle-import:0201")
      (fields
        (field (name "HQ_PART") "CA0183221")
        (field (name "LCSC_PART") "C76939")
        (field (name "MANUFACTURER") "Samsung")
      )
      (libsource (lib "eagle-import") (part "100NF-25V-0201"))
    )
    (comp (ref "D5")
      (value "Green")
      (footprint "eagle-import:LED-0603")
      (fields
        (field (name "HQ_PART") "PH0010430")
        (field (name "LCSC_PART") "C965804")
        (field (name "MANUFACTURER") "Wurth")
      )
      (libsource (lib "eagle-import") (part "LED-GREENLED-0603"))
    )
    (comp (ref "D6")
      (value "Red")
      (footprint "eagle-import:LED-0603")
      (fields (field (name "LCSC_PART") "C2286"))
      (libsource (lib "eagle-import") (part "LED-REDLED-0603"))
    )
    (comp (ref "D7")
      (value "Green")
      (footprint "eagle-import:LED-0603")
      (fields
        (field (name "HQ_PART") "PH0010430")
        (field (name "LCSC_PART") "C965804")
        (field (name "MANUFACTURER") "Wurth")
      )
      (libsource (lib "eagle-import") (part "LED-GREENLED-0603"))
    )
    (comp (ref "D8")
      (value "Red")
      (footprint "eagle-import:LED-0603")
      (fields (field (name "LCSC_PART") "C2286"))
      (libsource (lib "eagle-import") (part "LED-REDLED-0603"))
    )
    (comp (ref "IC2")
      (value "AP22653W6")
      (footprint "eagle-import:SOT23-6")
      (fields
        (field (name "HQ_PART") "PM0174903")
        (field (name "LCSC_PART") "C2158037")
        (field (name "MANUFACTURER") "Diodes Incorporated")
      )
      (libsource (lib "eagle-import") (part "AP22653W6"))
    )
    (comp (ref "IC3")
      (value "AP22653W6")
      (footprint "eagle-import:SOT23-6")
      (fields
        (field (name "HQ_PART") "PM0174903")
        (field (name "LCSC_PART") "C2158037")
        (field (name "MANUFACTURER") "Diodes Incorporated")
      )
      (libsource (lib "eagle-import") (part "AP22653W6"))
    )
    (comp (ref "IC6")
      (value "SN74LVC1G04DBVR")
      (footprint "eagle-import:SOT95P280X145-5N")
      (libsource (lib "eagle-import") (part "74LVC1G04"))
    )
    (comp (ref "IC7")
      (value "SN74LVC1G04DBVR")
      (footprint "eagle-import:SOT95P280X145-5N")
      (libsource (lib "eagle-import") (part "74LVC1G04"))
    )
    (comp (ref "R6")
      (value "20K 1%")
      (footprint "eagle-import:0201")
      (fields (field (name "LCSC_PART") "C473466"))
      (libsource (lib "eagle-import") (part "20K-1%0201"))
    )
    (comp (ref "R7")
      (value "10K 1%")
      (footprint "eagle-import:0201")
      (fields
        (field (name "HQ_PART") "RE0208620")
        (field (name "LCSC_PART") "C473048")
        (field (name "MANUFACTURER") "FH")
      )
      (libsource (lib "eagle-import") (part "10K-1%0201"))
    )
    (comp (ref "R8")
      (value "1M 1%")
      (footprint "eagle-import:1206")
      (fields
        (field (name "PACKAGE") "1206")
        (field (name "HQ_PART") "RE0188103")
        (field (name "LCSC_PART") "C17927")
        (field (name "MANUFACTURER") "Uniohm")
      )
      (libsource (lib "eagle-import") (part "1M-1%1206"))
    )
    (comp (ref "R9")
      (value "20K 1%")
      (footprint "eagle-import:0201")
      (fields (field (name "LCSC_PART") "C473466"))
      (libsource (lib "eagle-import") (part "20K-1%0201"))
    )
    (comp (ref "R10")
      (value "10K 1%")
      (footprint "eagle-import:0201")
      (fields
        (field (name "HQ_PART") "RE0208620")
        (field (name "LCSC_PART") "C473048")
        (field (name "MANUFACTURER") "FH")
      )
      (libsource (lib "eagle-import") (part "10K-1%0201"))
    )
    (comp (ref "R18")
      (value "1K 1%")
      (footprint "eagle-import:0402")
      (fields
        (field (name "HQ_PART") "RE0208724")
        (field (name "LCSC_PART") "C11702")
        (field (name "MANUFACTURER") "FH")
      )
      (libsource (lib "eagle-import") (part "1K-1%0402"))
    )
    (comp (ref "R19")
      (value "10K 1%")
      (footprint "eagle-import:0402")
      (fields
        (field (name "HQ_PART") "RE0207399")
        (field (name "LCSC_PART") "C25744")
        (field (name "MANUFACTURER") "ROHM")
      )
      (libsource (lib "eagle-import") (part "10K-1%0402"))
    )
    (comp (ref "R20")
      (value "1K 1%")
      (footprint "eagle-import:0402")
      (fields
        (field (name "HQ_PART") "RE0208724")
        (field (name "LCSC_PART") "C11702")
        (field (name "MANUFACTURER") "FH")
      )
      (libsource (lib "eagle-import") (part "1K-1%0402"))
    )
    (comp (ref "R21")
      (value "1K 1%")
      (footprint "eagle-import:0402")
      (fields
        (field (name "HQ_PART") "RE0208724")
        (field (name "LCSC_PART") "C11702")
        (field (name "MANUFACTURER") "FH")
      )
      (libsource (lib "eagle-import") (part "1K-1%0402"))
    )
    (comp (ref "R22")
      (value "10K 1%")
      (footprint "eagle-import:0402")
      (fields
        (field (name "HQ_PART") "RE0207399")
        (field (name "LCSC_PART") "C25744")
        (field (name "MANUFACTURER") "ROHM")
      )
      (libsource (lib "eagle-import") (part "10K-1%0402"))
    )
    (comp (ref "R23")
      (value "1K 1%")
      (footprint "eagle-import:0402")
      (fields
        (field (name "HQ_PART") "RE0208724")
        (field (name "LCSC_PART") "C11702")
        (field (name "MANUFACTURER") "FH")
      )
      (libsource (lib "eagle-import") (part "1K-1%0402"))
    )
    (comp (ref "USBA_3-4")
      (value "61400826021")
      (footprint "eagle-import:61400826021")
      (libsource (lib "eagle-import") (part "61400826021"))
    )
    (comp (ref "VUSBA3")
      (value "TPB1,27")
      (footprint "eagle-import:B1,27")
      (libsource (lib "eagle-import") (part "TPB1,27"))
    )
    (comp (ref "VUSBA4")
      (value "TPB1,27")
      (footprint "eagle-import:B1,27")
      (libsource (lib "eagle-import") (part "TPB1,27"))
    )
  )
  (nets
    (net (code "1") (name "+1V1") (class "Default")
      (node (ref "C192") (pin "1") (pinfunction "1_1") (pintype "passive"))
      (node (ref "C193") (pin "1") (pinfunction "1_1") (pintype "passive"))
      (node (ref "C194") (pin "1") (pinfunction "1_1") (pintype "passive"))
      (node (ref "C26") (pin "1") (pinfunction "1_1") (pintype "passive"))
      (node (ref "C27") (pin "1") (pinfunction "1_1") (pintype "passive"))
      (node (ref "IC26") (pin "10") (pinfunction "DVDD1_10") (pintype "power_in"))
      (node (ref "IC26") (pin "32") (pinfunction "DVDD2_32") (pintype "power_in"))
      (node (ref "IC26") (pin "51") (pinfunction "DVDD3_51") (pintype "power_in"))
      (node (ref "IC26") (pin "65") (pinfunction "VREG_FB_65") (pintype "input"))
      (node (ref "IC26") (pin "68") (pinfunction "USB_OTP_VDD_68") (pintype "power_in"))
      (node (ref "IC26") (pin "69") (pinfunction "QSPI_IOVDD_69") (pintype "power_in"))
      (node (ref "L1") (pin "2") (pinfunction "2_2") (pintype "passive"))
    )
    (net (code "2") (name "+3V3") (class "Default")
      (node (ref "C102") (pin "1") (pinfunction "1_1") (pintype "passive"))
      (node (ref "C127") (pin "1") (pinfunction "1_1") (pintype "passive"))
      (node (ref "C152") (pin "1") (pinfunction "1_1") (pintype "passive"))
      (node (ref "C17") (pin "1") (pinfunction "1_1") (pintype "passive"))
      (node (ref "C176") (pin "1") (pinfunction "1_1") (pintype "passive"))
      (node (ref "C18") (pin "1") (pinfunction "1_1") (pintype "passive"))
      (node (ref "C182") (pin "1") (pinfunction "1_1") (pintype "passive"))
      (node (ref "C183") (pin "1") (pinfunction "1_1") (pintype "passive"))
      (node (ref "C184") (pin "1") (pinfunction "1_1") (pintype "passive"))
      (node (ref "C185") (pin "1") (pinfunction "1_1") (pintype "passive"))
      (node (ref "C186") (pin "1") (pinfunction "1_1") (pintype "passive"))
      (node (ref "C187") (pin "1") (pinfunction "1_1") (pintype "passive"))
      (node (ref "C188") (pin "1") (pinfunction "1_1") (pintype "passive"))
      (node (ref "C189") (pin "1") (pinfunction "1_1") (pintype "passive"))
      (node (ref "C19") (pin "1") (pinfunction "1_1") (pintype "passive"))
      (node (ref "C190") (pin "1") (pinfunction "1_1") (pintype "passive"))
      (node (ref "C195") (pin "1") (pinfunction "1_1") (pintype "passive"))
      (node (ref "C198") (pin "1") (pinfunction "1_1") (pintype "passive"))
      (node (ref "C20") (pin "1") (pinfunction "1_1") (pintype "passive"))
      (node (ref "C212") (pin "1") (pinfunction "1_1") (pintype "passive"))
      (node (ref "C213") (pin "1") (pinfunction "1_1") (pintype "passive"))
      (node (ref "C22") (pin "1") (pinfunction "1_1") (pintype "passive"))
      (node (ref "C221") (pin "1") (pinfunction "1_1") (pintype "passive"))
      (node (ref "C222") (pin "1") (pinfunction "1_1") (pintype "passive"))
      (node (ref "C223") (pin "1") (pinfunction "1_1") (pintype "passive"))
      (node (ref "C23") (pin "1") (pinfunction "1_1") (pintype "passive"))
      (node (ref "C236") (pin "1") (pinfunction "1_1") (pintype "passive"))
      (node (ref "C238") (pin "1") (pinfunction "1_1") (pintype "passive"))
      (node (ref "C239") (pin "1") (pinfunction "1_1") (pintype "passive"))
      (node (ref "C24") (pin "1") (pinfunction "1_1") (pintype "passive"))
      (node (ref "C246") (pin "1") (pinfunction "1_1") (pintype "passive"))
      (node (ref "C249") (pin "1") (pinfunction "1_1") (pintype "passive"))
      (node (ref "C25") (pin "1") (pinfunction "1_1") (pintype "passive"))
      (node (ref "C251") (pin "1") (pinfunction "1_1") (pintype "passive"))
      (node (ref "C283") (pin "1") (pinfunction "1_1") (pintype "passive"))
      (node (ref "C291") (pin "1") (pinfunction "1_1") (pintype "passive"))
      (node (ref "C55") (pin "1") (pinfunction "1_1") (pintype "passive"))
      (node (ref "C73") (pin "1") (pinfunction "1_1") (pintype "passive"))
      (node (ref "D1") (pin "A") (pinfunction "A_A") (pintype "passive"))
      (node (ref "D12") (pin "5") (pinfunction "5_5") (pintype "power_in"))
      (node (ref "D13") (pin "5") (pinfunction "5_5") (pintype "power_in"))
      (node (ref "D3") (pin "A") (pinfunction "A_A") (pintype "passive"))
      (node (ref "D5") (pin "A") (pinfunction "A_A") (pintype "passive"))
      (node (ref "D7") (pin "A") (pinfunction "A_A") (pintype "passive"))
      (node (ref "DISP") (pin "1") (pinfunction "1_1") (pintype "bidirectional"))
      (node (ref "DISP") (pin "2") (pinfunction "2_2") (pintype "bidirectional"))
      (node (ref "ETH1") (pin "10") (pinfunction "GREEN+_10") (pintype "passive"))
      (node (ref "ETH1") (pin "12") (pinfunction "YELLOW+_12") (pintype "passive"))
      (node (ref "IC11") (pin "4") (pinfunction "VCC_4") (pintype "bidirectional"))
      (node (ref "IC11") (pin "7") (pinfunction "A0_7") (pintype "bidirectional"))
      (node (ref "IC13") (pin "4") (pinfunction "VCC_4") (pintype "bidirectional"))
      (node (ref "IC16") (pin "4") (pinfunction "VCC_4") (pintype "bidirectional"))
      (node (ref "IC16") (pin "8") (pinfunction "A1_8") (pintype "bidirectional"))
      (node (ref "IC19") (pin "4") (pinfunction "VCC_4") (pintype "bidirectional"))
      (node (ref "IC19") (pin "7") (pinfunction "A0_7") (pintype "bidirectional"))
      (node (ref "IC19") (pin "8") (pinfunction "A1_8") (pintype "bidirectional"))
      (node (ref "IC22") (pin "4") (pinfunction "VCC_4") (pintype "bidirectional"))
      (node (ref "IC25") (pin "4") (pinfunction "VCC_4") (pintype "bidirectional"))
      (node (ref "IC25") (pin "7") (pinfunction "A0_7") (pintype "bidirectional"))
      (node (ref "IC26") (pin "15") (pinfunction "IOVDD2_15") (pintype "power_in"))
      (node (ref "IC26") (pin "24") (pinfunction "IOVDD3_24") (pintype "power_in"))
      (node (ref "IC26") (pin "29") (pinfunction "IOVDD4_29") (pintype "power_in"))
      (node (ref "IC26") (pin "41") (pinfunction "IOVDD5_41") (pintype "power_in"))
      (node (ref "IC26") (pin "5") (pinfunction "IOVDD1_5") (pintype "power_in"))
      (node (ref "IC26") (pin "50") (pinfunction "IOVDD6_50") (pintype "power_in"))
      (node (ref "IC26") (pin "60") (pinfunction "IOVDD7_60") (pintype "power_in"))
      (node (ref "IC26") (pin "64") (pinfunction "VREG_IN_64") (pintype "power_in"))
      (node (ref "IC26") (pin "76") (pinfunction "IOVDD8_76") (pintype "power_in"))
      (node (ref "IC27") (pin "8") (pinfunction "VCC_8") (pintype "power_in"))
      (node (ref "IC28") (pin "2") (pinfunction "V+_2") (pintype "power_in"))
      (node (ref "IC29") (pin "8") (pinfunction "VCC_8") (pintype "power_in"))
      (node (ref "IC31") (pin "28") (pinfunction "VDD_28") (pintype "power_in"))
      (node (ref "IC31") (pin "43") (pinfunction "PMODE2_43") (pintype "input"))
      (node (ref "IC31") (pin "44") (pinfunction "PMODE1_44") (pintype "input"))
      (node (ref "IC31") (pin "45") (pinfunction "PMODE0_45") (pintype "input"))
      (node (ref "IC33") (pin "4") (pinfunction "VCC_4") (pintype "bidirectional"))
      (node (ref "IC33") (pin "8") (pinfunction "A1_8") (pintype "bidirectional"))
      (node (ref "IC36") (pin "4") (pinfunction "VCC_4") (pintype "bidirectional"))
      (node (ref "IC36") (pin "7") (pinfunction "A0_7") (pintype "bidirectional"))
      (node (ref "IC36") (pin "8") (pinfunction "A1_8") (pintype "bidirectional"))
      (node (ref "IC38") (pin "21") (pinfunction "VCC_21") (pintype "power_in"))
      (node (ref "IC39") (pin "8") (pinfunction "VCC_8") (pintype "power_in"))
      (node (ref "IC4") (pin "5") (pinfunction "V+_5") (pintype "bidirectional"))
      (node (ref "IC42") (pin "5") (pinfunction "VDD_5") (pintype "bidirectional"))
      (node (ref "IC5") (pin "5") (pinfunction "V+_5") (pintype "bidirectional"))
      (node (ref "IC6") (pin "5") (pinfunction "V+_5") (pintype "bidirectional"))
      (node (ref "IC7") (pin "5") (pinfunction "V+_5") (pintype "bidirectional"))
      (node (ref "JTAG") (pin "1") (pinfunction "1_1") (pintype "passive"))
      (node (ref "L10") (pin "1") (pinfunction "1_1") (pintype "passive"))
      (node (ref "L11") (pin "2") (pinfunction "2_2") (pintype "passive"))
      (node (ref "R1") (pin "1") (pinfunction "1_1") (pintype "passive"))
      (node (ref "R10") (pin "1") (pinfunction "1_1") (pintype "passive"))
      (node (ref "R124") (pin "2") (pinfunction "2_2") (pintype "passive"))
      (node (ref "R13") (pin "2") (pinfunction "2_2") (pintype "passive"))
      (node (ref "R16") (pin "2") (pinfunction "2_2") (pintype "passive"))
      (node (ref "R176") (pin "2") (pinfunction "2_2") (pintype "passive"))
      (node (ref "R19") (pin "2") (pinfunction "2_2") (pintype "passive"))
      (node (ref "R206") (pin "2") (pinfunction "2_2") (pintype "passive"))
      (node (ref "R207") (pin "A2") (pinfunction "8_A2") (pintype "passive"))
      (node (ref "R207") (pin "B2") (pinfunction "7_B2") (pintype "passive"))
      (node (ref "R207") (pin "C2") (pinfunction "6_C2") (pintype "passive"))
      (node (ref "R207") (pin "D2") (pinfunction "5_D2") (pintype "passive"))
      (node (ref "R209") (pin "2") (pinfunction "2_2") (pintype "passive"))
      (node (ref "R212") (pin "2") (pinfunction "2_2") (pintype "passive"))
      (node (ref "R213") (pin "2") (pinfunction "2_2") (pintype "passive"))
      (node (ref "R215") (pin "A2") (pinfunction "8_A2") (pintype "passive"))
      (node (ref "R215") (pin "B2") (pinfunction "7_B2") (pintype "passive"))
      (node (ref "R215") (pin "C2") (pinfunction "6_C2") (pintype "passive"))
      (node (ref "R215") (pin "D2") (pinfunction "5_D2") (pintype "passive"))
      (node (ref "R216") (pin "A2") (pinfunction "8_A2") (pintype "passive"))
      (node (ref "R216") (pin "B2") (pinfunction "7_B2") (pintype "passive"))
      (node (ref "R216") (pin "C2") (pinfunction "6_C2") (pintype "passive"))
      (node (ref "R216") (pin "D2") (pinfunction "5_D2") (pintype "passive"))
      (node (ref "R217") (pin "A2") (pinfunction "8_A2") (pintype "passive"))
      (node (ref "R217") (pin "B2") (pinfunction "7_B2") (pintype "passive"))
      (node (ref "R217") (pin "C2") (pinfunction "6_C2") (pintype "passive"))
      (node (ref "R217") (pin "D2") (pinfunction "5_D2") (pintype "passive"))
      (node (ref "R22") (pin "2") (pinfunction "2_2") (pintype "passive"))
      (node (ref "R226") (pin "2") (pinfunction "2_2") (pintype "passive"))
      (node (ref "R227") (pin "2") (pinfunction "2_2") (pintype "passive"))
      (node (ref "R24") (pin "1") (pinfunction "1_1") (pintype "passive"))
      (node (ref "R252") (pin "2") (pinfunction "2_2") (pintype "passive"))
      (node (ref "R258") (pin "2") (pinfunction "2_2") (pintype "passive"))
      (node (ref "R27") (pin "1") (pinfunction "1_1") (pintype "passive"))
      (node (ref "R278") (pin "2") (pinfunction "2_2") (pintype "passive"))
      (node (ref "R29") (pin "1") (pinfunction "1_1") (pintype "passive"))
      (node (ref "R4") (pin "1") (pinfunction "1_1") (pintype "passive"))
      (node (ref "R7") (pin "1") (pinfunction "1_1") (pintype "passive"))
      (node (ref "R71") (pin "2") (pinfunction "2_2") (pintype "passive"))
      (node (ref "RFB3") (pin "1") (pinfunction "1_1") (pintype "passive"))
      (node (ref "VO3") (pin "TP") (pinfunction "P$1_TP") (pintype "bidirectional"))
    )
    (net (code "3") (name "+3V3_A") (class "Default")
      (node (ref "C224") (pin "1") (pinfunction "1_1") (pintype "passive"))
      (node (ref "C225") (pin "1") (pinfunction "1_1") (pintype "passive"))
      (node (ref "C226") (pin "1") (pinfunction "1_1") (pintype "passive"))
      (node (ref "C227") (pin "1") (pinfunction "1_1") (pintype "passive"))
      (node (ref "C228") (pin "1") (pinfunction "1_1") (pintype "passive"))
      (node (ref "C229") (pin "1") (pinfunction "1_1") (pintype "passive"))
      (node (ref "IC31") (pin "11") (pinfunction "AVDD_11") (pintype "power_in"))
      (node (ref "IC31") (pin "15") (pinfunction "AVDD_15") (pintype "power_in"))
      (node (ref "IC31") (pin "17") (pinfunction "AVDD_17") (pintype "power_in"))
      (node (ref "IC31") (pin "21") (pinfunction "AVDD_21") (pintype "power_in"))
      (node (ref "IC31") (pin "4") (pinfunction "AVDD_4") (pintype "power_in"))
      (node (ref "IC31") (pin "8") (pinfunction "AVDD_8") (pintype "power_in"))
      (node (ref "L10") (pin "2") (pinfunction "2_2") (pintype "passive"))
      (node (ref "R208") (pin "2") (pinfunction "2_2") (pintype "passive"))
      (node (ref "R35") (pin "2") (pinfunction "2_2") (pintype "passive"))
      (node (ref "R43") (pin "2") (pinfunction "2_2") (pintype "passive"))
      (node (ref "R44") (pin "2") (pinfunction "2_2") (pintype "passive"))
    )
    (net (code "4") (name "+5V") (class "Default")
      (node (ref "DISP") (pin "3") (pinfunction "3_3") (pintype "bidirectional"))
      (node (ref "DISP") (pin "4") (pinfunction "4_4") (pintype "bidirectional"))
    )
    (net (code "5") (name "+5VA") (class "Default")
      (node (ref "C2") (pin "1") (pinfunction "1_1") (pintype "passive"))
      (node (ref "C264") (pin "1") (pinfunction "1_1") (pintype "passive"))
      (node (ref "C295") (pin "1") (pinfunction "1_1") (pintype "passive"))
      (node (ref "C297") (pin "1") (pinfunction "1_1") (pintype "passive"))
      (node (ref "C298") (pin "1") (pinfunction "1_1") (pintype "passive"))
      (node (ref "C82") (pin "1") (pinfunction "1_1") (pintype "passive"))
      (node (ref "IC1") (pin "1") (pinfunction "IN_1") (pintype "bidirectional"))
      (node (ref "IC8") (pin "1") (pinfunction "IN_1") (pintype "bidirectional"))
      (node (ref "L12") (pin "2") (pinfunction "2_2") (pintype "passive"))
      (node (ref "R284") (pin "1") (pinfunction "1_1") (pintype "passive"))
      (node (ref "VO5A") (pin "TP") (pinfunction "P$1_TP") (pintype "bidirectional"))
    )
    (net (code "6") (name "+5VB") (class "Default")
      (node (ref "C12") (pin "1") (pinfunction "1_1") (pintype "passive"))
      (node (ref "C278") (pin "1") (pinfunction "1_1") (pintype "passive"))
      (node (ref "C302") (pin "1") (pinfunction "1_1") (pintype "passive"))
      (node (ref "C304") (pin "1") (pinfunction "1_1") (pintype "passive"))
      (node (ref "C7") (pin "1") (pinfunction "1_1") (pintype "passive"))
      (node (ref "IC2") (pin "1") (pinfunction "IN_1") (pintype "bidirectional"))
      (node (ref "IC3") (pin "1") (pinfunction "IN_1") (pintype "bidirectional"))
      (node (ref "L13") (pin "2") (pinfunction "2_2") (pintype "passive"))
      (node (ref "R293") (pin "1") (pinfunction "1_1") (pintype "passive"))
      (node (ref "VO5B") (pin "TP") (pinfunction "P$1_TP") (pintype "bidirectional"))
    )
    (net (code "7") (name "+24V_A") (class "Default")
      (node (ref "C104") (pin "1") (pinfunction "1_1") (pintype "passive"))
      (node (ref "C119") (pin "1") (pinfunction "1_1") (pintype "passive"))
      (node (ref "C120") (pin "1") (pinfunction "1_1") (pintype "passive"))
      (node (ref "C121") (pin "1") (pinfunction "1_1") (pintype "passive"))
      (node (ref "C122") (pin "1") (pinfunction "+_1") (pintype "passive"))
      (node (ref "C129") (pin "1") (pinfunction "1_1") (pintype "passive"))
      (node (ref "C214") (pin "1") (pinfunction "1_1") (pintype "passive"))
      (node (ref "C256") (pin "1") (pinfunction "+_1") (pintype "passive"))
      (node (ref "C257") (pin "1") (pinfunction "+_1") (pintype "passive"))
      (node (ref "C47") (pin "1") (pinfunction "1_1") (pintype "passive"))
      (node (ref "C48") (pin "1") (pinfunction "1_1") (pintype "passive"))
      (node (ref "C49") (pin "1") (pinfunction "1_1") (pintype "passive"))
      (node (ref "C50") (pin "1") (pinfunction "+_1") (pintype "passive"))
      (node (ref "C65") (pin "1") (pinfunction "1_1") (pintype "passive"))
      (node (ref "C66") (pin "1") (pinfunction "1_1") (pintype "passive"))
      (node (ref "C67") (pin "1") (pinfunction "1_1") (pintype "passive"))
      (node (ref "C68") (pin "1") (pinfunction "+_1") (pintype "passive"))
      (node (ref "C75") (pin "1") (pinfunction "1_1") (pintype "passive"))
      (node (ref "C94") (pin "1") (pinfunction "1_1") (pintype "passive"))
      (node (ref "C95") (pin "1") (pinfunction "1_1") (pintype "passive"))
      (node (ref "C96") (pin "1") (pinfunction "1_1") (pintype "passive"))
      (node (ref "C97") (pin "1") (pinfunction "+_1") (pintype "passive"))
      (node (ref "D11") (pin "C") (pinfunction "C_C") (pintype "passive"))
      (node (ref "F3") (pin "2_1") (pinfunction "2_2_1") (pintype "passive"))
      (node (ref "F3") (pin "2_2") (pinfunction "2_2_2") (pintype "passive"))
      (node (ref "IC10") (pin "3") (pinfunction "VIN_3") (pintype "power_in"))
      (node (ref "IC12") (pin "3") (pinfunction "VIN_3") (pintype "power_in"))
      (node (ref "IC15") (pin "3") (pinfunction "VIN_3") (pintype "power_in"))
      (node (ref "IC18") (pin "3") (pinfunction "VIN_3") (pintype "power_in"))
      (node (ref "T10") (pin "5") (pinfunction "D_5") (pintype "passive"))
      (node (ref "T10") (pin "6") (pinfunction "D_6") (pintype "passive"))
      (node (ref "T10") (pin "7") (pinfunction "D_7") (pintype "passive"))
      (node (ref "T10") (pin "8") (pinfunction "D_8") (pintype "passive"))
      (node (ref "T10") (pin "9") (pinfunction "D_9") (pintype "passive"))
      (node (ref "T15") (pin "5") (pinfunction "D_5") (pintype "passive"))
      (node (ref "T15") (pin "6") (pinfunction "D_6") (pintype "passive"))
      (node (ref "T15") (pin "7") (pinfunction "D_7") (pintype "passive"))
      (node (ref "T15") (pin "8") (pinfunction "D_8") (pintype "passive"))
      (node (ref "T15") (pin "9") (pinfunction "D_9") (pintype "passive"))
      (node (ref "T20") (pin "5") (pinfunction "D_5") (pintype "passive"))
      (node (ref "T20") (pin "6") (pinfunction "D_6") (pintype "passive"))
      (node (ref "T20") (pin "7") (pinfunction "D_7") (pintype "passive"))
      (node (ref "T20") (pin "8") (pinfunction "D_8") (pintype "passive"))
      (node (ref "T20") (pin "9") (pinfunction "D_9") (pintype "passive"))
      (node (ref "T5") (pin "5") (pinfunction "D_5") (pintype "passive"))
      (node (ref "T5") (pin "6") (pinfunction "D_6") (pintype "passive"))
      (node (ref "T5") (pin "7") (pinfunction "D_7") (pintype "passive"))
      (node (ref "T5") (pin "8") (pinfunction "D_8") (pintype "passive"))
      (node (ref "T5") (pin "9") (pinfunction "D_9") (pintype "passive"))
    )
    (net (code "8") (name "+24V_B") (class "Default")
      (node (ref "C144") (pin "1") (pinfunction "1_1") (pintype "passive"))
      (node (ref "C145") (pin "1") (pinfunction "1_1") (pintype "passive"))
      (node (ref "C146") (pin "1") (pinfunction "1_1") (pintype "passive"))
      (node (ref "C147") (pin "1") (pinfunction "+_1") (pintype "passive"))
      (node (ref "C154") (pin "1") (pinfunction "1_1") (pintype "passive"))
      (node (ref "C169") (pin "1") (pinfunction "1_1") (pintype "passive"))
      (node (ref "C170") (pin "1") (pinfunction "1_1") (pintype "passive"))
      (node (ref "C171") (pin "1") (pinfunction "1_1") (pintype "passive"))
      (node (ref "C172") (pin "1") (pinfunction "+_1") (pintype "passive"))
      (node (ref "C200") (pin "1") (pinfunction "1_1") (pintype "passive"))
      (node (ref "C231") (pin "1") (pinfunction "1_1") (pintype "passive"))
      (node (ref "C232") (pin "1") (pinfunction "1_1") (pintype "passive"))
      (node (ref "C240") (pin "1") (pinfunction "1_1") (pintype "passive"))
      (node (ref "C241") (pin "1") (pinfunction "+_1") (pintype "passive"))
      (node (ref "C254") (pin "1") (pinfunction "+_1") (pintype "passive"))
      (node (ref "C255") (pin "1") (pinfunction "+_1") (pintype "passive"))
      (node (ref "C258") (pin "1") (pinfunction "1_1") (pintype "passive"))
      (node (ref "C274") (pin "1") (pinfunction "1_1") (pintype "passive"))
      (node (ref "C275") (pin "1") (pinfunction "1_1") (pintype "passive"))
      (node (ref "C276") (pin "1") (pinfunction "1_1") (pintype "passive"))
      (node (ref "C277") (pin "1") (pinfunction "+_1") (pintype "passive"))
      (node (ref "C285") (pin "1") (pinfunction "1_1") (pintype "passive"))
      (node (ref "D10") (pin "C") (pinfunction "C_C") (pintype "passive"))
      (node (ref "F2") (pin "2_1") (pinfunction "2_2_1") (pintype "passive"))
      (node (ref "F2") (pin "2_2") (pinfunction "2_2_2") (pintype "passive"))
      (node (ref "IC21") (pin "3") (pinfunction "VIN_3") (pintype "power_in"))
      (node (ref "IC24") (pin "3") (pinfunction "VIN_3") (pintype "power_in"))
      (node (ref "IC32") (pin "3") (pinfunction "VIN_3") (pintype "power_in"))
      (node (ref "IC35") (pin "3") (pinfunction "VIN_3") (pintype "power_in"))
      (node (ref "T25") (pin "5") (pinfunction "D_5") (pintype "passive"))
      (node (ref "T25") (pin "6") (pinfunction "D_6") (pintype "passive"))
      (node (ref "T25") (pin "7") (pinfunction "D_7") (pintype "passive"))
      (node (ref "T25") (pin "8") (pinfunction "D_8") (pintype "passive"))
      (node (ref "T25") (pin "9") (pinfunction "D_9") (pintype "passive"))
      (node (ref "T30") (pin "5") (pinfunction "D_5") (pintype "passive"))
      (node (ref "T30") (pin "6") (pinfunction "D_6") (pintype "passive"))
      (node (ref "T30") (pin "7") (pinfunction "D_7") (pintype "passive"))
      (node (ref "T30") (pin "8") (pinfunction "D_8") (pintype "passive"))
      (node (ref "T30") (pin "9") (pinfunction "D_9") (pintype "passive"))
      (node (ref "T35") (pin "5") (pinfunction "D_5") (pintype "passive"))
      (node (ref "T35") (pin "6") (pinfunction "D_6") (pintype "passive"))
      (node (ref "T35") (pin "7") (pinfunction "D_7") (pintype "passive"))
      (node (ref "T35") (pin "8") (pinfunction "D_8") (pintype "passive"))
      (node (ref "T35") (pin "9") (pinfunction "D_9") (pintype "passive"))
      (node (ref "T40") (pin "5") (pinfunction "D_5") (pintype "passive"))
      (node (ref "T40") (pin "6") (pinfunction "D_6") (pintype "passive"))
      (node (ref "T40") (pin "7") (pinfunction "D_7") (pintype "passive"))
      (node (ref "T40") (pin "8") (pinfunction "D_8") (pintype "passive"))
      (node (ref "T40") (pin "9") (pinfunction "D_9") (pintype "passive"))
    )
    (net (code "9") (name "+24V_C") (class "Default")
      (node (ref "C233") (pin "1") (pinfunction "1_1") (pintype "passive"))
      (node (ref "C237") (pin "1") (pinfunction "1_1") (pintype "passive"))
      (node (ref "C252") (pin "1") (pinfunction "+_1") (pintype "passive"))
      (node (ref "C253") (pin "1") (pinfunction "+_1") (pintype "passive"))
      (node (ref "C292") (pin "1") (pinfunction "1_1") (pintype "passive"))
      (node (ref "C296") (pin "1") (pinfunction "1_1") (pintype "passive"))
      (node (ref "C299") (pin "1") (pinfunction "1_1") (pintype "passive"))
      (node (ref "C303") (pin "1") (pinfunction "1_1") (pintype "passive"))
      (node (ref "D9") (pin "C") (pinfunction "C_C") (pintype "passive"))
      (node (ref "F1") (pin "2_1") (pinfunction "2_2_1") (pintype "passive"))
      (node (ref "F1") (pin "2_2") (pinfunction "2_2_2") (pintype "passive"))
      (node (ref "IC40") (pin "2") (pinfunction "IN_2") (pintype "bidirectional"))
      (node (ref "IC41") (pin "2") (pinfunction "IN_2") (pintype "bidirectional"))
      (node (ref "IC43") (pin "2") (pinfunction "IN_2") (pintype "bidirectional"))
      (node (ref "R241") (pin "1") (pinfunction "1_1") (pintype "passive"))
      (node (ref "R289") (pin "2") (pinfunction "2_2") (pintype "passive"))
      (node (ref "R298") (pin "2") (pinfunction "2_2") (pintype "passive"))
    )
    (net (code "10") (name "5V_EN") (class "Default")
      (node (ref "IC41") (pin "6") (pinfunction "EN_6") (pintype "bidirectional"))
      (node (ref "IC43") (pin "6") (pinfunction "EN_6") (pintype "bidirectional"))
      (node (ref "R287") (pin "2") (pinfunction "2_2") (pintype "passive"))
      (node (ref "R289") (pin "1") (pinfunction "1_1") (pintype "passive"))
      (node (ref "R296") (pin "2") (pinfunction "2_2") (pintype "passive"))
      (node (ref "R298") (pin "1") (pinfunction "1_1") (pintype "passive"))
    )
    (net (code "11") (name "ADC_3VA") (class "Default")
      (node (ref "R208") (pin "1") (pinfunction "1_1") (pintype "passive"))
      (node (ref "R225") (pin "2") (pinfunction "2_2") (pintype "passive"))
    )
    (net (code "12") (name "ADC_VUSB") (class "Default")
      (node (ref "C29") (pin "1") (pinfunction "1_1") (pintype "passive"))
      (node (ref "R31") (pin "2") (pinfunction "2_2") (pintype "passive"))
      (node (ref "R32") (pin "1") (pinfunction "1_1") (pintype "passive"))
    )
    (net (code "13") (name "AVDD") (class "Default")
      (node (ref "AVDD") (pin "TP") (pinfunction "P$1_TP") (pintype "bidirectional"))
      (node (ref "C181") (pin "1") (pinfunction "1_1") (pintype "passive"))
      (node (ref "IC28") (pin "1") (pinfunction "OUT_1") (pintype "output"))
      (node (ref "IC28") (pin "4") (pinfunction "-IN_4") (pintype "input"))
      (node (ref "R28") (pin "2") (pinfunction "2_2") (pintype "passive"))
    )
    (net (code "14") (name "CC1_PORT1") (class "Default")
      (node (ref "IC9") (pin "2") (pinfunction "CC1_2") (pintype "bidirectional"))
      (node (ref "PORT1") (pin "A5") (pinfunction "CC1_A5") (pintype "passive"))
    )
    (net (code "15") (name "CC1_PORT2") (class "Default")
      (node (ref "IC14") (pin "2") (pinfunction "CC1_2") (pintype "bidirectional"))
      (node (ref "PORT2") (pin "A5") (pinfunction "CC1_A5") (pintype "passive"))
    )
    (net (code "16") (name "CC1_PORT3") (class "Default")
      (node (ref "IC17") (pin "2") (pinfunction "CC1_2") (pintype "bidirectional"))
      (node (ref "PORT3") (pin "A5") (pinfunction "CC1_A5") (pintype "passive"))
    )
    (net (code "17") (name "CC1_PORT4") (class "Default")
      (node (ref "IC20") (pin "2") (pinfunction "CC1_2") (pintype "bidirectional"))
      (node (ref "PORT4") (pin "A5") (pinfunction "CC1_A5") (pintype "passive"))
    )
    (net (code "18") (name "CC1_PORT5") (class "Default")
      (node (ref "IC23") (pin "2") (pinfunction "CC1_2") (pintype "bidirectional"))
      (node (ref "PORT5") (pin "A5") (pinfunction "CC1_A5") (pintype "passive"))
    )
    (net (code "19") (name "CC1_PORT6") (class "Default")
      (node (ref "IC30") (pin "2") (pinfunction "CC1_2") (pintype "bidirectional"))
      (node (ref "PORT6") (pin "A5") (pinfunction "CC1_A5") (pintype "passive"))
    )
    (net (code "20") (name "CC1_PORT7") (class "Default")
      (node (ref "IC34") (pin "2") (pinfunction "CC1_2") (pintype "bidirectional"))
      (node (ref "PORT7") (pin "A5") (pinfunction "CC1_A5") (pintype "passive"))
    )
    (net (code "21") (name "CC1_PORT8") (class "Default")
      (node (ref "IC37") (pin "2") (pinfunction "CC1_2") (pintype "bidirectional"))
      (node (ref "PORT8") (pin "A5") (pinfunction "CC1_A5") (pintype "passive"))
    )
    (net (code "22") (name "CC2_PORT1") (class "Default")
      (node (ref "IC9") (pin "3") (pinfunction "CC2_3") (pintype "bidirectional"))
      (node (ref "PORT1") (pin "B5") (pinfunction "CC2_B5") (pintype "passive"))
    )
    (net (code "23") (name "CC2_PORT2") (class "Default")
      (node (ref "IC14") (pin "3") (pinfunction "CC2_3") (pintype "bidirectional"))
      (node (ref "PORT2") (pin "B5") (pinfunction "CC2_B5") (pintype "passive"))
    )
    (net (code "24") (name "CC2_PORT3") (class "Default")
      (node (ref "IC17") (pin "3") (pinfunction "CC2_3") (pintype "bidirectional"))
      (node (ref "PORT3") (pin "B5") (pinfunction "CC2_B5") (pintype "passive"))
    )
    (net (code "25") (name "CC2_PORT4") (class "Default")
      (node (ref "IC20") (pin "3") (pinfunction "CC2_3") (pintype "bidirectional"))
      (node (ref "PORT4") (pin "B5") (pinfunction "CC2_B5") (pintype "passive"))
    )
    (net (code "26") (name "CC2_PORT5") (class "Default")
      (node (ref "IC23") (pin "3") (pinfunction "CC2_3") (pintype "bidirectional"))
      (node (ref "PORT5") (pin "B5") (pinfunction "CC2_B5") (pintype "passive"))
    )
    (net (code "27") (name "CC2_PORT6") (class "Default")
      (node (ref "IC30") (pin "3") (pinfunction "CC2_3") (pintype "bidirectional"))
      (node (ref "PORT6") (pin "B5") (pinfunction "CC2_B5") (pintype "passive"))
    )
    (net (code "28") (name "CC2_PORT7") (class "Default")
      (node (ref "IC34") (pin "3") (pinfunction "CC2_3") (pintype "bidirectional"))
      (node (ref "PORT7") (pin "B5") (pinfunction "CC2_B5") (pintype "passive"))
    )
    (net (code "29") (name "CC2_PORT8") (class "Default")
      (node (ref "IC37") (pin "3") (pinfunction "CC2_3") (pintype "bidirectional"))
      (node (ref "PORT8") (pin "B5") (pinfunction "CC2_B5") (pintype "passive"))
    )
    (net (code "30") (name "EN_PORT1") (class "Default")
      (node (ref "IC12") (pin "4") (pinfunction "EN_4") (pintype "input"))
      (node (ref "IC42") (pin "25") (pinfunction "IO2.0_25") (pintype "bidirectional"))
      (node (ref "R230") (pin "1") (pinfunction "1_1") (pintype "passive"))
    )
    (net (code "31") (name "EN_PORT2") (class "Default")
      (node (ref "IC10") (pin "4") (pinfunction "EN_4") (pintype "input"))
      (node (ref "IC42") (pin "26") (pinfunction "IO2.1_26") (pintype "bidirectional"))
      (node (ref "R88") (pin "1") (pinfunction "1_1") (pintype "passive"))
    )
    (net (code "32") (name "EN_PORT3") (class "Default")
      (node (ref "IC15") (pin "4") (pinfunction "EN_4") (pintype "input"))
      (node (ref "IC42") (pin "27") (pinfunction "IO2.2_27") (pintype "bidirectional"))
      (node (ref "R114") (pin "1") (pinfunction "1_1") (pintype "passive"))
    )
    (net (code "33") (name "EN_PORT4") (class "Default")
      (node (ref "IC18") (pin "4") (pinfunction "EN_4") (pintype "input"))
      (node (ref "IC42") (pin "28") (pinfunction "IO2.3_28") (pintype "bidirectional"))
      (node (ref "R140") (pin "1") (pinfunction "1_1") (pintype "passive"))
    )
    (net (code "34") (name "EN_PORT5") (class "Default")
      (node (ref "IC21") (pin "4") (pinfunction "EN_4") (pintype "input"))
      (node (ref "IC42") (pin "1") (pinfunction "IO2.4_1") (pintype "bidirectional"))
      (node (ref "R166") (pin "1") (pinfunction "1_1") (pintype "passive"))
    )
    (net (code "35") (name "EN_PORT6") (class "Default")
      (node (ref "IC24") (pin "4") (pinfunction "EN_4") (pintype "input"))
      (node (ref "IC42") (pin "2") (pinfunction "IO2.5_2") (pintype "bidirectional"))
      (node (ref "R192") (pin "1") (pinfunction "1_1") (pintype "passive"))
    )
    (net (code "36") (name "EN_PORT7") (class "Default")
      (node (ref "IC32") (pin "4") (pinfunction "EN_4") (pintype "input"))
      (node (ref "IC42") (pin "3") (pinfunction "IO2.6_3") (pintype "bidirectional"))
      (node (ref "R239") (pin "1") (pinfunction "1_1") (pintype "passive"))
    )
    (net (code "37") (name "EN_PORT8") (class "Default")
      (node (ref "IC35") (pin "4") (pinfunction "EN_4") (pintype "input"))
      (node (ref "IC42") (pin "4") (pinfunction "IO2.7_4") (pintype "bidirectional"))
      (node (ref "R274") (pin "1") (pinfunction "1_1") (pintype "passive"))
    )
    (net (code "38") (name "GND") (class "Default")
      (node (ref "C1") (pin "2") (pinfunction "2_2") (pintype "passive"))
      (node (ref "C10") (pin "2") (pinfunction "-_2") (pintype "passive"))
      (node (ref "C100") (pin "2") (pinfunction "2_2") (pintype "passive"))
      (node (ref "C101") (pin "2") (pinfunction "2_2") (pintype "passive"))
      (node (ref "C102") (pin "2") (pinfunction "2_2") (pintype "passive"))
      (node (ref "C104") (pin "2") (pinfunction "2_2") (pintype "passive"))
      (node (ref "C105") (pin "2") (pinfunction "2_2") (pintype "passive"))
      (node (ref "C106") (pin "2") (pinfunction "2_2") (pintype "passive"))
      (node (ref "C107") (pin "2") (pinfunction "2_2") (pintype "passive"))
      (node (ref "C108") (pin "2") (pinfunction "-_2") (pintype "passive"))
      (node (ref "C109") (pin "1") (pinfunction "1_1") (pintype "passive"))
      (node (ref "C11") (pin "2") (pinfunction "2_2") (pintype "passive"))
      (node (ref "C110") (pin "2") (pinfunction "2_2") (pintype "passive"))
      (node (ref "C111") (pin "2") (pinfunction "2_2") (pintype "passive"))
      (node (ref "C112") (pin "2") (pinfunction "2_2") (pintype "passive"))
      (node (ref "C113") (pin "2") (pinfunction "2_2") (pintype "passive"))
      (node (ref "C114") (pin "2") (pinfunction "2_2") (pintype "passive"))
      (node (ref "C115") (pin "2") (pinfunction "2_2") (pintype "passive"))
      (node (ref "C116") (pin "2") (pinfunction "2_2") (pintype "passive"))
      (node (ref "C119") (pin "2") (pinfunction "2_2") (pintype "passive"))
      (node (ref "C12") (pin "2") (pinfunction "2_2") (pintype "passive"))
      (node (ref "C120") (pin "2") (pinfunction "2_2") (pintype "passive"))
      (node (ref "C121") (pin "2") (pinfunction "2_2") (pintype "passive"))
      (node (ref "C122") (pin "2") (pinfunction "-_2") (pintype "passive"))
      (node (ref "C123") (pin "2") (pinfunction "2_2") (pintype "passive"))
      (node (ref "C124") (pin "2") (pinfunction "2_2") (pintype "passive"))
      (node (ref "C125") (pin "2") (pinfunction "2_2") (pintype "passive"))
      (node (ref "C126") (pin "2") (pinfunction "2_2") (pintype "passive"))
      (node (ref "C127") (pin "2") (pinfunction "2_2") (pintype "passive"))
      (node (ref "C129") (pin "2") (pinfunction "2_2") (pintype "passive"))
      (node (ref "C13") (pin "2") (pinfunction "2_2") (pintype "passive"))
      (node (ref "C130") (pin "2") (pinfunction "2_2") (pintype "passive"))
      (node (ref "C131") (pin "2") (pinfunction "2_2") (pintype "passive"))
      (node (ref "C132") (pin "2") (pinfunction "2_2") (pintype "passive"))
      (node (ref "C133") (pin "2") (pinfunction "-_2") (pintype "passive"))
      (node (ref "C134") (pin "1") (pinfunction "1_1") (pintype "passive"))
      (node (ref "C135") (pin "2") (pinfunction "2_2") (pintype "passive"))
      (node (ref "C136") (pin "2") (pinfunction "2_2") (pintype "passive"))
      (node (ref "C137") (pin "2") (pinfunction "2_2") (pintype "passive"))
      (node (ref "C138") (pin "2") (pinfunction "2_2") (pintype "passive"))
      (node (ref "C139") (pin "2") (pinfunction "2_2") (pintype "passive"))
      (node (ref "C14") (pin "2") (pinfunction "2_2") (pintype "passive"))
      (node (ref "C140") (pin "2") (pinfunction "2_2") (pintype "passive"))
      (node (ref "C141") (pin "2") (pinfunction "2_2") (pintype "passive"))
      (node (ref "C144") (pin "2") (pinfunction "2_2") (pintype "passive"))
      (node (ref "C145") (pin "2") (pinfunction "2_2") (pintype "passive"))
      (node (ref "C146") (pin "2") (pinfunction "2_2") (pintype "passive"))
      (node (ref "C147") (pin "2") (pinfunction "-_2") (pintype "passive"))
      (node (ref "C148") (pin "2") (pinfunction "2_2") (pintype "passive"))
      (node (ref "C149") (pin "2") (pinfunction "2_2") (pintype "passive"))
      (node (ref "C15") (pin "2") (pinfunction "-_2") (pintype "passive"))
      (node (ref "C150") (pin "2") (pinfunction "2_2") (pintype "passive"))
      (node (ref "C151") (pin "2") (pinfunction "2_2") (pintype "passive"))
      (node (ref "C152") (pin "2") (pinfunction "2_2") (pintype "passive"))
      (node (ref "C154") (pin "2") (pinfunction "2_2") (pintype "passive"))
      (node (ref "C155") (pin "2") (pinfunction "2_2") (pintype "passive"))
      (node (ref "C156") (pin "2") (pinfunction "2_2") (pintype "passive"))
      (node (ref "C157") (pin "2") (pinfunction "2_2") (pintype "passive"))
      (node (ref "C158") (pin "2") (pinfunction "-_2") (pintype "passive"))
      (node (ref "C159") (pin "1") (pinfunction "1_1") (pintype "passive"))
      (node (ref "C16") (pin "2") (pinfunction "2_2") (pintype "passive"))
      (node (ref "C160") (pin "2") (pinfunction "2_2") (pintype "passive"))
      (node (ref "C161") (pin "2") (pinfunction "2_2") (pintype "passive"))
      (node (ref "C162") (pin "2") (pinfunction "2_2") (pintype "passive"))
      (node (ref "C163") (pin "2") (pinfunction "2_2") (pintype "passive"))
      (node (ref "C164") (pin "2") (pinfunction "2_2") (pintype "passive"))
      (node (ref "C165") (pin "2") (pinfunction "2_2") (pintype "passive"))
      (node (ref "C166") (pin "2") (pinfunction "2_2") (pintype "passive"))
      (node (ref "C169") (pin "2") (pinfunction "2_2") (pintype "passive"))
      (node (ref "C17") (pin "2") (pinfunction "2_2") (pintype "passive"))
      (node (ref "C170") (pin "2") (pinfunction "2_2") (pintype "passive"))
      (node (ref "C171") (pin "2") (pinfunction "2_2") (pintype "passive"))
      (node (ref "C172") (pin "2") (pinfunction "-_2") (pintype "passive"))
      (node (ref "C173") (pin "2") (pinfunction "2_2") (pintype "passive"))
      (node (ref "C174") (pin "2") (pinfunction "2_2") (pintype "passive"))
      (node (ref "C175") (pin "2") (pinfunction "2_2") (pintype "passive"))
      (node (ref "C176") (pin "2") (pinfunction "2_2") (pintype "passive"))
      (node (ref "C177") (pin "2") (pinfunction "2_2") (pintype "passive"))
      (node (ref "C178") (pin "2") (pinfunction "2_2") (pintype "passive"))
      (node (ref "C179") (pin "2") (pinfunction "2_2") (pintype "passive"))
      (node (ref "C18") (pin "2") (pinfunction "2_2") (pintype "passive"))
      (node (ref "C180") (pin "2") (pinfunction "2_2") (pintype "passive"))
      (node (ref "C181") (pin "2") (pinfunction "2_2") (pintype "passive"))
      (node (ref "C182") (pin "2") (pinfunction "2_2") (pintype "passive"))
      (node (ref "C183") (pin "2") (pinfunction "2_2") (pintype "passive"))
      (node (ref "C184") (pin "2") (pinfunction "2_2") (pintype "passive"))
      (node (ref "C185") (pin "2") (pinfunction "2_2") (pintype "passive"))
      (node (ref "C186") (pin "2") (pinfunction "2_2") (pintype "passive"))
      (node (ref "C187") (pin "2") (pinfunction "2_2") (pintype "passive"))
      (node (ref "C188") (pin "2") (pinfunction "2_2") (pintype "passive"))
      (node (ref "C189") (pin "2") (pinfunction "2_2") (pintype "passive"))
      (node (ref "C19") (pin "2") (pinfunction "2_2") (pintype "passive"))
      (node (ref "C190") (pin "2") (pinfunction "2_2") (pintype "passive"))
      (node (ref "C191") (pin "2") (pinfunction "2_2") (pintype "passive"))
      (node (ref "C192") (pin "2") (pinfunction "2_2") (pintype "passive"))
      (node (ref "C193") (pin "2") (pinfunction "2_2") (pintype "passive"))
      (node (ref "C194") (pin "2") (pinfunction "2_2") (pintype "passive"))
      (node (ref "C195") (pin "2") (pinfunction "2_2") (pintype "passive"))
      (node (ref "C197") (pin "2") (pinfunction "2_2") (pintype "passive"))
      (node (ref "C198") (pin "2") (pinfunction "2_2") (pintype "passive"))
      (node (ref "C2") (pin "2") (pinfunction "2_2") (pintype "passive"))
      (node (ref "C20") (pin "2") (pinfunction "2_2") (pintype "passive"))
      (node (ref "C200") (pin "2") (pinfunction "2_2") (pintype "passive"))
      (node (ref "C201") (pin "2") (pinfunction "2_2") (pintype "passive"))
      (node (ref "C202") (pin "2") (pinfunction "2_2") (pintype "passive"))
      (node (ref "C203") (pin "2") (pinfunction "2_2") (pintype "passive"))
      (node (ref "C204") (pin "2") (pinfunction "-_2") (pintype "passive"))
      (node (ref "C205") (pin "1") (pinfunction "1_1") (pintype "passive"))
      (node (ref "C206") (pin "2") (pinfunction "2_2") (pintype "passive"))
      (node (ref "C207") (pin "2") (pinfunction "2_2") (pintype "passive"))
      (node (ref "C208") (pin "2") (pinfunction "2_2") (pintype "passive"))
      (node (ref "C209") (pin "2") (pinfunction "2_2") (pintype "passive"))
      (node (ref "C21") (pin "2") (pinfunction "2_2") (pintype "passive"))
      (node (ref "C210") (pin "2") (pinfunction "2_2") (pintype "passive"))
      (node (ref "C211") (pin "2") (pinfunction "2_2") (pintype "passive"))
      (node (ref "C212") (pin "2") (pinfunction "2_2") (pintype "passive"))
      (node (ref "C213") (pin "2") (pinfunction "2_2") (pintype "passive"))
      (node (ref "C214") (pin "2") (pinfunction "2_2") (pintype "passive"))
      (node (ref "C215") (pin "2") (pinfunction "2_2") (pintype "passive"))
      (node (ref "C216") (pin "2") (pinfunction "2_2") (pintype "passive"))
      (node (ref "C217") (pin "2") (pinfunction "2_2") (pintype "passive"))
      (node (ref "C218") (pin "2") (pinfunction "-_2") (pintype "passive"))
      (node (ref "C219") (pin "2") (pinfunction "2_2") (pintype "passive"))
      (node (ref "C22") (pin "2") (pinfunction "2_2") (pintype "passive"))
      (node (ref "C221") (pin "2") (pinfunction "2_2") (pintype "passive"))
      (node (ref "C222") (pin "2") (pinfunction "2_2") (pintype "passive"))
      (node (ref "C223") (pin "2") (pinfunction "2_2") (pintype "passive"))
      (node (ref "C224") (pin "2") (pinfunction "2_2") (pintype "passive"))
      (node (ref "C225") (pin "2") (pinfunction "2_2") (pintype "passive"))
      (node (ref "C226") (pin "2") (pinfunction "2_2") (pintype "passive"))
      (node (ref "C227") (pin "2") (pinfunction "2_2") (pintype "passive"))
      (node (ref "C228") (pin "2") (pinfunction "2_2") (pintype "passive"))
      (node (ref "C229") (pin "2") (pinfunction "2_2") (pintype "passive"))
      (node (ref "C23") (pin "2") (pinfunction "2_2") (pintype "passive"))
      (node (ref "C231") (pin "2") (pinfunction "2_2") (pintype "passive"))
      (node (ref "C232") (pin "2") (pinfunction "2_2") (pintype "passive"))
      (node (ref "C233") (pin "2") (pinfunction "2_2") (pintype "passive"))
      (node (ref "C234") (pin "2") (pinfunction "2_2") (pintype "passive"))
      (node (ref "C237") (pin "2") (pinfunction "2_2") (pintype "passive"))
      (node (ref "C238") (pin "2") (pinfunction "2_2") (pintype "passive"))
      (node (ref "C239") (pin "2") (pinfunction "2_2") (pintype "passive"))
      (node (ref "C24") (pin "2") (pinfunction "2_2") (pintype "passive"))
      (node (ref "C240") (pin "2") (pinfunction "2_2") (pintype "passive"))
      (node (ref "C241") (pin "2") (pinfunction "-_2") (pintype "passive"))
      (node (ref "C242") (pin "2") (pinfunction "2_2") (pintype "passive"))
      (node (ref "C243") (pin "2") (pinfunction "2_2") (pintype "passive"))
      (node (ref "C244") (pin "2") (pinfunction "2_2") (pintype "passive"))
      (node (ref "C245") (pin "2") (pinfunction "2_2") (pintype "passive"))
      (node (ref "C246") (pin "2") (pinfunction "2_2") (pintype "passive"))
      (node (ref "C247") (pin "2") (pinfunction "2_2") (pintype "passive"))
      (node (ref "C248") (pin "2") (pinfunction "2_2") (pintype "passive"))
      (node (ref "C249") (pin "2") (pinfunction "2_2") (pintype "passive"))
      (node (ref "C25") (pin "2") (pinfunction "2_2") (pintype "passive"))
      (node (ref "C251") (pin "2") (pinfunction "2_2") (pintype "passive"))
      (node (ref "C252") (pin "2") (pinfunction "-_2") (pintype "passive"))
      (node (ref "C253") (pin "2") (pinfunction "-_2") (pintype "passive"))
      (node (ref "C254") (pin "2") (pinfunction "-_2") (pintype "passive"))
      (node (ref "C255") (pin "2") (pinfunction "-_2") (pintype "passive"))
      (node (ref "C256") (pin "2") (pinfunction "-_2") (pintype "passive"))
      (node (ref "C257") (pin "2") (pinfunction "-_2") (pintype "passive"))
      (node (ref "C258") (pin "2") (pinfunction "2_2") (pintype "passive"))
      (node (ref "C259") (pin "2") (pinfunction "2_2") (pintype "passive"))
      (node (ref "C26") (pin "2") (pinfunction "2_2") (pintype "passive"))
      (node (ref "C260") (pin "2") (pinfunction "2_2") (pintype "passive"))
      (node (ref "C261") (pin "2") (pinfunction "2_2") (pintype "passive"))
      (node (ref "C262") (pin "2") (pinfunction "-_2") (pintype "passive"))
      (node (ref "C263") (pin "1") (pinfunction "1_1") (pintype "passive"))
      (node (ref "C264") (pin "2") (pinfunction "2_2") (pintype "passive"))
      (node (ref "C265") (pin "2") (pinfunction "2_2") (pintype "passive"))
      (node (ref "C266") (pin "2") (pinfunction "2_2") (pintype "passive"))
      (node (ref "C267") (pin "2") (pinfunction "2_2") (pintype "passive"))
      (node (ref "C268") (pin "2") (pinfunction "2_2") (pintype "passive"))
      (node (ref "C269") (pin "2") (pinfunction "2_2") (pintype "passive"))
      (node (ref "C27") (pin "2") (pinfunction "2_2") (pintype "passive"))
      (node (ref "C270") (pin "2") (pinfunction "2_2") (pintype "passive"))
      (node (ref "C271") (pin "2") (pinfunction "2_2") (pintype "passive"))
      (node (ref "C274") (pin "2") (pinfunction "2_2") (pintype "passive"))
      (node (ref "C275") (pin "2") (pinfunction "2_2") (pintype "passive"))
      (node (ref "C276") (pin "2") (pinfunction "2_2") (pintype "passive"))
      (node (ref "C277") (pin "2") (pinfunction "-_2") (pintype "passive"))
      (node (ref "C278") (pin "2") (pinfunction "2_2") (pintype "passive"))
      (node (ref "C279") (pin "2") (pinfunction "2_2") (pintype "passive"))
      (node (ref "C28") (pin "2") (pinfunction "2_2") (pintype "passive"))
      (node (ref "C280") (pin "2") (pinfunction "2_2") (pintype "passive"))
      (node (ref "C281") (pin "2") (pinfunction "2_2") (pintype "passive"))
      (node (ref "C282") (pin "2") (pinfunction "2_2") (pintype "passive"))
      (node (ref "C283") (pin "2") (pinfunction "2_2") (pintype "passive"))
      (node (ref "C285") (pin "2") (pinfunction "2_2") (pintype "passive"))
      (node (ref "C286") (pin "2") (pinfunction "2_2") (pintype "passive"))
      (node (ref "C287") (pin "2") (pinfunction "2_2") (pintype "passive"))
      (node (ref "C288") (pin "2") (pinfunction "2_2") (pintype "passive"))
      (node (ref "C289") (pin "2") (pinfunction "-_2") (pintype "passive"))
      (node (ref "C29") (pin "2") (pinfunction "2_2") (pintype "passive"))
      (node (ref "C290") (pin "1") (pinfunction "1_1") (pintype "passive"))
      (node (ref "C291") (pin "2") (pinfunction "2_2") (pintype "passive"))
      (node (ref "C292") (pin "2") (pinfunction "2_2") (pintype "passive"))
      (node (ref "C293") (pin "2") (pinfunction "2_2") (pintype "passive"))
      (node (ref "C296") (pin "2") (pinfunction "2_2") (pintype "passive"))
      (node (ref "C297") (pin "2") (pinfunction "2_2") (pintype "passive"))
      (node (ref "C298") (pin "2") (pinfunction "2_2") (pintype "passive"))
      (node (ref "C299") (pin "2") (pinfunction "2_2") (pintype "passive"))
      (node (ref "C3") (pin "2") (pinfunction "2_2") (pintype "passive"))
      (node (ref "C30") (pin "2") (pinfunction "2_2") (pintype "passive"))
      (node (ref "C300") (pin "2") (pinfunction "2_2") (pintype "passive"))
      (node (ref "C303") (pin "2") (pinfunction "2_2") (pintype "passive"))
      (node (ref "C304") (pin "2") (pinfunction "2_2") (pintype "passive"))
      (node (ref "C31") (pin "1") (pinfunction "1_1") (pintype "passive"))
      (node (ref "C32") (pin "2") (pinfunction "2_2") (pintype "passive"))
      (node (ref "C35") (pin "2") (pinfunction "2_2") (pintype "passive"))
      (node (ref "C36") (pin "2") (pinfunction "2_2") (pintype "passive"))
      (node (ref "C37") (pin "2") (pinfunction "2_2") (pintype "passive"))
      (node (ref "C38") (pin "2") (pinfunction "2_2") (pintype "passive"))
      (node (ref "C39") (pin "2") (pinfunction "2_2") (pintype "passive"))
      (node (ref "C4") (pin "2") (pinfunction "2_2") (pintype "passive"))
      (node (ref "C40") (pin "1") (pinfunction "1_1") (pintype "passive"))
      (node (ref "C41") (pin "2") (pinfunction "2_2") (pintype "passive"))
      (node (ref "C42") (pin "2") (pinfunction "2_2") (pintype "passive"))
      (node (ref "C43") (pin "2") (pinfunction "2_2") (pintype "passive"))
      (node (ref "C44") (pin "2") (pinfunction "2_2") (pintype "passive"))
      (node (ref "C47") (pin "2") (pinfunction "2_2") (pintype "passive"))
      (node (ref "C48") (pin "2") (pinfunction "2_2") (pintype "passive"))
      (node (ref "C49") (pin "2") (pinfunction "2_2") (pintype "passive"))
      (node (ref "C5") (pin "2") (pinfunction "-_2") (pintype "passive"))
      (node (ref "C50") (pin "2") (pinfunction "-_2") (pintype "passive"))
      (node (ref "C51") (pin "2") (pinfunction "2_2") (pintype "passive"))
      (node (ref "C52") (pin "2") (pinfunction "2_2") (pintype "passive"))
      (node (ref "C53") (pin "2") (pinfunction "2_2") (pintype "passive"))
      (node (ref "C54") (pin "2") (pinfunction "2_2") (pintype "passive"))
      (node (ref "C55") (pin "2") (pinfunction "2_2") (pintype "passive"))
      (node (ref "C56") (pin "2") (pinfunction "2_2") (pintype "passive"))
      (node (ref "C57") (pin "2") (pinfunction "2_2") (pintype "passive"))
      (node (ref "C58") (pin "2") (pinfunction "2_2") (pintype "passive"))
      (node (ref "C59") (pin "2") (pinfunction "2_2") (pintype "passive"))
      (node (ref "C6") (pin "2") (pinfunction "2_2") (pintype "passive"))
      (node (ref "C60") (pin "2") (pinfunction "2_2") (pintype "passive"))
      (node (ref "C61") (pin "2") (pinfunction "2_2") (pintype "passive"))
      (node (ref "C62") (pin "2") (pinfunction "2_2") (pintype "passive"))
      (node (ref "C65") (pin "2") (pinfunction "2_2") (pintype "passive"))
      (node (ref "C66") (pin "2") (pinfunction "2_2") (pintype "passive"))
      (node (ref "C67") (pin "2") (pinfunction "2_2") (pintype "passive"))
      (node (ref "C68") (pin "2") (pinfunction "-_2") (pintype "passive"))
      (node (ref "C69") (pin "2") (pinfunction "2_2") (pintype "passive"))
      (node (ref "C7") (pin "2") (pinfunction "2_2") (pintype "passive"))
      (node (ref "C70") (pin "2") (pinfunction "2_2") (pintype "passive"))
      (node (ref "C71") (pin "2") (pinfunction "2_2") (pintype "passive"))
      (node (ref "C72") (pin "2") (pinfunction "2_2") (pintype "passive"))
      (node (ref "C73") (pin "2") (pinfunction "2_2") (pintype "passive"))
      (node (ref "C75") (pin "2") (pinfunction "2_2") (pintype "passive"))
      (node (ref "C76") (pin "2") (pinfunction "2_2") (pintype "passive"))
      (node (ref "C77") (pin "2") (pinfunction "2_2") (pintype "passive"))
      (node (ref "C78") (pin "2") (pinfunction "2_2") (pintype "passive"))
      (node (ref "C79") (pin "2") (pinfunction "-_2") (pintype "passive"))
      (node (ref "C8") (pin "2") (pinfunction "2_2") (pintype "passive"))
      (node (ref "C80") (pin "1") (pinfunction "1_1") (pintype "passive"))
      (node (ref "C81") (pin "2") (pinfunction "2_2") (pintype "passive"))
      (node (ref "C82") (pin "2") (pinfunction "2_2") (pintype "passive"))
      (node (ref "C83") (pin "2") (pinfunction "2_2") (pintype "passive"))
      (node (ref "C84") (pin "2") (pinfunction "2_2") (pintype "passive"))
      (node (ref "C85") (pin "2") (pinfunction "-_2") (pintype "passive"))
      (node (ref "C86") (pin "2") (pinfunction "2_2") (pintype "passive"))
      (node (ref "C87") (pin "2") (pinfunction "2_2") (pintype "passive"))
      (node (ref "C88") (pin "2") (pinfunction "2_2") (pintype "passive"))
      (node (ref "C89") (pin "2") (pinfunction "2_2") (pintype "passive"))
      (node (ref "C9") (pin "2") (pinfunction "2_2") (pintype "passive"))
      (node (ref "C90") (pin "2") (pinfunction "2_2") (pintype "passive"))
      (node (ref "C91") (pin "2") (pinfunction "2_2") (pintype "passive"))
      (node (ref "C94") (pin "2") (pinfunction "2_2") (pintype "passive"))
      (node (ref "C95") (pin "2") (pinfunction "2_2") (pintype "passive"))
      (node (ref "C96") (pin "2") (pinfunction "2_2") (pintype "passive"))
      (node (ref "C97") (pin "2") (pinfunction "-_2") (pintype "passive"))
      (node (ref "C98") (pin "2") (pinfunction "2_2") (pintype "passive"))
      (node (ref "C99") (pin "2") (pinfunction "2_2") (pintype "passive"))
      (node (ref "D10") (pin "A") (pinfunction "A_A") (pintype "passive"))
      (node (ref "D11") (pin "A") (pinfunction "A_A") (pintype "passive"))
      (node (ref "D12") (pin "2") (pinfunction "2_2") (pintype "power_in"))
      (node (ref "D13") (pin "2") (pinfunction "2_2") (pintype "power_in"))
      (node (ref "D2") (pin "C") (pinfunction "C_C") (pintype "passive"))
      (node (ref "D4") (pin "C") (pinfunction "C_C") (pintype "passive"))
      (node (ref "D6") (pin "C") (pinfunction "C_C") (pintype "passive"))
      (node (ref "D8") (pin "C") (pinfunction "C_C") (pintype "passive"))
      (node (ref "D9") (pin "A") (pinfunction "A_A") (pintype "passive"))
      (node (ref "DISP") (pin "5") (pinfunction "5_5") (pintype "bidirectional"))
      (node (ref "DISP") (pin "8") (pinfunction "8_8") (pintype "bidirectional"))
      (node (ref "DISP") (pin "Z0") (pinfunction "Z1_Z0") (pintype "bidirectional"))
      (node (ref "DISP") (pin "Z1") (pinfunction "Z1_Z1") (pintype "bidirectional"))
      (node (ref "DISP") (pin "Z2") (pinfunction "Z2_Z2") (pintype "bidirectional"))
      (node (ref "DISP") (pin "Z3") (pinfunction "Z3_Z3") (pintype "bidirectional"))
      (node (ref "DISP") (pin "Z4") (pinfunction "Z3_Z4") (pintype "bidirectional"))
      (node (ref "DISP") (pin "Z5") (pinfunction "Z4_Z5") (pintype "bidirectional"))
      (node (ref "ESD1") (pin "1") (pinfunction "A_1") (pintype "bidirectional"))
      (node (ref "ETH1") (pin "8") (pinfunction "GND_8") (pintype "power_in"))
      (node (ref "GND-1") (pin "TP") (pinfunction "P$1_TP") (pintype "bidirectional"))
      (node (ref "GND-5") (pin "TP") (pinfunction "P$1_TP") (pintype "bidirectional"))
      (node (ref "IC1") (pin "2") (pinfunction "GND_2") (pintype "bidirectional"))
      (node (ref "IC10") (pin "10") (pinfunction "AGND_10") (pintype "power_in"))
      (node (ref "IC10") (pin "24") (pinfunction "PGND_24") (pintype "power_in"))
      (node (ref "IC10") (pin "9") (pinfunction "PGND_9") (pintype "power_in"))
      (node (ref "IC11") (pin "3") (pinfunction "GND_3") (pintype "bidirectional"))
      (node (ref "IC11") (pin "8") (pinfunction "A1_8") (pintype "bidirectional"))
      (node (ref "IC12") (pin "10") (pinfunction "AGND_10") (pintype "power_in"))
      (node (ref "IC12") (pin "24") (pinfunction "PGND_24") (pintype "power_in"))
      (node (ref "IC12") (pin "9") (pinfunction "PGND_9") (pintype "power_in"))
      (node (ref "IC13") (pin "3") (pinfunction "GND_3") (pintype "bidirectional"))
      (node (ref "IC13") (pin "7") (pinfunction "A0_7") (pintype "bidirectional"))
      (node (ref "IC13") (pin "8") (pinfunction "A1_8") (pintype "bidirectional"))
      (node (ref "IC14") (pin "6") (pinfunction "GND_6") (pintype "power_in"))
      (node (ref "IC15") (pin "10") (pinfunction "AGND_10") (pintype "power_in"))
      (node (ref "IC15") (pin "24") (pinfunction "PGND_24") (pintype "power_in"))
      (node (ref "IC15") (pin "9") (pinfunction "PGND_9") (pintype "power_in"))
      (node (ref "IC16") (pin "3") (pinfunction "GND_3") (pintype "bidirectional"))
      (node (ref "IC16") (pin "7") (pinfunction "A0_7") (pintype "bidirectional"))
      (node (ref "IC17") (pin "6") (pinfunction "GND_6") (pintype "power_in"))
      (node (ref "IC18") (pin "10") (pinfunction "AGND_10") (pintype "power_in"))
      (node (ref "IC18") (pin "24") (pinfunction "PGND_24") (pintype "power_in"))
      (node (ref "IC18") (pin "9") (pinfunction "PGND_9") (pintype "power_in"))
      (node (ref "IC19") (pin "3") (pinfunction "GND_3") (pintype "bidirectional"))
      (node (ref "IC2") (pin "2") (pinfunction "GND_2") (pintype "bidirectional"))
      (node (ref "IC20") (pin "6") (pinfunction "GND_6") (pintype "power_in"))
      (node (ref "IC21") (pin "10") (pinfunction "AGND_10") (pintype "power_in"))
      (node (ref "IC21") (pin "24") (pinfunction "PGND_24") (pintype "power_in"))
      (node (ref "IC21") (pin "9") (pinfunction "PGND_9") (pintype "power_in"))
      (node (ref "IC22") (pin "3") (pinfunction "GND_3") (pintype "bidirectional"))
      (node (ref "IC22") (pin "7") (pinfunction "A0_7") (pintype "bidirectional"))
      (node (ref "IC22") (pin "8") (pinfunction "A1_8") (pintype "bidirectional"))
      (node (ref "IC23") (pin "6") (pinfunction "GND_6") (pintype "power_in"))
      (node (ref "IC24") (pin "10") (pinfunction "AGND_10") (pintype "power_in"))
      (node (ref "IC24") (pin "24") (pinfunction "PGND_24") (pintype "power_in"))
      (node (ref "IC24") (pin "9") (pinfunction "PGND_9") (pintype "power_in"))
      (node (ref "IC25") (pin "3") (pinfunction "GND_3") (pintype "bidirectional"))
      (node (ref "IC25") (pin "8") (pinfunction "A1_8") (pintype "bidirectional"))
      (node (ref "IC26") (pin "62") (pinfunction "VREG_PGND_62") (pintype "power_in"))
      (node (ref "IC26") (pin "81") (pinfunction "GND_81") (pintype "power_in"))
      (node (ref "IC27") (pin "4") (pinfunction "GND_4") (pintype "power_in"))
      (node (ref "IC27") (pin "PAD") (pinfunction "GND_PAD") (pintype "power_in"))
      (node (ref "IC28") (pin "5") (pinfunction "V-_5") (pintype "power_in"))
      (node (ref "IC29") (pin "2") (pinfunction "A1_2") (pintype "bidirectional"))
      (node (ref "IC29") (pin "3") (pinfunction "A2_3") (pintype "bidirectional"))
      (node (ref "IC29") (pin "4") (pinfunction "GND_4") (pintype "power_in"))
      (node (ref "IC29") (pin "7") (pinfunction "WP_7") (pintype "bidirectional"))
      (node (ref "IC29") (pin "9") (pinfunction "GND_9") (pintype "power_in"))
      (node (ref "IC3") (pin "2") (pinfunction "GND_2") (pintype "bidirectional"))
      (node (ref "IC30") (pin "6") (pinfunction "GND_6") (pintype "power_in"))
      (node (ref "IC31") (pin "14") (pinfunction "AGND_14") (pintype "power_in"))
      (node (ref "IC31") (pin "16") (pinfunction "AGND_16") (pintype "power_in"))
      (node (ref "IC31") (pin "19") (pinfunction "AGND_19") (pintype "power_in"))
      (node (ref "IC31") (pin "29") (pinfunction "GND_29") (pintype "passive"))
      (node (ref "IC31") (pin "3") (pinfunction "AGND_3") (pintype "power_in"))
      (node (ref "IC31") (pin "48") (pinfunction "AGND_48") (pintype "power_in"))
      (node (ref "IC31") (pin "9") (pinfunction "AGND_9") (pintype "power_in"))
      (node (ref "IC32") (pin "10") (pinfunction "AGND_10") (pintype "power_in"))
      (node (ref "IC32") (pin "24") (pinfunction "PGND_24") (pintype "power_in"))
      (node (ref "IC32") (pin "9") (pinfunction "PGND_9") (pintype "power_in"))
      (node (ref "IC33") (pin "3") (pinfunction "GND_3") (pintype "bidirectional"))
      (node (ref "IC33") (pin "7") (pinfunction "A0_7") (pintype "bidirectional"))
      (node (ref "IC34") (pin "6") (pinfunction "GND_6") (pintype "power_in"))
      (node (ref "IC35") (pin "10") (pinfunction "AGND_10") (pintype "power_in"))
      (node (ref "IC35") (pin "24") (pinfunction "PGND_24") (pintype "power_in"))
      (node (ref "IC35") (pin "9") (pinfunction "PGND_9") (pintype "power_in"))
      (node (ref "IC36") (pin "3") (pinfunction "GND_3") (pintype "bidirectional"))
      (node (ref "IC37") (pin "6") (pinfunction "GND_6") (pintype "power_in"))
      (node (ref "IC38") (pin "18") (pinfunction "A2_18") (pintype "input"))
      (node (ref "IC38") (pin "22") (pinfunction "A0_22") (pintype "input"))
      (node (ref "IC38") (pin "23") (pinfunction "A1_23") (pintype "input"))
      (node (ref "IC38") (pin "25") (pinfunction "GND_25") (pintype "power_in"))
      (node (ref "IC38") (pin "9") (pinfunction "GND_9") (pintype "power_in"))
      (node (ref "IC39") (pin "4") (pinfunction "GND_4") (pintype "power_in"))
      (node (ref "IC39") (pin "PAD") (pinfunction "GND_PAD") (pintype "power_in"))
      (node (ref "IC4") (pin "3") (pinfunction "V-_3") (pintype "bidirectional"))
      (node (ref "IC40") (pin "4") (pinfunction "GND_4") (pintype "bidirectional"))
      (node (ref "IC41") (pin "4") (pinfunction "GND_4") (pintype "bidirectional"))
      (node (ref "IC42") (pin "11") (pinfunction "A0_11") (pintype "bidirectional"))
      (node (ref "IC42") (pin "12") (pinfunction "A1_12") (pintype "bidirectional"))
      (node (ref "IC42") (pin "13") (pinfunction "A2_13") (pintype "bidirectional"))
      (node (ref "IC42") (pin "6") (pinfunction "VSS_6") (pintype "bidirectional"))
      (node (ref "IC42") (pin "PAD") (pinfunction "VSS_PAD") (pintype "bidirectional"))
      (node (ref "IC43") (pin "4") (pinfunction "GND_4") (pintype "bidirectional"))
      (node (ref "IC5") (pin "3") (pinfunction "V-_3") (pintype "bidirectional"))
      (node (ref "IC6") (pin "3") (pinfunction "V-_3") (pintype "bidirectional"))
      (node (ref "IC7") (pin "3") (pinfunction "V-_3") (pintype "bidirectional"))
      (node (ref "IC8") (pin "2") (pinfunction "GND_2") (pintype "bidirectional"))
      (node (ref "IC9") (pin "6") (pinfunction "GND_6") (pintype "power_in"))
      (node (ref "J8") (pin "4") (pinfunction "4_4") (pintype "passive"))
      (node (ref "J8") (pin "5") (pinfunction "5_5") (pintype "passive"))
      (node (ref "J8") (pin "6") (pinfunction "6_6") (pintype "passive"))
      (node (ref "JTAG") (pin "3") (pinfunction "3_3") (pintype "passive"))
      (node (ref "JTAG") (pin "5") (pinfunction "5_5") (pintype "passive"))
      (node (ref "JTAG") (pin "9") (pinfunction "9_9") (pintype "passive"))
      (node (ref "PORT1") (pin "A12") (pinfunction "GND1_A12") (pintype "passive"))
      (node (ref "PORT1") (pin "B12") (pinfunction "GND2_B12") (pintype "passive"))
      (node (ref "PORT2") (pin "A12") (pinfunction "GND1_A12") (pintype "passive"))
      (node (ref "PORT2") (pin "B12") (pinfunction "GND2_B12") (pintype "passive"))
      (node (ref "PORT3") (pin "A12") (pinfunction "GND1_A12") (pintype "passive"))
      (node (ref "PORT3") (pin "B12") (pinfunction "GND2_B12") (pintype "passive"))
      (node (ref "PORT4") (pin "A12") (pinfunction "GND1_A12") (pintype "passive"))
      (node (ref "PORT4") (pin "B12") (pinfunction "GND2_B12") (pintype "passive"))
      (node (ref "PORT5") (pin "A12") (pinfunction "GND1_A12") (pintype "passive"))
      (node (ref "PORT5") (pin "B12") (pinfunction "GND2_B12") (pintype "passive"))
      (node (ref "PORT6") (pin "A12") (pinfunction "GND1_A12") (pintype "passive"))
      (node (ref "PORT6") (pin "B12") (pinfunction "GND2_B12") (pintype "passive"))
      (node (ref "PORT7") (pin "A12") (pinfunction "GND1_A12") (pintype "passive"))
      (node (ref "PORT7") (pin "B12") (pinfunction "GND2_B12") (pintype "passive"))
      (node (ref "PORT8") (pin "A12") (pinfunction "GND1_A12") (pintype "passive"))
      (node (ref "PORT8") (pin "B12") (pinfunction "GND2_B12") (pintype "passive"))
      (node (ref "R104") (pin "2") (pinfunction "2_2") (pintype "passive"))
      (node (ref "R105") (pin "2") (pinfunction "2_2") (pintype "passive"))
      (node (ref "R106") (pin "2") (pinfunction "2_2") (pintype "passive"))
      (node (ref "R107") (pin "2") (pinfunction "2_2") (pintype "passive"))
      (node (ref "R114") (pin "2") (pinfunction "2_2") (pintype "passive"))
      (node (ref "R117") (pin "1") (pinfunction "1_1") (pintype "passive"))
      (node (ref "R123") (pin "2") (pinfunction "2_2") (pintype "passive"))
      (node (ref "R125") (pin "2") (pinfunction "2_2") (pintype "passive"))
      (node (ref "R130") (pin "2") (pinfunction "2_2") (pintype "passive"))
      (node (ref "R131") (pin "2") (pinfunction "2_2") (pintype "passive"))
      (node (ref "R132") (pin "2") (pinfunction "2_2") (pintype "passive"))
      (node (ref "R133") (pin "2") (pinfunction "2_2") (pintype "passive"))
      (node (ref "R140") (pin "2") (pinfunction "2_2") (pintype "passive"))
      (node (ref "R143") (pin "1") (pinfunction "1_1") (pintype "passive"))
      (node (ref "R149") (pin "2") (pinfunction "2_2") (pintype "passive"))
      (node (ref "R150") (pin "2") (pinfunction "2_2") (pintype "passive"))
      (node (ref "R151") (pin "2") (pinfunction "2_2") (pintype "passive"))
      (node (ref "R156") (pin "2") (pinfunction "2_2") (pintype "passive"))
      (node (ref "R157") (pin "2") (pinfunction "2_2") (pintype "passive"))
      (node (ref "R158") (pin "2") (pinfunction "2_2") (pintype "passive"))
      (node (ref "R159") (pin "2") (pinfunction "2_2") (pintype "passive"))
      (node (ref "R166") (pin "2") (pinfunction "2_2") (pintype "passive"))
      (node (ref "R169") (pin "1") (pinfunction "1_1") (pintype "passive"))
      (node (ref "R175") (pin "2") (pinfunction "2_2") (pintype "passive"))
      (node (ref "R177") (pin "2") (pinfunction "2_2") (pintype "passive"))
      (node (ref "R182") (pin "2") (pinfunction "2_2") (pintype "passive"))
      (node (ref "R183") (pin "2") (pinfunction "2_2") (pintype "passive"))
      (node (ref "R184") (pin "2") (pinfunction "2_2") (pintype "passive"))
      (node (ref "R185") (pin "2") (pinfunction "2_2") (pintype "passive"))
      (node (ref "R192") (pin "2") (pinfunction "2_2") (pintype "passive"))
      (node (ref "R195") (pin "1") (pinfunction "1_1") (pintype "passive"))
      (node (ref "R2") (pin "1") (pinfunction "1_1") (pintype "passive"))
      (node (ref "R201") (pin "2") (pinfunction "2_2") (pintype "passive"))
      (node (ref "R202") (pin "2") (pinfunction "2_2") (pintype "passive"))
      (node (ref "R203") (pin "2") (pinfunction "2_2") (pintype "passive"))
      (node (ref "R214") (pin "1") (pinfunction "1_1") (pintype "passive"))
      (node (ref "R221") (pin "2") (pinfunction "2_2") (pintype "passive"))
      (node (ref "R222") (pin "2") (pinfunction "2_2") (pintype "passive"))
      (node (ref "R223") (pin "2") (pinfunction "2_2") (pintype "passive"))
      (node (ref "R224") (pin "2") (pinfunction "2_2") (pintype "passive"))
      (node (ref "R225") (pin "1") (pinfunction "1_1") (pintype "passive"))
      (node (ref "R230") (pin "2") (pinfunction "2_2") (pintype "passive"))
      (node (ref "R239") (pin "2") (pinfunction "2_2") (pintype "passive"))
      (node (ref "R242") (pin "2") (pinfunction "2_2") (pintype "passive"))
      (node (ref "R246") (pin "1") (pinfunction "1_1") (pintype "passive"))
      (node (ref "R249") (pin "2") (pinfunction "2_2") (pintype "passive"))
      (node (ref "R250") (pin "2") (pinfunction "2_2") (pintype "passive"))
      (node (ref "R251") (pin "2") (pinfunction "2_2") (pintype "passive"))
      (node (ref "R255") (pin "2") (pinfunction "2_2") (pintype "passive"))
      (node (ref "R257") (pin "2") (pinfunction "2_2") (pintype "passive"))
      (node (ref "R259") (pin "2") (pinfunction "2_2") (pintype "passive"))
      (node (ref "R264") (pin "2") (pinfunction "2_2") (pintype "passive"))
      (node (ref "R265") (pin "2") (pinfunction "2_2") (pintype "passive"))
      (node (ref "R266") (pin "2") (pinfunction "2_2") (pintype "passive"))
      (node (ref "R267") (pin "2") (pinfunction "2_2") (pintype "passive"))
      (node (ref "R274") (pin "2") (pinfunction "2_2") (pintype "passive"))
      (node (ref "R277") (pin "1") (pinfunction "1_1") (pintype "passive"))
      (node (ref "R281") (pin "2") (pinfunction "2_2") (pintype "passive"))
      (node (ref "R285") (pin "2") (pinfunction "2_2") (pintype "passive"))
      (node (ref "R287") (pin "1") (pinfunction "1_1") (pintype "passive"))
      (node (ref "R290") (pin "2") (pinfunction "2_2") (pintype "passive"))
      (node (ref "R294") (pin "2") (pinfunction "2_2") (pintype "passive"))
      (node (ref "R296") (pin "1") (pinfunction "1_1") (pintype "passive"))
      (node (ref "R3") (pin "2") (pinfunction "2_2") (pintype "passive"))
      (node (ref "R32") (pin "2") (pinfunction "2_2") (pintype "passive"))
      (node (ref "R36") (pin "1") (pinfunction "1_1") (pintype "passive"))
      (node (ref "R45") (pin "1") (pinfunction "1_1") (pintype "passive"))
      (node (ref "R49") (pin "2") (pinfunction "2_2") (pintype "passive"))
      (node (ref "R50") (pin "1") (pinfunction "1_1") (pintype "passive"))
      (node (ref "R51") (pin "2") (pinfunction "2_2") (pintype "passive"))
      (node (ref "R52") (pin "2") (pinfunction "2_2") (pintype "passive"))
      (node (ref "R58") (pin "2") (pinfunction "2_2") (pintype "passive"))
      (node (ref "R59") (pin "2") (pinfunction "2_2") (pintype "passive"))
      (node (ref "R6") (pin "2") (pinfunction "2_2") (pintype "passive"))
      (node (ref "R60") (pin "2") (pinfunction "2_2") (pintype "passive"))
      (node (ref "R61") (pin "2") (pinfunction "2_2") (pintype "passive"))
      (node (ref "R70") (pin "2") (pinfunction "2_2") (pintype "passive"))
      (node (ref "R72") (pin "2") (pinfunction "2_2") (pintype "passive"))
      (node (ref "R77") (pin "2") (pinfunction "2_2") (pintype "passive"))
      (node (ref "R78") (pin "2") (pinfunction "2_2") (pintype "passive"))
      (node (ref "R79") (pin "2") (pinfunction "2_2") (pintype "passive"))
      (node (ref "R8") (pin "1") (pinfunction "1_1") (pintype "passive"))
      (node (ref "R80") (pin "2") (pinfunction "2_2") (pintype "passive"))
      (node (ref "R84") (pin "2") (pinfunction "2_2") (pintype "passive"))
      (node (ref "R88") (pin "2") (pinfunction "2_2") (pintype "passive"))
      (node (ref "R9") (pin "2") (pinfunction "2_2") (pintype "passive"))
      (node (ref "R91") (pin "1") (pinfunction "1_1") (pintype "passive"))
      (node (ref "R97") (pin "2") (pinfunction "2_2") (pintype "passive"))
      (node (ref "R98") (pin "2") (pinfunction "2_2") (pintype "passive"))
      (node (ref "R99") (pin "2") (pinfunction "2_2") (pintype "passive"))
      (node (ref "REF1") (pin "2") (pinfunction "A_2") (pintype "passive"))
      (node (ref "REF1") (pin "3") (pinfunction "A_3") (pintype "passive"))
      (node (ref "RFB4") (pin "2") (pinfunction "2_2") (pintype "passive"))
      (node (ref "SW1") (pin "1") (pinfunction "P$1_1") (pintype "bidirectional"))
      (node (ref "SW2") (pin "2") (pinfunction "P$2_2") (pintype "bidirectional"))
      (node (ref "T14") (pin "1") (pinfunction "S_1") (pintype "passive"))
      (node (ref "T14") (pin "2") (pinfunction "S_2") (pintype "passive"))
      (node (ref "T14") (pin "3") (pinfunction "S_3") (pintype "passive"))
      (node (ref "T19") (pin "1") (pinfunction "S_1") (pintype "passive"))
      (node (ref "T19") (pin "2") (pinfunction "S_2") (pintype "passive"))
      (node (ref "T19") (pin "3") (pinfunction "S_3") (pintype "passive"))
      (node (ref "T24") (pin "1") (pinfunction "S_1") (pintype "passive"))
      (node (ref "T24") (pin "2") (pinfunction "S_2") (pintype "passive"))
      (node (ref "T24") (pin "3") (pinfunction "S_3") (pintype "passive"))
      (node (ref "T29") (pin "1") (pinfunction "S_1") (pintype "passive"))
      (node (ref "T29") (pin "2") (pinfunction "S_2") (pintype "passive"))
      (node (ref "T29") (pin "3") (pinfunction "S_3") (pintype "passive"))
      (node (ref "T34") (pin "1") (pinfunction "S_1") (pintype "passive"))
      (node (ref "T34") (pin "2") (pinfunction "S_2") (pintype "passive"))
      (node (ref "T34") (pin "3") (pinfunction "S_3") (pintype "passive"))
      (node (ref "T39") (pin "1") (pinfunction "S_1") (pintype "passive"))
      (node (ref "T39") (pin "2") (pinfunction "S_2") (pintype "passive"))
      (node (ref "T39") (pin "3") (pinfunction "S_3") (pintype "passive"))
      (node (ref "T4") (pin "1") (pinfunction "S_1") (pintype "passive"))
      (node (ref "T4") (pin "2") (pinfunction "S_2") (pintype "passive"))
      (node (ref "T4") (pin "3") (pinfunction "S_3") (pintype "passive"))
      (node (ref "T9") (pin "1") (pinfunction "S_1") (pintype "passive"))
      (node (ref "T9") (pin "2") (pinfunction "S_2") (pintype "passive"))
      (node (ref "T9") (pin "3") (pinfunction "S_3") (pintype "passive"))
      (node (ref "USB9") (pin "GND") (pinfunction "GND_GND") (pintype "power_in"))
      (node (ref "USB9") (pin "GND2") (pinfunction "GND_GND2") (pintype "power_in"))
      (node (ref "USBA_1-2") (pin "4") (pinfunction "GND_4") (pintype "passive"))
      (node (ref "USBA_1-2") (pin "8") (pinfunction "GND_8") (pintype "passive"))
      (node (ref "USBA_3-4") (pin "4") (pinfunction "GND_4") (pintype "passive"))
      (node (ref "USBA_3-4") (pin "8") (pinfunction "GND_8") (pintype "passive"))
      (node (ref "X1") (pin "2") (pinfunction "GND_2") (pintype "passive"))
      (node (ref "X1") (pin "4") (pinfunction "GND_4") (pintype "passive"))
      (node (ref "X2") (pin "2") (pinfunction "GND_2") (pintype "passive"))
      (node (ref "X2") (pin "4") (pinfunction "GND_4") (pintype "passive"))
    )
    (net (code "39") (name "I2C0_SCL") (class "Default")
      (node (ref "D12") (pin "3") (pinfunction "3_3") (pintype "bidirectional"))
      (node (ref "IC26") (pin "2") (pinfunction "GPIO5_2") (pintype "bidirectional"))
      (node (ref "IC38") (pin "19") (pinfunction "SCL_19") (pintype "bidirectional"))
      (node (ref "R207") (pin "B1") (pinfunction "2_B1") (pintype "passive"))
    )
    (net (code "40") (name "I2C0_SDA") (class "Default")
      (node (ref "D12") (pin "1") (pinfunction "1_1") (pintype "bidirectional"))
      (node (ref "IC26") (pin "1") (pinfunction "GPIO4_1") (pintype "bidirectional"))
      (node (ref "IC38") (pin "20") (pinfunction "SDA_20") (pintype "bidirectional"))
      (node (ref "R207") (pin "D1") (pinfunction "4_D1") (pintype "passive"))
    )
    (net (code "41") (name "I2C1_SCL") (class "Default")
      (node (ref "D12") (pin "6") (pinfunction "6_6") (pintype "bidirectional"))
      (node (ref "DISP") (pin "7") (pinfunction "7_7") (pintype "bidirectional"))
      (node (ref "IC26") (pin "4") (pinfunction "GPIO7_4") (pintype "bidirectional"))
      (node (ref "IC29") (pin "6") (pinfunction "SCL_6") (pintype "bidirectional"))
      (node (ref "IC42") (pin "8") (pinfunction "SCL_8") (pintype "bidirectional"))
      (node (ref "R207") (pin "C1") (pinfunction "3_C1") (pintype "passive"))
    )
    (net (code "42") (name "I2C1_SDA") (class "Default")
      (node (ref "D12") (pin "4") (pinfunction "4_4") (pintype "bidirectional"))
      (node (ref "DISP") (pin "6") (pinfunction "6_6") (pintype "bidirectional"))
      (node (ref "IC26") (pin "3") (pinfunction "GPIO6_3") (pintype "bidirectional"))
      (node (ref "IC29") (pin "5") (pinfunction "SDA_5") (pintype "bidirectional"))
      (node (ref "IC42") (pin "9") (pinfunction "SDA_9") (pintype "bidirectional"))
      (node (ref "R207") (pin "A1") (pinfunction "1_A1") (pintype "passive"))
    )
    (net (code "43") (name "IN1_PORT1") (class "Default")
      (node (ref "IC13") (pin "1") (pinfunction "IN+_1") (pintype "bidirectional"))
      (node (ref "IC9") (pin "12") (pinfunction "VBUS_SENSE_12") (pintype "input"))
      (node (ref "R57") (pin "1") (pinfunction "1_1") (pintype "passive"))
      (node (ref "T8") (pin "5") (pinfunction "D_5") (pintype "passive"))
      (node (ref "T8") (pin "6") (pinfunction "D_6") (pintype "passive"))
      (node (ref "T8") (pin "7") (pinfunction "D_7") (pintype "passive"))
      (node (ref "T8") (pin "8") (pinfunction "D_8") (pintype "passive"))
      (node (ref "T8") (pin "9") (pinfunction "D_9") (pintype "passive"))
    )
    (net (code "44") (name "IN1_PORT2") (class "Default")
      (node (ref "IC11") (pin "1") (pinfunction "IN+_1") (pintype "bidirectional"))
      (node (ref "IC14") (pin "12") (pinfunction "VBUS_SENSE_12") (pintype "input"))
      (node (ref "R76") (pin "1") (pinfunction "1_1") (pintype "passive"))
      (node (ref "T3") (pin "5") (pinfunction "D_5") (pintype "passive"))
      (node (ref "T3") (pin "6") (pinfunction "D_6") (pintype "passive"))
      (node (ref "T3") (pin "7") (pinfunction "D_7") (pintype "passive"))
      (node (ref "T3") (pin "8") (pinfunction "D_8") (pintype "passive"))
      (node (ref "T3") (pin "9") (pinfunction "D_9") (pintype "passive"))
    )
    (net (code "45") (name "IN1_PORT3") (class "Default")
      (node (ref "IC16") (pin "1") (pinfunction "IN+_1") (pintype "bidirectional"))
      (node (ref "IC17") (pin "12") (pinfunction "VBUS_SENSE_12") (pintype "input"))
      (node (ref "R103") (pin "1") (pinfunction "1_1") (pintype "passive"))
      (node (ref "T13") (pin "5") (pinfunction "D_5") (pintype "passive"))
      (node (ref "T13") (pin "6") (pinfunction "D_6") (pintype "passive"))
      (node (ref "T13") (pin "7") (pinfunction "D_7") (pintype "passive"))
      (node (ref "T13") (pin "8") (pinfunction "D_8") (pintype "passive"))
      (node (ref "T13") (pin "9") (pinfunction "D_9") (pintype "passive"))
    )
    (net (code "46") (name "IN1_PORT4") (class "Default")
      (node (ref "IC19") (pin "1") (pinfunction "IN+_1") (pintype "bidirectional"))
      (node (ref "IC20") (pin "12") (pinfunction "VBUS_SENSE_12") (pintype "input"))
      (node (ref "R129") (pin "1") (pinfunction "1_1") (pintype "passive"))
      (node (ref "T18") (pin "5") (pinfunction "D_5") (pintype "passive"))
      (node (ref "T18") (pin "6") (pinfunction "D_6") (pintype "passive"))
      (node (ref "T18") (pin "7") (pinfunction "D_7") (pintype "passive"))
      (node (ref "T18") (pin "8") (pinfunction "D_8") (pintype "passive"))
      (node (ref "T18") (pin "9") (pinfunction "D_9") (pintype "passive"))
    )
    (net (code "47") (name "IN1_PORT5") (class "Default")
      (node (ref "IC22") (pin "1") (pinfunction "IN+_1") (pintype "bidirectional"))
      (node (ref "IC23") (pin "12") (pinfunction "VBUS_SENSE_12") (pintype "input"))
      (node (ref "R155") (pin "1") (pinfunction "1_1") (pintype "passive"))
      (node (ref "T23") (pin "5") (pinfunction "D_5") (pintype "passive"))
      (node (ref "T23") (pin "6") (pinfunction "D_6") (pintype "passive"))
      (node (ref "T23") (pin "7") (pinfunction "D_7") (pintype "passive"))
      (node (ref "T23") (pin "8") (pinfunction "D_8") (pintype "passive"))
      (node (ref "T23") (pin "9") (pinfunction "D_9") (pintype "passive"))
    )
    (net (code "48") (name "IN1_PORT6") (class "Default")
      (node (ref "IC25") (pin "1") (pinfunction "IN+_1") (pintype "bidirectional"))
      (node (ref "IC30") (pin "12") (pinfunction "VBUS_SENSE_12") (pintype "input"))
      (node (ref "R181") (pin "1") (pinfunction "1_1") (pintype "passive"))
      (node (ref "T28") (pin "5") (pinfunction "D_5") (pintype "passive"))
      (node (ref "T28") (pin "6") (pinfunction "D_6") (pintype "passive"))
      (node (ref "T28") (pin "7") (pinfunction "D_7") (pintype "passive"))
      (node (ref "T28") (pin "8") (pinfunction "D_8") (pintype "passive"))
      (node (ref "T28") (pin "9") (pinfunction "D_9") (pintype "passive"))
    )
    (net (code "49") (name "IN1_PORT7") (class "Default")
      (node (ref "IC33") (pin "1") (pinfunction "IN+_1") (pintype "bidirectional"))
      (node (ref "IC34") (pin "12") (pinfunction "VBUS_SENSE_12") (pintype "input"))
      (node (ref "R220") (pin "1") (pinfunction "1_1") (pintype "passive"))
      (node (ref "T33") (pin "5") (pinfunction "D_5") (pintype "passive"))
      (node (ref "T33") (pin "6") (pinfunction "D_6") (pintype "passive"))
      (node (ref "T33") (pin "7") (pinfunction "D_7") (pintype "passive"))
      (node (ref "T33") (pin "8") (pinfunction "D_8") (pintype "passive"))
      (node (ref "T33") (pin "9") (pinfunction "D_9") (pintype "passive"))
    )
    (net (code "50") (name "IN1_PORT8") (class "Default")
      (node (ref "IC36") (pin "1") (pinfunction "IN+_1") (pintype "bidirectional"))
      (node (ref "IC37") (pin "12") (pinfunction "VBUS_SENSE_12") (pintype "input"))
      (node (ref "R263") (pin "1") (pinfunction "1_1") (pintype "passive"))
      (node (ref "T38") (pin "5") (pinfunction "D_5") (pintype "passive"))
      (node (ref "T38") (pin "6") (pinfunction "D_6") (pintype "passive"))
      (node (ref "T38") (pin "7") (pinfunction "D_7") (pintype "passive"))
      (node (ref "T38") (pin "8") (pinfunction "D_8") (pintype "passive"))
      (node (ref "T38") (pin "9") (pinfunction "D_9") (pintype "passive"))
    )
    (net (code "51") (name "IN2_PORT1") (class "Default")
      (node (ref "IC13") (pin "2") (pinfunction "IN-_2") (pintype "bidirectional"))
      (node (ref "PORT1") (pin "A9") (pinfunction "VBUS1_A9") (pintype "passive"))
      (node (ref "PORT1") (pin "B9") (pinfunction "VBUS2_B9") (pintype "passive"))
      (node (ref "R57") (pin "2") (pinfunction "2_2") (pintype "passive"))
    )
    (net (code "52") (name "IN2_PORT2") (class "Default")
      (node (ref "IC11") (pin "2") (pinfunction "IN-_2") (pintype "bidirectional"))
      (node (ref "PORT2") (pin "A9") (pinfunction "VBUS1_A9") (pintype "passive"))
      (node (ref "PORT2") (pin "B9") (pinfunction "VBUS2_B9") (pintype "passive"))
      (node (ref "R76") (pin "2") (pinfunction "2_2") (pintype "passive"))
    )
    (net (code "53") (name "IN2_PORT3") (class "Default")
      (node (ref "IC16") (pin "2") (pinfunction "IN-_2") (pintype "bidirectional"))
      (node (ref "PORT3") (pin "A9") (pinfunction "VBUS1_A9") (pintype "passive"))
      (node (ref "PORT3") (pin "B9") (pinfunction "VBUS2_B9") (pintype "passive"))
      (node (ref "R103") (pin "2") (pinfunction "2_2") (pintype "passive"))
    )
    (net (code "54") (name "IN2_PORT4") (class "Default")
      (node (ref "IC19") (pin "2") (pinfunction "IN-_2") (pintype "bidirectional"))
      (node (ref "PORT4") (pin "A9") (pinfunction "VBUS1_A9") (pintype "passive"))
      (node (ref "PORT4") (pin "B9") (pinfunction "VBUS2_B9") (pintype "passive"))
      (node (ref "R129") (pin "2") (pinfunction "2_2") (pintype "passive"))
    )
    (net (code "55") (name "IN2_PORT5") (class "Default")
      (node (ref "IC22") (pin "2") (pinfunction "IN-_2") (pintype "bidirectional"))
      (node (ref "PORT5") (pin "A9") (pinfunction "VBUS1_A9") (pintype "passive"))
      (node (ref "PORT5") (pin "B9") (pinfunction "VBUS2_B9") (pintype "passive"))
      (node (ref "R155") (pin "2") (pinfunction "2_2") (pintype "passive"))
    )
    (net (code "56") (name "IN2_PORT6") (class "Default")
      (node (ref "IC25") (pin "2") (pinfunction "IN-_2") (pintype "bidirectional"))
      (node (ref "PORT6") (pin "A9") (pinfunction "VBUS1_A9") (pintype "passive"))
      (node (ref "PORT6") (pin "B9") (pinfunction "VBUS2_B9") (pintype "passive"))
      (node (ref "R181") (pin "2") (pinfunction "2_2") (pintype "passive"))
    )
    (net (code "57") (name "IN2_PORT7") (class "Default")
      (node (ref "IC33") (pin "2") (pinfunction "IN-_2") (pintype "bidirectional"))
      (node (ref "PORT7") (pin "A9") (pinfunction "VBUS1_A9") (pintype "passive"))
      (node (ref "PORT7") (pin "B9") (pinfunction "VBUS2_B9") (pintype "passive"))
      (node (ref "R220") (pin "2") (pinfunction "2_2") (pintype "passive"))
    )
    (net (code "58") (name "IN2_PORT8") (class "Default")
      (node (ref "IC36") (pin "2") (pinfunction "IN-_2") (pintype "bidirectional"))
      (node (ref "PORT8") (pin "A9") (pinfunction "VBUS1_A9") (pintype "passive"))
      (node (ref "PORT8") (pin "B9") (pinfunction "VBUS2_B9") (pintype "passive"))
      (node (ref "R263") (pin "2") (pinfunction "2_2") (pintype "passive"))
    )
    (net (code "59") (name "KEY_0") (class "Default")
      (node (ref "D13") (pin "4") (pinfunction "4_4") (pintype "bidirectional"))
      (node (ref "DISP") (pin "12") (pinfunction "12_12") (pintype "bidirectional"))
      (node (ref "IC26") (pin "25") (pinfunction "GPIO24_25") (pintype "bidirectional"))
    )
    (net (code "60") (name "KEY_1") (class "Default")
      (node (ref "D13") (pin "6") (pinfunction "6_6") (pintype "bidirectional"))
      (node (ref "DISP") (pin "11") (pinfunction "11_11") (pintype "bidirectional"))
      (node (ref "IC26") (pin "26") (pinfunction "GPIO25_26") (pintype "bidirectional"))
    )
    (net (code "61") (name "KEY_2") (class "Default")
      (node (ref "D13") (pin "1") (pinfunction "1_1") (pintype "bidirectional"))
      (node (ref "DISP") (pin "10") (pinfunction "10_10") (pintype "bidirectional"))
      (node (ref "IC26") (pin "27") (pinfunction "GPIO26_27") (pintype "bidirectional"))
    )
    (net (code "62") (name "KEY_3") (class "Default")
      (node (ref "D13") (pin "3") (pinfunction "3_3") (pintype "bidirectional"))
      (node (ref "DISP") (pin "9") (pinfunction "9_9") (pintype "bidirectional"))
      (node (ref "IC26") (pin "28") (pinfunction "GPIO27_28") (pintype "bidirectional"))
    )
    (net (code "63") (name "LCD_BL") (class "Default")
      (node (ref "DISP") (pin "13") (pinfunction "13_13") (pintype "bidirectional"))
    )
    (net (code "64") (name "LCD_RES") (class "Default")
      (node (ref "DISP") (pin "14") (pinfunction "14_14") (pintype "bidirectional"))
    )
    (net (code "65") (name "MCP_DSP_RST") (class "Default")
      (node (ref "DISP") (pin "20") (pinfunction "20_20") (pintype "bidirectional"))
      (node (ref "R252") (pin "1") (pinfunction "1_1") (pintype "passive"))
    )
    (net (code "66") (name "MCP_REL_RST") (class "Default")
      (node (ref "IC42") (pin "14") (pinfunction "~{RESET}_14") (pintype "bidirectional"))
    )
    (net (code "67") (name "Net-(C44-Pad1)") (class "Default")
      (node (ref "C44") (pin "1") (pinfunction "1_1") (pintype "passive"))
      (node (ref "R62") (pin "2") (pinfunction "2_2") (pintype "passive"))
    )
    (net (code "68") (name "Net-(C46-Pad1)") (class "Default")
      (node (ref "C46") (pin "1") (pinfunction "1_1") (pintype "passive"))
      (node (ref "IC12") (pin "21") (pinfunction "SW2_21") (pintype "power_in"))
      (node (ref "IC12") (pin "25") (pinfunction "SW2_25") (pintype "power_in"))
      (node (ref "L2") (pin "2") (pinfunction "2_2") (pintype "passive"))
      (node (ref "R232") (pin "1") (pinfunction "1_1") (pintype "passive"))
    )
    (net (code "69") (name "Net-(C62-Pad1)") (class "Default")
      (node (ref "C62") (pin "1") (pinfunction "1_1") (pintype "passive"))
      (node (ref "R81") (pin "2") (pinfunction "2_2") (pintype "passive"))
    )
    (net (code "70") (name "Net-(C64-Pad1)") (class "Default")
      (node (ref "C64") (pin "1") (pinfunction "1_1") (pintype "passive"))
      (node (ref "IC10") (pin "21") (pinfunction "SW2_21") (pintype "power_in"))
      (node (ref "IC10") (pin "25") (pinfunction "SW2_25") (pintype "power_in"))
      (node (ref "L3") (pin "2") (pinfunction "2_2") (pintype "passive"))
      (node (ref "R90") (pin "1") (pinfunction "1_1") (pintype "passive"))
    )
    (net (code "71") (name "Net-(C76-Pad1)") (class "Default")
      (node (ref "C76") (pin "1") (pinfunction "1_1") (pintype "passive"))
      (node (ref "R89") (pin "2") (pinfunction "2_2") (pintype "passive"))
    )
    (net (code "72") (name "Net-(C77-Pad1)") (class "Default")
      (node (ref "C77") (pin "1") (pinfunction "1_1") (pintype "passive"))
      (node (ref "R90") (pin "2") (pinfunction "2_2") (pintype "passive"))
    )
    (net (code "73") (name "Net-(C91-Pad1)") (class "Default")
      (node (ref "C91") (pin "1") (pinfunction "1_1") (pintype "passive"))
      (node (ref "R108") (pin "2") (pinfunction "2_2") (pintype "passive"))
    )
    (net (code "74") (name "Net-(C93-Pad1)") (class "Default")
      (node (ref "C93") (pin "1") (pinfunction "1_1") (pintype "passive"))
      (node (ref "IC15") (pin "21") (pinfunction "SW2_21") (pintype "power_in"))
      (node (ref "IC15") (pin "25") (pinfunction "SW2_25") (pintype "power_in"))
      (node (ref "L4") (pin "2") (pinfunction "2_2") (pintype "passive"))
      (node (ref "R116") (pin "1") (pinfunction "1_1") (pintype "passive"))
    )
    (net (code "75") (name "Net-(C105-Pad1)") (class "Default")
      (node (ref "C105") (pin "1") (pinfunction "1_1") (pintype "passive"))
      (node (ref "R115") (pin "2") (pinfunction "2_2") (pintype "passive"))
    )
    (net (code "76") (name "Net-(C106-Pad1)") (class "Default")
      (node (ref "C106") (pin "1") (pinfunction "1_1") (pintype "passive"))
      (node (ref "R116") (pin "2") (pinfunction "2_2") (pintype "passive"))
    )
    (net (code "77") (name "Net-(C116-Pad1)") (class "Default")
      (node (ref "C116") (pin "1") (pinfunction "1_1") (pintype "passive"))
      (node (ref "R134") (pin "2") (pinfunction "2_2") (pintype "passive"))
    )
    (net (code "78") (name "Net-(C118-Pad1)") (class "Default")
      (node (ref "C118") (pin "1") (pinfunction "1_1") (pintype "passive"))
      (node (ref "IC18") (pin "21") (pinfunction "SW2_21") (pintype "power_in"))
      (node (ref "IC18") (pin "25") (pinfunction "SW2_25") (pintype "power_in"))
      (node (ref "L5") (pin "2") (pinfunction "2_2") (pintype "passive"))
      (node (ref "R142") (pin "1") (pinfunction "1_1") (pintype "passive"))
    )
    (net (code "79") (name "Net-(C130-Pad1)") (class "Default")
      (node (ref "C130") (pin "1") (pinfunction "1_1") (pintype "passive"))
      (node (ref "R141") (pin "2") (pinfunction "2_2") (pintype "passive"))
    )
    (net (code "80") (name "Net-(C131-Pad1)") (class "Default")
      (node (ref "C131") (pin "1") (pinfunction "1_1") (pintype "passive"))
      (node (ref "R142") (pin "2") (pinfunction "2_2") (pintype "passive"))
    )
    (net (code "81") (name "Net-(C141-Pad1)") (class "Default")
      (node (ref "C141") (pin "1") (pinfunction "1_1") (pintype "passive"))
      (node (ref "R160") (pin "2") (pinfunction "2_2") (pintype "passive"))
    )
    (net (code "82") (name "Net-(C143-Pad1)") (class "Default")
      (node (ref "C143") (pin "1") (pinfunction "1_1") (pintype "passive"))
      (node (ref "IC21") (pin "21") (pinfunction "SW2_21") (pintype "power_in"))
      (node (ref "IC21") (pin "25") (pinfunction "SW2_25") (pintype "power_in"))
      (node (ref "L6") (pin "2") (pinfunction "2_2") (pintype "passive"))
      (node (ref "R168") (pin "1") (pinfunction "1_1") (pintype "passive"))
    )
    (net (code "83") (name "Net-(C155-Pad1)") (class "Default")
      (node (ref "C155") (pin "1") (pinfunction "1_1") (pintype "passive"))
      (node (ref "R167") (pin "2") (pinfunction "2_2") (pintype "passive"))
    )
    (net (code "84") (name "Net-(C156-Pad1)") (class "Default")
      (node (ref "C156") (pin "1") (pinfunction "1_1") (pintype "passive"))
      (node (ref "R168") (pin "2") (pinfunction "2_2") (pintype "passive"))
    )
    (net (code "85") (name "Net-(C166-Pad1)") (class "Default")
      (node (ref "C166") (pin "1") (pinfunction "1_1") (pintype "passive"))
      (node (ref "R186") (pin "2") (pinfunction "2_2") (pintype "passive"))
    )
    (net (code "86") (name "Net-(C168-Pad1)") (class "Default")
      (node (ref "C168") (pin "1") (pinfunction "1_1") (pintype "passive"))
      (node (ref "IC24") (pin "21") (pinfunction "SW2_21") (pintype "power_in"))
      (node (ref "IC24") (pin "25") (pinfunction "SW2_25") (pintype "power_in"))
      (node (ref "L7") (pin "2") (pinfunction "2_2") (pintype "passive"))
      (node (ref "R194") (pin "1") (pinfunction "1_1") (pintype "passive"))
    )
    (net (code "87") (name "Net-(C201-Pad1)") (class "Default")
      (node (ref "C201") (pin "1") (pinfunction "1_1") (pintype "passive"))
      (node (ref "R193") (pin "2") (pinfunction "2_2") (pintype "passive"))
    )
    (net (code "88") (name "Net-(C202-Pad1)") (class "Default")
      (node (ref "C202") (pin "1") (pinfunction "1_1") (pintype "passive"))
      (node (ref "R194") (pin "2") (pinfunction "2_2") (pintype "passive"))
    )
    (net (code "89") (name "Net-(C215-Pad1)") (class "Default")
      (node (ref "C215") (pin "1") (pinfunction "1_1") (pintype "passive"))
      (node (ref "R231") (pin "2") (pinfunction "2_2") (pintype "passive"))
    )
    (net (code "90") (name "Net-(C216-Pad1)") (class "Default")
      (node (ref "C216") (pin "1") (pinfunction "1_1") (pintype "passive"))
      (node (ref "R232") (pin "2") (pinfunction "2_2") (pintype "passive"))
    )
    (net (code "91") (name "Net-(C219-Pad1)") (class "Default")
      (node (ref "C219") (pin "1") (pinfunction "1_1") (pintype "passive"))
      (node (ref "R233") (pin "2") (pinfunction "2_2") (pintype "passive"))
    )
    (net (code "92") (name "Net-(C230-Pad1)") (class "Default")
      (node (ref "C230") (pin "1") (pinfunction "1_1") (pintype "passive"))
      (node (ref "IC32") (pin "21") (pinfunction "SW2_21") (pintype "power_in"))
      (node (ref "IC32") (pin "25") (pinfunction "SW2_25") (pintype "power_in"))
      (node (ref "L8") (pin "2") (pinfunction "2_2") (pintype "passive"))
      (node (ref "R245") (pin "1") (pinfunction "1_1") (pintype "passive"))
    )
    (net (code "93") (name "Net-(C235-Pad1)") (class "Default")
      (node (ref "C235") (pin "1") (pinfunction "1_1") (pintype "passive"))
      (node (ref "R243") (pin "1") (pinfunction "1_1") (pintype "passive"))
    )
    (net (code "94") (name "Net-(C236-Pad2)") (class "Default")
      (node (ref "C236") (pin "2") (pinfunction "2_2") (pintype "passive"))
      (node (ref "RFB3") (pin "2") (pinfunction "2_2") (pintype "passive"))
      (node (ref "RFB4") (pin "1") (pinfunction "1_1") (pintype "passive"))
      (node (ref "RT1") (pin "2") (pinfunction "2_2") (pintype "passive"))
    )
    (net (code "95") (name "Net-(C259-Pad1)") (class "Default")
      (node (ref "C259") (pin "1") (pinfunction "1_1") (pintype "passive"))
      (node (ref "R240") (pin "2") (pinfunction "2_2") (pintype "passive"))
    )
    (net (code "96") (name "Net-(C260-Pad1)") (class "Default")
      (node (ref "C260") (pin "1") (pinfunction "1_1") (pintype "passive"))
      (node (ref "R245") (pin "2") (pinfunction "2_2") (pintype "passive"))
    )
    (net (code "97") (name "Net-(C271-Pad1)") (class "Default")
      (node (ref "C271") (pin "1") (pinfunction "1_1") (pintype "passive"))
      (node (ref "R268") (pin "2") (pinfunction "2_2") (pintype "passive"))
    )
    (net (code "98") (name "Net-(C273-Pad1)") (class "Default")
      (node (ref "C273") (pin "1") (pinfunction "1_1") (pintype "passive"))
      (node (ref "IC35") (pin "21") (pinfunction "SW2_21") (pintype "power_in"))
      (node (ref "IC35") (pin "25") (pinfunction "SW2_25") (pintype "power_in"))
      (node (ref "L9") (pin "2") (pinfunction "2_2") (pintype "passive"))
      (node (ref "R276") (pin "1") (pinfunction "1_1") (pintype "passive"))
    )
    (net (code "99") (name "Net-(C286-Pad1)") (class "Default")
      (node (ref "C286") (pin "1") (pinfunction "1_1") (pintype "passive"))
      (node (ref "R275") (pin "2") (pinfunction "2_2") (pintype "passive"))
    )
    (net (code "100") (name "Net-(C287-Pad1)") (class "Default")
      (node (ref "C287") (pin "1") (pinfunction "1_1") (pintype "passive"))
      (node (ref "R276") (pin "2") (pinfunction "2_2") (pintype "passive"))
    )
    (net (code "101") (name "Net-(C294-Pad1)") (class "Default")
      (node (ref "C294") (pin "1") (pinfunction "1_1") (pintype "passive"))
      (node (ref "R282") (pin "1") (pinfunction "1_1") (pintype "passive"))
    )
    (net (code "102") (name "Net-(C295-Pad2)") (class "Default")
      (node (ref "C295") (pin "2") (pinfunction "2_2") (pintype "passive"))
      (node (ref "R283") (pin "2") (pinfunction "2_2") (pintype "passive"))
      (node (ref "R284") (pin "2") (pinfunction "2_2") (pintype "passive"))
      (node (ref "R285") (pin "1") (pinfunction "1_1") (pintype "passive"))
    )
    (net (code "103") (name "Net-(C301-Pad1)") (class "Default")
      (node (ref "C301") (pin "1") (pinfunction "1_1") (pintype "passive"))
      (node (ref "R291") (pin "1") (pinfunction "1_1") (pintype "passive"))
    )
    (net (code "104") (name "Net-(C302-Pad2)") (class "Default")
      (node (ref "C302") (pin "2") (pinfunction "2_2") (pintype "passive"))
      (node (ref "R292") (pin "2") (pinfunction "2_2") (pintype "passive"))
      (node (ref "R293") (pin "2") (pinfunction "2_2") (pintype "passive"))
      (node (ref "R294") (pin "1") (pinfunction "1_1") (pintype "passive"))
    )
    (net (code "105") (name "Net-(D1-PadC)") (class "Default")
      (node (ref "D1") (pin "C") (pinfunction "C_C") (pintype "passive"))
      (node (ref "R14") (pin "2") (pinfunction "2_2") (pintype "passive"))
    )
    (net (code "106") (name "Net-(D2-PadA)") (class "Default")
      (node (ref "D2") (pin "A") (pinfunction "A_A") (pintype "passive"))
      (node (ref "R12") (pin "2") (pinfunction "2_2") (pintype "passive"))
    )
    (net (code "107") (name "Net-(D3-PadC)") (class "Default")
      (node (ref "D3") (pin "C") (pinfunction "C_C") (pintype "passive"))
      (node (ref "R17") (pin "2") (pinfunction "2_2") (pintype "passive"))
    )
    (net (code "108") (name "Net-(D4-PadA)") (class "Default")
      (node (ref "D4") (pin "A") (pinfunction "A_A") (pintype "passive"))
      (node (ref "R15") (pin "1") (pinfunction "1_1") (pintype "passive"))
    )
    (net (code "109") (name "Net-(D5-PadC)") (class "Default")
      (node (ref "D5") (pin "C") (pinfunction "C_C") (pintype "passive"))
      (node (ref "R20") (pin "2") (pinfunction "2_2") (pintype "passive"))
    )
    (net (code "110") (name "Net-(D6-PadA)") (class "Default")
      (node (ref "D6") (pin "A") (pinfunction "A_A") (pintype "passive"))
      (node (ref "R18") (pin "1") (pinfunction "1_1") (pintype "passive"))
    )
    (net (code "111") (name "Net-(D7-PadC)") (class "Default")
      (node (ref "D7") (pin "C") (pinfunction "C_C") (pintype "passive"))
      (node (ref "R23") (pin "2") (pinfunction "2_2") (pintype "passive"))
    )
    (net (code "112") (name "Net-(D8-PadA)") (class "Default")
      (node (ref "D8") (pin "A") (pinfunction "A_A") (pintype "passive"))
      (node (ref "R21") (pin "1") (pinfunction "1_1") (pintype "passive"))
    )
    (net (code "113") (name "Net-(ETH1-GREEN-)") (class "Default")
      (node (ref "ETH1") (pin "9") (pinfunction "GREEN-_9") (pintype "passive"))
      (node (ref "R34") (pin "2") (pinfunction "2_2") (pintype "passive"))
    )
    (net (code "114") (name "Net-(ETH1-YELLOW-)") (class "Default")
      (node (ref "ETH1") (pin "11") (pinfunction "YELLOW-_11") (pintype "passive"))
      (node (ref "R33") (pin "2") (pinfunction "2_2") (pintype "passive"))
    )
    (net (code "115") (name "Net-(F1-1-Pad1_1)") (class "Default")
      (node (ref "F1") (pin "1_1") (pinfunction "1_1_1") (pintype "passive"))
      (node (ref "F1") (pin "1_2") (pinfunction "1_1_2") (pintype "passive"))
      (node (ref "J8") (pin "1") (pinfunction "1_1") (pintype "passive"))
    )
    (net (code "116") (name "Net-(F2-1-Pad1_1)") (class "Default")
      (node (ref "F2") (pin "1_1") (pinfunction "1_1_1") (pintype "passive"))
      (node (ref "F2") (pin "1_2") (pinfunction "1_1_2") (pintype "passive"))
      (node (ref "J8") (pin "2") (pinfunction "2_2") (pintype "passive"))
    )
    (net (code "117") (name "Net-(F3-1-Pad1_1)") (class "Default")
      (node (ref "F3") (pin "1_1") (pinfunction "1_1_1") (pintype "passive"))
      (node (ref "F3") (pin "1_2") (pinfunction "1_1_2") (pintype "passive"))
      (node (ref "J8") (pin "3") (pinfunction "3_3") (pintype "passive"))
    )
    (net (code "118") (name "Net-(IC1-ILIM)") (class "Default")
      (node (ref "IC1") (pin "5") (pinfunction "ILIM_5") (pintype "bidirectional"))
      (node (ref "R3") (pin "1") (pinfunction "1_1") (pintype "passive"))
    )
    (net (code "119") (name "Net-(IC2-ILIM)") (class "Default")
      (node (ref "IC2") (pin "5") (pinfunction "ILIM_5") (pintype "bidirectional"))
      (node (ref "R6") (pin "1") (pinfunction "1_1") (pintype "passive"))
    )
    (net (code "120") (name "Net-(IC3-ILIM)") (class "Default")
      (node (ref "IC3") (pin "5") (pinfunction "ILIM_5") (pintype "bidirectional"))
      (node (ref "R9") (pin "1") (pinfunction "1_1") (pintype "passive"))
    )
    (net (code "121") (name "Net-(IC4-OUT)") (class "Default")
      (node (ref "IC4") (pin "4") (pinfunction "OUT_4") (pintype "bidirectional"))
      (node (ref "R12") (pin "1") (pinfunction "1_1") (pintype "passive"))
      (node (ref "R14") (pin "1") (pinfunction "1_1") (pintype "passive"))
    )
    (net (code "122") (name "Net-(IC5-OUT)") (class "Default")
      (node (ref "IC5") (pin "4") (pinfunction "OUT_4") (pintype "bidirectional"))
      (node (ref "R15") (pin "2") (pinfunction "2_2") (pintype "passive"))
      (node (ref "R17") (pin "1") (pinfunction "1_1") (pintype "passive"))
    )
    (net (code "123") (name "Net-(IC6-OUT)") (class "Default")
      (node (ref "IC6") (pin "4") (pinfunction "OUT_4") (pintype "bidirectional"))
      (node (ref "R18") (pin "2") (pinfunction "2_2") (pintype "passive"))
      (node (ref "R20") (pin "1") (pinfunction "1_1") (pintype "passive"))
    )
    (net (code "124") (name "Net-(IC7-OUT)") (class "Default")
      (node (ref "IC7") (pin "4") (pinfunction "OUT_4") (pintype "bidirectional"))
      (node (ref "R21") (pin "2") (pinfunction "2_2") (pintype "passive"))
      (node (ref "R23") (pin "1") (pinfunction "1_1") (pintype "passive"))
    )
    (net (code "125") (name "Net-(IC8-ILIM)") (class "Default")
      (node (ref "IC8") (pin "5") (pinfunction "ILIM_5") (pintype "bidirectional"))
      (node (ref "R84") (pin "1") (pinfunction "1_1") (pintype "passive"))
    )
    (net (code "126") (name "Net-(IC9-ADDR0)") (class "Default")
      (node (ref "IC9") (pin "9") (pinfunction "ADDR0_9") (pintype "input"))
      (node (ref "R51") (pin "1") (pinfunction "1_1") (pintype "passive"))
    )
    (net (code "127") (name "Net-(IC9-SEL_PDO2)") (class "Default")
      (node (ref "IC9") (pin "8") (pinfunction "SEL_PDO2_8") (pintype "open_collector"))
      (node (ref "R48") (pin "2") (pinfunction "2_2") (pintype "passive"))
      (node (ref "R49") (pin "1") (pinfunction "1_1") (pintype "passive"))
    )
    (net (code "128") (name "Net-(IC9-SEL_PDO3)") (class "Default")
      (node (ref "IC9") (pin "7") (pinfunction "SEL_PDO3_7") (pintype "open_collector"))
      (node (ref "R47") (pin "2") (pinfunction "2_2") (pintype "passive"))
      (node (ref "R48") (pin "1") (pinfunction "1_1") (pintype "passive"))
    )
    (net (code "129") (name "Net-(IC9-SEL_PDO4)") (class "Default")
      (node (ref "IC9") (pin "10") (pinfunction "SEL_PDO4_10") (pintype "open_collector"))
      (node (ref "R46") (pin "2") (pinfunction "2_2") (pintype "passive"))
      (node (ref "R47") (pin "1") (pinfunction "1_1") (pintype "passive"))
    )
    (net (code "130") (name "Net-(IC9-SEL_PDO5)") (class "Default")
      (node (ref "IC9") (pin "11") (pinfunction "SEL_PDO5_11") (pintype "open_collector"))
      (node (ref "R11") (pin "2") (pinfunction "2_2") (pintype "passive"))
      (node (ref "R46") (pin "1") (pinfunction "1_1") (pintype "passive"))
    )
    (net (code "131") (name "Net-(IC9-VBUS_DISCH)") (class "Default")
      (node (ref "IC9") (pin "13") (pinfunction "VBUS_DISCH_13") (pintype "output"))
      (node (ref "R53") (pin "2") (pinfunction "2_2") (pintype "passive"))
      (node (ref "T6") (pin "4") (pinfunction "G_4") (pintype "passive"))
    )
    (net (code "132") (name "Net-(IC9-VBUS_EN_SRC)") (class "Default")
      (node (ref "IC9") (pin "14") (pinfunction "VBUS_EN_SRC_14") (pintype "open_collector"))
      (node (ref "R55") (pin "2") (pinfunction "2_2") (pintype "passive"))
    )
    (net (code "133") (name "Net-(IC9-VREG1V2)") (class "Default")
      (node (ref "C6") (pin "1") (pinfunction "1_1") (pintype "passive"))
      (node (ref "IC9") (pin "15") (pinfunction "VREG1V2_15") (pintype "input"))
    )
    (net (code "134") (name "Net-(IC9-VREG2V7)") (class "Default")
      (node (ref "C16") (pin "1") (pinfunction "1_1") (pintype "passive"))
      (node (ref "IC9") (pin "16") (pinfunction "VREG2V7_16") (pintype "input"))
    )
    (net (code "135") (name "Net-(IC10-BOOT1)") (class "Default")
      (node (ref "C63") (pin "2") (pinfunction "2_2") (pintype "passive"))
      (node (ref "IC10") (pin "22") (pinfunction "BOOT1_22") (pintype "power_in"))
    )
    (net (code "136") (name "Net-(IC10-BOOT2)") (class "Default")
      (node (ref "C64") (pin "2") (pinfunction "2_2") (pintype "passive"))
      (node (ref "IC10") (pin "20") (pinfunction "BOOT2_20") (pintype "power_in"))
    )
    (net (code "137") (name "Net-(IC10-CDC)") (class "Default")
      (node (ref "IC10") (pin "16") (pinfunction "CDC_16") (pintype "output"))
      (node (ref "R80") (pin "1") (pinfunction "1_1") (pintype "passive"))
    )
    (net (code "138") (name "Net-(IC10-COMP)") (class "Default")
      (node (ref "C61") (pin "1") (pinfunction "1_1") (pintype "passive"))
      (node (ref "IC10") (pin "18") (pinfunction "COMP_18") (pintype "input"))
      (node (ref "R81") (pin "1") (pinfunction "1_1") (pintype "passive"))
    )
    (net (code "139") (name "Net-(IC10-DITH_SYNC)") (class "Default")
      (node (ref "C60") (pin "1") (pinfunction "1_1") (pintype "passive"))
      (node (ref "IC10") (pin "7") (pinfunction "DITH_SYNC_7") (pintype "input"))
    )
    (net (code "140") (name "Net-(IC10-DR1H)") (class "Default")
      (node (ref "IC10") (pin "2") (pinfunction "DR1H_2") (pintype "output"))
      (node (ref "R85") (pin "1") (pinfunction "1_1") (pintype "passive"))
    )
    (net (code "141") (name "Net-(IC10-DR1L)") (class "Default")
      (node (ref "IC10") (pin "1") (pinfunction "DR1L_1") (pintype "output"))
      (node (ref "R83") (pin "1") (pinfunction "1_1") (pintype "passive"))
    )
    (net (code "142") (name "Net-(IC10-FB)") (class "Default")
      (node (ref "IC10") (pin "14") (pinfunction "FB_14") (pintype "input"))
      (node (ref "R56") (pin "2") (pinfunction "2_2") (pintype "passive"))
      (node (ref "R66") (pin "1") (pinfunction "1_1") (pintype "passive"))
    )
    (net (code "143") (name "Net-(IC10-FSW)") (class "Default")
      (node (ref "IC10") (pin "8") (pinfunction "FSW_8") (pintype "input"))
      (node (ref "R78") (pin "1") (pinfunction "1_1") (pintype "passive"))
    )
    (net (code "144") (name "Net-(IC10-ILIM)") (class "Default")
      (node (ref "IC10") (pin "17") (pinfunction "ILIM_17") (pintype "output"))
      (node (ref "R79") (pin "1") (pinfunction "1_1") (pintype "passive"))
    )
    (net (code "145") (name "Net-(IC10-MODE)") (class "Default")
      (node (ref "IC10") (pin "15") (pinfunction "MODE_15") (pintype "input"))
      (node (ref "R77") (pin "1") (pinfunction "1_1") (pintype "passive"))
    )
    (net (code "146") (name "Net-(IC10-SW1)") (class "Default")
      (node (ref "C63") (pin "1") (pinfunction "1_1") (pintype "passive"))
      (node (ref "IC10") (pin "23") (pinfunction "SW1_23") (pintype "power_in"))
      (node (ref "L3") (pin "1") (pinfunction "1_1") (pintype "passive"))
      (node (ref "R89") (pin "1") (pinfunction "1_1") (pintype "passive"))
      (node (ref "T4") (pin "5") (pinfunction "D_5") (pintype "passive"))
      (node (ref "T4") (pin "6") (pinfunction "D_6") (pintype "passive"))
      (node (ref "T4") (pin "7") (pinfunction "D_7") (pintype "passive"))
      (node (ref "T4") (pin "8") (pinfunction "D_8") (pintype "passive"))
      (node (ref "T4") (pin "9") (pinfunction "D_9") (pintype "passive"))
      (node (ref "T5") (pin "1") (pinfunction "S_1") (pintype "passive"))
      (node (ref "T5") (pin "2") (pinfunction "S_2") (pintype "passive"))
      (node (ref "T5") (pin "3") (pinfunction "S_3") (pintype "passive"))
    )
    (net (code "147") (name "Net-(IC10-VCC)") (class "Default")
      (node (ref "C59") (pin "1") (pinfunction "1_1") (pintype "passive"))
      (node (ref "IC10") (pin "19") (pinfunction "VCC_19") (pintype "power_in"))
    )
    (net (code "148") (name "Net-(IC12-BOOT1)") (class "Default")
      (node (ref "C45") (pin "2") (pinfunction "2_2") (pintype "passive"))
      (node (ref "IC12") (pin "22") (pinfunction "BOOT1_22") (pintype "power_in"))
    )
    (net (code "149") (name "Net-(IC12-BOOT2)") (class "Default")
      (node (ref "C46") (pin "2") (pinfunction "2_2") (pintype "passive"))
      (node (ref "IC12") (pin "20") (pinfunction "BOOT2_20") (pintype "power_in"))
    )
    (net (code "150") (name "Net-(IC12-CDC)") (class "Default")
      (node (ref "IC12") (pin "16") (pinfunction "CDC_16") (pintype "output"))
      (node (ref "R61") (pin "1") (pinfunction "1_1") (pintype "passive"))
    )
    (net (code "151") (name "Net-(IC12-COMP)") (class "Default")
      (node (ref "C43") (pin "1") (pinfunction "1_1") (pintype "passive"))
      (node (ref "IC12") (pin "18") (pinfunction "COMP_18") (pintype "input"))
      (node (ref "R62") (pin "1") (pinfunction "1_1") (pintype "passive"))
    )
    (net (code "152") (name "Net-(IC12-DITH_SYNC)") (class "Default")
      (node (ref "C42") (pin "1") (pinfunction "1_1") (pintype "passive"))
      (node (ref "IC12") (pin "7") (pinfunction "DITH_SYNC_7") (pintype "input"))
    )
    (net (code "153") (name "Net-(IC12-DR1H)") (class "Default")
      (node (ref "IC12") (pin "2") (pinfunction "DR1H_2") (pintype "output"))
      (node (ref "R65") (pin "1") (pinfunction "1_1") (pintype "passive"))
    )
    (net (code "154") (name "Net-(IC12-DR1L)") (class "Default")
      (node (ref "IC12") (pin "1") (pinfunction "DR1L_1") (pintype "output"))
      (node (ref "R64") (pin "1") (pinfunction "1_1") (pintype "passive"))
    )
    (net (code "155") (name "Net-(IC12-FB)") (class "Default")
      (node (ref "IC12") (pin "14") (pinfunction "FB_14") (pintype "input"))
      (node (ref "R11") (pin "1") (pinfunction "1_1") (pintype "passive"))
      (node (ref "R5") (pin "2") (pinfunction "2_2") (pintype "passive"))
    )
    (net (code "156") (name "Net-(IC12-FSW)") (class "Default")
      (node (ref "IC12") (pin "8") (pinfunction "FSW_8") (pintype "input"))
      (node (ref "R59") (pin "1") (pinfunction "1_1") (pintype "passive"))
    )
    (net (code "157") (name "Net-(IC12-ILIM)") (class "Default")
      (node (ref "IC12") (pin "17") (pinfunction "ILIM_17") (pintype "output"))
      (node (ref "R60") (pin "1") (pinfunction "1_1") (pintype "passive"))
    )
    (net (code "158") (name "Net-(IC12-MODE)") (class "Default")
      (node (ref "IC12") (pin "15") (pinfunction "MODE_15") (pintype "input"))
      (node (ref "R58") (pin "1") (pinfunction "1_1") (pintype "passive"))
    )
    (net (code "159") (name "Net-(IC12-SW1)") (class "Default")
      (node (ref "C45") (pin "1") (pinfunction "1_1") (pintype "passive"))
      (node (ref "IC12") (pin "23") (pinfunction "SW1_23") (pintype "power_in"))
      (node (ref "L2") (pin "1") (pinfunction "1_1") (pintype "passive"))
      (node (ref "R231") (pin "1") (pinfunction "1_1") (pintype "passive"))
      (node (ref "T10") (pin "1") (pinfunction "S_1") (pintype "passive"))
      (node (ref "T10") (pin "2") (pinfunction "S_2") (pintype "passive"))
      (node (ref "T10") (pin "3") (pinfunction "S_3") (pintype "passive"))
      (node (ref "T9") (pin "5") (pinfunction "D_5") (pintype "passive"))
      (node (ref "T9") (pin "6") (pinfunction "D_6") (pintype "passive"))
      (node (ref "T9") (pin "7") (pinfunction "D_7") (pintype "passive"))
      (node (ref "T9") (pin "8") (pinfunction "D_8") (pintype "passive"))
      (node (ref "T9") (pin "9") (pinfunction "D_9") (pintype "passive"))
    )
    (net (code "160") (name "Net-(IC12-VCC)") (class "Default")
      (node (ref "C41") (pin "1") (pinfunction "1_1") (pintype "passive"))
      (node (ref "IC12") (pin "19") (pinfunction "VCC_19") (pintype "power_in"))
    )
    (net (code "161") (name "Net-(IC14-ADDR0)") (class "Default")
      (node (ref "IC14") (pin "9") (pinfunction "ADDR0_9") (pintype "input"))
      (node (ref "R71") (pin "1") (pinfunction "1_1") (pintype "passive"))
    )
    (net (code "162") (name "Net-(IC14-SEL_PDO2)") (class "Default")
      (node (ref "IC14") (pin "8") (pinfunction "SEL_PDO2_8") (pintype "open_collector"))
      (node (ref "R69") (pin "2") (pinfunction "2_2") (pintype "passive"))
      (node (ref "R70") (pin "1") (pinfunction "1_1") (pintype "passive"))
    )
    (net (code "163") (name "Net-(IC14-SEL_PDO3)") (class "Default")
      (node (ref "IC14") (pin "7") (pinfunction "SEL_PDO3_7") (pintype "open_collector"))
      (node (ref "R68") (pin "2") (pinfunction "2_2") (pintype "passive"))
      (node (ref "R69") (pin "1") (pinfunction "1_1") (pintype "passive"))
    )
    (net (code "164") (name "Net-(IC14-SEL_PDO4)") (class "Default")
      (node (ref "IC14") (pin "10") (pinfunction "SEL_PDO4_10") (pintype "open_collector"))
      (node (ref "R67") (pin "2") (pinfunction "2_2") (pintype "passive"))
      (node (ref "R68") (pin "1") (pinfunction "1_1") (pintype "passive"))
    )
    (net (code "165") (name "Net-(IC14-SEL_PDO5)") (class "Default")
      (node (ref "IC14") (pin "11") (pinfunction "SEL_PDO5_11") (pintype "open_collector"))
      (node (ref "R66") (pin "2") (pinfunction "2_2") (pintype "passive"))
      (node (ref "R67") (pin "1") (pinfunction "1_1") (pintype "passive"))
    )
    (net (code "166") (name "Net-(IC14-VBUS_DISCH)") (class "Default")
      (node (ref "IC14") (pin "13") (pinfunction "VBUS_DISCH_13") (pintype "output"))
      (node (ref "R73") (pin "2") (pinfunction "2_2") (pintype "passive"))
      (node (ref "T1") (pin "4") (pinfunction "G_4") (pintype "passive"))
    )
    (net (code "167") (name "Net-(IC14-VBUS_EN_SRC)") (class "Default")
      (node (ref "IC14") (pin "14") (pinfunction "VBUS_EN_SRC_14") (pintype "open_collector"))
      (node (ref "R75") (pin "2") (pinfunction "2_2") (pintype "passive"))
    )
    (net (code "168") (name "Net-(IC14-VREG1V2)") (class "Default")
      (node (ref "C56") (pin "1") (pinfunction "1_1") (pintype "passive"))
      (node (ref "IC14") (pin "15") (pinfunction "VREG1V2_15") (pintype "input"))
    )
    (net (code "169") (name "Net-(IC14-VREG2V7)") (class "Default")
      (node (ref "C57") (pin "1") (pinfunction "1_1") (pintype "passive"))
      (node (ref "IC14") (pin "16") (pinfunction "VREG2V7_16") (pintype "input"))
    )
    (net (code "170") (name "Net-(IC15-BOOT1)") (class "Default")
      (node (ref "C92") (pin "2") (pinfunction "2_2") (pintype "passive"))
      (node (ref "IC15") (pin "22") (pinfunction "BOOT1_22") (pintype "power_in"))
    )
    (net (code "171") (name "Net-(IC15-BOOT2)") (class "Default")
      (node (ref "C93") (pin "2") (pinfunction "2_2") (pintype "passive"))
      (node (ref "IC15") (pin "20") (pinfunction "BOOT2_20") (pintype "power_in"))
    )
    (net (code "172") (name "Net-(IC15-CDC)") (class "Default")
      (node (ref "IC15") (pin "16") (pinfunction "CDC_16") (pintype "output"))
      (node (ref "R107") (pin "1") (pinfunction "1_1") (pintype "passive"))
    )
    (net (code "173") (name "Net-(IC15-COMP)") (class "Default")
      (node (ref "C90") (pin "1") (pinfunction "1_1") (pintype "passive"))
      (node (ref "IC15") (pin "18") (pinfunction "COMP_18") (pintype "input"))
      (node (ref "R108") (pin "1") (pinfunction "1_1") (pintype "passive"))
    )
    (net (code "174") (name "Net-(IC15-DITH_SYNC)") (class "Default")
      (node (ref "C89") (pin "1") (pinfunction "1_1") (pintype "passive"))
      (node (ref "IC15") (pin "7") (pinfunction "DITH_SYNC_7") (pintype "input"))
    )
    (net (code "175") (name "Net-(IC15-DR1H)") (class "Default")
      (node (ref "IC15") (pin "2") (pinfunction "DR1H_2") (pintype "output"))
      (node (ref "R111") (pin "1") (pinfunction "1_1") (pintype "passive"))
    )
    (net (code "176") (name "Net-(IC15-DR1L)") (class "Default")
      (node (ref "IC15") (pin "1") (pinfunction "DR1L_1") (pintype "output"))
      (node (ref "R110") (pin "1") (pinfunction "1_1") (pintype "passive"))
    )
    (net (code "177") (name "Net-(IC15-FB)") (class "Default")
      (node (ref "IC15") (pin "14") (pinfunction "FB_14") (pintype "input"))
      (node (ref "R92") (pin "2") (pinfunction "2_2") (pintype "passive"))
      (node (ref "R93") (pin "1") (pinfunction "1_1") (pintype "passive"))
    )
    (net (code "178") (name "Net-(IC15-FSW)") (class "Default")
      (node (ref "IC15") (pin "8") (pinfunction "FSW_8") (pintype "input"))
      (node (ref "R105") (pin "1") (pinfunction "1_1") (pintype "passive"))
    )
    (net (code "179") (name "Net-(IC15-ILIM)") (class "Default")
      (node (ref "IC15") (pin "17") (pinfunction "ILIM_17") (pintype "output"))
      (node (ref "R106") (pin "1") (pinfunction "1_1") (pintype "passive"))
    )
    (net (code "180") (name "Net-(IC15-MODE)") (class "Default")
      (node (ref "IC15") (pin "15") (pinfunction "MODE_15") (pintype "input"))
      (node (ref "R104") (pin "1") (pinfunction "1_1") (pintype "passive"))
    )
    (net (code "181") (name "Net-(IC15-SW1)") (class "Default")
      (node (ref "C92") (pin "1") (pinfunction "1_1") (pintype "passive"))
      (node (ref "IC15") (pin "23") (pinfunction "SW1_23") (pintype "power_in"))
      (node (ref "L4") (pin "1") (pinfunction "1_1") (pintype "passive"))
      (node (ref "R115") (pin "1") (pinfunction "1_1") (pintype "passive"))
      (node (ref "T14") (pin "5") (pinfunction "D_5") (pintype "passive"))
      (node (ref "T14") (pin "6") (pinfunction "D_6") (pintype "passive"))
      (node (ref "T14") (pin "7") (pinfunction "D_7") (pintype "passive"))
      (node (ref "T14") (pin "8") (pinfunction "D_8") (pintype "passive"))
      (node (ref "T14") (pin "9") (pinfunction "D_9") (pintype "passive"))
      (node (ref "T15") (pin "1") (pinfunction "S_1") (pintype "passive"))
      (node (ref "T15") (pin "2") (pinfunction "S_2") (pintype "passive"))
      (node (ref "T15") (pin "3") (pinfunction "S_3") (pintype "passive"))
    )
    (net (code "182") (name "Net-(IC15-VCC)") (class "Default")
      (node (ref "C88") (pin "1") (pinfunction "1_1") (pintype "passive"))
      (node (ref "IC15") (pin "19") (pinfunction "VCC_19") (pintype "power_in"))
    )
    (net (code "183") (name "Net-(IC17-ADDR0)") (class "Default")
      (node (ref "IC17") (pin "9") (pinfunction "ADDR0_9") (pintype "input"))
      (node (ref "R98") (pin "1") (pinfunction "1_1") (pintype "passive"))
    )
    (net (code "184") (name "Net-(IC17-SEL_PDO2)") (class "Default")
      (node (ref "IC17") (pin "8") (pinfunction "SEL_PDO2_8") (pintype "open_collector"))
      (node (ref "R96") (pin "2") (pinfunction "2_2") (pintype "passive"))
      (node (ref "R97") (pin "1") (pinfunction "1_1") (pintype "passive"))
    )
    (net (code "185") (name "Net-(IC17-SEL_PDO3)") (class "Default")
      (node (ref "IC17") (pin "7") (pinfunction "SEL_PDO3_7") (pintype "open_collector"))
      (node (ref "R95") (pin "2") (pinfunction "2_2") (pintype "passive"))
      (node (ref "R96") (pin "1") (pinfunction "1_1") (pintype "passive"))
    )
    (net (code "186") (name "Net-(IC17-SEL_PDO4)") (class "Default")
      (node (ref "IC17") (pin "10") (pinfunction "SEL_PDO4_10") (pintype "open_collector"))
      (node (ref "R94") (pin "2") (pinfunction "2_2") (pintype "passive"))
      (node (ref "R95") (pin "1") (pinfunction "1_1") (pintype "passive"))
    )
    (net (code "187") (name "Net-(IC17-SEL_PDO5)") (class "Default")
      (node (ref "IC17") (pin "11") (pinfunction "SEL_PDO5_11") (pintype "open_collector"))
      (node (ref "R93") (pin "2") (pinfunction "2_2") (pintype "passive"))
      (node (ref "R94") (pin "1") (pinfunction "1_1") (pintype "passive"))
    )
    (net (code "188") (name "Net-(IC17-VBUS_DISCH)") (class "Default")
      (node (ref "IC17") (pin "13") (pinfunction "VBUS_DISCH_13") (pintype "output"))
      (node (ref "R100") (pin "2") (pinfunction "2_2") (pintype "passive"))
      (node (ref "T11") (pin "4") (pinfunction "G_4") (pintype "passive"))
    )
    (net (code "189") (name "Net-(IC17-VBUS_EN_SRC)") (class "Default")
      (node (ref "IC17") (pin "14") (pinfunction "VBUS_EN_SRC_14") (pintype "open_collector"))
      (node (ref "R102") (pin "2") (pinfunction "2_2") (pintype "passive"))
    )
    (net (code "190") (name "Net-(IC17-VREG1V2)") (class "Default")
      (node (ref "C81") (pin "1") (pinfunction "1_1") (pintype "passive"))
      (node (ref "IC17") (pin "15") (pinfunction "VREG1V2_15") (pintype "input"))
    )
    (net (code "191") (name "Net-(IC17-VREG2V7)") (class "Default")
      (node (ref "C86") (pin "1") (pinfunction "1_1") (pintype "passive"))
      (node (ref "IC17") (pin "16") (pinfunction "VREG2V7_16") (pintype "input"))
    )
    (net (code "192") (name "Net-(IC18-BOOT1)") (class "Default")
      (node (ref "C117") (pin "2") (pinfunction "2_2") (pintype "passive"))
      (node (ref "IC18") (pin "22") (pinfunction "BOOT1_22") (pintype "power_in"))
    )
    (net (code "193") (name "Net-(IC18-BOOT2)") (class "Default")
      (node (ref "C118") (pin "2") (pinfunction "2_2") (pintype "passive"))
      (node (ref "IC18") (pin "20") (pinfunction "BOOT2_20") (pintype "power_in"))
    )
    (net (code "194") (name "Net-(IC18-CDC)") (class "Default")
      (node (ref "IC18") (pin "16") (pinfunction "CDC_16") (pintype "output"))
      (node (ref "R133") (pin "1") (pinfunction "1_1") (pintype "passive"))
    )
    (net (code "195") (name "Net-(IC18-COMP)") (class "Default")
      (node (ref "C115") (pin "1") (pinfunction "1_1") (pintype "passive"))
      (node (ref "IC18") (pin "18") (pinfunction "COMP_18") (pintype "input"))
      (node (ref "R134") (pin "1") (pinfunction "1_1") (pintype "passive"))
    )
    (net (code "196") (name "Net-(IC18-DITH_SYNC)") (class "Default")
      (node (ref "C114") (pin "1") (pinfunction "1_1") (pintype "passive"))
      (node (ref "IC18") (pin "7") (pinfunction "DITH_SYNC_7") (pintype "input"))
    )
    (net (code "197") (name "Net-(IC18-DR1H)") (class "Default")
      (node (ref "IC18") (pin "2") (pinfunction "DR1H_2") (pintype "output"))
      (node (ref "R137") (pin "1") (pinfunction "1_1") (pintype "passive"))
    )
    (net (code "198") (name "Net-(IC18-DR1L)") (class "Default")
      (node (ref "IC18") (pin "1") (pinfunction "DR1L_1") (pintype "output"))
      (node (ref "R136") (pin "1") (pinfunction "1_1") (pintype "passive"))
    )
    (net (code "199") (name "Net-(IC18-FB)") (class "Default")
      (node (ref "IC18") (pin "14") (pinfunction "FB_14") (pintype "input"))
      (node (ref "R118") (pin "2") (pinfunction "2_2") (pintype "passive"))
      (node (ref "R119") (pin "1") (pinfunction "1_1") (pintype "passive"))
    )
    (net (code "200") (name "Net-(IC18-FSW)") (class "Default")
      (node (ref "IC18") (pin "8") (pinfunction "FSW_8") (pintype "input"))
      (node (ref "R131") (pin "1") (pinfunction "1_1") (pintype "passive"))
    )
    (net (code "201") (name "Net-(IC18-ILIM)") (class "Default")
      (node (ref "IC18") (pin "17") (pinfunction "ILIM_17") (pintype "output"))
      (node (ref "R132") (pin "1") (pinfunction "1_1") (pintype "passive"))
    )
    (net (code "202") (name "Net-(IC18-MODE)") (class "Default")
      (node (ref "IC18") (pin "15") (pinfunction "MODE_15") (pintype "input"))
      (node (ref "R130") (pin "1") (pinfunction "1_1") (pintype "passive"))
    )
    (net (code "203") (name "Net-(IC18-SW1)") (class "Default")
      (node (ref "C117") (pin "1") (pinfunction "1_1") (pintype "passive"))
      (node (ref "IC18") (pin "23") (pinfunction "SW1_23") (pintype "power_in"))
      (node (ref "L5") (pin "1") (pinfunction "1_1") (pintype "passive"))
      (node (ref "R141") (pin "1") (pinfunction "1_1") (pintype "passive"))
      (node (ref "T19") (pin "5") (pinfunction "D_5") (pintype "passive"))
      (node (ref "T19") (pin "6") (pinfunction "D_6") (pintype "passive"))
      (node (ref "T19") (pin "7") (pinfunction "D_7") (pintype "passive"))
      (node (ref "T19") (pin "8") (pinfunction "D_8") (pintype "passive"))
      (node (ref "T19") (pin "9") (pinfunction "D_9") (pintype "passive"))
      (node (ref "T20") (pin "1") (pinfunction "S_1") (pintype "passive"))
      (node (ref "T20") (pin "2") (pinfunction "S_2") (pintype "passive"))
      (node (ref "T20") (pin "3") (pinfunction "S_3") (pintype "passive"))
    )
    (net (code "204") (name "Net-(IC18-VCC)") (class "Default")
      (node (ref "C113") (pin "1") (pinfunction "1_1") (pintype "passive"))
      (node (ref "IC18") (pin "19") (pinfunction "VCC_19") (pintype "power_in"))
    )
    (net (code "205") (name "Net-(IC20-ADDR0)") (class "Default")
      (node (ref "IC20") (pin "9") (pinfunction "ADDR0_9") (pintype "input"))
      (node (ref "R124") (pin "1") (pinfunction "1_1") (pintype "passive"))
    )
    (net (code "206") (name "Net-(IC20-SEL_PDO2)") (class "Default")
      (node (ref "IC20") (pin "8") (pinfunction "SEL_PDO2_8") (pintype "open_collector"))
      (node (ref "R122") (pin "2") (pinfunction "2_2") (pintype "passive"))
      (node (ref "R123") (pin "1") (pinfunction "1_1") (pintype "passive"))
    )
    (net (code "207") (name "Net-(IC20-SEL_PDO3)") (class "Default")
      (node (ref "IC20") (pin "7") (pinfunction "SEL_PDO3_7") (pintype "open_collector"))
      (node (ref "R121") (pin "2") (pinfunction "2_2") (pintype "passive"))
      (node (ref "R122") (pin "1") (pinfunction "1_1") (pintype "passive"))
    )
    (net (code "208") (name "Net-(IC20-SEL_PDO4)") (class "Default")
      (node (ref "IC20") (pin "10") (pinfunction "SEL_PDO4_10") (pintype "open_collector"))
      (node (ref "R120") (pin "2") (pinfunction "2_2") (pintype "passive"))
      (node (ref "R121") (pin "1") (pinfunction "1_1") (pintype "passive"))
    )
    (net (code "209") (name "Net-(IC20-SEL_PDO5)") (class "Default")
      (node (ref "IC20") (pin "11") (pinfunction "SEL_PDO5_11") (pintype "open_collector"))
      (node (ref "R119") (pin "2") (pinfunction "2_2") (pintype "passive"))
      (node (ref "R120") (pin "1") (pinfunction "1_1") (pintype "passive"))
    )
    (net (code "210") (name "Net-(IC20-VBUS_DISCH)") (class "Default")
      (node (ref "IC20") (pin "13") (pinfunction "VBUS_DISCH_13") (pintype "output"))
      (node (ref "R126") (pin "2") (pinfunction "2_2") (pintype "passive"))
      (node (ref "T16") (pin "4") (pinfunction "G_4") (pintype "passive"))
    )
    (net (code "211") (name "Net-(IC20-VBUS_EN_SRC)") (class "Default")
      (node (ref "IC20") (pin "14") (pinfunction "VBUS_EN_SRC_14") (pintype "open_collector"))
      (node (ref "R128") (pin "2") (pinfunction "2_2") (pintype "passive"))
    )
    (net (code "212") (name "Net-(IC20-VREG1V2)") (class "Default")
      (node (ref "C110") (pin "1") (pinfunction "1_1") (pintype "passive"))
      (node (ref "IC20") (pin "15") (pinfunction "VREG1V2_15") (pintype "input"))
    )
    (net (code "213") (name "Net-(IC20-VREG2V7)") (class "Default")
      (node (ref "C111") (pin "1") (pinfunction "1_1") (pintype "passive"))
      (node (ref "IC20") (pin "16") (pinfunction "VREG2V7_16") (pintype "input"))
    )
    (net (code "214") (name "Net-(IC21-BOOT1)") (class "Default")
      (node (ref "C142") (pin "2") (pinfunction "2_2") (pintype "passive"))
      (node (ref "IC21") (pin "22") (pinfunction "BOOT1_22") (pintype "power_in"))
    )
    (net (code "215") (name "Net-(IC21-BOOT2)") (class "Default")
      (node (ref "C143") (pin "2") (pinfunction "2_2") (pintype "passive"))
      (node (ref "IC21") (pin "20") (pinfunction "BOOT2_20") (pintype "power_in"))
    )
    (net (code "216") (name "Net-(IC21-CDC)") (class "Default")
      (node (ref "IC21") (pin "16") (pinfunction "CDC_16") (pintype "output"))
      (node (ref "R159") (pin "1") (pinfunction "1_1") (pintype "passive"))
    )
    (net (code "217") (name "Net-(IC21-COMP)") (class "Default")
      (node (ref "C140") (pin "1") (pinfunction "1_1") (pintype "passive"))
      (node (ref "IC21") (pin "18") (pinfunction "COMP_18") (pintype "input"))
      (node (ref "R160") (pin "1") (pinfunction "1_1") (pintype "passive"))
    )
    (net (code "218") (name "Net-(IC21-DITH_SYNC)") (class "Default")
      (node (ref "C139") (pin "1") (pinfunction "1_1") (pintype "passive"))
      (node (ref "IC21") (pin "7") (pinfunction "DITH_SYNC_7") (pintype "input"))
    )
    (net (code "219") (name "Net-(IC21-DR1H)") (class "Default")
      (node (ref "IC21") (pin "2") (pinfunction "DR1H_2") (pintype "output"))
      (node (ref "R163") (pin "1") (pinfunction "1_1") (pintype "passive"))
    )
    (net (code "220") (name "Net-(IC21-DR1L)") (class "Default")
      (node (ref "IC21") (pin "1") (pinfunction "DR1L_1") (pintype "output"))
      (node (ref "R162") (pin "1") (pinfunction "1_1") (pintype "passive"))
    )
    (net (code "221") (name "Net-(IC21-FB)") (class "Default")
      (node (ref "IC21") (pin "14") (pinfunction "FB_14") (pintype "input"))
      (node (ref "R144") (pin "2") (pinfunction "2_2") (pintype "passive"))
      (node (ref "R145") (pin "1") (pinfunction "1_1") (pintype "passive"))
    )
    (net (code "222") (name "Net-(IC21-FSW)") (class "Default")
      (node (ref "IC21") (pin "8") (pinfunction "FSW_8") (pintype "input"))
      (node (ref "R157") (pin "1") (pinfunction "1_1") (pintype "passive"))
    )
    (net (code "223") (name "Net-(IC21-ILIM)") (class "Default")
      (node (ref "IC21") (pin "17") (pinfunction "ILIM_17") (pintype "output"))
      (node (ref "R158") (pin "1") (pinfunction "1_1") (pintype "passive"))
    )
    (net (code "224") (name "Net-(IC21-MODE)") (class "Default")
      (node (ref "IC21") (pin "15") (pinfunction "MODE_15") (pintype "input"))
      (node (ref "R156") (pin "1") (pinfunction "1_1") (pintype "passive"))
    )
    (net (code "225") (name "Net-(IC21-SW1)") (class "Default")
      (node (ref "C142") (pin "1") (pinfunction "1_1") (pintype "passive"))
      (node (ref "IC21") (pin "23") (pinfunction "SW1_23") (pintype "power_in"))
      (node (ref "L6") (pin "1") (pinfunction "1_1") (pintype "passive"))
      (node (ref "R167") (pin "1") (pinfunction "1_1") (pintype "passive"))
      (node (ref "T24") (pin "5") (pinfunction "D_5") (pintype "passive"))
      (node (ref "T24") (pin "6") (pinfunction "D_6") (pintype "passive"))
      (node (ref "T24") (pin "7") (pinfunction "D_7") (pintype "passive"))
      (node (ref "T24") (pin "8") (pinfunction "D_8") (pintype "passive"))
      (node (ref "T24") (pin "9") (pinfunction "D_9") (pintype "passive"))
      (node (ref "T25") (pin "1") (pinfunction "S_1") (pintype "passive"))
      (node (ref "T25") (pin "2") (pinfunction "S_2") (pintype "passive"))
      (node (ref "T25") (pin "3") (pinfunction "S_3") (pintype "passive"))
    )
    (net (code "226") (name "Net-(IC21-VCC)") (class "Default")
      (node (ref "C138") (pin "1") (pinfunction "1_1") (pintype "passive"))
      (node (ref "IC21") (pin "19") (pinfunction "VCC_19") (pintype "power_in"))
    )
    (net (code "227") (name "Net-(IC23-ADDR0)") (class "Default")
      (node (ref "IC23") (pin "9") (pinfunction "ADDR0_9") (pintype "input"))
      (node (ref "R150") (pin "1") (pinfunction "1_1") (pintype "passive"))
    )
    (net (code "228") (name "Net-(IC23-SEL_PDO2)") (class "Default")
      (node (ref "IC23") (pin "8") (pinfunction "SEL_PDO2_8") (pintype "open_collector"))
      (node (ref "R148") (pin "2") (pinfunction "2_2") (pintype "passive"))
      (node (ref "R149") (pin "1") (pinfunction "1_1") (pintype "passive"))
    )
    (net (code "229") (name "Net-(IC23-SEL_PDO3)") (class "Default")
      (node (ref "IC23") (pin "7") (pinfunction "SEL_PDO3_7") (pintype "open_collector"))
      (node (ref "R147") (pin "2") (pinfunction "2_2") (pintype "passive"))
      (node (ref "R148") (pin "1") (pinfunction "1_1") (pintype "passive"))
    )
    (net (code "230") (name "Net-(IC23-SEL_PDO4)") (class "Default")
      (node (ref "IC23") (pin "10") (pinfunction "SEL_PDO4_10") (pintype "open_collector"))
      (node (ref "R146") (pin "2") (pinfunction "2_2") (pintype "passive"))
      (node (ref "R147") (pin "1") (pinfunction "1_1") (pintype "passive"))
    )
    (net (code "231") (name "Net-(IC23-SEL_PDO5)") (class "Default")
      (node (ref "IC23") (pin "11") (pinfunction "SEL_PDO5_11") (pintype "open_collector"))
      (node (ref "R145") (pin "2") (pinfunction "2_2") (pintype "passive"))
      (node (ref "R146") (pin "1") (pinfunction "1_1") (pintype "passive"))
    )
    (net (code "232") (name "Net-(IC23-VBUS_DISCH)") (class "Default")
      (node (ref "IC23") (pin "13") (pinfunction "VBUS_DISCH_13") (pintype "output"))
      (node (ref "R152") (pin "2") (pinfunction "2_2") (pintype "passive"))
      (node (ref "T21") (pin "4") (pinfunction "G_4") (pintype "passive"))
    )
    (net (code "233") (name "Net-(IC23-VBUS_EN_SRC)") (class "Default")
      (node (ref "IC23") (pin "14") (pinfunction "VBUS_EN_SRC_14") (pintype "open_collector"))
      (node (ref "R154") (pin "2") (pinfunction "2_2") (pintype "passive"))
    )
    (net (code "234") (name "Net-(IC23-VREG1V2)") (class "Default")
      (node (ref "C135") (pin "1") (pinfunction "1_1") (pintype "passive"))
      (node (ref "IC23") (pin "15") (pinfunction "VREG1V2_15") (pintype "input"))
    )
    (net (code "235") (name "Net-(IC23-VREG2V7)") (class "Default")
      (node (ref "C136") (pin "1") (pinfunction "1_1") (pintype "passive"))
      (node (ref "IC23") (pin "16") (pinfunction "VREG2V7_16") (pintype "input"))
    )
    (net (code "236") (name "Net-(IC24-BOOT1)") (class "Default")
      (node (ref "C167") (pin "2") (pinfunction "2_2") (pintype "passive"))
      (node (ref "IC24") (pin "22") (pinfunction "BOOT1_22") (pintype "power_in"))
    )
    (net (code "237") (name "Net-(IC24-BOOT2)") (class "Default")
      (node (ref "C168") (pin "2") (pinfunction "2_2") (pintype "passive"))
      (node (ref "IC24") (pin "20") (pinfunction "BOOT2_20") (pintype "power_in"))
    )
    (net (code "238") (name "Net-(IC24-CDC)") (class "Default")
      (node (ref "IC24") (pin "16") (pinfunction "CDC_16") (pintype "output"))
      (node (ref "R185") (pin "1") (pinfunction "1_1") (pintype "passive"))
    )
    (net (code "239") (name "Net-(IC24-COMP)") (class "Default")
      (node (ref "C165") (pin "1") (pinfunction "1_1") (pintype "passive"))
      (node (ref "IC24") (pin "18") (pinfunction "COMP_18") (pintype "input"))
      (node (ref "R186") (pin "1") (pinfunction "1_1") (pintype "passive"))
    )
    (net (code "240") (name "Net-(IC24-DITH_SYNC)") (class "Default")
      (node (ref "C164") (pin "1") (pinfunction "1_1") (pintype "passive"))
      (node (ref "IC24") (pin "7") (pinfunction "DITH_SYNC_7") (pintype "input"))
    )
    (net (code "241") (name "Net-(IC24-DR1H)") (class "Default")
      (node (ref "IC24") (pin "2") (pinfunction "DR1H_2") (pintype "output"))
      (node (ref "R189") (pin "1") (pinfunction "1_1") (pintype "passive"))
    )
    (net (code "242") (name "Net-(IC24-DR1L)") (class "Default")
      (node (ref "IC24") (pin "1") (pinfunction "DR1L_1") (pintype "output"))
      (node (ref "R188") (pin "1") (pinfunction "1_1") (pintype "passive"))
    )
    (net (code "243") (name "Net-(IC24-FB)") (class "Default")
      (node (ref "IC24") (pin "14") (pinfunction "FB_14") (pintype "input"))
      (node (ref "R170") (pin "2") (pinfunction "2_2") (pintype "passive"))
      (node (ref "R171") (pin "1") (pinfunction "1_1") (pintype "passive"))
    )
    (net (code "244") (name "Net-(IC24-FSW)") (class "Default")
      (node (ref "IC24") (pin "8") (pinfunction "FSW_8") (pintype "input"))
      (node (ref "R183") (pin "1") (pinfunction "1_1") (pintype "passive"))
    )
    (net (code "245") (name "Net-(IC24-ILIM)") (class "Default")
      (node (ref "IC24") (pin "17") (pinfunction "ILIM_17") (pintype "output"))
      (node (ref "R184") (pin "1") (pinfunction "1_1") (pintype "passive"))
    )
    (net (code "246") (name "Net-(IC24-MODE)") (class "Default")
      (node (ref "IC24") (pin "15") (pinfunction "MODE_15") (pintype "input"))
      (node (ref "R182") (pin "1") (pinfunction "1_1") (pintype "passive"))
    )
    (net (code "247") (name "Net-(IC24-SW1)") (class "Default")
      (node (ref "C167") (pin "1") (pinfunction "1_1") (pintype "passive"))
      (node (ref "IC24") (pin "23") (pinfunction "SW1_23") (pintype "power_in"))
      (node (ref "L7") (pin "1") (pinfunction "1_1") (pintype "passive"))
      (node (ref "R193") (pin "1") (pinfunction "1_1") (pintype "passive"))
      (node (ref "T29") (pin "5") (pinfunction "D_5") (pintype "passive"))
      (node (ref "T29") (pin "6") (pinfunction "D_6") (pintype "passive"))
      (node (ref "T29") (pin "7") (pinfunction "D_7") (pintype "passive"))
      (node (ref "T29") (pin "8") (pinfunction "D_8") (pintype "passive"))
      (node (ref "T29") (pin "9") (pinfunction "D_9") (pintype "passive"))
      (node (ref "T30") (pin "1") (pinfunction "S_1") (pintype "passive"))
      (node (ref "T30") (pin "2") (pinfunction "S_2") (pintype "passive"))
      (node (ref "T30") (pin "3") (pinfunction "S_3") (pintype "passive"))
    )
    (net (code "248") (name "Net-(IC24-VCC)") (class "Default")
      (node (ref "C163") (pin "1") (pinfunction "1_1") (pintype "passive"))
      (node (ref "IC24") (pin "19") (pinfunction "VCC_19") (pintype "power_in"))
    )
    (net (code "249") (name "Net-(IC26C-ADC_AVDD)") (class "Default")
      (node (ref "C191") (pin "1") (pinfunction "1_1") (pintype "passive"))
      (node (ref "IC26") (pin "59") (pinfunction "ADC_AVDD_59") (pintype "power_in"))
      (node (ref "R28") (pin "1") (pinfunction "1_1") (pintype "passive"))
      (node (ref "R29") (pin "2") (pinfunction "2_2") (pintype "passive"))
    )
    (net (code "250") (name "Net-(IC26C-USB_DM)") (class "Default")
      (node (ref "IC26") (pin "66") (pinfunction "USB_DM_66") (pintype "bidirectional"))
      (node (ref "R25") (pin "2") (pinfunction "2_2") (pintype "passive"))
    )
    (net (code "251") (name "Net-(IC26C-USB_DP)") (class "Default")
      (node (ref "IC26") (pin "67") (pinfunction "USB_DP_67") (pintype "bidirectional"))
      (node (ref "R26") (pin "2") (pinfunction "2_2") (pintype "passive"))
    )
    (net (code "252") (name "Net-(IC26C-VREG_AVDD)") (class "Default")
      (node (ref "C21") (pin "1") (pinfunction "1_1") (pintype "passive"))
      (node (ref "IC26") (pin "61") (pinfunction "VREG_AVDD_61") (pintype "power_in"))
      (node (ref "R27") (pin "2") (pinfunction "2_2") (pintype "passive"))
    )
    (net (code "253") (name "Net-(IC26C-VREG_LX)") (class "Default")
      (node (ref "IC26") (pin "63") (pinfunction "VREG_LX_63") (pintype "power_in"))
      (node (ref "L1") (pin "1") (pinfunction "1_1") (pintype "passive"))
    )
    (net (code "254") (name "Net-(IC26C-XIN)") (class "Default")
      (node (ref "C177") (pin "1") (pinfunction "1_1") (pintype "passive"))
      (node (ref "IC26") (pin "30") (pinfunction "XIN_30") (pintype "input"))
      (node (ref "X1") (pin "1") (pinfunction "1_1") (pintype "passive"))
    )
    (net (code "255") (name "Net-(IC26C-XOUT)") (class "Default")
      (node (ref "IC26") (pin "31") (pinfunction "XOUT_31") (pintype "output"))
      (node (ref "R211") (pin "2") (pinfunction "2_2") (pintype "passive"))
    )
    (net (code "256") (name "Net-(IC28-+IN)") (class "Default")
      (node (ref "C179") (pin "1") (pinfunction "1_1") (pintype "passive"))
      (node (ref "C180") (pin "1") (pinfunction "1_1") (pintype "passive"))
      (node (ref "IC28") (pin "3") (pinfunction "+IN_3") (pintype "input"))
      (node (ref "R212") (pin "1") (pinfunction "1_1") (pintype "passive"))
      (node (ref "REF1") (pin "1") (pinfunction "C_1") (pintype "passive"))
      (node (ref "VREF") (pin "TP") (pinfunction "P$1_TP") (pintype "bidirectional"))
    )
    (net (code "257") (name "Net-(IC29-A0)") (class "Default")
      (node (ref "IC29") (pin "1") (pinfunction "A0_1") (pintype "bidirectional"))
      (node (ref "R213") (pin "1") (pinfunction "1_1") (pintype "passive"))
      (node (ref "R214") (pin "2") (pinfunction "2_2") (pintype "passive"))
    )
    (net (code "258") (name "Net-(IC30-ADDR0)") (class "Default")
      (node (ref "IC30") (pin "9") (pinfunction "ADDR0_9") (pintype "input"))
      (node (ref "R176") (pin "1") (pinfunction "1_1") (pintype "passive"))
    )
    (net (code "259") (name "Net-(IC30-SEL_PDO2)") (class "Default")
      (node (ref "IC30") (pin "8") (pinfunction "SEL_PDO2_8") (pintype "open_collector"))
      (node (ref "R174") (pin "2") (pinfunction "2_2") (pintype "passive"))
      (node (ref "R175") (pin "1") (pinfunction "1_1") (pintype "passive"))
    )
    (net (code "260") (name "Net-(IC30-SEL_PDO3)") (class "Default")
      (node (ref "IC30") (pin "7") (pinfunction "SEL_PDO3_7") (pintype "open_collector"))
      (node (ref "R173") (pin "2") (pinfunction "2_2") (pintype "passive"))
      (node (ref "R174") (pin "1") (pinfunction "1_1") (pintype "passive"))
    )
    (net (code "261") (name "Net-(IC30-SEL_PDO4)") (class "Default")
      (node (ref "IC30") (pin "10") (pinfunction "SEL_PDO4_10") (pintype "open_collector"))
      (node (ref "R172") (pin "2") (pinfunction "2_2") (pintype "passive"))
      (node (ref "R173") (pin "1") (pinfunction "1_1") (pintype "passive"))
    )
    (net (code "262") (name "Net-(IC30-SEL_PDO5)") (class "Default")
      (node (ref "IC30") (pin "11") (pinfunction "SEL_PDO5_11") (pintype "open_collector"))
      (node (ref "R171") (pin "2") (pinfunction "2_2") (pintype "passive"))
      (node (ref "R172") (pin "1") (pinfunction "1_1") (pintype "passive"))
    )
    (net (code "263") (name "Net-(IC30-VBUS_DISCH)") (class "Default")
      (node (ref "IC30") (pin "13") (pinfunction "VBUS_DISCH_13") (pintype "output"))
      (node (ref "R178") (pin "2") (pinfunction "2_2") (pintype "passive"))
      (node (ref "T26") (pin "4") (pinfunction "G_4") (pintype "passive"))
    )
    (net (code "264") (name "Net-(IC30-VBUS_EN_SRC)") (class "Default")
      (node (ref "IC30") (pin "14") (pinfunction "VBUS_EN_SRC_14") (pintype "open_collector"))
      (node (ref "R180") (pin "2") (pinfunction "2_2") (pintype "passive"))
    )
    (net (code "265") (name "Net-(IC30-VREG1V2)") (class "Default")
      (node (ref "C160") (pin "1") (pinfunction "1_1") (pintype "passive"))
      (node (ref "IC30") (pin "15") (pinfunction "VREG1V2_15") (pintype "input"))
    )
    (net (code "266") (name "Net-(IC30-VREG2V7)") (class "Default")
      (node (ref "C161") (pin "1") (pinfunction "1_1") (pintype "passive"))
      (node (ref "IC30") (pin "16") (pinfunction "VREG2V7_16") (pintype "input"))
    )
    (net (code "267") (name "Net-(IC31-1V2O)") (class "Default")
      (node (ref "C35") (pin "1") (pinfunction "1_1") (pintype "passive"))
      (node (ref "IC31") (pin "22") (pinfunction "1V2O_22") (pintype "output"))
    )
    (net (code "268") (name "Net-(IC31-EXRES1)") (class "Default")
      (node (ref "IC31") (pin "10") (pinfunction "EXRES1_10") (pintype "bidirectional"))
      (node (ref "R45") (pin "2") (pinfunction "2_2") (pintype "passive"))
    )
    (net (code "269") (name "Net-(IC31-TOCAP)") (class "Default")
      (node (ref "C36") (pin "1") (pinfunction "1_1") (pintype "passive"))
      (node (ref "IC31") (pin "20") (pinfunction "TOCAP_20") (pintype "output"))
    )
    (net (code "270") (name "Net-(IC31-XI)") (class "Default")
      (node (ref "C38") (pin "1") (pinfunction "1_1") (pintype "passive"))
      (node (ref "IC31") (pin "30") (pinfunction "XI_30") (pintype "input"))
      (node (ref "R205") (pin "1") (pinfunction "1_1") (pintype "passive"))
      (node (ref "X2") (pin "3") (pinfunction "2_3") (pintype "passive"))
    )
    (net (code "271") (name "Net-(IC31-XO)") (class "Default")
      (node (ref "C37") (pin "1") (pinfunction "1_1") (pintype "passive"))
      (node (ref "IC31") (pin "31") (pinfunction "XO_31") (pintype "output"))
      (node (ref "R205") (pin "2") (pinfunction "2_2") (pintype "passive"))
      (node (ref "X2") (pin "1") (pinfunction "1_1") (pintype "passive"))
    )
    (net (code "272") (name "Net-(IC32-BOOT1)") (class "Default")
      (node (ref "C220") (pin "2") (pinfunction "2_2") (pintype "passive"))
      (node (ref "IC32") (pin "22") (pinfunction "BOOT1_22") (pintype "power_in"))
    )
    (net (code "273") (name "Net-(IC32-BOOT2)") (class "Default")
      (node (ref "C230") (pin "2") (pinfunction "2_2") (pintype "passive"))
      (node (ref "IC32") (pin "20") (pinfunction "BOOT2_20") (pintype "power_in"))
    )
    (net (code "274") (name "Net-(IC32-CDC)") (class "Default")
      (node (ref "IC32") (pin "16") (pinfunction "CDC_16") (pintype "output"))
      (node (ref "R224") (pin "1") (pinfunction "1_1") (pintype "passive"))
    )
    (net (code "275") (name "Net-(IC32-COMP)") (class "Default")
      (node (ref "C211") (pin "1") (pinfunction "1_1") (pintype "passive"))
      (node (ref "IC32") (pin "18") (pinfunction "COMP_18") (pintype "input"))
      (node (ref "R233") (pin "1") (pinfunction "1_1") (pintype "passive"))
    )
    (net (code "276") (name "Net-(IC32-DITH_SYNC)") (class "Default")
      (node (ref "C210") (pin "1") (pinfunction "1_1") (pintype "passive"))
      (node (ref "IC32") (pin "7") (pinfunction "DITH_SYNC_7") (pintype "input"))
    )
    (net (code "277") (name "Net-(IC32-DR1H)") (class "Default")
      (node (ref "IC32") (pin "2") (pinfunction "DR1H_2") (pintype "output"))
      (node (ref "R236") (pin "1") (pinfunction "1_1") (pintype "passive"))
    )
    (net (code "278") (name "Net-(IC32-DR1L)") (class "Default")
      (node (ref "IC32") (pin "1") (pinfunction "DR1L_1") (pintype "output"))
      (node (ref "R235") (pin "1") (pinfunction "1_1") (pintype "passive"))
    )
    (net (code "279") (name "Net-(IC32-FB)") (class "Default")
      (node (ref "IC32") (pin "14") (pinfunction "FB_14") (pintype "input"))
      (node (ref "R196") (pin "2") (pinfunction "2_2") (pintype "passive"))
      (node (ref "R197") (pin "1") (pinfunction "1_1") (pintype "passive"))
    )
    (net (code "280") (name "Net-(IC32-FSW)") (class "Default")
      (node (ref "IC32") (pin "8") (pinfunction "FSW_8") (pintype "input"))
      (node (ref "R222") (pin "1") (pinfunction "1_1") (pintype "passive"))
    )
    (net (code "281") (name "Net-(IC32-ILIM)") (class "Default")
      (node (ref "IC32") (pin "17") (pinfunction "ILIM_17") (pintype "output"))
      (node (ref "R223") (pin "1") (pinfunction "1_1") (pintype "passive"))
    )
    (net (code "282") (name "Net-(IC32-MODE)") (class "Default")
      (node (ref "IC32") (pin "15") (pinfunction "MODE_15") (pintype "input"))
      (node (ref "R221") (pin "1") (pinfunction "1_1") (pintype "passive"))
    )
    (net (code "283") (name "Net-(IC32-SW1)") (class "Default")
      (node (ref "C220") (pin "1") (pinfunction "1_1") (pintype "passive"))
      (node (ref "IC32") (pin "23") (pinfunction "SW1_23") (pintype "power_in"))
      (node (ref "L8") (pin "1") (pinfunction "1_1") (pintype "passive"))
      (node (ref "R240") (pin "1") (pinfunction "1_1") (pintype "passive"))
      (node (ref "T34") (pin "5") (pinfunction "D_5") (pintype "passive"))
      (node (ref "T34") (pin "6") (pinfunction "D_6") (pintype "passive"))
      (node (ref "T34") (pin "7") (pinfunction "D_7") (pintype "passive"))
      (node (ref "T34") (pin "8") (pinfunction "D_8") (pintype "passive"))
      (node (ref "T34") (pin "9") (pinfunction "D_9") (pintype "passive"))
      (node (ref "T35") (pin "1") (pinfunction "S_1") (pintype "passive"))
      (node (ref "T35") (pin "2") (pinfunction "S_2") (pintype "passive"))
      (node (ref "T35") (pin "3") (pinfunction "S_3") (pintype "passive"))
    )
    (net (code "284") (name "Net-(IC32-VCC)") (class "Default")
      (node (ref "C209") (pin "1") (pinfunction "1_1") (pintype "passive"))
      (node (ref "IC32") (pin "19") (pinfunction "VCC_19") (pintype "power_in"))
    )
    (net (code "285") (name "Net-(IC34-ADDR0)") (class "Default")
      (node (ref "IC34") (pin "9") (pinfunction "ADDR0_9") (pintype "input"))
      (node (ref "R202") (pin "1") (pinfunction "1_1") (pintype "passive"))
    )
    (net (code "286") (name "Net-(IC34-SEL_PDO2)") (class "Default")
      (node (ref "IC34") (pin "8") (pinfunction "SEL_PDO2_8") (pintype "open_collector"))
      (node (ref "R200") (pin "2") (pinfunction "2_2") (pintype "passive"))
      (node (ref "R201") (pin "1") (pinfunction "1_1") (pintype "passive"))
    )
    (net (code "287") (name "Net-(IC34-SEL_PDO3)") (class "Default")
      (node (ref "IC34") (pin "7") (pinfunction "SEL_PDO3_7") (pintype "open_collector"))
      (node (ref "R199") (pin "2") (pinfunction "2_2") (pintype "passive"))
      (node (ref "R200") (pin "1") (pinfunction "1_1") (pintype "passive"))
    )
    (net (code "288") (name "Net-(IC34-SEL_PDO4)") (class "Default")
      (node (ref "IC34") (pin "10") (pinfunction "SEL_PDO4_10") (pintype "open_collector"))
      (node (ref "R198") (pin "2") (pinfunction "2_2") (pintype "passive"))
      (node (ref "R199") (pin "1") (pinfunction "1_1") (pintype "passive"))
    )
    (net (code "289") (name "Net-(IC34-SEL_PDO5)") (class "Default")
      (node (ref "IC34") (pin "11") (pinfunction "SEL_PDO5_11") (pintype "open_collector"))
      (node (ref "R197") (pin "2") (pinfunction "2_2") (pintype "passive"))
      (node (ref "R198") (pin "1") (pinfunction "1_1") (pintype "passive"))
    )
    (net (code "290") (name "Net-(IC34-VBUS_DISCH)") (class "Default")
      (node (ref "IC34") (pin "13") (pinfunction "VBUS_DISCH_13") (pintype "output"))
      (node (ref "R204") (pin "2") (pinfunction "2_2") (pintype "passive"))
      (node (ref "T31") (pin "4") (pinfunction "G_4") (pintype "passive"))
    )
    (net (code "291") (name "Net-(IC34-VBUS_EN_SRC)") (class "Default")
      (node (ref "IC34") (pin "14") (pinfunction "VBUS_EN_SRC_14") (pintype "open_collector"))
      (node (ref "R219") (pin "2") (pinfunction "2_2") (pintype "passive"))
    )
    (net (code "292") (name "Net-(IC34-VREG1V2)") (class "Default")
      (node (ref "C206") (pin "1") (pinfunction "1_1") (pintype "passive"))
      (node (ref "IC34") (pin "15") (pinfunction "VREG1V2_15") (pintype "input"))
    )
    (net (code "293") (name "Net-(IC34-VREG2V7)") (class "Default")
      (node (ref "C207") (pin "1") (pinfunction "1_1") (pintype "passive"))
      (node (ref "IC34") (pin "16") (pinfunction "VREG2V7_16") (pintype "input"))
    )
    (net (code "294") (name "Net-(IC35-BOOT1)") (class "Default")
      (node (ref "C272") (pin "2") (pinfunction "2_2") (pintype "passive"))
      (node (ref "IC35") (pin "22") (pinfunction "BOOT1_22") (pintype "power_in"))
    )
    (net (code "295") (name "Net-(IC35-BOOT2)") (class "Default")
      (node (ref "C273") (pin "2") (pinfunction "2_2") (pintype "passive"))
      (node (ref "IC35") (pin "20") (pinfunction "BOOT2_20") (pintype "power_in"))
    )
    (net (code "296") (name "Net-(IC35-CDC)") (class "Default")
      (node (ref "IC35") (pin "16") (pinfunction "CDC_16") (pintype "output"))
      (node (ref "R267") (pin "1") (pinfunction "1_1") (pintype "passive"))
    )
    (net (code "297") (name "Net-(IC35-COMP)") (class "Default")
      (node (ref "C270") (pin "1") (pinfunction "1_1") (pintype "passive"))
      (node (ref "IC35") (pin "18") (pinfunction "COMP_18") (pintype "input"))
      (node (ref "R268") (pin "1") (pinfunction "1_1") (pintype "passive"))
    )
    (net (code "298") (name "Net-(IC35-DITH_SYNC)") (class "Default")
      (node (ref "C269") (pin "1") (pinfunction "1_1") (pintype "passive"))
      (node (ref "IC35") (pin "7") (pinfunction "DITH_SYNC_7") (pintype "input"))
    )
    (net (code "299") (name "Net-(IC35-DR1H)") (class "Default")
      (node (ref "IC35") (pin "2") (pinfunction "DR1H_2") (pintype "output"))
      (node (ref "R271") (pin "1") (pinfunction "1_1") (pintype "passive"))
    )
    (net (code "300") (name "Net-(IC35-DR1L)") (class "Default")
      (node (ref "IC35") (pin "1") (pinfunction "DR1L_1") (pintype "output"))
      (node (ref "R270") (pin "1") (pinfunction "1_1") (pintype "passive"))
    )
    (net (code "301") (name "Net-(IC35-FB)") (class "Default")
      (node (ref "IC35") (pin "14") (pinfunction "FB_14") (pintype "input"))
      (node (ref "R247") (pin "2") (pinfunction "2_2") (pintype "passive"))
      (node (ref "R248") (pin "1") (pinfunction "1_1") (pintype "passive"))
    )
    (net (code "302") (name "Net-(IC35-FSW)") (class "Default")
      (node (ref "IC35") (pin "8") (pinfunction "FSW_8") (pintype "input"))
      (node (ref "R265") (pin "1") (pinfunction "1_1") (pintype "passive"))
    )
    (net (code "303") (name "Net-(IC35-ILIM)") (class "Default")
      (node (ref "IC35") (pin "17") (pinfunction "ILIM_17") (pintype "output"))
      (node (ref "R266") (pin "1") (pinfunction "1_1") (pintype "passive"))
    )
    (net (code "304") (name "Net-(IC35-MODE)") (class "Default")
      (node (ref "IC35") (pin "15") (pinfunction "MODE_15") (pintype "input"))
      (node (ref "R264") (pin "1") (pinfunction "1_1") (pintype "passive"))
    )
    (net (code "305") (name "Net-(IC35-SW1)") (class "Default")
      (node (ref "C272") (pin "1") (pinfunction "1_1") (pintype "passive"))
      (node (ref "IC35") (pin "23") (pinfunction "SW1_23") (pintype "power_in"))
      (node (ref "L9") (pin "1") (pinfunction "1_1") (pintype "passive"))
      (node (ref "R275") (pin "1") (pinfunction "1_1") (pintype "passive"))
      (node (ref "T39") (pin "5") (pinfunction "D_5") (pintype "passive"))
      (node (ref "T39") (pin "6") (pinfunction "D_6") (pintype "passive"))
      (node (ref "T39") (pin "7") (pinfunction "D_7") (pintype "passive"))
      (node (ref "T39") (pin "8") (pinfunction "D_8") (pintype "passive"))
      (node (ref "T39") (pin "9") (pinfunction "D_9") (pintype "passive"))
      (node (ref "T40") (pin "1") (pinfunction "S_1") (pintype "passive"))
      (node (ref "T40") (pin "2") (pinfunction "S_2") (pintype "passive"))
      (node (ref "T40") (pin "3") (pinfunction "S_3") (pintype "passive"))
    )
    (net (code "306") (name "Net-(IC35-VCC)") (class "Default")
      (node (ref "C268") (pin "1") (pinfunction "1_1") (pintype "passive"))
      (node (ref "IC35") (pin "19") (pinfunction "VCC_19") (pintype "power_in"))
    )
    (net (code "307") (name "Net-(IC37-ADDR0)") (class "Default")
      (node (ref "IC37") (pin "9") (pinfunction "ADDR0_9") (pintype "input"))
      (node (ref "R258") (pin "1") (pinfunction "1_1") (pintype "passive"))
    )
    (net (code "308") (name "Net-(IC37-SEL_PDO2)") (class "Default")
      (node (ref "IC37") (pin "8") (pinfunction "SEL_PDO2_8") (pintype "open_collector"))
      (node (ref "R256") (pin "2") (pinfunction "2_2") (pintype "passive"))
      (node (ref "R257") (pin "1") (pinfunction "1_1") (pintype "passive"))
    )
    (net (code "309") (name "Net-(IC37-SEL_PDO3)") (class "Default")
      (node (ref "IC37") (pin "7") (pinfunction "SEL_PDO3_7") (pintype "open_collector"))
      (node (ref "R254") (pin "2") (pinfunction "2_2") (pintype "passive"))
      (node (ref "R256") (pin "1") (pinfunction "1_1") (pintype "passive"))
    )
    (net (code "310") (name "Net-(IC37-SEL_PDO4)") (class "Default")
      (node (ref "IC37") (pin "10") (pinfunction "SEL_PDO4_10") (pintype "open_collector"))
      (node (ref "R253") (pin "2") (pinfunction "2_2") (pintype "passive"))
      (node (ref "R254") (pin "1") (pinfunction "1_1") (pintype "passive"))
    )
    (net (code "311") (name "Net-(IC37-SEL_PDO5)") (class "Default")
      (node (ref "IC37") (pin "11") (pinfunction "SEL_PDO5_11") (pintype "open_collector"))
      (node (ref "R248") (pin "2") (pinfunction "2_2") (pintype "passive"))
      (node (ref "R253") (pin "1") (pinfunction "1_1") (pintype "passive"))
    )
    (net (code "312") (name "Net-(IC37-VBUS_DISCH)") (class "Default")
      (node (ref "IC37") (pin "13") (pinfunction "VBUS_DISCH_13") (pintype "output"))
      (node (ref "R260") (pin "2") (pinfunction "2_2") (pintype "passive"))
      (node (ref "T36") (pin "4") (pinfunction "G_4") (pintype "passive"))
    )
    (net (code "313") (name "Net-(IC37-VBUS_EN_SRC)") (class "Default")
      (node (ref "IC37") (pin "14") (pinfunction "VBUS_EN_SRC_14") (pintype "open_collector"))
      (node (ref "R262") (pin "2") (pinfunction "2_2") (pintype "passive"))
    )
    (net (code "314") (name "Net-(IC37-VREG1V2)") (class "Default")
      (node (ref "C265") (pin "1") (pinfunction "1_1") (pintype "passive"))
      (node (ref "IC37") (pin "15") (pinfunction "VREG1V2_15") (pintype "input"))
    )
    (net (code "315") (name "Net-(IC37-VREG2V7)") (class "Default")
      (node (ref "C266") (pin "1") (pinfunction "1_1") (pintype "passive"))
      (node (ref "IC37") (pin "16") (pinfunction "VREG2V7_16") (pintype "input"))
    )
    (net (code "316") (name "Net-(IC40-AAM)") (class "Default")
      (node (ref "IC40") (pin "1") (pinfunction "AAM_1") (pintype "bidirectional"))
      (node (ref "R242") (pin "1") (pinfunction "1_1") (pintype "passive"))
      (node (ref "R244") (pin "2") (pinfunction "2_2") (pintype "passive"))
    )
    (net (code "317") (name "Net-(IC40-BST)") (class "Default")
      (node (ref "IC40") (pin "5") (pinfunction "BST_5") (pintype "bidirectional"))
      (node (ref "R243") (pin "2") (pinfunction "2_2") (pintype "passive"))
    )
    (net (code "318") (name "Net-(IC40-EN)") (class "Default")
      (node (ref "IC40") (pin "6") (pinfunction "EN_6") (pintype "bidirectional"))
      (node (ref "R241") (pin "2") (pinfunction "2_2") (pintype "passive"))
    )
    (net (code "319") (name "Net-(IC40-FB)") (class "Default")
      (node (ref "IC40") (pin "8") (pinfunction "FB_8") (pintype "bidirectional"))
      (node (ref "RT1") (pin "1") (pinfunction "1_1") (pintype "passive"))
    )
    (net (code "320") (name "Net-(IC40-SW)") (class "Default")
      (node (ref "C235") (pin "2") (pinfunction "2_2") (pintype "passive"))
      (node (ref "IC40") (pin "3") (pinfunction "SW_3") (pintype "bidirectional"))
      (node (ref "L11") (pin "1") (pinfunction "1_1") (pintype "passive"))
    )
    (net (code "321") (name "Net-(IC40-VCC)") (class "Default")
      (node (ref "C234") (pin "1") (pinfunction "1_1") (pintype "passive"))
      (node (ref "IC40") (pin "7") (pinfunction "VCC_7") (pintype "bidirectional"))
      (node (ref "R244") (pin "1") (pinfunction "1_1") (pintype "passive"))
    )
    (net (code "322") (name "Net-(IC41-AAM)") (class "Default")
      (node (ref "IC41") (pin "1") (pinfunction "AAM_1") (pintype "bidirectional"))
      (node (ref "R281") (pin "1") (pinfunction "1_1") (pintype "passive"))
      (node (ref "R286") (pin "2") (pinfunction "2_2") (pintype "passive"))
    )
    (net (code "323") (name "Net-(IC41-BST)") (class "Default")
      (node (ref "IC41") (pin "5") (pinfunction "BST_5") (pintype "bidirectional"))
      (node (ref "R282") (pin "2") (pinfunction "2_2") (pintype "passive"))
    )
    (net (code "324") (name "Net-(IC41-FB)") (class "Default")
      (node (ref "IC41") (pin "8") (pinfunction "FB_8") (pintype "bidirectional"))
      (node (ref "R283") (pin "1") (pinfunction "1_1") (pintype "passive"))
    )
    (net (code "325") (name "Net-(IC41-SW)") (class "Default")
      (node (ref "C294") (pin "2") (pinfunction "2_2") (pintype "passive"))
      (node (ref "IC41") (pin "3") (pinfunction "SW_3") (pintype "bidirectional"))
      (node (ref "L12") (pin "1") (pinfunction "1_1") (pintype "passive"))
    )
    (net (code "326") (name "Net-(IC41-VCC)") (class "Default")
      (node (ref "C293") (pin "1") (pinfunction "1_1") (pintype "passive"))
      (node (ref "IC41") (pin "7") (pinfunction "VCC_7") (pintype "bidirectional"))
      (node (ref "R286") (pin "1") (pinfunction "1_1") (pintype "passive"))
    )
    (net (code "327") (name "Net-(IC43-AAM)") (class "Default")
      (node (ref "IC43") (pin "1") (pinfunction "AAM_1") (pintype "bidirectional"))
      (node (ref "R290") (pin "1") (pinfunction "1_1") (pintype "passive"))
      (node (ref "R295") (pin "2") (pinfunction "2_2") (pintype "passive"))
    )
    (net (code "328") (name "Net-(IC43-BST)") (class "Default")
      (node (ref "IC43") (pin "5") (pinfunction "BST_5") (pintype "bidirectional"))
      (node (ref "R291") (pin "2") (pinfunction "2_2") (pintype "passive"))
    )
    (net (code "329") (name "Net-(IC43-FB)") (class "Default")
      (node (ref "IC43") (pin "8") (pinfunction "FB_8") (pintype "bidirectional"))
      (node (ref "R292") (pin "1") (pinfunction "1_1") (pintype "passive"))
    )
    (net (code "330") (name "Net-(IC43-SW)") (class "Default")
      (node (ref "C301") (pin "2") (pinfunction "2_2") (pintype "passive"))
      (node (ref "IC43") (pin "3") (pinfunction "SW_3") (pintype "bidirectional"))
      (node (ref "L13") (pin "1") (pinfunction "1_1") (pintype "passive"))
    )
    (net (code "331") (name "Net-(IC43-VCC)") (class "Default")
      (node (ref "C300") (pin "1") (pinfunction "1_1") (pintype "passive"))
      (node (ref "IC43") (pin "7") (pinfunction "VCC_7") (pintype "bidirectional"))
      (node (ref "R295") (pin "1") (pinfunction "1_1") (pintype "passive"))
    )
    (net (code "332") (name "Net-(R52-Pad1)") (class "Default")
      (node (ref "R52") (pin "1") (pinfunction "1_1") (pintype "passive"))
      (node (ref "T6") (pin "5") (pinfunction "D_5") (pintype "passive"))
      (node (ref "T6") (pin "6") (pinfunction "D_6") (pintype "passive"))
      (node (ref "T6") (pin "7") (pinfunction "D_7") (pintype "passive"))
      (node (ref "T6") (pin "8") (pinfunction "D_8") (pintype "passive"))
      (node (ref "T6") (pin "9") (pinfunction "D_9") (pintype "passive"))
    )
    (net (code "333") (name "Net-(R54-Pad1)") (class "Default")
      (node (ref "R54") (pin "1") (pinfunction "1_1") (pintype "passive"))
      (node (ref "T7") (pin "1") (pinfunction "S_1") (pintype "passive"))
      (node (ref "T7") (pin "2") (pinfunction "S_2") (pintype "passive"))
      (node (ref "T7") (pin "3") (pinfunction "S_3") (pintype "passive"))
      (node (ref "T8") (pin "1") (pinfunction "S_1") (pintype "passive"))
      (node (ref "T8") (pin "2") (pinfunction "S_2") (pintype "passive"))
      (node (ref "T8") (pin "3") (pinfunction "S_3") (pintype "passive"))
    )
    (net (code "334") (name "Net-(R72-Pad1)") (class "Default")
      (node (ref "R72") (pin "1") (pinfunction "1_1") (pintype "passive"))
      (node (ref "T1") (pin "5") (pinfunction "D_5") (pintype "passive"))
      (node (ref "T1") (pin "6") (pinfunction "D_6") (pintype "passive"))
      (node (ref "T1") (pin "7") (pinfunction "D_7") (pintype "passive"))
      (node (ref "T1") (pin "8") (pinfunction "D_8") (pintype "passive"))
      (node (ref "T1") (pin "9") (pinfunction "D_9") (pintype "passive"))
    )
    (net (code "335") (name "Net-(R74-Pad1)") (class "Default")
      (node (ref "R74") (pin "1") (pinfunction "1_1") (pintype "passive"))
      (node (ref "T2") (pin "1") (pinfunction "S_1") (pintype "passive"))
      (node (ref "T2") (pin "2") (pinfunction "S_2") (pintype "passive"))
      (node (ref "T2") (pin "3") (pinfunction "S_3") (pintype "passive"))
      (node (ref "T3") (pin "1") (pinfunction "S_1") (pintype "passive"))
      (node (ref "T3") (pin "2") (pinfunction "S_2") (pintype "passive"))
      (node (ref "T3") (pin "3") (pinfunction "S_3") (pintype "passive"))
    )
    (net (code "336") (name "Net-(R99-Pad1)") (class "Default")
      (node (ref "R99") (pin "1") (pinfunction "1_1") (pintype "passive"))
      (node (ref "T11") (pin "5") (pinfunction "D_5") (pintype "passive"))
      (node (ref "T11") (pin "6") (pinfunction "D_6") (pintype "passive"))
      (node (ref "T11") (pin "7") (pinfunction "D_7") (pintype "passive"))
      (node (ref "T11") (pin "8") (pinfunction "D_8") (pintype "passive"))
      (node (ref "T11") (pin "9") (pinfunction "D_9") (pintype "passive"))
    )
    (net (code "337") (name "Net-(R101-Pad1)") (class "Default")
      (node (ref "R101") (pin "1") (pinfunction "1_1") (pintype "passive"))
      (node (ref "T12") (pin "1") (pinfunction "S_1") (pintype "passive"))
      (node (ref "T12") (pin "2") (pinfunction "S_2") (pintype "passive"))
      (node (ref "T12") (pin "3") (pinfunction "S_3") (pintype "passive"))
      (node (ref "T13") (pin "1") (pinfunction "S_1") (pintype "passive"))
      (node (ref "T13") (pin "2") (pinfunction "S_2") (pintype "passive"))
      (node (ref "T13") (pin "3") (pinfunction "S_3") (pintype "passive"))
    )
    (net (code "338") (name "Net-(R125-Pad1)") (class "Default")
      (node (ref "R125") (pin "1") (pinfunction "1_1") (pintype "passive"))
      (node (ref "T16") (pin "5") (pinfunction "D_5") (pintype "passive"))
      (node (ref "T16") (pin "6") (pinfunction "D_6") (pintype "passive"))
      (node (ref "T16") (pin "7") (pinfunction "D_7") (pintype "passive"))
      (node (ref "T16") (pin "8") (pinfunction "D_8") (pintype "passive"))
      (node (ref "T16") (pin "9") (pinfunction "D_9") (pintype "passive"))
    )
    (net (code "339") (name "Net-(R127-Pad1)") (class "Default")
      (node (ref "R127") (pin "1") (pinfunction "1_1") (pintype "passive"))
      (node (ref "T17") (pin "1") (pinfunction "S_1") (pintype "passive"))
      (node (ref "T17") (pin "2") (pinfunction "S_2") (pintype "passive"))
      (node (ref "T17") (pin "3") (pinfunction "S_3") (pintype "passive"))
      (node (ref "T18") (pin "1") (pinfunction "S_1") (pintype "passive"))
      (node (ref "T18") (pin "2") (pinfunction "S_2") (pintype "passive"))
      (node (ref "T18") (pin "3") (pinfunction "S_3") (pintype "passive"))
    )
    (net (code "340") (name "Net-(R151-Pad1)") (class "Default")
      (node (ref "R151") (pin "1") (pinfunction "1_1") (pintype "passive"))
      (node (ref "T21") (pin "5") (pinfunction "D_5") (pintype "passive"))
      (node (ref "T21") (pin "6") (pinfunction "D_6") (pintype "passive"))
      (node (ref "T21") (pin "7") (pinfunction "D_7") (pintype "passive"))
      (node (ref "T21") (pin "8") (pinfunction "D_8") (pintype "passive"))
      (node (ref "T21") (pin "9") (pinfunction "D_9") (pintype "passive"))
    )
    (net (code "341") (name "Net-(R153-Pad1)") (class "Default")
      (node (ref "R153") (pin "1") (pinfunction "1_1") (pintype "passive"))
      (node (ref "T22") (pin "1") (pinfunction "S_1") (pintype "passive"))
      (node (ref "T22") (pin "2") (pinfunction "S_2") (pintype "passive"))
      (node (ref "T22") (pin "3") (pinfunction "S_3") (pintype "passive"))
      (node (ref "T23") (pin "1") (pinfunction "S_1") (pintype "passive"))
      (node (ref "T23") (pin "2") (pinfunction "S_2") (pintype "passive"))
      (node (ref "T23") (pin "3") (pinfunction "S_3") (pintype "passive"))
    )
    (net (code "342") (name "Net-(R177-Pad1)") (class "Default")
      (node (ref "R177") (pin "1") (pinfunction "1_1") (pintype "passive"))
      (node (ref "T26") (pin "5") (pinfunction "D_5") (pintype "passive"))
      (node (ref "T26") (pin "6") (pinfunction "D_6") (pintype "passive"))
      (node (ref "T26") (pin "7") (pinfunction "D_7") (pintype "passive"))
      (node (ref "T26") (pin "8") (pinfunction "D_8") (pintype "passive"))
      (node (ref "T26") (pin "9") (pinfunction "D_9") (pintype "passive"))
    )
    (net (code "343") (name "Net-(R179-Pad1)") (class "Default")
      (node (ref "R179") (pin "1") (pinfunction "1_1") (pintype "passive"))
      (node (ref "T27") (pin "1") (pinfunction "S_1") (pintype "passive"))
      (node (ref "T27") (pin "2") (pinfunction "S_2") (pintype "passive"))
      (node (ref "T27") (pin "3") (pinfunction "S_3") (pintype "passive"))
      (node (ref "T28") (pin "1") (pinfunction "S_1") (pintype "passive"))
      (node (ref "T28") (pin "2") (pinfunction "S_2") (pintype "passive"))
      (node (ref "T28") (pin "3") (pinfunction "S_3") (pintype "passive"))
    )
    (net (code "344") (name "Net-(R203-Pad1)") (class "Default")
      (node (ref "R203") (pin "1") (pinfunction "1_1") (pintype "passive"))
      (node (ref "T31") (pin "5") (pinfunction "D_5") (pintype "passive"))
      (node (ref "T31") (pin "6") (pinfunction "D_6") (pintype "passive"))
      (node (ref "T31") (pin "7") (pinfunction "D_7") (pintype "passive"))
      (node (ref "T31") (pin "8") (pinfunction "D_8") (pintype "passive"))
      (node (ref "T31") (pin "9") (pinfunction "D_9") (pintype "passive"))
    )
    (net (code "345") (name "Net-(R218-Pad1)") (class "Default")
      (node (ref "R218") (pin "1") (pinfunction "1_1") (pintype "passive"))
      (node (ref "T32") (pin "1") (pinfunction "S_1") (pintype "passive"))
      (node (ref "T32") (pin "2") (pinfunction "S_2") (pintype "passive"))
      (node (ref "T32") (pin "3") (pinfunction "S_3") (pintype "passive"))
      (node (ref "T33") (pin "1") (pinfunction "S_1") (pintype "passive"))
      (node (ref "T33") (pin "2") (pinfunction "S_2") (pintype "passive"))
      (node (ref "T33") (pin "3") (pinfunction "S_3") (pintype "passive"))
    )
    (net (code "346") (name "Net-(R259-Pad1)") (class "Default")
      (node (ref "R259") (pin "1") (pinfunction "1_1") (pintype "passive"))
      (node (ref "T36") (pin "5") (pinfunction "D_5") (pintype "passive"))
      (node (ref "T36") (pin "6") (pinfunction "D_6") (pintype "passive"))
      (node (ref "T36") (pin "7") (pinfunction "D_7") (pintype "passive"))
      (node (ref "T36") (pin "8") (pinfunction "D_8") (pintype "passive"))
      (node (ref "T36") (pin "9") (pinfunction "D_9") (pintype "passive"))
    )
    (net (code "347") (name "Net-(R261-Pad1)") (class "Default")
      (node (ref "R261") (pin "1") (pinfunction "1_1") (pintype "passive"))
      (node (ref "T37") (pin "1") (pinfunction "S_1") (pintype "passive"))
      (node (ref "T37") (pin "2") (pinfunction "S_2") (pintype "passive"))
      (node (ref "T37") (pin "3") (pinfunction "S_3") (pintype "passive"))
      (node (ref "T38") (pin "1") (pinfunction "S_1") (pintype "passive"))
      (node (ref "T38") (pin "2") (pinfunction "S_2") (pintype "passive"))
      (node (ref "T38") (pin "3") (pinfunction "S_3") (pintype "passive"))
    )
    (net (code "348") (name "Net-(T2-G)") (class "Default")
      (node (ref "R74") (pin "2") (pinfunction "2_2") (pintype "passive"))
      (node (ref "R75") (pin "1") (pinfunction "1_1") (pintype "passive"))
      (node (ref "T2") (pin "4") (pinfunction "G_4") (pintype "passive"))
      (node (ref "T3") (pin "4") (pinfunction "G_4") (pintype "passive"))
    )
    (net (code "349") (name "Net-(T4-G)") (class "Default")
      (node (ref "R83") (pin "2") (pinfunction "2_2") (pintype "passive"))
      (node (ref "T4") (pin "4") (pinfunction "G_4") (pintype "passive"))
    )
    (net (code "350") (name "Net-(T5-G)") (class "Default")
      (node (ref "R85") (pin "2") (pinfunction "2_2") (pintype "passive"))
      (node (ref "T5") (pin "4") (pinfunction "G_4") (pintype "passive"))
    )
    (net (code "351") (name "Net-(T7-G)") (class "Default")
      (node (ref "R54") (pin "2") (pinfunction "2_2") (pintype "passive"))
      (node (ref "R55") (pin "1") (pinfunction "1_1") (pintype "passive"))
      (node (ref "T7") (pin "4") (pinfunction "G_4") (pintype "passive"))
      (node (ref "T8") (pin "4") (pinfunction "G_4") (pintype "passive"))
    )
    (net (code "352") (name "Net-(T9-G)") (class "Default")
      (node (ref "R64") (pin "2") (pinfunction "2_2") (pintype "passive"))
      (node (ref "T9") (pin "4") (pinfunction "G_4") (pintype "passive"))
    )
    (net (code "353") (name "Net-(T10-G)") (class "Default")
      (node (ref "R65") (pin "2") (pinfunction "2_2") (pintype "passive"))
      (node (ref "T10") (pin "4") (pinfunction "G_4") (pintype "passive"))
    )
    (net (code "354") (name "Net-(T12-G)") (class "Default")
      (node (ref "R101") (pin "2") (pinfunction "2_2") (pintype "passive"))
      (node (ref "R102") (pin "1") (pinfunction "1_1") (pintype "passive"))
      (node (ref "T12") (pin "4") (pinfunction "G_4") (pintype "passive"))
      (node (ref "T13") (pin "4") (pinfunction "G_4") (pintype "passive"))
    )
    (net (code "355") (name "Net-(T14-G)") (class "Default")
      (node (ref "R110") (pin "2") (pinfunction "2_2") (pintype "passive"))
      (node (ref "T14") (pin "4") (pinfunction "G_4") (pintype "passive"))
    )
    (net (code "356") (name "Net-(T15-G)") (class "Default")
      (node (ref "R111") (pin "2") (pinfunction "2_2") (pintype "passive"))
      (node (ref "T15") (pin "4") (pinfunction "G_4") (pintype "passive"))
    )
    (net (code "357") (name "Net-(T17-G)") (class "Default")
      (node (ref "R127") (pin "2") (pinfunction "2_2") (pintype "passive"))
      (node (ref "R128") (pin "1") (pinfunction "1_1") (pintype "passive"))
      (node (ref "T17") (pin "4") (pinfunction "G_4") (pintype "passive"))
      (node (ref "T18") (pin "4") (pinfunction "G_4") (pintype "passive"))
    )
    (net (code "358") (name "Net-(T19-G)") (class "Default")
      (node (ref "R136") (pin "2") (pinfunction "2_2") (pintype "passive"))
      (node (ref "T19") (pin "4") (pinfunction "G_4") (pintype "passive"))
    )
    (net (code "359") (name "Net-(T20-G)") (class "Default")
      (node (ref "R137") (pin "2") (pinfunction "2_2") (pintype "passive"))
      (node (ref "T20") (pin "4") (pinfunction "G_4") (pintype "passive"))
    )
    (net (code "360") (name "Net-(T22-G)") (class "Default")
      (node (ref "R153") (pin "2") (pinfunction "2_2") (pintype "passive"))
      (node (ref "R154") (pin "1") (pinfunction "1_1") (pintype "passive"))
      (node (ref "T22") (pin "4") (pinfunction "G_4") (pintype "passive"))
      (node (ref "T23") (pin "4") (pinfunction "G_4") (pintype "passive"))
    )
    (net (code "361") (name "Net-(T24-G)") (class "Default")
      (node (ref "R162") (pin "2") (pinfunction "2_2") (pintype "passive"))
      (node (ref "T24") (pin "4") (pinfunction "G_4") (pintype "passive"))
    )
    (net (code "362") (name "Net-(T25-G)") (class "Default")
      (node (ref "R163") (pin "2") (pinfunction "2_2") (pintype "passive"))
      (node (ref "T25") (pin "4") (pinfunction "G_4") (pintype "passive"))
    )
    (net (code "363") (name "Net-(T27-G)") (class "Default")
      (node (ref "R179") (pin "2") (pinfunction "2_2") (pintype "passive"))
      (node (ref "R180") (pin "1") (pinfunction "1_1") (pintype "passive"))
      (node (ref "T27") (pin "4") (pinfunction "G_4") (pintype "passive"))
      (node (ref "T28") (pin "4") (pinfunction "G_4") (pintype "passive"))
    )
    (net (code "364") (name "Net-(T29-G)") (class "Default")
      (node (ref "R188") (pin "2") (pinfunction "2_2") (pintype "passive"))
      (node (ref "T29") (pin "4") (pinfunction "G_4") (pintype "passive"))
    )
    (net (code "365") (name "Net-(T30-G)") (class "Default")
      (node (ref "R189") (pin "2") (pinfunction "2_2") (pintype "passive"))
      (node (ref "T30") (pin "4") (pinfunction "G_4") (pintype "passive"))
    )
    (net (code "366") (name "Net-(T32-G)") (class "Default")
      (node (ref "R218") (pin "2") (pinfunction "2_2") (pintype "passive"))
      (node (ref "R219") (pin "1") (pinfunction "1_1") (pintype "passive"))
      (node (ref "T32") (pin "4") (pinfunction "G_4") (pintype "passive"))
      (node (ref "T33") (pin "4") (pinfunction "G_4") (pintype "passive"))
    )
    (net (code "367") (name "Net-(T34-G)") (class "Default")
      (node (ref "R235") (pin "2") (pinfunction "2_2") (pintype "passive"))
      (node (ref "T34") (pin "4") (pinfunction "G_4") (pintype "passive"))
    )
    (net (code "368") (name "Net-(T35-G)") (class "Default")
      (node (ref "R236") (pin "2") (pinfunction "2_2") (pintype "passive"))
      (node (ref "T35") (pin "4") (pinfunction "G_4") (pintype "passive"))
    )
    (net (code "369") (name "Net-(T37-G)") (class "Default")
      (node (ref "R261") (pin "2") (pinfunction "2_2") (pintype "passive"))
      (node (ref "R262") (pin "1") (pinfunction "1_1") (pintype "passive"))
      (node (ref "T37") (pin "4") (pinfunction "G_4") (pintype "passive"))
      (node (ref "T38") (pin "4") (pinfunction "G_4") (pintype "passive"))
    )
    (net (code "370") (name "Net-(T39-G)") (class "Default")
      (node (ref "R270") (pin "2") (pinfunction "2_2") (pintype "passive"))
      (node (ref "T39") (pin "4") (pinfunction "G_4") (pintype "passive"))
    )
    (net (code "371") (name "Net-(T40-G)") (class "Default")
      (node (ref "R271") (pin "2") (pinfunction "2_2") (pintype "passive"))
      (node (ref "T40") (pin "4") (pinfunction "G_4") (pintype "passive"))
    )
    (net (code "372") (name "Net-(USB9-CC1)") (class "Default")
      (node (ref "R251") (pin "1") (pinfunction "1_1") (pintype "passive"))
      (node (ref "USB9") (pin "A5") (pinfunction "CC1_A5") (pintype "bidirectional"))
    )
    (net (code "373") (name "Net-(USB9-CC2)") (class "Default")
      (node (ref "R250") (pin "1") (pinfunction "1_1") (pintype "passive"))
      (node (ref "USB9") (pin "B5") (pinfunction "CC2_B5") (pintype "bidirectional"))
    )
    (net (code "374") (name "Net-(X1-2)") (class "Default")
      (node (ref "C178") (pin "1") (pinfunction "1_1") (pintype "passive"))
      (node (ref "R211") (pin "1") (pinfunction "1_1") (pintype "passive"))
      (node (ref "X1") (pin "3") (pinfunction "2_3") (pintype "passive"))
    )
    (net (code "375") (name "OCP1") (class "Default")
      (node (ref "IC4") (pin "2") (pinfunction "IN_2") (pintype "bidirectional"))
      (node (ref "IC42") (pin "21") (pinfunction "IO1.4_21") (pintype "bidirectional"))
      (node (ref "IC8") (pin "4") (pinfunction "~{FAULT}_4") (pintype "bidirectional"))
      (node (ref "R13") (pin "1") (pinfunction "1_1") (pintype "passive"))
    )
    (net (code "376") (name "OCP2") (class "Default")
      (node (ref "IC1") (pin "4") (pinfunction "~{FAULT}_4") (pintype "bidirectional"))
      (node (ref "IC42") (pin "22") (pinfunction "IO1.5_22") (pintype "bidirectional"))
      (node (ref "IC5") (pin "2") (pinfunction "IN_2") (pintype "bidirectional"))
      (node (ref "R16") (pin "1") (pinfunction "1_1") (pintype "passive"))
    )
    (net (code "377") (name "OCP3") (class "Default")
      (node (ref "IC2") (pin "4") (pinfunction "~{FAULT}_4") (pintype "bidirectional"))
      (node (ref "IC42") (pin "23") (pinfunction "IO1.6_23") (pintype "bidirectional"))
      (node (ref "IC6") (pin "2") (pinfunction "IN_2") (pintype "bidirectional"))
      (node (ref "R19") (pin "1") (pinfunction "1_1") (pintype "passive"))
    )
    (net (code "378") (name "OCP4") (class "Default")
      (node (ref "IC3") (pin "4") (pinfunction "~{FAULT}_4") (pintype "bidirectional"))
      (node (ref "IC42") (pin "24") (pinfunction "IO1.7_24") (pintype "bidirectional"))
      (node (ref "IC7") (pin "2") (pinfunction "IN_2") (pintype "bidirectional"))
      (node (ref "R22") (pin "1") (pinfunction "1_1") (pintype "passive"))
    )
    (net (code "379") (name "P1_IS_N") (class "Default")
      (node (ref "C196") (pin "2") (pinfunction "2_2") (pintype "passive"))
      (node (ref "IC12") (pin "13") (pinfunction "ISN_13") (pintype "input"))
      (node (ref "R229") (pin "1") (pinfunction "1_1") (pintype "passive"))
    )
    (net (code "380") (name "P1_IS_P") (class "Default")
      (node (ref "C196") (pin "1") (pinfunction "1_1") (pintype "passive"))
      (node (ref "IC12") (pin "12") (pinfunction "ISP_12") (pintype "input"))
      (node (ref "R228") (pin "1") (pinfunction "1_1") (pintype "passive"))
    )
    (net (code "381") (name "P2_IS_N") (class "Default")
      (node (ref "C74") (pin "2") (pinfunction "2_2") (pintype "passive"))
      (node (ref "IC10") (pin "13") (pinfunction "ISN_13") (pintype "input"))
      (node (ref "R87") (pin "1") (pinfunction "1_1") (pintype "passive"))
    )
    (net (code "382") (name "P2_IS_P") (class "Default")
      (node (ref "C74") (pin "1") (pinfunction "1_1") (pintype "passive"))
      (node (ref "IC10") (pin "12") (pinfunction "ISP_12") (pintype "input"))
      (node (ref "R86") (pin "1") (pinfunction "1_1") (pintype "passive"))
    )
    (net (code "383") (name "P3_IS_N") (class "Default")
      (node (ref "C103") (pin "2") (pinfunction "2_2") (pintype "passive"))
      (node (ref "IC15") (pin "13") (pinfunction "ISN_13") (pintype "input"))
      (node (ref "R113") (pin "1") (pinfunction "1_1") (pintype "passive"))
    )
    (net (code "384") (name "P3_IS_P") (class "Default")
      (node (ref "C103") (pin "1") (pinfunction "1_1") (pintype "passive"))
      (node (ref "IC15") (pin "12") (pinfunction "ISP_12") (pintype "input"))
      (node (ref "R112") (pin "1") (pinfunction "1_1") (pintype "passive"))
    )
    (net (code "385") (name "P4_IS_N") (class "Default")
      (node (ref "C128") (pin "2") (pinfunction "2_2") (pintype "passive"))
      (node (ref "IC18") (pin "13") (pinfunction "ISN_13") (pintype "input"))
      (node (ref "R139") (pin "1") (pinfunction "1_1") (pintype "passive"))
    )
    (net (code "386") (name "P4_IS_P") (class "Default")
      (node (ref "C128") (pin "1") (pinfunction "1_1") (pintype "passive"))
      (node (ref "IC18") (pin "12") (pinfunction "ISP_12") (pintype "input"))
      (node (ref "R138") (pin "1") (pinfunction "1_1") (pintype "passive"))
    )
    (net (code "387") (name "P5_IS_N") (class "Default")
      (node (ref "C153") (pin "2") (pinfunction "2_2") (pintype "passive"))
      (node (ref "IC21") (pin "13") (pinfunction "ISN_13") (pintype "input"))
      (node (ref "R165") (pin "1") (pinfunction "1_1") (pintype "passive"))
    )
    (net (code "388") (name "P5_IS_P") (class "Default")
      (node (ref "C153") (pin "1") (pinfunction "1_1") (pintype "passive"))
      (node (ref "IC21") (pin "12") (pinfunction "ISP_12") (pintype "input"))
      (node (ref "R164") (pin "1") (pinfunction "1_1") (pintype "passive"))
    )
    (net (code "389") (name "P6_IS_N") (class "Default")
      (node (ref "C199") (pin "2") (pinfunction "2_2") (pintype "passive"))
      (node (ref "IC24") (pin "13") (pinfunction "ISN_13") (pintype "input"))
      (node (ref "R191") (pin "1") (pinfunction "1_1") (pintype "passive"))
    )
    (net (code "390") (name "P6_IS_P") (class "Default")
      (node (ref "C199") (pin "1") (pinfunction "1_1") (pintype "passive"))
      (node (ref "IC24") (pin "12") (pinfunction "ISP_12") (pintype "input"))
      (node (ref "R190") (pin "1") (pinfunction "1_1") (pintype "passive"))
    )
    (net (code "391") (name "P7_IS_N") (class "Default")
      (node (ref "C250") (pin "2") (pinfunction "2_2") (pintype "passive"))
      (node (ref "IC32") (pin "13") (pinfunction "ISN_13") (pintype "input"))
      (node (ref "R238") (pin "1") (pinfunction "1_1") (pintype "passive"))
    )
    (net (code "392") (name "P7_IS_P") (class "Default")
      (node (ref "C250") (pin "1") (pinfunction "1_1") (pintype "passive"))
      (node (ref "IC32") (pin "12") (pinfunction "ISP_12") (pintype "input"))
      (node (ref "R237") (pin "1") (pinfunction "1_1") (pintype "passive"))
    )
    (net (code "393") (name "P8_IS_N") (class "Default")
      (node (ref "C284") (pin "2") (pinfunction "2_2") (pintype "passive"))
      (node (ref "IC35") (pin "13") (pinfunction "ISN_13") (pintype "input"))
      (node (ref "R273") (pin "1") (pinfunction "1_1") (pintype "passive"))
    )
    (net (code "394") (name "P8_IS_P") (class "Default")
      (node (ref "C284") (pin "1") (pinfunction "1_1") (pintype "passive"))
      (node (ref "IC35") (pin "12") (pinfunction "ISP_12") (pintype "input"))
      (node (ref "R272") (pin "1") (pinfunction "1_1") (pintype "passive"))
    )
    (net (code "395") (name "QMI_CS1") (class "Default")
      (node (ref "IC26") (pin "6") (pinfunction "GPIO8_6") (pintype "bidirectional"))
      (node (ref "IC39") (pin "1") (pinfunction "~{CS}_1") (pintype "bidirectional"))
      (node (ref "R278") (pin "1") (pinfunction "1_1") (pintype "passive"))
    )
    (net (code "396") (name "QSPI_SCLK") (class "Default")
      (node (ref "IC26") (pin "71") (pinfunction "QSPI_SCLK_71") (pintype "output"))
      (node (ref "IC27") (pin "6") (pinfunction "CLK_6") (pintype "bidirectional"))
      (node (ref "IC39") (pin "6") (pinfunction "CLK_6") (pintype "bidirectional"))
    )
    (net (code "397") (name "QSPI_SD0") (class "Default")
      (node (ref "IC26") (pin "72") (pinfunction "QSPI_SD0_72") (pintype "bidirectional"))
      (node (ref "IC27") (pin "5") (pinfunction "DI/IO0_5") (pintype "bidirectional"))
      (node (ref "IC39") (pin "5") (pinfunction "DI/IO0_5") (pintype "bidirectional"))
    )
    (net (code "398") (name "QSPI_SD1") (class "Default")
      (node (ref "IC26") (pin "74") (pinfunction "QSPI_SD1_74") (pintype "bidirectional"))
      (node (ref "IC27") (pin "2") (pinfunction "DO/IO1_2") (pintype "bidirectional"))
      (node (ref "IC39") (pin "2") (pinfunction "DO/IO1_2") (pintype "bidirectional"))
    )
    (net (code "399") (name "QSPI_SD2") (class "Default")
      (node (ref "IC26") (pin "73") (pinfunction "QSPI_SD2_73") (pintype "bidirectional"))
      (node (ref "IC27") (pin "3") (pinfunction "~{WP}/IO2_3") (pintype "bidirectional"))
      (node (ref "IC39") (pin "3") (pinfunction "~{WP}/IO2_3") (pintype "bidirectional"))
    )
    (net (code "400") (name "QSPI_SD3") (class "Default")
      (node (ref "IC26") (pin "70") (pinfunction "QSPI_SD3_70") (pintype "bidirectional"))
      (node (ref "IC27") (pin "7") (pinfunction "~{HOLD}/IO3_7") (pintype "bidirectional"))
      (node (ref "IC39") (pin "7") (pinfunction "~{HOLD}/IO3_7") (pintype "bidirectional"))
    )
    (net (code "401") (name "RCT") (class "Default")
      (node (ref "C32") (pin "1") (pinfunction "1_1") (pintype "passive"))
      (node (ref "ETH1") (pin "5") (pinfunction "P5/RCT_5") (pintype "passive"))
      (node (ref "R41") (pin "1") (pinfunction "1_1") (pintype "passive"))
      (node (ref "R42") (pin "1") (pinfunction "1_1") (pintype "passive"))
    )
    (net (code "402") (name "RDC_RD_N") (class "Default")
      (node (ref "C33") (pin "1") (pinfunction "1_1") (pintype "passive"))
      (node (ref "R40") (pin "2") (pinfunction "2_2") (pintype "passive"))
      (node (ref "R41") (pin "2") (pinfunction "2_2") (pintype "passive"))
    )
    (net (code "403") (name "RDC_RD_P") (class "Default")
      (node (ref "C34") (pin "1") (pinfunction "1_1") (pintype "passive"))
      (node (ref "R39") (pin "2") (pinfunction "2_2") (pintype "passive"))
      (node (ref "R42") (pin "2") (pinfunction "2_2") (pintype "passive"))
    )
    (net (code "404") (name "RD_N") (class "Default")
      (node (ref "C33") (pin "2") (pinfunction "2_2") (pintype "passive"))
      (node (ref "ETH1") (pin "6") (pinfunction "RD-_6") (pintype "passive"))
    )
    (net (code "405") (name "RD_P") (class "Default")
      (node (ref "C34") (pin "2") (pinfunction "2_2") (pintype "passive"))
      (node (ref "ETH1") (pin "4") (pinfunction "RD+_4") (pintype "passive"))
    )
    (net (code "406") (name "RUN") (class "Default")
      (node (ref "IC26") (pin "35") (pinfunction "RUN_35") (pintype "input"))
      (node (ref "JTAG") (pin "10") (pinfunction "10_10") (pintype "passive"))
      (node (ref "R24") (pin "2") (pinfunction "2_2") (pintype "passive"))
      (node (ref "SW1") (pin "2") (pinfunction "P$2_2") (pintype "bidirectional"))
    )
    (net (code "407") (name "RX_RD_N") (class "Default")
      (node (ref "IC31") (pin "5") (pinfunction "RXN_5") (pintype "input"))
      (node (ref "R40") (pin "1") (pinfunction "1_1") (pintype "passive"))
    )
    (net (code "408") (name "RX_RD_P") (class "Default")
      (node (ref "IC31") (pin "6") (pinfunction "RXP_6") (pintype "input"))
      (node (ref "R39") (pin "1") (pinfunction "1_1") (pintype "passive"))
    )
    (net (code "409") (name "SHIELD") (class "Default")
      (node (ref "C1") (pin "1") (pinfunction "1_1") (pintype "passive"))
      (node (ref "C109") (pin "2") (pinfunction "2_2") (pintype "passive"))
      (node (ref "C11") (pin "1") (pinfunction "1_1") (pintype "passive"))
      (node (ref "C134") (pin "2") (pinfunction "2_2") (pintype "passive"))
      (node (ref "C159") (pin "2") (pinfunction "2_2") (pintype "passive"))
      (node (ref "C205") (pin "2") (pinfunction "2_2") (pintype "passive"))
      (node (ref "C263") (pin "2") (pinfunction "2_2") (pintype "passive"))
      (node (ref "C28") (pin "1") (pinfunction "1_1") (pintype "passive"))
      (node (ref "C290") (pin "2") (pinfunction "2_2") (pintype "passive"))
      (node (ref "C31") (pin "2") (pinfunction "2_2") (pintype "passive"))
      (node (ref "C40") (pin "2") (pinfunction "2_2") (pintype "passive"))
      (node (ref "C80") (pin "2") (pinfunction "2_2") (pintype "passive"))
      (node (ref "ETH1") (pin "13") (pinfunction "SHIELD_13") (pintype "passive"))
      (node (ref "ETH1") (pin "14") (pinfunction "SHIELD_14") (pintype "passive"))
      (node (ref "H1") (pin "B3,3") (pinfunction "MOUNT_B3,3") (pintype "passive"))
      (node (ref "H2") (pin "B3,3") (pinfunction "MOUNT_B3,3") (pintype "passive"))
      (node (ref "H3") (pin "B3,3") (pinfunction "MOUNT_B3,3") (pintype "passive"))
      (node (ref "H4") (pin "B3,3") (pinfunction "MOUNT_B3,3") (pintype "passive"))
      (node (ref "PORT1") (pin "S1") (pinfunction "SHIELD1_S1") (pintype "passive"))
      (node (ref "PORT1") (pin "S2") (pinfunction "SHIELD1_S2") (pintype "passive"))
      (node (ref "PORT1") (pin "S3") (pinfunction "SHIELD1_S3") (pintype "passive"))
      (node (ref "PORT1") (pin "S4") (pinfunction "SHIELD1_S4") (pintype "passive"))
      (node (ref "PORT2") (pin "S1") (pinfunction "SHIELD1_S1") (pintype "passive"))
      (node (ref "PORT2") (pin "S2") (pinfunction "SHIELD1_S2") (pintype "passive"))
      (node (ref "PORT2") (pin "S3") (pinfunction "SHIELD1_S3") (pintype "passive"))
      (node (ref "PORT2") (pin "S4") (pinfunction "SHIELD1_S4") (pintype "passive"))
      (node (ref "PORT3") (pin "S1") (pinfunction "SHIELD1_S1") (pintype "passive"))
      (node (ref "PORT3") (pin "S2") (pinfunction "SHIELD1_S2") (pintype "passive"))
      (node (ref "PORT3") (pin "S3") (pinfunction "SHIELD1_S3") (pintype "passive"))
      (node (ref "PORT3") (pin "S4") (pinfunction "SHIELD1_S4") (pintype "passive"))
      (node (ref "PORT4") (pin "S1") (pinfunction "SHIELD1_S1") (pintype "passive"))
      (node (ref "PORT4") (pin "S2") (pinfunction "SHIELD1_S2") (pintype "passive"))
      (node (ref "PORT4") (pin "S3") (pinfunction "SHIELD1_S3") (pintype "passive"))
      (node (ref "PORT4") (pin "S4") (pinfunction "SHIELD1_S4") (pintype "passive"))
      (node (ref "PORT5") (pin "S1") (pinfunction "SHIELD1_S1") (pintype "passive"))
      (node (ref "PORT5") (pin "S2") (pinfunction "SHIELD1_S2") (pintype "passive"))
      (node (ref "PORT5") (pin "S3") (pinfunction "SHIELD1_S3") (pintype "passive"))
      (node (ref "PORT5") (pin "S4") (pinfunction "SHIELD1_S4") (pintype "passive"))
      (node (ref "PORT6") (pin "S1") (pinfunction "SHIELD1_S1") (pintype "passive"))
      (node (ref "PORT6") (pin "S2") (pinfunction "SHIELD1_S2") (pintype "passive"))
      (node (ref "PORT6") (pin "S3") (pinfunction "SHIELD1_S3") (pintype "passive"))
      (node (ref "PORT6") (pin "S4") (pinfunction "SHIELD1_S4") (pintype "passive"))
      (node (ref "PORT7") (pin "S1") (pinfunction "SHIELD1_S1") (pintype "passive"))
      (node (ref "PORT7") (pin "S2") (pinfunction "SHIELD1_S2") (pintype "passive"))
      (node (ref "PORT7") (pin "S3") (pinfunction "SHIELD1_S3") (pintype "passive"))
      (node (ref "PORT7") (pin "S4") (pinfunction "SHIELD1_S4") (pintype "passive"))
      (node (ref "PORT8") (pin "S1") (pinfunction "SHIELD1_S1") (pintype "passive"))
      (node (ref "PORT8") (pin "S2") (pinfunction "SHIELD1_S2") (pintype "passive"))
      (node (ref "PORT8") (pin "S3") (pinfunction "SHIELD1_S3") (pintype "passive"))
      (node (ref "PORT8") (pin "S4") (pinfunction "SHIELD1_S4") (pintype "passive"))
      (node (ref "R117") (pin "2") (pinfunction "2_2") (pintype "passive"))
      (node (ref "R143") (pin "2") (pinfunction "2_2") (pintype "passive"))
      (node (ref "R169") (pin "2") (pinfunction "2_2") (pintype "passive"))
      (node (ref "R195") (pin "2") (pinfunction "2_2") (pintype "passive"))
      (node (ref "R2") (pin "2") (pinfunction "2_2") (pintype "passive"))
      (node (ref "R246") (pin "2") (pinfunction "2_2") (pintype "passive"))
      (node (ref "R255") (pin "1") (pinfunction "1_1") (pintype "passive"))
      (node (ref "R277") (pin "2") (pinfunction "2_2") (pintype "passive"))
      (node (ref "R36") (pin "2") (pinfunction "2_2") (pintype "passive"))
      (node (ref "R50") (pin "2") (pinfunction "2_2") (pintype "passive"))
      (node (ref "R8") (pin "2") (pinfunction "2_2") (pintype "passive"))
      (node (ref "R91") (pin "2") (pinfunction "2_2") (pintype "passive"))
      (node (ref "USB9") (pin "SHLD1") (pinfunction "SHILED_SHLD1") (pintype "power_in"))
      (node (ref "USB9") (pin "SHLD2") (pinfunction "SHILED_SHLD2") (pintype "power_in"))
      (node (ref "USB9") (pin "SHLD3") (pinfunction "SHILED_SHLD3") (pintype "power_in"))
      (node (ref "USB9") (pin "SHLD4") (pinfunction "SHILED_SHLD4") (pintype "power_in"))
      (node (ref "USBA_1-2") (pin "S1") (pinfunction "SHIELD_S1") (pintype "passive"))
      (node (ref "USBA_1-2") (pin "S2") (pinfunction "SHIELD_S2") (pintype "passive"))
      (node (ref "USBA_1-2") (pin "S3") (pinfunction "SHIELD_S3") (pintype "passive"))
      (node (ref "USBA_1-2") (pin "S4") (pinfunction "SHIELD_S4") (pintype "passive"))
      (node (ref "USBA_3-4") (pin "S1") (pinfunction "SHIELD_S1") (pintype "passive"))
      (node (ref "USBA_3-4") (pin "S2") (pinfunction "SHIELD_S2") (pintype "passive"))
      (node (ref "USBA_3-4") (pin "S3") (pinfunction "SHIELD_S3") (pintype "passive"))
      (node (ref "USBA_3-4") (pin "S4") (pinfunction "SHIELD_S4") (pintype "passive"))
    )
    (net (code "410") (name "SPI1_CS") (class "Default")
      (node (ref "IC26") (pin "12") (pinfunction "GPIO13_12") (pintype "bidirectional"))
    )
    (net (code "411") (name "SPI1_MISO") (class "Default")
      (node (ref "IC26") (pin "11") (pinfunction "GPIO12_11") (pintype "bidirectional"))
    )
    (net (code "412") (name "SPI1_MOSI") (class "Default")
      (node (ref "IC26") (pin "14") (pinfunction "GPIO15_14") (pintype "bidirectional"))
    )
    (net (code "413") (name "SPI1_SCLK") (class "Default")
      (node (ref "IC26") (pin "13") (pinfunction "GPIO14_13") (pintype "bidirectional"))
    )
    (net (code "414") (name "SWCLK") (class "Default")
      (node (ref "IC26") (pin "33") (pinfunction "SWCLK_33") (pintype "output"))
      (node (ref "JTAG") (pin "4") (pinfunction "4_4") (pintype "passive"))
    )
    (net (code "415") (name "SWDIO") (class "Default")
      (node (ref "IC26") (pin "34") (pinfunction "SWDIO_34") (pintype "bidirectional"))
      (node (ref "JTAG") (pin "2") (pinfunction "2_2") (pintype "passive"))
    )
    (net (code "416") (name "TCA0_I2C_SCL") (class "Default")
      (node (ref "IC14") (pin "4") (pinfunction "SCL_4") (pintype "input"))
      (node (ref "IC38") (pin "2") (pinfunction "SC0_2") (pintype "bidirectional"))
      (node (ref "IC9") (pin "4") (pinfunction "SCL_4") (pintype "input"))
      (node (ref "R215") (pin "C1") (pinfunction "3_C1") (pintype "passive"))
    )
    (net (code "417") (name "TCA0_I2C_SDA") (class "Default")
      (node (ref "IC14") (pin "5") (pinfunction "SDA_5") (pintype "bidirectional"))
      (node (ref "IC38") (pin "1") (pinfunction "SD0_1") (pintype "bidirectional"))
      (node (ref "IC9") (pin "5") (pinfunction "SDA_5") (pintype "bidirectional"))
      (node (ref "R215") (pin "D1") (pinfunction "4_D1") (pintype "passive"))
    )
    (net (code "418") (name "TCA1_I2C_SCL") (class "Default")
      (node (ref "IC17") (pin "4") (pinfunction "SCL_4") (pintype "input"))
      (node (ref "IC20") (pin "4") (pinfunction "SCL_4") (pintype "input"))
      (node (ref "IC38") (pin "4") (pinfunction "SC1_4") (pintype "bidirectional"))
      (node (ref "R215") (pin "A1") (pinfunction "1_A1") (pintype "passive"))
    )
    (net (code "419") (name "TCA1_I2C_SDA") (class "Default")
      (node (ref "IC17") (pin "5") (pinfunction "SDA_5") (pintype "bidirectional"))
      (node (ref "IC20") (pin "5") (pinfunction "SDA_5") (pintype "bidirectional"))
      (node (ref "IC38") (pin "3") (pinfunction "SD1_3") (pintype "bidirectional"))
      (node (ref "R215") (pin "B1") (pinfunction "2_B1") (pintype "passive"))
    )
    (net (code "420") (name "TCA2_I2C_SCL") (class "Default")
      (node (ref "IC23") (pin "4") (pinfunction "SCL_4") (pintype "input"))
      (node (ref "IC30") (pin "4") (pinfunction "SCL_4") (pintype "input"))
      (node (ref "IC38") (pin "6") (pinfunction "SC2_6") (pintype "bidirectional"))
      (node (ref "R216") (pin "C1") (pinfunction "3_C1") (pintype "passive"))
    )
    (net (code "421") (name "TCA2_I2C_SDA") (class "Default")
      (node (ref "IC23") (pin "5") (pinfunction "SDA_5") (pintype "bidirectional"))
      (node (ref "IC30") (pin "5") (pinfunction "SDA_5") (pintype "bidirectional"))
      (node (ref "IC38") (pin "5") (pinfunction "SD2_5") (pintype "bidirectional"))
      (node (ref "R216") (pin "D1") (pinfunction "4_D1") (pintype "passive"))
    )
    (net (code "422") (name "TCA3_I2C_SCL") (class "Default")
      (node (ref "IC34") (pin "4") (pinfunction "SCL_4") (pintype "input"))
      (node (ref "IC37") (pin "4") (pinfunction "SCL_4") (pintype "input"))
      (node (ref "IC38") (pin "8") (pinfunction "SC3_8") (pintype "bidirectional"))
      (node (ref "R216") (pin "A1") (pinfunction "1_A1") (pintype "passive"))
    )
    (net (code "423") (name "TCA3_I2C_SDA") (class "Default")
      (node (ref "IC34") (pin "5") (pinfunction "SDA_5") (pintype "bidirectional"))
      (node (ref "IC37") (pin "5") (pinfunction "SDA_5") (pintype "bidirectional"))
      (node (ref "IC38") (pin "7") (pinfunction "SD3_7") (pintype "bidirectional"))
      (node (ref "R216") (pin "B1") (pinfunction "2_B1") (pintype "passive"))
    )
    (net (code "424") (name "TCA4_I2C_SCL") (class "Default")
      (node (ref "IC11") (pin "5") (pinfunction "SCL_5") (pintype "bidirectional"))
      (node (ref "IC13") (pin "5") (pinfunction "SCL_5") (pintype "bidirectional"))
      (node (ref "IC16") (pin "5") (pinfunction "SCL_5") (pintype "bidirectional"))
      (node (ref "IC19") (pin "5") (pinfunction "SCL_5") (pintype "bidirectional"))
      (node (ref "IC38") (pin "11") (pinfunction "SC4_11") (pintype "bidirectional"))
      (node (ref "R217") (pin "C1") (pinfunction "3_C1") (pintype "passive"))
    )
    (net (code "425") (name "TCA4_I2C_SDA") (class "Default")
      (node (ref "IC11") (pin "6") (pinfunction "SDA_6") (pintype "bidirectional"))
      (node (ref "IC13") (pin "6") (pinfunction "SDA_6") (pintype "bidirectional"))
      (node (ref "IC16") (pin "6") (pinfunction "SDA_6") (pintype "bidirectional"))
      (node (ref "IC19") (pin "6") (pinfunction "SDA_6") (pintype "bidirectional"))
      (node (ref "IC38") (pin "10") (pinfunction "SD4_10") (pintype "bidirectional"))
      (node (ref "R217") (pin "D1") (pinfunction "4_D1") (pintype "passive"))
    )
    (net (code "426") (name "TCA5_I2C_SCL") (class "Default")
      (node (ref "IC22") (pin "5") (pinfunction "SCL_5") (pintype "bidirectional"))
      (node (ref "IC25") (pin "5") (pinfunction "SCL_5") (pintype "bidirectional"))
      (node (ref "IC33") (pin "5") (pinfunction "SCL_5") (pintype "bidirectional"))
      (node (ref "IC36") (pin "5") (pinfunction "SCL_5") (pintype "bidirectional"))
      (node (ref "IC38") (pin "13") (pinfunction "SC5_13") (pintype "bidirectional"))
      (node (ref "R217") (pin "A1") (pinfunction "1_A1") (pintype "passive"))
    )
    (net (code "427") (name "TCA5_I2C_SDA") (class "Default")
      (node (ref "IC22") (pin "6") (pinfunction "SDA_6") (pintype "bidirectional"))
      (node (ref "IC25") (pin "6") (pinfunction "SDA_6") (pintype "bidirectional"))
      (node (ref "IC33") (pin "6") (pinfunction "SDA_6") (pintype "bidirectional"))
      (node (ref "IC36") (pin "6") (pinfunction "SDA_6") (pintype "bidirectional"))
      (node (ref "IC38") (pin "12") (pinfunction "SD5_12") (pintype "bidirectional"))
      (node (ref "R217") (pin "B1") (pinfunction "2_B1") (pintype "passive"))
    )
    (net (code "428") (name "TCA6_I2C_SCL") (class "Default")
      (node (ref "IC38") (pin "15") (pinfunction "SC6_15") (pintype "bidirectional"))
    )
    (net (code "429") (name "TCA6_I2C_SDA") (class "Default")
      (node (ref "IC38") (pin "14") (pinfunction "SD6_14") (pintype "bidirectional"))
    )
    (net (code "430") (name "TCA7_I2C_SCL") (class "Default")
      (node (ref "IC38") (pin "17") (pinfunction "SC7_17") (pintype "bidirectional"))
    )
    (net (code "431") (name "TCA7_I2C_SDA") (class "Default")
      (node (ref "IC38") (pin "16") (pinfunction "SD7_16") (pintype "bidirectional"))
    )
    (net (code "432") (name "TCT") (class "Default")
      (node (ref "C30") (pin "1") (pinfunction "1_1") (pintype "passive"))
      (node (ref "ETH1") (pin "2") (pinfunction "P4/TCT_2") (pintype "passive"))
      (node (ref "R35") (pin "1") (pinfunction "1_1") (pintype "passive"))
    )
    (net (code "433") (name "TD_N") (class "Default")
      (node (ref "ETH1") (pin "3") (pinfunction "TD-_3") (pintype "passive"))
      (node (ref "R279") (pin "2") (pinfunction "2_2") (pintype "passive"))
    )
    (net (code "434") (name "TD_P") (class "Default")
      (node (ref "ETH1") (pin "1") (pinfunction "TD+_1") (pintype "passive"))
      (node (ref "R280") (pin "2") (pinfunction "2_2") (pintype "passive"))
    )
    (net (code "435") (name "TD_R_N") (class "Default")
      (node (ref "R279") (pin "1") (pinfunction "1_1") (pintype "passive"))
      (node (ref "R38") (pin "2") (pinfunction "2_2") (pintype "passive"))
      (node (ref "R44") (pin "1") (pinfunction "1_1") (pintype "passive"))
    )
    (net (code "436") (name "TD_R_P") (class "Default")
      (node (ref "R280") (pin "1") (pinfunction "1_1") (pintype "passive"))
      (node (ref "R37") (pin "2") (pinfunction "2_2") (pintype "passive"))
      (node (ref "R43") (pin "1") (pinfunction "1_1") (pintype "passive"))
    )
    (net (code "437") (name "TX_TD_N") (class "Default")
      (node (ref "IC31") (pin "1") (pinfunction "TXN_1") (pintype "output"))
      (node (ref "R38") (pin "1") (pinfunction "1_1") (pintype "passive"))
    )
    (net (code "438") (name "TX_TD_P") (class "Default")
      (node (ref "IC31") (pin "2") (pinfunction "TXP_2") (pintype "output"))
      (node (ref "R37") (pin "1") (pinfunction "1_1") (pintype "passive"))
    )
    (net (code "439") (name "UART0_RX") (class "Default")
      (node (ref "IC26") (pin "78") (pinfunction "GPIO1_78") (pintype "bidirectional"))
      (node (ref "JTAG") (pin "6") (pinfunction "6_6") (pintype "passive"))
    )
    (net (code "440") (name "UART0_TX") (class "Default")
      (node (ref "IC26") (pin "77") (pinfunction "GPIO0_77") (pintype "bidirectional"))
      (node (ref "JTAG") (pin "8") (pinfunction "8_8") (pintype "passive"))
    )
    (net (code "441") (name "USBA1_EN") (class "Default")
      (node (ref "IC42") (pin "17") (pinfunction "IO1.0_17") (pintype "bidirectional"))
      (node (ref "IC8") (pin "3") (pinfunction "EN_3") (pintype "bidirectional"))
      (node (ref "R1") (pin "2") (pinfunction "2_2") (pintype "passive"))
    )
    (net (code "442") (name "USBA2_EN") (class "Default")
      (node (ref "IC1") (pin "3") (pinfunction "EN_3") (pintype "bidirectional"))
      (node (ref "IC42") (pin "18") (pinfunction "IO1.1_18") (pintype "bidirectional"))
      (node (ref "R4") (pin "2") (pinfunction "2_2") (pintype "passive"))
    )
    (net (code "443") (name "USBA3_EN") (class "Default")
      (node (ref "IC2") (pin "3") (pinfunction "EN_3") (pintype "bidirectional"))
      (node (ref "IC42") (pin "19") (pinfunction "IO1.2_19") (pintype "bidirectional"))
      (node (ref "R7") (pin "2") (pinfunction "2_2") (pintype "passive"))
    )
    (net (code "444") (name "USBA4_EN") (class "Default")
      (node (ref "IC3") (pin "3") (pinfunction "EN_3") (pintype "bidirectional"))
      (node (ref "IC42") (pin "20") (pinfunction "IO1.3_20") (pintype "bidirectional"))
      (node (ref "R10") (pin "2") (pinfunction "2_2") (pintype "passive"))
    )
    (net (code "445") (name "USB_BOOT") (class "Default")
      (node (ref "JTAG") (pin "7") (pinfunction "7_7") (pintype "passive"))
      (node (ref "R210") (pin "1") (pinfunction "1_1") (pintype "passive"))
      (node (ref "SW2") (pin "1") (pinfunction "P$1_1") (pintype "bidirectional"))
    )
    (net (code "446") (name "USB_RP_DP_N") (class "Default")
      (node (ref "ESD1") (pin "3") (pinfunction "C2_3") (pintype "bidirectional"))
      (node (ref "R25") (pin "1") (pinfunction "1_1") (pintype "passive"))
      (node (ref "USB9") (pin "A7") (pinfunction "D-_A7") (pintype "bidirectional"))
      (node (ref "USB9") (pin "B7") (pinfunction "D-_B7") (pintype "bidirectional"))
    )
    (net (code "447") (name "USB_RP_DP_P") (class "Default")
      (node (ref "ESD1") (pin "2") (pinfunction "C1_2") (pintype "bidirectional"))
      (node (ref "R26") (pin "1") (pinfunction "1_1") (pintype "passive"))
      (node (ref "USB9") (pin "A6") (pinfunction "D+_A6") (pintype "bidirectional"))
      (node (ref "USB9") (pin "B6") (pinfunction "D+_B6") (pintype "bidirectional"))
    )
    (net (code "448") (name "VBUS") (class "Default")
      (node (ref "C247") (pin "1") (pinfunction "1_1") (pintype "passive"))
      (node (ref "C248") (pin "1") (pinfunction "1_1") (pintype "passive"))
      (node (ref "ESD1") (pin "4") (pinfunction "C3_4") (pintype "bidirectional"))
      (node (ref "R249") (pin "1") (pinfunction "1_1") (pintype "passive"))
      (node (ref "R30") (pin "1") (pinfunction "1_1") (pintype "passive"))
      (node (ref "R31") (pin "1") (pinfunction "1_1") (pintype "passive"))
      (node (ref "USB9") (pin "VBUS1") (pinfunction "VBUS_VBUS1") (pintype "power_in"))
      (node (ref "USB9") (pin "VBUS2") (pinfunction "VBUS_VBUS2") (pintype "power_in"))
    )
    (net (code "449") (name "VBUS_USBA1") (class "Default")
      (node (ref "C83") (pin "1") (pinfunction "1_1") (pintype "passive"))
      (node (ref "C84") (pin "1") (pinfunction "1_1") (pintype "passive"))
      (node (ref "C85") (pin "1") (pinfunction "+_1") (pintype "passive"))
      (node (ref "IC8") (pin "6") (pinfunction "OUT_6") (pintype "bidirectional"))
      (node (ref "USBA_1-2") (pin "1") (pinfunction "VBUS_1") (pintype "passive"))
      (node (ref "VUSBA1") (pin "TP") (pinfunction "TP_TP") (pintype "input"))
    )
    (net (code "450") (name "VBUS_USBA2") (class "Default")
      (node (ref "C3") (pin "1") (pinfunction "1_1") (pintype "passive"))
      (node (ref "C4") (pin "1") (pinfunction "1_1") (pintype "passive"))
      (node (ref "C5") (pin "1") (pinfunction "+_1") (pintype "passive"))
      (node (ref "IC1") (pin "6") (pinfunction "OUT_6") (pintype "bidirectional"))
      (node (ref "USBA_1-2") (pin "5") (pinfunction "VBUS_5") (pintype "passive"))
      (node (ref "VUSBA2") (pin "TP") (pinfunction "TP_TP") (pintype "input"))
    )
    (net (code "451") (name "VBUS_USBA3") (class "Default")
      (node (ref "C10") (pin "1") (pinfunction "+_1") (pintype "passive"))
      (node (ref "C8") (pin "1") (pinfunction "1_1") (pintype "passive"))
      (node (ref "C9") (pin "1") (pinfunction "1_1") (pintype "passive"))
      (node (ref "IC2") (pin "6") (pinfunction "OUT_6") (pintype "bidirectional"))
      (node (ref "USBA_3-4") (pin "1") (pinfunction "VBUS_1") (pintype "passive"))
      (node (ref "VUSBA3") (pin "TP") (pinfunction "TP_TP") (pintype "input"))
    )
    (net (code "452") (name "VBUS_USBA4") (class "Default")
      (node (ref "C13") (pin "1") (pinfunction "1_1") (pintype "passive"))
      (node (ref "C14") (pin "1") (pinfunction "1_1") (pintype "passive"))
      (node (ref "C15") (pin "1") (pinfunction "+_1") (pintype "passive"))
      (node (ref "IC3") (pin "6") (pinfunction "OUT_6") (pintype "bidirectional"))
      (node (ref "USBA_3-4") (pin "5") (pinfunction "VBUS_5") (pintype "passive"))
      (node (ref "VUSBA4") (pin "TP") (pinfunction "TP_TP") (pintype "input"))
    )
    (net (code "453") (name "VOUT_PORT1") (class "Default")
      (node (ref "C217") (pin "1") (pinfunction "1_1") (pintype "passive"))
      (node (ref "C218") (pin "1") (pinfunction "+_1") (pintype "passive"))
      (node (ref "C51") (pin "1") (pinfunction "1_1") (pintype "passive"))
      (node (ref "C52") (pin "1") (pinfunction "1_1") (pintype "passive"))
      (node (ref "C53") (pin "1") (pinfunction "1_1") (pintype "passive"))
      (node (ref "C54") (pin "1") (pinfunction "1_1") (pintype "passive"))
      (node (ref "IC12") (pin "11") (pinfunction "VOUT_11") (pintype "power_in"))
      (node (ref "IC12") (pin "26") (pinfunction "VOUT_26") (pintype "power_in"))
      (node (ref "R228") (pin "2") (pinfunction "2_2") (pintype "passive"))
      (node (ref "R63") (pin "1") (pinfunction "1_1") (pintype "passive"))
    )
    (net (code "454") (name "VOUT_PORT2") (class "Default")
      (node (ref "C69") (pin "1") (pinfunction "1_1") (pintype "passive"))
      (node (ref "C70") (pin "1") (pinfunction "1_1") (pintype "passive"))
      (node (ref "C71") (pin "1") (pinfunction "1_1") (pintype "passive"))
      (node (ref "C72") (pin "1") (pinfunction "1_1") (pintype "passive"))
      (node (ref "C78") (pin "1") (pinfunction "1_1") (pintype "passive"))
      (node (ref "C79") (pin "1") (pinfunction "+_1") (pintype "passive"))
      (node (ref "IC10") (pin "11") (pinfunction "VOUT_11") (pintype "power_in"))
      (node (ref "IC10") (pin "26") (pinfunction "VOUT_26") (pintype "power_in"))
      (node (ref "R82") (pin "1") (pinfunction "1_1") (pintype "passive"))
      (node (ref "R86") (pin "2") (pinfunction "2_2") (pintype "passive"))
    )
    (net (code "455") (name "VOUT_PORT3") (class "Default")
      (node (ref "C100") (pin "1") (pinfunction "1_1") (pintype "passive"))
      (node (ref "C101") (pin "1") (pinfunction "1_1") (pintype "passive"))
      (node (ref "C107") (pin "1") (pinfunction "1_1") (pintype "passive"))
      (node (ref "C108") (pin "1") (pinfunction "+_1") (pintype "passive"))
      (node (ref "C98") (pin "1") (pinfunction "1_1") (pintype "passive"))
      (node (ref "C99") (pin "1") (pinfunction "1_1") (pintype "passive"))
      (node (ref "IC15") (pin "11") (pinfunction "VOUT_11") (pintype "power_in"))
      (node (ref "IC15") (pin "26") (pinfunction "VOUT_26") (pintype "power_in"))
      (node (ref "R109") (pin "1") (pinfunction "1_1") (pintype "passive"))
      (node (ref "R112") (pin "2") (pinfunction "2_2") (pintype "passive"))
    )
    (net (code "456") (name "VOUT_PORT4") (class "Default")
      (node (ref "C123") (pin "1") (pinfunction "1_1") (pintype "passive"))
      (node (ref "C124") (pin "1") (pinfunction "1_1") (pintype "passive"))
      (node (ref "C125") (pin "1") (pinfunction "1_1") (pintype "passive"))
      (node (ref "C126") (pin "1") (pinfunction "1_1") (pintype "passive"))
      (node (ref "C132") (pin "1") (pinfunction "1_1") (pintype "passive"))
      (node (ref "C133") (pin "1") (pinfunction "+_1") (pintype "passive"))
      (node (ref "IC18") (pin "11") (pinfunction "VOUT_11") (pintype "power_in"))
      (node (ref "IC18") (pin "26") (pinfunction "VOUT_26") (pintype "power_in"))
      (node (ref "R135") (pin "1") (pinfunction "1_1") (pintype "passive"))
      (node (ref "R138") (pin "2") (pinfunction "2_2") (pintype "passive"))
    )
    (net (code "457") (name "VOUT_PORT5") (class "Default")
      (node (ref "C148") (pin "1") (pinfunction "1_1") (pintype "passive"))
      (node (ref "C149") (pin "1") (pinfunction "1_1") (pintype "passive"))
      (node (ref "C150") (pin "1") (pinfunction "1_1") (pintype "passive"))
      (node (ref "C151") (pin "1") (pinfunction "1_1") (pintype "passive"))
      (node (ref "C157") (pin "1") (pinfunction "1_1") (pintype "passive"))
      (node (ref "C158") (pin "1") (pinfunction "+_1") (pintype "passive"))
      (node (ref "IC21") (pin "11") (pinfunction "VOUT_11") (pintype "power_in"))
      (node (ref "IC21") (pin "26") (pinfunction "VOUT_26") (pintype "power_in"))
      (node (ref "R161") (pin "1") (pinfunction "1_1") (pintype "passive"))
      (node (ref "R164") (pin "2") (pinfunction "2_2") (pintype "passive"))
    )
    (net (code "458") (name "VOUT_PORT6") (class "Default")
      (node (ref "C173") (pin "1") (pinfunction "1_1") (pintype "passive"))
      (node (ref "C174") (pin "1") (pinfunction "1_1") (pintype "passive"))
      (node (ref "C175") (pin "1") (pinfunction "1_1") (pintype "passive"))
      (node (ref "C197") (pin "1") (pinfunction "1_1") (pintype "passive"))
      (node (ref "C203") (pin "1") (pinfunction "1_1") (pintype "passive"))
      (node (ref "C204") (pin "1") (pinfunction "+_1") (pintype "passive"))
      (node (ref "IC24") (pin "11") (pinfunction "VOUT_11") (pintype "power_in"))
      (node (ref "IC24") (pin "26") (pinfunction "VOUT_26") (pintype "power_in"))
      (node (ref "R187") (pin "1") (pinfunction "1_1") (pintype "passive"))
      (node (ref "R190") (pin "2") (pinfunction "2_2") (pintype "passive"))
    )
    (net (code "459") (name "VOUT_PORT7") (class "Default")
      (node (ref "C242") (pin "1") (pinfunction "1_1") (pintype "passive"))
      (node (ref "C243") (pin "1") (pinfunction "1_1") (pintype "passive"))
      (node (ref "C244") (pin "1") (pinfunction "1_1") (pintype "passive"))
      (node (ref "C245") (pin "1") (pinfunction "1_1") (pintype "passive"))
      (node (ref "C261") (pin "1") (pinfunction "1_1") (pintype "passive"))
      (node (ref "C262") (pin "1") (pinfunction "+_1") (pintype "passive"))
      (node (ref "IC32") (pin "11") (pinfunction "VOUT_11") (pintype "power_in"))
      (node (ref "IC32") (pin "26") (pinfunction "VOUT_26") (pintype "power_in"))
      (node (ref "R234") (pin "1") (pinfunction "1_1") (pintype "passive"))
      (node (ref "R237") (pin "2") (pinfunction "2_2") (pintype "passive"))
    )
    (net (code "460") (name "VOUT_PORT8") (class "Default")
      (node (ref "C279") (pin "1") (pinfunction "1_1") (pintype "passive"))
      (node (ref "C280") (pin "1") (pinfunction "1_1") (pintype "passive"))
      (node (ref "C281") (pin "1") (pinfunction "1_1") (pintype "passive"))
      (node (ref "C282") (pin "1") (pinfunction "1_1") (pintype "passive"))
      (node (ref "C288") (pin "1") (pinfunction "1_1") (pintype "passive"))
      (node (ref "C289") (pin "1") (pinfunction "+_1") (pintype "passive"))
      (node (ref "IC35") (pin "11") (pinfunction "VOUT_11") (pintype "power_in"))
      (node (ref "IC35") (pin "26") (pinfunction "VOUT_26") (pintype "power_in"))
      (node (ref "R269") (pin "1") (pinfunction "1_1") (pintype "passive"))
      (node (ref "R272") (pin "2") (pinfunction "2_2") (pintype "passive"))
    )
    (net (code "461") (name "VSRC1") (class "Default")
      (node (ref "C39") (pin "1") (pinfunction "1_1") (pintype "passive"))
      (node (ref "IC9") (pin "1") (pinfunction "VDD_1") (pintype "power_in"))
      (node (ref "R229") (pin "2") (pinfunction "2_2") (pintype "passive"))
      (node (ref "R5") (pin "1") (pinfunction "1_1") (pintype "passive"))
      (node (ref "R53") (pin "1") (pinfunction "1_1") (pintype "passive"))
      (node (ref "R63") (pin "2") (pinfunction "2_2") (pintype "passive"))
      (node (ref "T6") (pin "1") (pinfunction "S_1") (pintype "passive"))
      (node (ref "T6") (pin "2") (pinfunction "S_2") (pintype "passive"))
      (node (ref "T6") (pin "3") (pinfunction "S_3") (pintype "passive"))
      (node (ref "T7") (pin "5") (pinfunction "D_5") (pintype "passive"))
      (node (ref "T7") (pin "6") (pinfunction "D_6") (pintype "passive"))
      (node (ref "T7") (pin "7") (pinfunction "D_7") (pintype "passive"))
      (node (ref "T7") (pin "8") (pinfunction "D_8") (pintype "passive"))
      (node (ref "T7") (pin "9") (pinfunction "D_9") (pintype "passive"))
    )
    (net (code "462") (name "VSRC2") (class "Default")
      (node (ref "C58") (pin "1") (pinfunction "1_1") (pintype "passive"))
      (node (ref "IC14") (pin "1") (pinfunction "VDD_1") (pintype "power_in"))
      (node (ref "R56") (pin "1") (pinfunction "1_1") (pintype "passive"))
      (node (ref "R73") (pin "1") (pinfunction "1_1") (pintype "passive"))
      (node (ref "R82") (pin "2") (pinfunction "2_2") (pintype "passive"))
      (node (ref "R87") (pin "2") (pinfunction "2_2") (pintype "passive"))
      (node (ref "T1") (pin "1") (pinfunction "S_1") (pintype "passive"))
      (node (ref "T1") (pin "2") (pinfunction "S_2") (pintype "passive"))
      (node (ref "T1") (pin "3") (pinfunction "S_3") (pintype "passive"))
      (node (ref "T2") (pin "5") (pinfunction "D_5") (pintype "passive"))
      (node (ref "T2") (pin "6") (pinfunction "D_6") (pintype "passive"))
      (node (ref "T2") (pin "7") (pinfunction "D_7") (pintype "passive"))
      (node (ref "T2") (pin "8") (pinfunction "D_8") (pintype "passive"))
      (node (ref "T2") (pin "9") (pinfunction "D_9") (pintype "passive"))
    )
    (net (code "463") (name "VSRC3") (class "Default")
      (node (ref "C87") (pin "1") (pinfunction "1_1") (pintype "passive"))
      (node (ref "IC17") (pin "1") (pinfunction "VDD_1") (pintype "power_in"))
      (node (ref "R100") (pin "1") (pinfunction "1_1") (pintype "passive"))
      (node (ref "R109") (pin "2") (pinfunction "2_2") (pintype "passive"))
      (node (ref "R113") (pin "2") (pinfunction "2_2") (pintype "passive"))
      (node (ref "R92") (pin "1") (pinfunction "1_1") (pintype "passive"))
      (node (ref "T11") (pin "1") (pinfunction "S_1") (pintype "passive"))
      (node (ref "T11") (pin "2") (pinfunction "S_2") (pintype "passive"))
      (node (ref "T11") (pin "3") (pinfunction "S_3") (pintype "passive"))
      (node (ref "T12") (pin "5") (pinfunction "D_5") (pintype "passive"))
      (node (ref "T12") (pin "6") (pinfunction "D_6") (pintype "passive"))
      (node (ref "T12") (pin "7") (pinfunction "D_7") (pintype "passive"))
      (node (ref "T12") (pin "8") (pinfunction "D_8") (pintype "passive"))
      (node (ref "T12") (pin "9") (pinfunction "D_9") (pintype "passive"))
    )
    (net (code "464") (name "VSRC4") (class "Default")
      (node (ref "C112") (pin "1") (pinfunction "1_1") (pintype "passive"))
      (node (ref "IC20") (pin "1") (pinfunction "VDD_1") (pintype "power_in"))
      (node (ref "R118") (pin "1") (pinfunction "1_1") (pintype "passive"))
      (node (ref "R126") (pin "1") (pinfunction "1_1") (pintype "passive"))
      (node (ref "R135") (pin "2") (pinfunction "2_2") (pintype "passive"))
      (node (ref "R139") (pin "2") (pinfunction "2_2") (pintype "passive"))
      (node (ref "T16") (pin "1") (pinfunction "S_1") (pintype "passive"))
      (node (ref "T16") (pin "2") (pinfunction "S_2") (pintype "passive"))
      (node (ref "T16") (pin "3") (pinfunction "S_3") (pintype "passive"))
      (node (ref "T17") (pin "5") (pinfunction "D_5") (pintype "passive"))
      (node (ref "T17") (pin "6") (pinfunction "D_6") (pintype "passive"))
      (node (ref "T17") (pin "7") (pinfunction "D_7") (pintype "passive"))
      (node (ref "T17") (pin "8") (pinfunction "D_8") (pintype "passive"))
      (node (ref "T17") (pin "9") (pinfunction "D_9") (pintype "passive"))
    )
    (net (code "465") (name "VSRC5") (class "Default")
      (node (ref "C137") (pin "1") (pinfunction "1_1") (pintype "passive"))
      (node (ref "IC23") (pin "1") (pinfunction "VDD_1") (pintype "power_in"))
      (node (ref "R144") (pin "1") (pinfunction "1_1") (pintype "passive"))
      (node (ref "R152") (pin "1") (pinfunction "1_1") (pintype "passive"))
      (node (ref "R161") (pin "2") (pinfunction "2_2") (pintype "passive"))
      (node (ref "R165") (pin "2") (pinfunction "2_2") (pintype "passive"))
      (node (ref "T21") (pin "1") (pinfunction "S_1") (pintype "passive"))
      (node (ref "T21") (pin "2") (pinfunction "S_2") (pintype "passive"))
      (node (ref "T21") (pin "3") (pinfunction "S_3") (pintype "passive"))
      (node (ref "T22") (pin "5") (pinfunction "D_5") (pintype "passive"))
      (node (ref "T22") (pin "6") (pinfunction "D_6") (pintype "passive"))
      (node (ref "T22") (pin "7") (pinfunction "D_7") (pintype "passive"))
      (node (ref "T22") (pin "8") (pinfunction "D_8") (pintype "passive"))
      (node (ref "T22") (pin "9") (pinfunction "D_9") (pintype "passive"))
    )
    (net (code "466") (name "VSRC6") (class "Default")
      (node (ref "C162") (pin "1") (pinfunction "1_1") (pintype "passive"))
      (node (ref "IC30") (pin "1") (pinfunction "VDD_1") (pintype "power_in"))
      (node (ref "R170") (pin "1") (pinfunction "1_1") (pintype "passive"))
      (node (ref "R178") (pin "1") (pinfunction "1_1") (pintype "passive"))
      (node (ref "R187") (pin "2") (pinfunction "2_2") (pintype "passive"))
      (node (ref "R191") (pin "2") (pinfunction "2_2") (pintype "passive"))
      (node (ref "T26") (pin "1") (pinfunction "S_1") (pintype "passive"))
      (node (ref "T26") (pin "2") (pinfunction "S_2") (pintype "passive"))
      (node (ref "T26") (pin "3") (pinfunction "S_3") (pintype "passive"))
      (node (ref "T27") (pin "5") (pinfunction "D_5") (pintype "passive"))
      (node (ref "T27") (pin "6") (pinfunction "D_6") (pintype "passive"))
      (node (ref "T27") (pin "7") (pinfunction "D_7") (pintype "passive"))
      (node (ref "T27") (pin "8") (pinfunction "D_8") (pintype "passive"))
      (node (ref "T27") (pin "9") (pinfunction "D_9") (pintype "passive"))
    )
    (net (code "467") (name "VSRC7") (class "Default")
      (node (ref "C208") (pin "1") (pinfunction "1_1") (pintype "passive"))
      (node (ref "IC34") (pin "1") (pinfunction "VDD_1") (pintype "power_in"))
      (node (ref "R196") (pin "1") (pinfunction "1_1") (pintype "passive"))
      (node (ref "R204") (pin "1") (pinfunction "1_1") (pintype "passive"))
      (node (ref "R234") (pin "2") (pinfunction "2_2") (pintype "passive"))
      (node (ref "R238") (pin "2") (pinfunction "2_2") (pintype "passive"))
      (node (ref "T31") (pin "1") (pinfunction "S_1") (pintype "passive"))
      (node (ref "T31") (pin "2") (pinfunction "S_2") (pintype "passive"))
      (node (ref "T31") (pin "3") (pinfunction "S_3") (pintype "passive"))
      (node (ref "T32") (pin "5") (pinfunction "D_5") (pintype "passive"))
      (node (ref "T32") (pin "6") (pinfunction "D_6") (pintype "passive"))
      (node (ref "T32") (pin "7") (pinfunction "D_7") (pintype "passive"))
      (node (ref "T32") (pin "8") (pinfunction "D_8") (pintype "passive"))
      (node (ref "T32") (pin "9") (pinfunction "D_9") (pintype "passive"))
    )
    (net (code "468") (name "VSRC8") (class "Default")
      (node (ref "C267") (pin "1") (pinfunction "1_1") (pintype "passive"))
      (node (ref "IC37") (pin "1") (pinfunction "VDD_1") (pintype "power_in"))
      (node (ref "R247") (pin "1") (pinfunction "1_1") (pintype "passive"))
      (node (ref "R260") (pin "1") (pinfunction "1_1") (pintype "passive"))
      (node (ref "R269") (pin "2") (pinfunction "2_2") (pintype "passive"))
      (node (ref "R273") (pin "2") (pinfunction "2_2") (pintype "passive"))
      (node (ref "T36") (pin "1") (pinfunction "S_1") (pintype "passive"))
      (node (ref "T36") (pin "2") (pinfunction "S_2") (pintype "passive"))
      (node (ref "T36") (pin "3") (pinfunction "S_3") (pintype "passive"))
      (node (ref "T37") (pin "5") (pinfunction "D_5") (pintype "passive"))
      (node (ref "T37") (pin "6") (pinfunction "D_6") (pintype "passive"))
      (node (ref "T37") (pin "7") (pinfunction "D_7") (pintype "passive"))
      (node (ref "T37") (pin "8") (pinfunction "D_8") (pintype "passive"))
      (node (ref "T37") (pin "9") (pinfunction "D_9") (pintype "passive"))
    )
    (net (code "469") (name "VUSB") (class "Default")
      (node (ref "R30") (pin "2") (pinfunction "2_2") (pintype "passive"))
    )
    (net (code "470") (name "W5500_MISO") (class "Default")
      (node (ref "IC26") (pin "16") (pinfunction "GPIO16_16") (pintype "bidirectional"))
      (node (ref "IC31") (pin "34") (pinfunction "MISO_34") (pintype "output"))
    )
    (net (code "471") (name "W5500_MOSI") (class "Default")
      (node (ref "IC26") (pin "19") (pinfunction "GPIO19_19") (pintype "bidirectional"))
      (node (ref "IC31") (pin "35") (pinfunction "MOSI_35") (pintype "input"))
    )
    (net (code "472") (name "W5500_SCK") (class "Default")
      (node (ref "IC26") (pin "18") (pinfunction "GPIO18_18") (pintype "bidirectional"))
      (node (ref "IC31") (pin "33") (pinfunction "SCLK_33") (pintype "input"))
    )
    (net (code "473") (name "unconnected-(DISP-Pad15)") (class "Default")
      (node (ref "DISP") (pin "15") (pinfunction "15_15") (pintype "bidirectional"))
    )
    (net (code "474") (name "unconnected-(DISP-Pad16)") (class "Default")
      (node (ref "DISP") (pin "16") (pinfunction "16_16") (pintype "bidirectional"))
    )
    (net (code "475") (name "unconnected-(DISP-Pad17)") (class "Default")
      (node (ref "DISP") (pin "17") (pinfunction "17_17") (pintype "bidirectional"))
    )
    (net (code "476") (name "unconnected-(DISP-Pad18)") (class "Default")
      (node (ref "DISP") (pin "18") (pinfunction "18_18") (pintype "bidirectional"))
    )
    (net (code "477") (name "unconnected-(DISP-Pad19)") (class "Default")
      (node (ref "DISP") (pin "19") (pinfunction "19_19") (pintype "bidirectional"))
    )
    (net (code "478") (name "unconnected-(IC10-CC_N-Pad6)") (class "Default")
      (node (ref "IC10") (pin "6") (pinfunction "CC_N_6") (pintype "output"))
    )
    (net (code "479") (name "unconnected-(IC10-PG-Pad5)") (class "Default")
      (node (ref "IC10") (pin "5") (pinfunction "PG_5") (pintype "output"))
    )
    (net (code "480") (name "unconnected-(IC12-CC_N-Pad6)") (class "Default")
      (node (ref "IC12") (pin "6") (pinfunction "CC_N_6") (pintype "output"))
    )
    (net (code "481") (name "unconnected-(IC12-PG-Pad5)") (class "Default")
      (node (ref "IC12") (pin "5") (pinfunction "PG_5") (pintype "output"))
    )
    (net (code "482") (name "unconnected-(IC15-CC_N-Pad6)") (class "Default")
      (node (ref "IC15") (pin "6") (pinfunction "CC_N_6") (pintype "output"))
    )
    (net (code "483") (name "unconnected-(IC15-PG-Pad5)") (class "Default")
      (node (ref "IC15") (pin "5") (pinfunction "PG_5") (pintype "output"))
    )
    (net (code "484") (name "unconnected-(IC18-CC_N-Pad6)") (class "Default")
      (node (ref "IC18") (pin "6") (pinfunction "CC_N_6") (pintype "output"))
    )
    (net (code "485") (name "unconnected-(IC18-PG-Pad5)") (class "Default")
      (node (ref "IC18") (pin "5") (pinfunction "PG_5") (pintype "output"))
    )
    (net (code "486") (name "unconnected-(IC21-CC_N-Pad6)") (class "Default")
      (node (ref "IC21") (pin "6") (pinfunction "CC_N_6") (pintype "output"))
    )
    (net (code "487") (name "unconnected-(IC21-PG-Pad5)") (class "Default")
      (node (ref "IC21") (pin "5") (pinfunction "PG_5") (pintype "output"))
    )
    (net (code "488") (name "unconnected-(IC24-CC_N-Pad6)") (class "Default")
      (node (ref "IC24") (pin "6") (pinfunction "CC_N_6") (pintype "output"))
    )
    (net (code "489") (name "unconnected-(IC24-PG-Pad5)") (class "Default")
      (node (ref "IC24") (pin "5") (pinfunction "PG_5") (pintype "output"))
    )
    (net (code "490") (name "unconnected-(IC26A-GPIO2-Pad79)") (class "Default")
      (node (ref "IC26") (pin "79") (pinfunction "GPIO2_79") (pintype "bidirectional"))
    )
    (net (code "491") (name "unconnected-(IC26A-GPIO3-Pad80)") (class "Default")
      (node (ref "IC26") (pin "80") (pinfunction "GPIO3_80") (pintype "bidirectional"))
    )
    (net (code "492") (name "unconnected-(IC26A-GPIO9-Pad7)") (class "Default")
      (node (ref "IC26") (pin "7") (pinfunction "GPIO9_7") (pintype "bidirectional"))
    )
    (net (code "493") (name "unconnected-(IC26A-GPIO10-Pad8)") (class "Default")
      (node (ref "IC26") (pin "8") (pinfunction "GPIO10_8") (pintype "bidirectional"))
    )
    (net (code "494") (name "unconnected-(IC26A-GPIO11-Pad9)") (class "Default")
      (node (ref "IC26") (pin "9") (pinfunction "GPIO11_9") (pintype "bidirectional"))
    )
    (net (code "495") (name "unconnected-(IC26A-GPIO22-Pad22)") (class "Default")
      (node (ref "IC26") (pin "22") (pinfunction "GPIO22_22") (pintype "bidirectional"))
    )
    (net (code "496") (name "unconnected-(IC26A-GPIO23-Pad23)") (class "Default")
      (node (ref "IC26") (pin "23") (pinfunction "GPIO23_23") (pintype "bidirectional"))
    )
    (net (code "497") (name "unconnected-(IC26A-GPIO28-Pad36)") (class "Default")
      (node (ref "IC26") (pin "36") (pinfunction "GPIO28_36") (pintype "bidirectional"))
    )
    (net (code "498") (name "unconnected-(IC26A-GPIO29-Pad37)") (class "Default")
      (node (ref "IC26") (pin "37") (pinfunction "GPIO29_37") (pintype "bidirectional"))
    )
    (net (code "499") (name "unconnected-(IC26B-GPIO30-Pad38)") (class "Default")
      (node (ref "IC26") (pin "38") (pinfunction "GPIO30_38") (pintype "bidirectional"))
    )
    (net (code "500") (name "unconnected-(IC26B-GPIO31-Pad39)") (class "Default")
      (node (ref "IC26") (pin "39") (pinfunction "GPIO31_39") (pintype "bidirectional"))
    )
    (net (code "501") (name "unconnected-(IC26B-GPIO32-Pad40)") (class "Default")
      (node (ref "IC26") (pin "40") (pinfunction "GPIO32_40") (pintype "bidirectional"))
    )
    (net (code "502") (name "unconnected-(IC26B-GPIO33-Pad42)") (class "Default")
      (node (ref "IC26") (pin "42") (pinfunction "GPIO33_42") (pintype "bidirectional"))
    )
    (net (code "503") (name "unconnected-(IC26B-GPIO34-Pad43)") (class "Default")
      (node (ref "IC26") (pin "43") (pinfunction "GPIO34_43") (pintype "bidirectional"))
    )
    (net (code "504") (name "unconnected-(IC26B-GPIO35-Pad44)") (class "Default")
      (node (ref "IC26") (pin "44") (pinfunction "GPIO35_44") (pintype "bidirectional"))
    )
    (net (code "505") (name "unconnected-(IC26B-GPIO36-Pad45)") (class "Default")
      (node (ref "IC26") (pin "45") (pinfunction "GPIO36_45") (pintype "bidirectional"))
    )
    (net (code "506") (name "unconnected-(IC26B-GPIO37-Pad46)") (class "Default")
      (node (ref "IC26") (pin "46") (pinfunction "GPIO37_46") (pintype "bidirectional"))
    )
    (net (code "507") (name "unconnected-(IC26B-GPIO38-Pad47)") (class "Default")
      (node (ref "IC26") (pin "47") (pinfunction "GPIO38_47") (pintype "bidirectional"))
    )
    (net (code "508") (name "unconnected-(IC26B-GPIO39-Pad48)") (class "Default")
      (node (ref "IC26") (pin "48") (pinfunction "GPIO39_48") (pintype "bidirectional"))
    )
    (net (code "509") (name "unconnected-(IC26B-GPIO40_ADC0-Pad49)") (class "Default")
      (node (ref "IC26") (pin "49") (pinfunction "GPIO40_ADC0_49") (pintype "bidirectional"))
    )
    (net (code "510") (name "unconnected-(IC26B-GPIO41_ADC1-Pad52)") (class "Default")
      (node (ref "IC26") (pin "52") (pinfunction "GPIO41_ADC1_52") (pintype "bidirectional"))
    )
    (net (code "511") (name "unconnected-(IC26B-GPIO42_ADC2-Pad53)") (class "Default")
      (node (ref "IC26") (pin "53") (pinfunction "GPIO42_ADC2_53") (pintype "bidirectional"))
    )
    (net (code "512") (name "unconnected-(IC26B-GPIO43_ADC3-Pad54)") (class "Default")
      (node (ref "IC26") (pin "54") (pinfunction "GPIO43_ADC3_54") (pintype "bidirectional"))
    )
    (net (code "513") (name "unconnected-(IC26B-GPIO44_ADC4-Pad55)") (class "Default")
      (node (ref "IC26") (pin "55") (pinfunction "GPIO44_ADC4_55") (pintype "bidirectional"))
    )
    (net (code "514") (name "unconnected-(IC26B-GPIO45_ADC5-Pad56)") (class "Default")
      (node (ref "IC26") (pin "56") (pinfunction "GPIO45_ADC5_56") (pintype "bidirectional"))
    )
    (net (code "515") (name "unconnected-(IC26B-GPIO46_ADC6-Pad57)") (class "Default")
      (node (ref "IC26") (pin "57") (pinfunction "GPIO46_ADC6_57") (pintype "bidirectional"))
    )
    (net (code "516") (name "unconnected-(IC26B-GPIO47_ADC7-Pad58)") (class "Default")
      (node (ref "IC26") (pin "58") (pinfunction "GPIO47_ADC7_58") (pintype "bidirectional"))
    )
    (net (code "517") (name "unconnected-(IC31-DNC-Pad7)") (class "Default")
      (node (ref "IC31") (pin "7") (pinfunction "DNC_7") (pintype "bidirectional"))
    )
    (net (code "518") (name "unconnected-(IC31-RSVD1-Pad23)") (class "Default")
      (node (ref "IC31") (pin "23") (pinfunction "RSVD1_23") (pintype "input"))
    )
    (net (code "519") (name "unconnected-(IC31-RSVD2-Pad38)") (class "Default")
      (node (ref "IC31") (pin "38") (pinfunction "RSVD2_38") (pintype "input"))
    )
    (net (code "520") (name "unconnected-(IC31-RSVD3-Pad39)") (class "Default")
      (node (ref "IC31") (pin "39") (pinfunction "RSVD3_39") (pintype "input"))
    )
    (net (code "521") (name "unconnected-(IC31-RSVD4-Pad40)") (class "Default")
      (node (ref "IC31") (pin "40") (pinfunction "RSVD4_40") (pintype "input"))
    )
    (net (code "522") (name "unconnected-(IC31-RSVD5-Pad41)") (class "Default")
      (node (ref "IC31") (pin "41") (pinfunction "RSVD5_41") (pintype "input"))
    )
    (net (code "523") (name "unconnected-(IC31-RSVD6-Pad42)") (class "Default")
      (node (ref "IC31") (pin "42") (pinfunction "RSVD6_42") (pintype "input"))
    )
    (net (code "524") (name "unconnected-(IC31-VBG-Pad18)") (class "Default")
      (node (ref "IC31") (pin "18") (pinfunction "VBG_18") (pintype "output"))
    )
    (net (code "525") (name "unconnected-(IC32-CC_N-Pad6)") (class "Default")
      (node (ref "IC32") (pin "6") (pinfunction "CC_N_6") (pintype "output"))
    )
    (net (code "526") (name "unconnected-(IC32-PG-Pad5)") (class "Default")
      (node (ref "IC32") (pin "5") (pinfunction "PG_5") (pintype "output"))
    )
    (net (code "527") (name "unconnected-(IC35-CC_N-Pad6)") (class "Default")
      (node (ref "IC35") (pin "6") (pinfunction "CC_N_6") (pintype "output"))
    )
    (net (code "528") (name "unconnected-(IC35-PG-Pad5)") (class "Default")
      (node (ref "IC35") (pin "5") (pinfunction "PG_5") (pintype "output"))
    )
    (net (code "529") (name "unconnected-(IC42-INTA-Pad16)") (class "Default")
      (node (ref "IC42") (pin "16") (pinfunction "INTA_16") (pintype "bidirectional"))
    )
    (net (code "530") (name "unconnected-(IC42-INTB-Pad15)") (class "Default")
      (node (ref "IC42") (pin "15") (pinfunction "INTB_15") (pintype "bidirectional"))
    )
    (net (code "531") (name "unconnected-(USB9-SBU1-PadA8)") (class "Default")
      (node (ref "USB9") (pin "A8") (pinfunction "SBU1_A8") (pintype "bidirectional"))
    )
    (net (code "532") (name "unconnected-(USB9-SBU2-PadB8)") (class "Default")
      (node (ref "USB9") (pin "B8") (pinfunction "SBU2_B8") (pintype "bidirectional"))
    )
    (net (code "533") (name "unconnected-(USBA_1-2A-D+-Pad3)") (class "Default")
      (node (ref "USBA_1-2") (pin "3") (pinfunction "D+_3") (pintype "passive"))
    )
    (net (code "534") (name "unconnected-(USBA_1-2A-D--Pad2)") (class "Default")
      (node (ref "USBA_1-2") (pin "2") (pinfunction "D-_2") (pintype "passive"))
    )
    (net (code "535") (name "unconnected-(USBA_1-2B-D+-Pad7)") (class "Default")
      (node (ref "USBA_1-2") (pin "7") (pinfunction "D+_7") (pintype "passive"))
    )
    (net (code "536") (name "unconnected-(USBA_1-2B-D--Pad6)") (class "Default")
      (node (ref "USBA_1-2") (pin "6") (pinfunction "D-_6") (pintype "passive"))
    )
    (net (code "537") (name "unconnected-(USBA_3-4A-D+-Pad3)") (class "Default")
      (node (ref "USBA_3-4") (pin "3") (pinfunction "D+_3") (pintype "passive"))
    )
    (net (code "538") (name "unconnected-(USBA_3-4A-D--Pad2)") (class "Default")
      (node (ref "USBA_3-4") (pin "2") (pinfunction "D-_2") (pintype "passive"))
    )
    (net (code "539") (name "unconnected-(USBA_3-4B-D+-Pad7)") (class "Default")
      (node (ref "USBA_3-4") (pin "7") (pinfunction "D+_7") (pintype "passive"))
    )
    (net (code "540") (name "unconnected-(USBA_3-4B-D--Pad6)") (class "Default")
      (node (ref "USBA_3-4") (pin "6") (pinfunction "D-_6") (pintype "passive"))
    )
    (net (code "541") (name "~{ACT}") (class "Default")
      (node (ref "IC31") (pin "27") (pinfunction "ACTLED_27") (pintype "output"))
      (node (ref "R34") (pin "1") (pinfunction "1_1") (pintype "passive"))
    )
    (net (code "542") (name "~{DUP}") (class "Default")
      (node (ref "IC31") (pin "26") (pinfunction "DUPLED_26") (pintype "output"))
      (node (ref "R227") (pin "1") (pinfunction "1_1") (pintype "passive"))
    )
    (net (code "543") (name "~{LINK}") (class "Default")
      (node (ref "IC31") (pin "25") (pinfunction "LINKLED_25") (pintype "output"))
      (node (ref "R33") (pin "1") (pinfunction "1_1") (pintype "passive"))
    )
    (net (code "544") (name "~{QSPI_SS}") (class "Default")
      (node (ref "IC26") (pin "75") (pinfunction "QSPI_SS_75") (pintype "output"))
      (node (ref "IC27") (pin "1") (pinfunction "~{CS}_1") (pintype "bidirectional"))
      (node (ref "R209") (pin "1") (pinfunction "1_1") (pintype "passive"))
      (node (ref "R210") (pin "2") (pinfunction "2_2") (pintype "passive"))
    )
    (net (code "545") (name "~{SPD}") (class "Default")
      (node (ref "IC31") (pin "24") (pinfunction "SPDLED_24") (pintype "output"))
      (node (ref "R226") (pin "1") (pinfunction "1_1") (pintype "passive"))
    )
    (net (code "546") (name "~{TCA_RST}") (class "Default")
      (node (ref "IC38") (pin "24") (pinfunction "RESET_24") (pintype "input"))
    )
    (net (code "547") (name "~{W5500_CS}") (class "Default")
      (node (ref "IC26") (pin "17") (pinfunction "GPIO17_17") (pintype "bidirectional"))
      (node (ref "IC31") (pin "32") (pinfunction "~{SCSN}_32") (pintype "input"))
    )
    (net (code "548") (name "~{W5500_INT}") (class "Default")
      (node (ref "IC26") (pin "21") (pinfunction "GPIO21_21") (pintype "bidirectional"))
      (node (ref "IC31") (pin "36") (pinfunction "~{INTN}_36") (pintype "input"))
    )
    (net (code "549") (name "~{W5500_RST}") (class "Default")
      (node (ref "IC26") (pin "20") (pinfunction "GPIO20_20") (pintype "bidirectional"))
      (node (ref "IC31") (pin "37") (pinfunction "~{RSTN}_37") (pintype "input"))
      (node (ref "R206") (pin "1") (pinfunction "1_1") (pintype "passive"))
    )
  )
)
